# ZabavySign.net
KiCad netlist of a schematic drawn in EAGLE
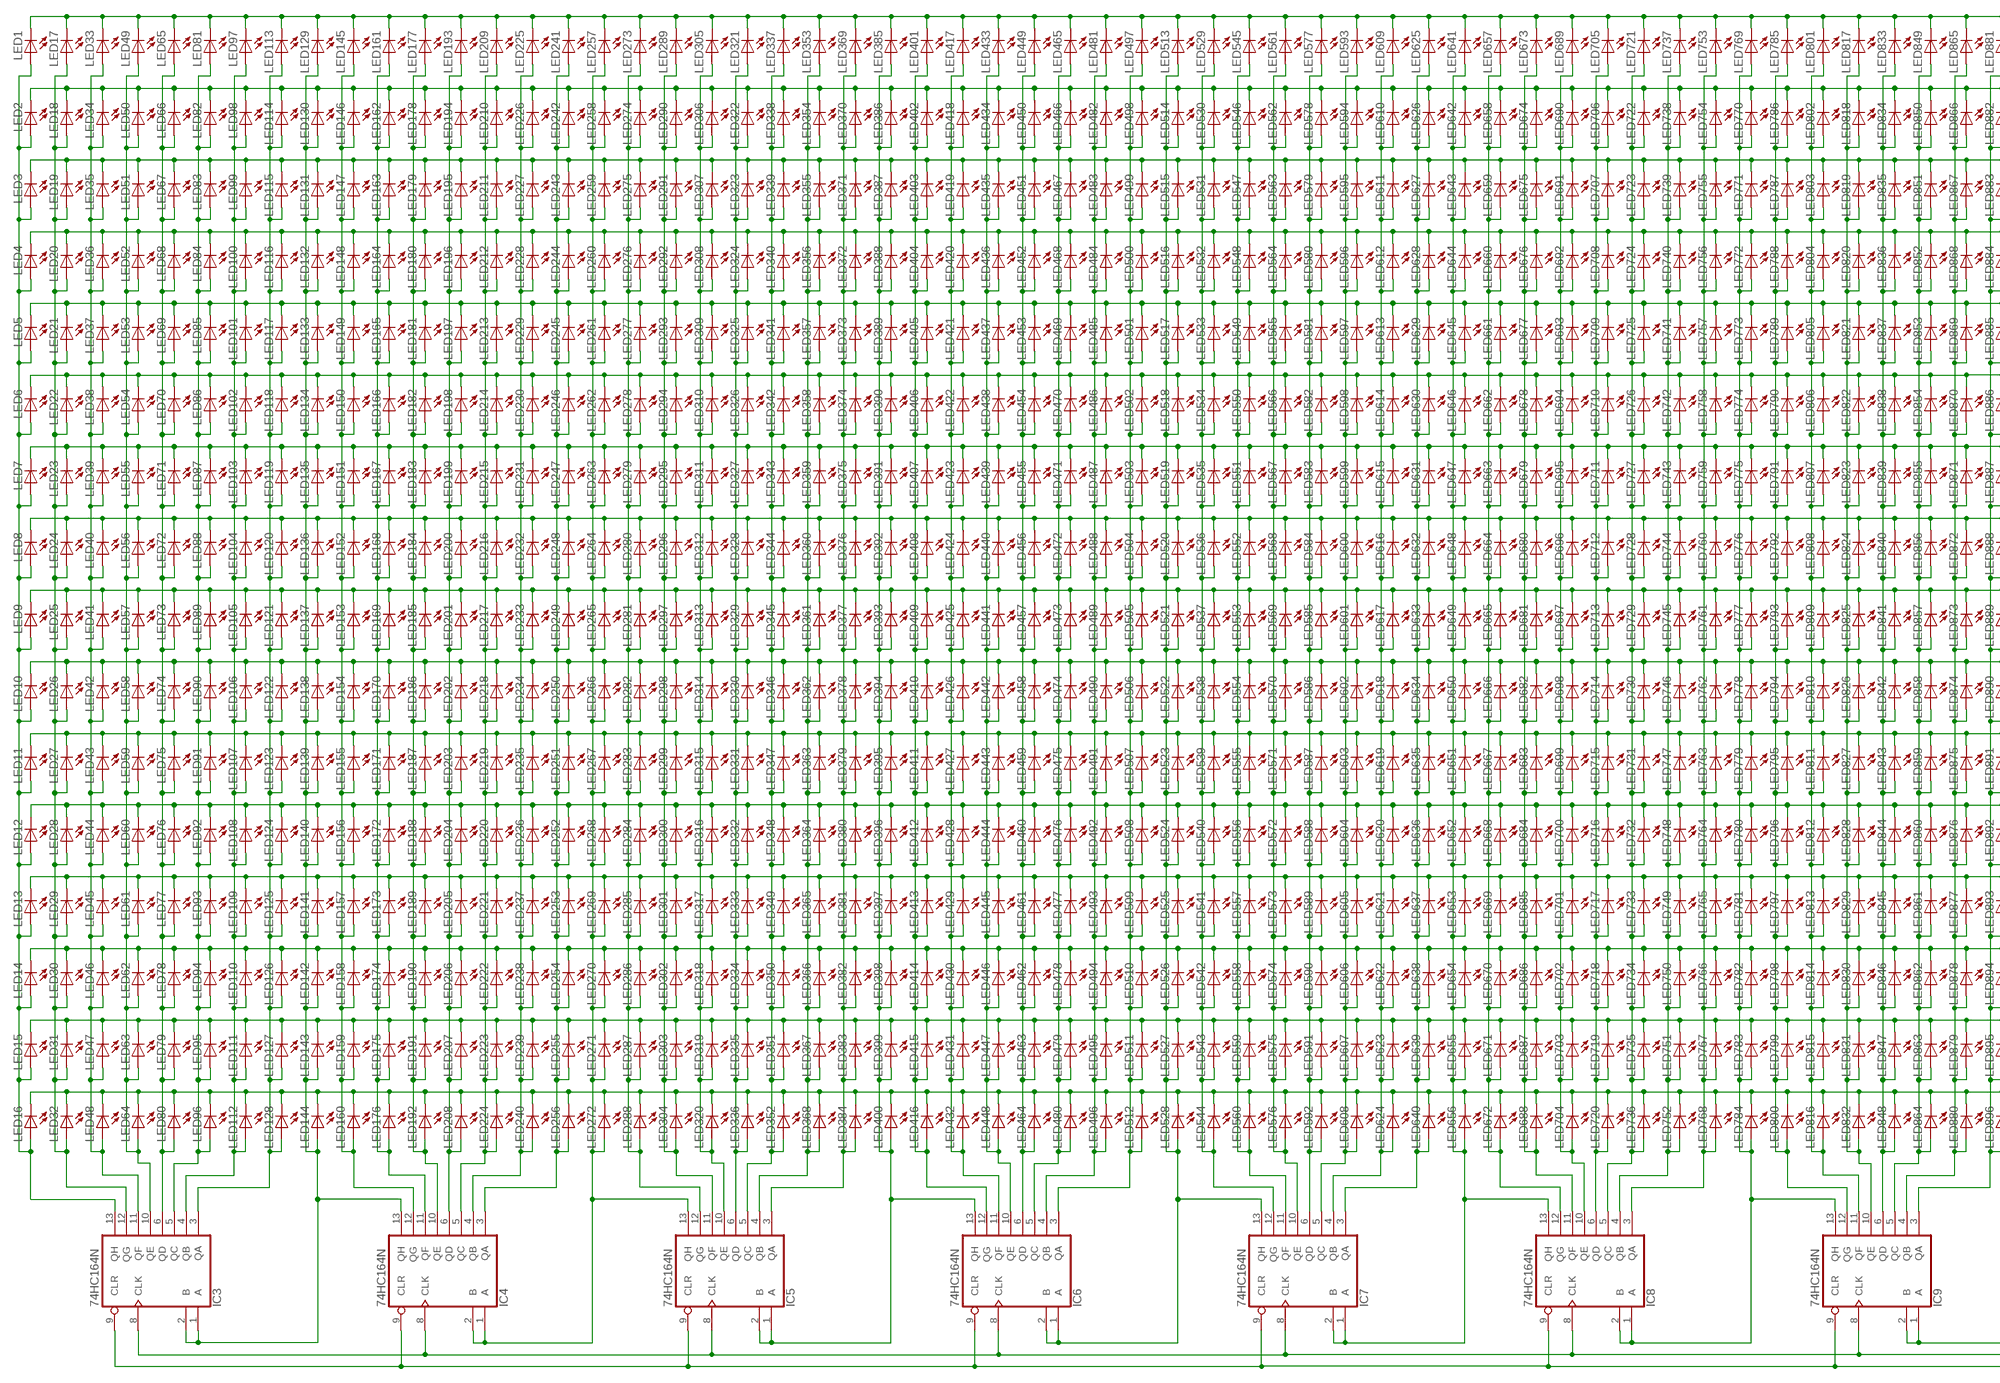
[diagram p0: schematic, sheet 1, part 1 of 2]
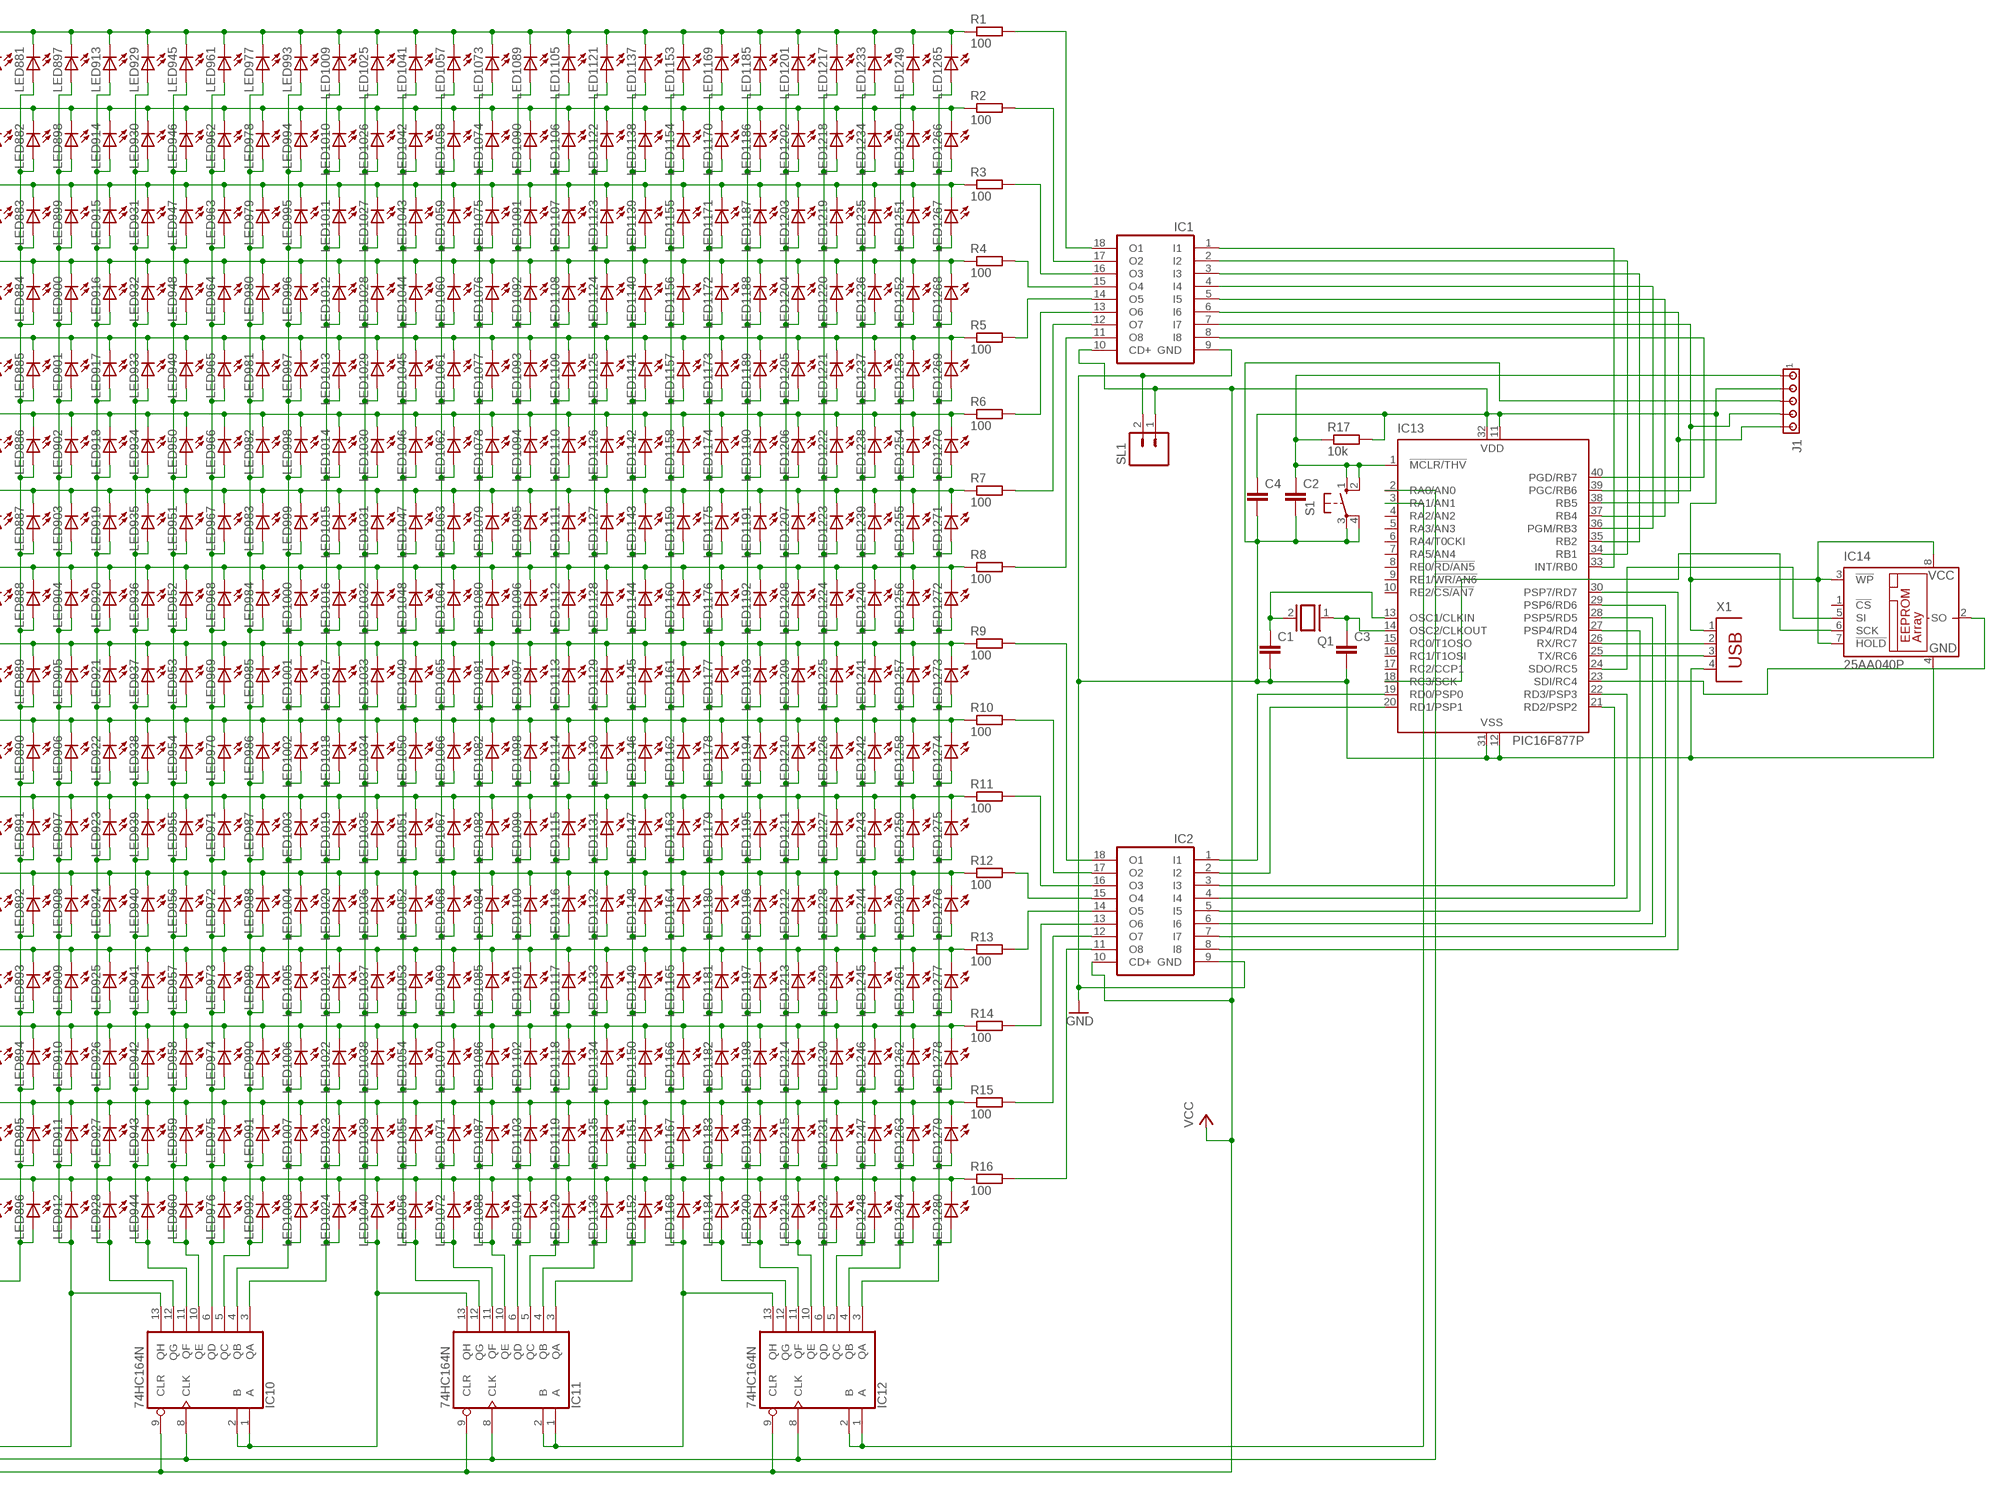
[diagram p1: schematic, sheet 1, part 2 of 2]

(export (version "E")
  (design (tool "Eeschema 10.0.6"))
  (components
    (comp (ref "C1")
      (value "C-EU050-024X044")
      (footprint "eagle-import:C050-024X044")
      (libsource (lib "eagle-import") (part "C-EU050-024X044"))
    )
    (comp (ref "C2")
      (value "C-EU050-024X044")
      (footprint "eagle-import:C050-024X044")
      (libsource (lib "eagle-import") (part "C-EU050-024X044"))
    )
    (comp (ref "C3")
      (value "C-EU050-024X044")
      (footprint "eagle-import:C050-024X044")
      (libsource (lib "eagle-import") (part "C-EU050-024X044"))
    )
    (comp (ref "C4")
      (value "C-EU050-024X044")
      (footprint "eagle-import:C050-024X044")
      (libsource (lib "eagle-import") (part "C-EU050-024X044"))
    )
    (comp (ref "IC1")
      (value "ULN2803A")
      (footprint "eagle-import:DIL18")
      (libsource (lib "eagle-import") (part "ULN2803A"))
    )
    (comp (ref "IC2")
      (value "ULN2803A")
      (footprint "eagle-import:DIL18")
      (libsource (lib "eagle-import") (part "ULN2803A"))
    )
    (comp (ref "IC3")
      (value "74HC164N")
      (footprint "eagle-import:DIL14")
      (libsource (lib "eagle-import") (part "74164NHC"))
    )
    (comp (ref "IC4")
      (value "74HC164N")
      (footprint "eagle-import:DIL14")
      (libsource (lib "eagle-import") (part "74164NHC"))
    )
    (comp (ref "IC5")
      (value "74HC164N")
      (footprint "eagle-import:DIL14")
      (libsource (lib "eagle-import") (part "74164NHC"))
    )
    (comp (ref "IC6")
      (value "74HC164N")
      (footprint "eagle-import:DIL14")
      (libsource (lib "eagle-import") (part "74164NHC"))
    )
    (comp (ref "IC7")
      (value "74HC164N")
      (footprint "eagle-import:DIL14")
      (libsource (lib "eagle-import") (part "74164NHC"))
    )
    (comp (ref "IC8")
      (value "74HC164N")
      (footprint "eagle-import:DIL14")
      (libsource (lib "eagle-import") (part "74164NHC"))
    )
    (comp (ref "IC9")
      (value "74HC164N")
      (footprint "eagle-import:DIL14")
      (libsource (lib "eagle-import") (part "74164NHC"))
    )
    (comp (ref "IC10")
      (value "74HC164N")
      (footprint "eagle-import:DIL14")
      (libsource (lib "eagle-import") (part "74164NHC"))
    )
    (comp (ref "IC11")
      (value "74HC164N")
      (footprint "eagle-import:DIL14")
      (libsource (lib "eagle-import") (part "74164NHC"))
    )
    (comp (ref "IC12")
      (value "74HC164N")
      (footprint "eagle-import:DIL14")
      (libsource (lib "eagle-import") (part "74164NHC"))
    )
    (comp (ref "IC13")
      (value "PIC16F877P")
      (footprint "eagle-import:DIL40")
      (fields (field (name "MF") "MICROCHIP") (field (name "MPN") "PIC16F877-04/P"))
      (libsource (lib "eagle-import") (part "PIC16F87P7"))
    )
    (comp (ref "IC14")
      (value "25AA040P")
      (footprint "eagle-import:DIL8")
      (fields (field (name "MF") "MICROCHIP") (field (name "MPN") "25AA040-I/P"))
      (libsource (lib "eagle-import") (part "25PAA040"))
    )
    (comp (ref "J1")
      (value "MTA05-100")
      (footprint "eagle-import:10X05MTA")
      (libsource (lib "eagle-import") (part "MTA05-100"))
    )
    (comp (ref "LED1")
      (value "LED5MM")
      (footprint "eagle-import:LED5MM")
      (libsource (lib "eagle-import") (part "LED5MM"))
    )
    (comp (ref "LED2")
      (value "LED5MM")
      (footprint "eagle-import:LED5MM")
      (libsource (lib "eagle-import") (part "LED5MM"))
    )
    (comp (ref "LED3")
      (value "LED5MM")
      (footprint "eagle-import:LED5MM")
      (libsource (lib "eagle-import") (part "LED5MM"))
    )
    (comp (ref "LED4")
      (value "LED5MM")
      (footprint "eagle-import:LED5MM")
      (libsource (lib "eagle-import") (part "LED5MM"))
    )
    (comp (ref "LED5")
      (value "LED5MM")
      (footprint "eagle-import:LED5MM")
      (libsource (lib "eagle-import") (part "LED5MM"))
    )
    (comp (ref "LED6")
      (value "LED5MM")
      (footprint "eagle-import:LED5MM")
      (libsource (lib "eagle-import") (part "LED5MM"))
    )
    (comp (ref "LED7")
      (value "LED5MM")
      (footprint "eagle-import:LED5MM")
      (libsource (lib "eagle-import") (part "LED5MM"))
    )
    (comp (ref "LED8")
      (value "LED5MM")
      (footprint "eagle-import:LED5MM")
      (libsource (lib "eagle-import") (part "LED5MM"))
    )
    (comp (ref "LED9")
      (value "LED5MM")
      (footprint "eagle-import:LED5MM")
      (libsource (lib "eagle-import") (part "LED5MM"))
    )
    (comp (ref "LED10")
      (value "LED5MM")
      (footprint "eagle-import:LED5MM")
      (libsource (lib "eagle-import") (part "LED5MM"))
    )
    (comp (ref "LED11")
      (value "LED5MM")
      (footprint "eagle-import:LED5MM")
      (libsource (lib "eagle-import") (part "LED5MM"))
    )
    (comp (ref "LED12")
      (value "LED5MM")
      (footprint "eagle-import:LED5MM")
      (libsource (lib "eagle-import") (part "LED5MM"))
    )
    (comp (ref "LED13")
      (value "LED5MM")
      (footprint "eagle-import:LED5MM")
      (libsource (lib "eagle-import") (part "LED5MM"))
    )
    (comp (ref "LED14")
      (value "LED5MM")
      (footprint "eagle-import:LED5MM")
      (libsource (lib "eagle-import") (part "LED5MM"))
    )
    (comp (ref "LED15")
      (value "LED5MM")
      (footprint "eagle-import:LED5MM")
      (libsource (lib "eagle-import") (part "LED5MM"))
    )
    (comp (ref "LED16")
      (value "LED5MM")
      (footprint "eagle-import:LED5MM")
      (libsource (lib "eagle-import") (part "LED5MM"))
    )
    (comp (ref "LED17")
      (value "LED5MM")
      (footprint "eagle-import:LED5MM")
      (libsource (lib "eagle-import") (part "LED5MM"))
    )
    (comp (ref "LED18")
      (value "LED5MM")
      (footprint "eagle-import:LED5MM")
      (libsource (lib "eagle-import") (part "LED5MM"))
    )
    (comp (ref "LED19")
      (value "LED5MM")
      (footprint "eagle-import:LED5MM")
      (libsource (lib "eagle-import") (part "LED5MM"))
    )
    (comp (ref "LED20")
      (value "LED5MM")
      (footprint "eagle-import:LED5MM")
      (libsource (lib "eagle-import") (part "LED5MM"))
    )
    (comp (ref "LED21")
      (value "LED5MM")
      (footprint "eagle-import:LED5MM")
      (libsource (lib "eagle-import") (part "LED5MM"))
    )
    (comp (ref "LED22")
      (value "LED5MM")
      (footprint "eagle-import:LED5MM")
      (libsource (lib "eagle-import") (part "LED5MM"))
    )
    (comp (ref "LED23")
      (value "LED5MM")
      (footprint "eagle-import:LED5MM")
      (libsource (lib "eagle-import") (part "LED5MM"))
    )
    (comp (ref "LED24")
      (value "LED5MM")
      (footprint "eagle-import:LED5MM")
      (libsource (lib "eagle-import") (part "LED5MM"))
    )
    (comp (ref "LED25")
      (value "LED5MM")
      (footprint "eagle-import:LED5MM")
      (libsource (lib "eagle-import") (part "LED5MM"))
    )
    (comp (ref "LED26")
      (value "LED5MM")
      (footprint "eagle-import:LED5MM")
      (libsource (lib "eagle-import") (part "LED5MM"))
    )
    (comp (ref "LED27")
      (value "LED5MM")
      (footprint "eagle-import:LED5MM")
      (libsource (lib "eagle-import") (part "LED5MM"))
    )
    (comp (ref "LED28")
      (value "LED5MM")
      (footprint "eagle-import:LED5MM")
      (libsource (lib "eagle-import") (part "LED5MM"))
    )
    (comp (ref "LED29")
      (value "LED5MM")
      (footprint "eagle-import:LED5MM")
      (libsource (lib "eagle-import") (part "LED5MM"))
    )
    (comp (ref "LED30")
      (value "LED5MM")
      (footprint "eagle-import:LED5MM")
      (libsource (lib "eagle-import") (part "LED5MM"))
    )
    (comp (ref "LED31")
      (value "LED5MM")
      (footprint "eagle-import:LED5MM")
      (libsource (lib "eagle-import") (part "LED5MM"))
    )
    (comp (ref "LED32")
      (value "LED5MM")
      (footprint "eagle-import:LED5MM")
      (libsource (lib "eagle-import") (part "LED5MM"))
    )
    (comp (ref "LED33")
      (value "LED5MM")
      (footprint "eagle-import:LED5MM")
      (libsource (lib "eagle-import") (part "LED5MM"))
    )
    (comp (ref "LED34")
      (value "LED5MM")
      (footprint "eagle-import:LED5MM")
      (libsource (lib "eagle-import") (part "LED5MM"))
    )
    (comp (ref "LED35")
      (value "LED5MM")
      (footprint "eagle-import:LED5MM")
      (libsource (lib "eagle-import") (part "LED5MM"))
    )
    (comp (ref "LED36")
      (value "LED5MM")
      (footprint "eagle-import:LED5MM")
      (libsource (lib "eagle-import") (part "LED5MM"))
    )
    (comp (ref "LED37")
      (value "LED5MM")
      (footprint "eagle-import:LED5MM")
      (libsource (lib "eagle-import") (part "LED5MM"))
    )
    (comp (ref "LED38")
      (value "LED5MM")
      (footprint "eagle-import:LED5MM")
      (libsource (lib "eagle-import") (part "LED5MM"))
    )
    (comp (ref "LED39")
      (value "LED5MM")
      (footprint "eagle-import:LED5MM")
      (libsource (lib "eagle-import") (part "LED5MM"))
    )
    (comp (ref "LED40")
      (value "LED5MM")
      (footprint "eagle-import:LED5MM")
      (libsource (lib "eagle-import") (part "LED5MM"))
    )
    (comp (ref "LED41")
      (value "LED5MM")
      (footprint "eagle-import:LED5MM")
      (libsource (lib "eagle-import") (part "LED5MM"))
    )
    (comp (ref "LED42")
      (value "LED5MM")
      (footprint "eagle-import:LED5MM")
      (libsource (lib "eagle-import") (part "LED5MM"))
    )
    (comp (ref "LED43")
      (value "LED5MM")
      (footprint "eagle-import:LED5MM")
      (libsource (lib "eagle-import") (part "LED5MM"))
    )
    (comp (ref "LED44")
      (value "LED5MM")
      (footprint "eagle-import:LED5MM")
      (libsource (lib "eagle-import") (part "LED5MM"))
    )
    (comp (ref "LED45")
      (value "LED5MM")
      (footprint "eagle-import:LED5MM")
      (libsource (lib "eagle-import") (part "LED5MM"))
    )
    (comp (ref "LED46")
      (value "LED5MM")
      (footprint "eagle-import:LED5MM")
      (libsource (lib "eagle-import") (part "LED5MM"))
    )
    (comp (ref "LED47")
      (value "LED5MM")
      (footprint "eagle-import:LED5MM")
      (libsource (lib "eagle-import") (part "LED5MM"))
    )
    (comp (ref "LED48")
      (value "LED5MM")
      (footprint "eagle-import:LED5MM")
      (libsource (lib "eagle-import") (part "LED5MM"))
    )
    (comp (ref "LED49")
      (value "LED5MM")
      (footprint "eagle-import:LED5MM")
      (libsource (lib "eagle-import") (part "LED5MM"))
    )
    (comp (ref "LED50")
      (value "LED5MM")
      (footprint "eagle-import:LED5MM")
      (libsource (lib "eagle-import") (part "LED5MM"))
    )
    (comp (ref "LED51")
      (value "LED5MM")
      (footprint "eagle-import:LED5MM")
      (libsource (lib "eagle-import") (part "LED5MM"))
    )
    (comp (ref "LED52")
      (value "LED5MM")
      (footprint "eagle-import:LED5MM")
      (libsource (lib "eagle-import") (part "LED5MM"))
    )
    (comp (ref "LED53")
      (value "LED5MM")
      (footprint "eagle-import:LED5MM")
      (libsource (lib "eagle-import") (part "LED5MM"))
    )
    (comp (ref "LED54")
      (value "LED5MM")
      (footprint "eagle-import:LED5MM")
      (libsource (lib "eagle-import") (part "LED5MM"))
    )
    (comp (ref "LED55")
      (value "LED5MM")
      (footprint "eagle-import:LED5MM")
      (libsource (lib "eagle-import") (part "LED5MM"))
    )
    (comp (ref "LED56")
      (value "LED5MM")
      (footprint "eagle-import:LED5MM")
      (libsource (lib "eagle-import") (part "LED5MM"))
    )
    (comp (ref "LED57")
      (value "LED5MM")
      (footprint "eagle-import:LED5MM")
      (libsource (lib "eagle-import") (part "LED5MM"))
    )
    (comp (ref "LED58")
      (value "LED5MM")
      (footprint "eagle-import:LED5MM")
      (libsource (lib "eagle-import") (part "LED5MM"))
    )
    (comp (ref "LED59")
      (value "LED5MM")
      (footprint "eagle-import:LED5MM")
      (libsource (lib "eagle-import") (part "LED5MM"))
    )
    (comp (ref "LED60")
      (value "LED5MM")
      (footprint "eagle-import:LED5MM")
      (libsource (lib "eagle-import") (part "LED5MM"))
    )
    (comp (ref "LED61")
      (value "LED5MM")
      (footprint "eagle-import:LED5MM")
      (libsource (lib "eagle-import") (part "LED5MM"))
    )
    (comp (ref "LED62")
      (value "LED5MM")
      (footprint "eagle-import:LED5MM")
      (libsource (lib "eagle-import") (part "LED5MM"))
    )
    (comp (ref "LED63")
      (value "LED5MM")
      (footprint "eagle-import:LED5MM")
      (libsource (lib "eagle-import") (part "LED5MM"))
    )
    (comp (ref "LED64")
      (value "LED5MM")
      (footprint "eagle-import:LED5MM")
      (libsource (lib "eagle-import") (part "LED5MM"))
    )
    (comp (ref "LED65")
      (value "LED5MM")
      (footprint "eagle-import:LED5MM")
      (libsource (lib "eagle-import") (part "LED5MM"))
    )
    (comp (ref "LED66")
      (value "LED5MM")
      (footprint "eagle-import:LED5MM")
      (libsource (lib "eagle-import") (part "LED5MM"))
    )
    (comp (ref "LED67")
      (value "LED5MM")
      (footprint "eagle-import:LED5MM")
      (libsource (lib "eagle-import") (part "LED5MM"))
    )
    (comp (ref "LED68")
      (value "LED5MM")
      (footprint "eagle-import:LED5MM")
      (libsource (lib "eagle-import") (part "LED5MM"))
    )
    (comp (ref "LED69")
      (value "LED5MM")
      (footprint "eagle-import:LED5MM")
      (libsource (lib "eagle-import") (part "LED5MM"))
    )
    (comp (ref "LED70")
      (value "LED5MM")
      (footprint "eagle-import:LED5MM")
      (libsource (lib "eagle-import") (part "LED5MM"))
    )
    (comp (ref "LED71")
      (value "LED5MM")
      (footprint "eagle-import:LED5MM")
      (libsource (lib "eagle-import") (part "LED5MM"))
    )
    (comp (ref "LED72")
      (value "LED5MM")
      (footprint "eagle-import:LED5MM")
      (libsource (lib "eagle-import") (part "LED5MM"))
    )
    (comp (ref "LED73")
      (value "LED5MM")
      (footprint "eagle-import:LED5MM")
      (libsource (lib "eagle-import") (part "LED5MM"))
    )
    (comp (ref "LED74")
      (value "LED5MM")
      (footprint "eagle-import:LED5MM")
      (libsource (lib "eagle-import") (part "LED5MM"))
    )
    (comp (ref "LED75")
      (value "LED5MM")
      (footprint "eagle-import:LED5MM")
      (libsource (lib "eagle-import") (part "LED5MM"))
    )
    (comp (ref "LED76")
      (value "LED5MM")
      (footprint "eagle-import:LED5MM")
      (libsource (lib "eagle-import") (part "LED5MM"))
    )
    (comp (ref "LED77")
      (value "LED5MM")
      (footprint "eagle-import:LED5MM")
      (libsource (lib "eagle-import") (part "LED5MM"))
    )
    (comp (ref "LED78")
      (value "LED5MM")
      (footprint "eagle-import:LED5MM")
      (libsource (lib "eagle-import") (part "LED5MM"))
    )
    (comp (ref "LED79")
      (value "LED5MM")
      (footprint "eagle-import:LED5MM")
      (libsource (lib "eagle-import") (part "LED5MM"))
    )
    (comp (ref "LED80")
      (value "LED5MM")
      (footprint "eagle-import:LED5MM")
      (libsource (lib "eagle-import") (part "LED5MM"))
    )
    (comp (ref "LED81")
      (value "LED5MM")
      (footprint "eagle-import:LED5MM")
      (libsource (lib "eagle-import") (part "LED5MM"))
    )
    (comp (ref "LED82")
      (value "LED5MM")
      (footprint "eagle-import:LED5MM")
      (libsource (lib "eagle-import") (part "LED5MM"))
    )
    (comp (ref "LED83")
      (value "LED5MM")
      (footprint "eagle-import:LED5MM")
      (libsource (lib "eagle-import") (part "LED5MM"))
    )
    (comp (ref "LED84")
      (value "LED5MM")
      (footprint "eagle-import:LED5MM")
      (libsource (lib "eagle-import") (part "LED5MM"))
    )
    (comp (ref "LED85")
      (value "LED5MM")
      (footprint "eagle-import:LED5MM")
      (libsource (lib "eagle-import") (part "LED5MM"))
    )
    (comp (ref "LED86")
      (value "LED5MM")
      (footprint "eagle-import:LED5MM")
      (libsource (lib "eagle-import") (part "LED5MM"))
    )
    (comp (ref "LED87")
      (value "LED5MM")
      (footprint "eagle-import:LED5MM")
      (libsource (lib "eagle-import") (part "LED5MM"))
    )
    (comp (ref "LED88")
      (value "LED5MM")
      (footprint "eagle-import:LED5MM")
      (libsource (lib "eagle-import") (part "LED5MM"))
    )
    (comp (ref "LED89")
      (value "LED5MM")
      (footprint "eagle-import:LED5MM")
      (libsource (lib "eagle-import") (part "LED5MM"))
    )
    (comp (ref "LED90")
      (value "LED5MM")
      (footprint "eagle-import:LED5MM")
      (libsource (lib "eagle-import") (part "LED5MM"))
    )
    (comp (ref "LED91")
      (value "LED5MM")
      (footprint "eagle-import:LED5MM")
      (libsource (lib "eagle-import") (part "LED5MM"))
    )
    (comp (ref "LED92")
      (value "LED5MM")
      (footprint "eagle-import:LED5MM")
      (libsource (lib "eagle-import") (part "LED5MM"))
    )
    (comp (ref "LED93")
      (value "LED5MM")
      (footprint "eagle-import:LED5MM")
      (libsource (lib "eagle-import") (part "LED5MM"))
    )
    (comp (ref "LED94")
      (value "LED5MM")
      (footprint "eagle-import:LED5MM")
      (libsource (lib "eagle-import") (part "LED5MM"))
    )
    (comp (ref "LED95")
      (value "LED5MM")
      (footprint "eagle-import:LED5MM")
      (libsource (lib "eagle-import") (part "LED5MM"))
    )
    (comp (ref "LED96")
      (value "LED5MM")
      (footprint "eagle-import:LED5MM")
      (libsource (lib "eagle-import") (part "LED5MM"))
    )
    (comp (ref "LED97")
      (value "LED5MM")
      (footprint "eagle-import:LED5MM")
      (libsource (lib "eagle-import") (part "LED5MM"))
    )
    (comp (ref "LED98")
      (value "LED5MM")
      (footprint "eagle-import:LED5MM")
      (libsource (lib "eagle-import") (part "LED5MM"))
    )
    (comp (ref "LED99")
      (value "LED5MM")
      (footprint "eagle-import:LED5MM")
      (libsource (lib "eagle-import") (part "LED5MM"))
    )
    (comp (ref "LED100")
      (value "LED5MM")
      (footprint "eagle-import:LED5MM")
      (libsource (lib "eagle-import") (part "LED5MM"))
    )
    (comp (ref "LED101")
      (value "LED5MM")
      (footprint "eagle-import:LED5MM")
      (libsource (lib "eagle-import") (part "LED5MM"))
    )
    (comp (ref "LED102")
      (value "LED5MM")
      (footprint "eagle-import:LED5MM")
      (libsource (lib "eagle-import") (part "LED5MM"))
    )
    (comp (ref "LED103")
      (value "LED5MM")
      (footprint "eagle-import:LED5MM")
      (libsource (lib "eagle-import") (part "LED5MM"))
    )
    (comp (ref "LED104")
      (value "LED5MM")
      (footprint "eagle-import:LED5MM")
      (libsource (lib "eagle-import") (part "LED5MM"))
    )
    (comp (ref "LED105")
      (value "LED5MM")
      (footprint "eagle-import:LED5MM")
      (libsource (lib "eagle-import") (part "LED5MM"))
    )
    (comp (ref "LED106")
      (value "LED5MM")
      (footprint "eagle-import:LED5MM")
      (libsource (lib "eagle-import") (part "LED5MM"))
    )
    (comp (ref "LED107")
      (value "LED5MM")
      (footprint "eagle-import:LED5MM")
      (libsource (lib "eagle-import") (part "LED5MM"))
    )
    (comp (ref "LED108")
      (value "LED5MM")
      (footprint "eagle-import:LED5MM")
      (libsource (lib "eagle-import") (part "LED5MM"))
    )
    (comp (ref "LED109")
      (value "LED5MM")
      (footprint "eagle-import:LED5MM")
      (libsource (lib "eagle-import") (part "LED5MM"))
    )
    (comp (ref "LED110")
      (value "LED5MM")
      (footprint "eagle-import:LED5MM")
      (libsource (lib "eagle-import") (part "LED5MM"))
    )
    (comp (ref "LED111")
      (value "LED5MM")
      (footprint "eagle-import:LED5MM")
      (libsource (lib "eagle-import") (part "LED5MM"))
    )
    (comp (ref "LED112")
      (value "LED5MM")
      (footprint "eagle-import:LED5MM")
      (libsource (lib "eagle-import") (part "LED5MM"))
    )
    (comp (ref "LED113")
      (value "LED5MM")
      (footprint "eagle-import:LED5MM")
      (libsource (lib "eagle-import") (part "LED5MM"))
    )
    (comp (ref "LED114")
      (value "LED5MM")
      (footprint "eagle-import:LED5MM")
      (libsource (lib "eagle-import") (part "LED5MM"))
    )
    (comp (ref "LED115")
      (value "LED5MM")
      (footprint "eagle-import:LED5MM")
      (libsource (lib "eagle-import") (part "LED5MM"))
    )
    (comp (ref "LED116")
      (value "LED5MM")
      (footprint "eagle-import:LED5MM")
      (libsource (lib "eagle-import") (part "LED5MM"))
    )
    (comp (ref "LED117")
      (value "LED5MM")
      (footprint "eagle-import:LED5MM")
      (libsource (lib "eagle-import") (part "LED5MM"))
    )
    (comp (ref "LED118")
      (value "LED5MM")
      (footprint "eagle-import:LED5MM")
      (libsource (lib "eagle-import") (part "LED5MM"))
    )
    (comp (ref "LED119")
      (value "LED5MM")
      (footprint "eagle-import:LED5MM")
      (libsource (lib "eagle-import") (part "LED5MM"))
    )
    (comp (ref "LED120")
      (value "LED5MM")
      (footprint "eagle-import:LED5MM")
      (libsource (lib "eagle-import") (part "LED5MM"))
    )
    (comp (ref "LED121")
      (value "LED5MM")
      (footprint "eagle-import:LED5MM")
      (libsource (lib "eagle-import") (part "LED5MM"))
    )
    (comp (ref "LED122")
      (value "LED5MM")
      (footprint "eagle-import:LED5MM")
      (libsource (lib "eagle-import") (part "LED5MM"))
    )
    (comp (ref "LED123")
      (value "LED5MM")
      (footprint "eagle-import:LED5MM")
      (libsource (lib "eagle-import") (part "LED5MM"))
    )
    (comp (ref "LED124")
      (value "LED5MM")
      (footprint "eagle-import:LED5MM")
      (libsource (lib "eagle-import") (part "LED5MM"))
    )
    (comp (ref "LED125")
      (value "LED5MM")
      (footprint "eagle-import:LED5MM")
      (libsource (lib "eagle-import") (part "LED5MM"))
    )
    (comp (ref "LED126")
      (value "LED5MM")
      (footprint "eagle-import:LED5MM")
      (libsource (lib "eagle-import") (part "LED5MM"))
    )
    (comp (ref "LED127")
      (value "LED5MM")
      (footprint "eagle-import:LED5MM")
      (libsource (lib "eagle-import") (part "LED5MM"))
    )
    (comp (ref "LED128")
      (value "LED5MM")
      (footprint "eagle-import:LED5MM")
      (libsource (lib "eagle-import") (part "LED5MM"))
    )
    (comp (ref "LED129")
      (value "LED5MM")
      (footprint "eagle-import:LED5MM")
      (libsource (lib "eagle-import") (part "LED5MM"))
    )
    (comp (ref "LED130")
      (value "LED5MM")
      (footprint "eagle-import:LED5MM")
      (libsource (lib "eagle-import") (part "LED5MM"))
    )
    (comp (ref "LED131")
      (value "LED5MM")
      (footprint "eagle-import:LED5MM")
      (libsource (lib "eagle-import") (part "LED5MM"))
    )
    (comp (ref "LED132")
      (value "LED5MM")
      (footprint "eagle-import:LED5MM")
      (libsource (lib "eagle-import") (part "LED5MM"))
    )
    (comp (ref "LED133")
      (value "LED5MM")
      (footprint "eagle-import:LED5MM")
      (libsource (lib "eagle-import") (part "LED5MM"))
    )
    (comp (ref "LED134")
      (value "LED5MM")
      (footprint "eagle-import:LED5MM")
      (libsource (lib "eagle-import") (part "LED5MM"))
    )
    (comp (ref "LED135")
      (value "LED5MM")
      (footprint "eagle-import:LED5MM")
      (libsource (lib "eagle-import") (part "LED5MM"))
    )
    (comp (ref "LED136")
      (value "LED5MM")
      (footprint "eagle-import:LED5MM")
      (libsource (lib "eagle-import") (part "LED5MM"))
    )
    (comp (ref "LED137")
      (value "LED5MM")
      (footprint "eagle-import:LED5MM")
      (libsource (lib "eagle-import") (part "LED5MM"))
    )
    (comp (ref "LED138")
      (value "LED5MM")
      (footprint "eagle-import:LED5MM")
      (libsource (lib "eagle-import") (part "LED5MM"))
    )
    (comp (ref "LED139")
      (value "LED5MM")
      (footprint "eagle-import:LED5MM")
      (libsource (lib "eagle-import") (part "LED5MM"))
    )
    (comp (ref "LED140")
      (value "LED5MM")
      (footprint "eagle-import:LED5MM")
      (libsource (lib "eagle-import") (part "LED5MM"))
    )
    (comp (ref "LED141")
      (value "LED5MM")
      (footprint "eagle-import:LED5MM")
      (libsource (lib "eagle-import") (part "LED5MM"))
    )
    (comp (ref "LED142")
      (value "LED5MM")
      (footprint "eagle-import:LED5MM")
      (libsource (lib "eagle-import") (part "LED5MM"))
    )
    (comp (ref "LED143")
      (value "LED5MM")
      (footprint "eagle-import:LED5MM")
      (libsource (lib "eagle-import") (part "LED5MM"))
    )
    (comp (ref "LED144")
      (value "LED5MM")
      (footprint "eagle-import:LED5MM")
      (libsource (lib "eagle-import") (part "LED5MM"))
    )
    (comp (ref "LED145")
      (value "LED5MM")
      (footprint "eagle-import:LED5MM")
      (libsource (lib "eagle-import") (part "LED5MM"))
    )
    (comp (ref "LED146")
      (value "LED5MM")
      (footprint "eagle-import:LED5MM")
      (libsource (lib "eagle-import") (part "LED5MM"))
    )
    (comp (ref "LED147")
      (value "LED5MM")
      (footprint "eagle-import:LED5MM")
      (libsource (lib "eagle-import") (part "LED5MM"))
    )
    (comp (ref "LED148")
      (value "LED5MM")
      (footprint "eagle-import:LED5MM")
      (libsource (lib "eagle-import") (part "LED5MM"))
    )
    (comp (ref "LED149")
      (value "LED5MM")
      (footprint "eagle-import:LED5MM")
      (libsource (lib "eagle-import") (part "LED5MM"))
    )
    (comp (ref "LED150")
      (value "LED5MM")
      (footprint "eagle-import:LED5MM")
      (libsource (lib "eagle-import") (part "LED5MM"))
    )
    (comp (ref "LED151")
      (value "LED5MM")
      (footprint "eagle-import:LED5MM")
      (libsource (lib "eagle-import") (part "LED5MM"))
    )
    (comp (ref "LED152")
      (value "LED5MM")
      (footprint "eagle-import:LED5MM")
      (libsource (lib "eagle-import") (part "LED5MM"))
    )
    (comp (ref "LED153")
      (value "LED5MM")
      (footprint "eagle-import:LED5MM")
      (libsource (lib "eagle-import") (part "LED5MM"))
    )
    (comp (ref "LED154")
      (value "LED5MM")
      (footprint "eagle-import:LED5MM")
      (libsource (lib "eagle-import") (part "LED5MM"))
    )
    (comp (ref "LED155")
      (value "LED5MM")
      (footprint "eagle-import:LED5MM")
      (libsource (lib "eagle-import") (part "LED5MM"))
    )
    (comp (ref "LED156")
      (value "LED5MM")
      (footprint "eagle-import:LED5MM")
      (libsource (lib "eagle-import") (part "LED5MM"))
    )
    (comp (ref "LED157")
      (value "LED5MM")
      (footprint "eagle-import:LED5MM")
      (libsource (lib "eagle-import") (part "LED5MM"))
    )
    (comp (ref "LED158")
      (value "LED5MM")
      (footprint "eagle-import:LED5MM")
      (libsource (lib "eagle-import") (part "LED5MM"))
    )
    (comp (ref "LED159")
      (value "LED5MM")
      (footprint "eagle-import:LED5MM")
      (libsource (lib "eagle-import") (part "LED5MM"))
    )
    (comp (ref "LED160")
      (value "LED5MM")
      (footprint "eagle-import:LED5MM")
      (libsource (lib "eagle-import") (part "LED5MM"))
    )
    (comp (ref "LED161")
      (value "LED5MM")
      (footprint "eagle-import:LED5MM")
      (libsource (lib "eagle-import") (part "LED5MM"))
    )
    (comp (ref "LED162")
      (value "LED5MM")
      (footprint "eagle-import:LED5MM")
      (libsource (lib "eagle-import") (part "LED5MM"))
    )
    (comp (ref "LED163")
      (value "LED5MM")
      (footprint "eagle-import:LED5MM")
      (libsource (lib "eagle-import") (part "LED5MM"))
    )
    (comp (ref "LED164")
      (value "LED5MM")
      (footprint "eagle-import:LED5MM")
      (libsource (lib "eagle-import") (part "LED5MM"))
    )
    (comp (ref "LED165")
      (value "LED5MM")
      (footprint "eagle-import:LED5MM")
      (libsource (lib "eagle-import") (part "LED5MM"))
    )
    (comp (ref "LED166")
      (value "LED5MM")
      (footprint "eagle-import:LED5MM")
      (libsource (lib "eagle-import") (part "LED5MM"))
    )
    (comp (ref "LED167")
      (value "LED5MM")
      (footprint "eagle-import:LED5MM")
      (libsource (lib "eagle-import") (part "LED5MM"))
    )
    (comp (ref "LED168")
      (value "LED5MM")
      (footprint "eagle-import:LED5MM")
      (libsource (lib "eagle-import") (part "LED5MM"))
    )
    (comp (ref "LED169")
      (value "LED5MM")
      (footprint "eagle-import:LED5MM")
      (libsource (lib "eagle-import") (part "LED5MM"))
    )
    (comp (ref "LED170")
      (value "LED5MM")
      (footprint "eagle-import:LED5MM")
      (libsource (lib "eagle-import") (part "LED5MM"))
    )
    (comp (ref "LED171")
      (value "LED5MM")
      (footprint "eagle-import:LED5MM")
      (libsource (lib "eagle-import") (part "LED5MM"))
    )
    (comp (ref "LED172")
      (value "LED5MM")
      (footprint "eagle-import:LED5MM")
      (libsource (lib "eagle-import") (part "LED5MM"))
    )
    (comp (ref "LED173")
      (value "LED5MM")
      (footprint "eagle-import:LED5MM")
      (libsource (lib "eagle-import") (part "LED5MM"))
    )
    (comp (ref "LED174")
      (value "LED5MM")
      (footprint "eagle-import:LED5MM")
      (libsource (lib "eagle-import") (part "LED5MM"))
    )
    (comp (ref "LED175")
      (value "LED5MM")
      (footprint "eagle-import:LED5MM")
      (libsource (lib "eagle-import") (part "LED5MM"))
    )
    (comp (ref "LED176")
      (value "LED5MM")
      (footprint "eagle-import:LED5MM")
      (libsource (lib "eagle-import") (part "LED5MM"))
    )
    (comp (ref "LED177")
      (value "LED5MM")
      (footprint "eagle-import:LED5MM")
      (libsource (lib "eagle-import") (part "LED5MM"))
    )
    (comp (ref "LED178")
      (value "LED5MM")
      (footprint "eagle-import:LED5MM")
      (libsource (lib "eagle-import") (part "LED5MM"))
    )
    (comp (ref "LED179")
      (value "LED5MM")
      (footprint "eagle-import:LED5MM")
      (libsource (lib "eagle-import") (part "LED5MM"))
    )
    (comp (ref "LED180")
      (value "LED5MM")
      (footprint "eagle-import:LED5MM")
      (libsource (lib "eagle-import") (part "LED5MM"))
    )
    (comp (ref "LED181")
      (value "LED5MM")
      (footprint "eagle-import:LED5MM")
      (libsource (lib "eagle-import") (part "LED5MM"))
    )
    (comp (ref "LED182")
      (value "LED5MM")
      (footprint "eagle-import:LED5MM")
      (libsource (lib "eagle-import") (part "LED5MM"))
    )
    (comp (ref "LED183")
      (value "LED5MM")
      (footprint "eagle-import:LED5MM")
      (libsource (lib "eagle-import") (part "LED5MM"))
    )
    (comp (ref "LED184")
      (value "LED5MM")
      (footprint "eagle-import:LED5MM")
      (libsource (lib "eagle-import") (part "LED5MM"))
    )
    (comp (ref "LED185")
      (value "LED5MM")
      (footprint "eagle-import:LED5MM")
      (libsource (lib "eagle-import") (part "LED5MM"))
    )
    (comp (ref "LED186")
      (value "LED5MM")
      (footprint "eagle-import:LED5MM")
      (libsource (lib "eagle-import") (part "LED5MM"))
    )
    (comp (ref "LED187")
      (value "LED5MM")
      (footprint "eagle-import:LED5MM")
      (libsource (lib "eagle-import") (part "LED5MM"))
    )
    (comp (ref "LED188")
      (value "LED5MM")
      (footprint "eagle-import:LED5MM")
      (libsource (lib "eagle-import") (part "LED5MM"))
    )
    (comp (ref "LED189")
      (value "LED5MM")
      (footprint "eagle-import:LED5MM")
      (libsource (lib "eagle-import") (part "LED5MM"))
    )
    (comp (ref "LED190")
      (value "LED5MM")
      (footprint "eagle-import:LED5MM")
      (libsource (lib "eagle-import") (part "LED5MM"))
    )
    (comp (ref "LED191")
      (value "LED5MM")
      (footprint "eagle-import:LED5MM")
      (libsource (lib "eagle-import") (part "LED5MM"))
    )
    (comp (ref "LED192")
      (value "LED5MM")
      (footprint "eagle-import:LED5MM")
      (libsource (lib "eagle-import") (part "LED5MM"))
    )
    (comp (ref "LED193")
      (value "LED5MM")
      (footprint "eagle-import:LED5MM")
      (libsource (lib "eagle-import") (part "LED5MM"))
    )
    (comp (ref "LED194")
      (value "LED5MM")
      (footprint "eagle-import:LED5MM")
      (libsource (lib "eagle-import") (part "LED5MM"))
    )
    (comp (ref "LED195")
      (value "LED5MM")
      (footprint "eagle-import:LED5MM")
      (libsource (lib "eagle-import") (part "LED5MM"))
    )
    (comp (ref "LED196")
      (value "LED5MM")
      (footprint "eagle-import:LED5MM")
      (libsource (lib "eagle-import") (part "LED5MM"))
    )
    (comp (ref "LED197")
      (value "LED5MM")
      (footprint "eagle-import:LED5MM")
      (libsource (lib "eagle-import") (part "LED5MM"))
    )
    (comp (ref "LED198")
      (value "LED5MM")
      (footprint "eagle-import:LED5MM")
      (libsource (lib "eagle-import") (part "LED5MM"))
    )
    (comp (ref "LED199")
      (value "LED5MM")
      (footprint "eagle-import:LED5MM")
      (libsource (lib "eagle-import") (part "LED5MM"))
    )
    (comp (ref "LED200")
      (value "LED5MM")
      (footprint "eagle-import:LED5MM")
      (libsource (lib "eagle-import") (part "LED5MM"))
    )
    (comp (ref "LED201")
      (value "LED5MM")
      (footprint "eagle-import:LED5MM")
      (libsource (lib "eagle-import") (part "LED5MM"))
    )
    (comp (ref "LED202")
      (value "LED5MM")
      (footprint "eagle-import:LED5MM")
      (libsource (lib "eagle-import") (part "LED5MM"))
    )
    (comp (ref "LED203")
      (value "LED5MM")
      (footprint "eagle-import:LED5MM")
      (libsource (lib "eagle-import") (part "LED5MM"))
    )
    (comp (ref "LED204")
      (value "LED5MM")
      (footprint "eagle-import:LED5MM")
      (libsource (lib "eagle-import") (part "LED5MM"))
    )
    (comp (ref "LED205")
      (value "LED5MM")
      (footprint "eagle-import:LED5MM")
      (libsource (lib "eagle-import") (part "LED5MM"))
    )
    (comp (ref "LED206")
      (value "LED5MM")
      (footprint "eagle-import:LED5MM")
      (libsource (lib "eagle-import") (part "LED5MM"))
    )
    (comp (ref "LED207")
      (value "LED5MM")
      (footprint "eagle-import:LED5MM")
      (libsource (lib "eagle-import") (part "LED5MM"))
    )
    (comp (ref "LED208")
      (value "LED5MM")
      (footprint "eagle-import:LED5MM")
      (libsource (lib "eagle-import") (part "LED5MM"))
    )
    (comp (ref "LED209")
      (value "LED5MM")
      (footprint "eagle-import:LED5MM")
      (libsource (lib "eagle-import") (part "LED5MM"))
    )
    (comp (ref "LED210")
      (value "LED5MM")
      (footprint "eagle-import:LED5MM")
      (libsource (lib "eagle-import") (part "LED5MM"))
    )
    (comp (ref "LED211")
      (value "LED5MM")
      (footprint "eagle-import:LED5MM")
      (libsource (lib "eagle-import") (part "LED5MM"))
    )
    (comp (ref "LED212")
      (value "LED5MM")
      (footprint "eagle-import:LED5MM")
      (libsource (lib "eagle-import") (part "LED5MM"))
    )
    (comp (ref "LED213")
      (value "LED5MM")
      (footprint "eagle-import:LED5MM")
      (libsource (lib "eagle-import") (part "LED5MM"))
    )
    (comp (ref "LED214")
      (value "LED5MM")
      (footprint "eagle-import:LED5MM")
      (libsource (lib "eagle-import") (part "LED5MM"))
    )
    (comp (ref "LED215")
      (value "LED5MM")
      (footprint "eagle-import:LED5MM")
      (libsource (lib "eagle-import") (part "LED5MM"))
    )
    (comp (ref "LED216")
      (value "LED5MM")
      (footprint "eagle-import:LED5MM")
      (libsource (lib "eagle-import") (part "LED5MM"))
    )
    (comp (ref "LED217")
      (value "LED5MM")
      (footprint "eagle-import:LED5MM")
      (libsource (lib "eagle-import") (part "LED5MM"))
    )
    (comp (ref "LED218")
      (value "LED5MM")
      (footprint "eagle-import:LED5MM")
      (libsource (lib "eagle-import") (part "LED5MM"))
    )
    (comp (ref "LED219")
      (value "LED5MM")
      (footprint "eagle-import:LED5MM")
      (libsource (lib "eagle-import") (part "LED5MM"))
    )
    (comp (ref "LED220")
      (value "LED5MM")
      (footprint "eagle-import:LED5MM")
      (libsource (lib "eagle-import") (part "LED5MM"))
    )
    (comp (ref "LED221")
      (value "LED5MM")
      (footprint "eagle-import:LED5MM")
      (libsource (lib "eagle-import") (part "LED5MM"))
    )
    (comp (ref "LED222")
      (value "LED5MM")
      (footprint "eagle-import:LED5MM")
      (libsource (lib "eagle-import") (part "LED5MM"))
    )
    (comp (ref "LED223")
      (value "LED5MM")
      (footprint "eagle-import:LED5MM")
      (libsource (lib "eagle-import") (part "LED5MM"))
    )
    (comp (ref "LED224")
      (value "LED5MM")
      (footprint "eagle-import:LED5MM")
      (libsource (lib "eagle-import") (part "LED5MM"))
    )
    (comp (ref "LED225")
      (value "LED5MM")
      (footprint "eagle-import:LED5MM")
      (libsource (lib "eagle-import") (part "LED5MM"))
    )
    (comp (ref "LED226")
      (value "LED5MM")
      (footprint "eagle-import:LED5MM")
      (libsource (lib "eagle-import") (part "LED5MM"))
    )
    (comp (ref "LED227")
      (value "LED5MM")
      (footprint "eagle-import:LED5MM")
      (libsource (lib "eagle-import") (part "LED5MM"))
    )
    (comp (ref "LED228")
      (value "LED5MM")
      (footprint "eagle-import:LED5MM")
      (libsource (lib "eagle-import") (part "LED5MM"))
    )
    (comp (ref "LED229")
      (value "LED5MM")
      (footprint "eagle-import:LED5MM")
      (libsource (lib "eagle-import") (part "LED5MM"))
    )
    (comp (ref "LED230")
      (value "LED5MM")
      (footprint "eagle-import:LED5MM")
      (libsource (lib "eagle-import") (part "LED5MM"))
    )
    (comp (ref "LED231")
      (value "LED5MM")
      (footprint "eagle-import:LED5MM")
      (libsource (lib "eagle-import") (part "LED5MM"))
    )
    (comp (ref "LED232")
      (value "LED5MM")
      (footprint "eagle-import:LED5MM")
      (libsource (lib "eagle-import") (part "LED5MM"))
    )
    (comp (ref "LED233")
      (value "LED5MM")
      (footprint "eagle-import:LED5MM")
      (libsource (lib "eagle-import") (part "LED5MM"))
    )
    (comp (ref "LED234")
      (value "LED5MM")
      (footprint "eagle-import:LED5MM")
      (libsource (lib "eagle-import") (part "LED5MM"))
    )
    (comp (ref "LED235")
      (value "LED5MM")
      (footprint "eagle-import:LED5MM")
      (libsource (lib "eagle-import") (part "LED5MM"))
    )
    (comp (ref "LED236")
      (value "LED5MM")
      (footprint "eagle-import:LED5MM")
      (libsource (lib "eagle-import") (part "LED5MM"))
    )
    (comp (ref "LED237")
      (value "LED5MM")
      (footprint "eagle-import:LED5MM")
      (libsource (lib "eagle-import") (part "LED5MM"))
    )
    (comp (ref "LED238")
      (value "LED5MM")
      (footprint "eagle-import:LED5MM")
      (libsource (lib "eagle-import") (part "LED5MM"))
    )
    (comp (ref "LED239")
      (value "LED5MM")
      (footprint "eagle-import:LED5MM")
      (libsource (lib "eagle-import") (part "LED5MM"))
    )
    (comp (ref "LED240")
      (value "LED5MM")
      (footprint "eagle-import:LED5MM")
      (libsource (lib "eagle-import") (part "LED5MM"))
    )
    (comp (ref "LED241")
      (value "LED5MM")
      (footprint "eagle-import:LED5MM")
      (libsource (lib "eagle-import") (part "LED5MM"))
    )
    (comp (ref "LED242")
      (value "LED5MM")
      (footprint "eagle-import:LED5MM")
      (libsource (lib "eagle-import") (part "LED5MM"))
    )
    (comp (ref "LED243")
      (value "LED5MM")
      (footprint "eagle-import:LED5MM")
      (libsource (lib "eagle-import") (part "LED5MM"))
    )
    (comp (ref "LED244")
      (value "LED5MM")
      (footprint "eagle-import:LED5MM")
      (libsource (lib "eagle-import") (part "LED5MM"))
    )
    (comp (ref "LED245")
      (value "LED5MM")
      (footprint "eagle-import:LED5MM")
      (libsource (lib "eagle-import") (part "LED5MM"))
    )
    (comp (ref "LED246")
      (value "LED5MM")
      (footprint "eagle-import:LED5MM")
      (libsource (lib "eagle-import") (part "LED5MM"))
    )
    (comp (ref "LED247")
      (value "LED5MM")
      (footprint "eagle-import:LED5MM")
      (libsource (lib "eagle-import") (part "LED5MM"))
    )
    (comp (ref "LED248")
      (value "LED5MM")
      (footprint "eagle-import:LED5MM")
      (libsource (lib "eagle-import") (part "LED5MM"))
    )
    (comp (ref "LED249")
      (value "LED5MM")
      (footprint "eagle-import:LED5MM")
      (libsource (lib "eagle-import") (part "LED5MM"))
    )
    (comp (ref "LED250")
      (value "LED5MM")
      (footprint "eagle-import:LED5MM")
      (libsource (lib "eagle-import") (part "LED5MM"))
    )
    (comp (ref "LED251")
      (value "LED5MM")
      (footprint "eagle-import:LED5MM")
      (libsource (lib "eagle-import") (part "LED5MM"))
    )
    (comp (ref "LED252")
      (value "LED5MM")
      (footprint "eagle-import:LED5MM")
      (libsource (lib "eagle-import") (part "LED5MM"))
    )
    (comp (ref "LED253")
      (value "LED5MM")
      (footprint "eagle-import:LED5MM")
      (libsource (lib "eagle-import") (part "LED5MM"))
    )
    (comp (ref "LED254")
      (value "LED5MM")
      (footprint "eagle-import:LED5MM")
      (libsource (lib "eagle-import") (part "LED5MM"))
    )
    (comp (ref "LED255")
      (value "LED5MM")
      (footprint "eagle-import:LED5MM")
      (libsource (lib "eagle-import") (part "LED5MM"))
    )
    (comp (ref "LED256")
      (value "LED5MM")
      (footprint "eagle-import:LED5MM")
      (libsource (lib "eagle-import") (part "LED5MM"))
    )
    (comp (ref "LED257")
      (value "LED5MM")
      (footprint "eagle-import:LED5MM")
      (libsource (lib "eagle-import") (part "LED5MM"))
    )
    (comp (ref "LED258")
      (value "LED5MM")
      (footprint "eagle-import:LED5MM")
      (libsource (lib "eagle-import") (part "LED5MM"))
    )
    (comp (ref "LED259")
      (value "LED5MM")
      (footprint "eagle-import:LED5MM")
      (libsource (lib "eagle-import") (part "LED5MM"))
    )
    (comp (ref "LED260")
      (value "LED5MM")
      (footprint "eagle-import:LED5MM")
      (libsource (lib "eagle-import") (part "LED5MM"))
    )
    (comp (ref "LED261")
      (value "LED5MM")
      (footprint "eagle-import:LED5MM")
      (libsource (lib "eagle-import") (part "LED5MM"))
    )
    (comp (ref "LED262")
      (value "LED5MM")
      (footprint "eagle-import:LED5MM")
      (libsource (lib "eagle-import") (part "LED5MM"))
    )
    (comp (ref "LED263")
      (value "LED5MM")
      (footprint "eagle-import:LED5MM")
      (libsource (lib "eagle-import") (part "LED5MM"))
    )
    (comp (ref "LED264")
      (value "LED5MM")
      (footprint "eagle-import:LED5MM")
      (libsource (lib "eagle-import") (part "LED5MM"))
    )
    (comp (ref "LED265")
      (value "LED5MM")
      (footprint "eagle-import:LED5MM")
      (libsource (lib "eagle-import") (part "LED5MM"))
    )
    (comp (ref "LED266")
      (value "LED5MM")
      (footprint "eagle-import:LED5MM")
      (libsource (lib "eagle-import") (part "LED5MM"))
    )
    (comp (ref "LED267")
      (value "LED5MM")
      (footprint "eagle-import:LED5MM")
      (libsource (lib "eagle-import") (part "LED5MM"))
    )
    (comp (ref "LED268")
      (value "LED5MM")
      (footprint "eagle-import:LED5MM")
      (libsource (lib "eagle-import") (part "LED5MM"))
    )
    (comp (ref "LED269")
      (value "LED5MM")
      (footprint "eagle-import:LED5MM")
      (libsource (lib "eagle-import") (part "LED5MM"))
    )
    (comp (ref "LED270")
      (value "LED5MM")
      (footprint "eagle-import:LED5MM")
      (libsource (lib "eagle-import") (part "LED5MM"))
    )
    (comp (ref "LED271")
      (value "LED5MM")
      (footprint "eagle-import:LED5MM")
      (libsource (lib "eagle-import") (part "LED5MM"))
    )
    (comp (ref "LED272")
      (value "LED5MM")
      (footprint "eagle-import:LED5MM")
      (libsource (lib "eagle-import") (part "LED5MM"))
    )
    (comp (ref "LED273")
      (value "LED5MM")
      (footprint "eagle-import:LED5MM")
      (libsource (lib "eagle-import") (part "LED5MM"))
    )
    (comp (ref "LED274")
      (value "LED5MM")
      (footprint "eagle-import:LED5MM")
      (libsource (lib "eagle-import") (part "LED5MM"))
    )
    (comp (ref "LED275")
      (value "LED5MM")
      (footprint "eagle-import:LED5MM")
      (libsource (lib "eagle-import") (part "LED5MM"))
    )
    (comp (ref "LED276")
      (value "LED5MM")
      (footprint "eagle-import:LED5MM")
      (libsource (lib "eagle-import") (part "LED5MM"))
    )
    (comp (ref "LED277")
      (value "LED5MM")
      (footprint "eagle-import:LED5MM")
      (libsource (lib "eagle-import") (part "LED5MM"))
    )
    (comp (ref "LED278")
      (value "LED5MM")
      (footprint "eagle-import:LED5MM")
      (libsource (lib "eagle-import") (part "LED5MM"))
    )
    (comp (ref "LED279")
      (value "LED5MM")
      (footprint "eagle-import:LED5MM")
      (libsource (lib "eagle-import") (part "LED5MM"))
    )
    (comp (ref "LED280")
      (value "LED5MM")
      (footprint "eagle-import:LED5MM")
      (libsource (lib "eagle-import") (part "LED5MM"))
    )
    (comp (ref "LED281")
      (value "LED5MM")
      (footprint "eagle-import:LED5MM")
      (libsource (lib "eagle-import") (part "LED5MM"))
    )
    (comp (ref "LED282")
      (value "LED5MM")
      (footprint "eagle-import:LED5MM")
      (libsource (lib "eagle-import") (part "LED5MM"))
    )
    (comp (ref "LED283")
      (value "LED5MM")
      (footprint "eagle-import:LED5MM")
      (libsource (lib "eagle-import") (part "LED5MM"))
    )
    (comp (ref "LED284")
      (value "LED5MM")
      (footprint "eagle-import:LED5MM")
      (libsource (lib "eagle-import") (part "LED5MM"))
    )
    (comp (ref "LED285")
      (value "LED5MM")
      (footprint "eagle-import:LED5MM")
      (libsource (lib "eagle-import") (part "LED5MM"))
    )
    (comp (ref "LED286")
      (value "LED5MM")
      (footprint "eagle-import:LED5MM")
      (libsource (lib "eagle-import") (part "LED5MM"))
    )
    (comp (ref "LED287")
      (value "LED5MM")
      (footprint "eagle-import:LED5MM")
      (libsource (lib "eagle-import") (part "LED5MM"))
    )
    (comp (ref "LED288")
      (value "LED5MM")
      (footprint "eagle-import:LED5MM")
      (libsource (lib "eagle-import") (part "LED5MM"))
    )
    (comp (ref "LED289")
      (value "LED5MM")
      (footprint "eagle-import:LED5MM")
      (libsource (lib "eagle-import") (part "LED5MM"))
    )
    (comp (ref "LED290")
      (value "LED5MM")
      (footprint "eagle-import:LED5MM")
      (libsource (lib "eagle-import") (part "LED5MM"))
    )
    (comp (ref "LED291")
      (value "LED5MM")
      (footprint "eagle-import:LED5MM")
      (libsource (lib "eagle-import") (part "LED5MM"))
    )
    (comp (ref "LED292")
      (value "LED5MM")
      (footprint "eagle-import:LED5MM")
      (libsource (lib "eagle-import") (part "LED5MM"))
    )
    (comp (ref "LED293")
      (value "LED5MM")
      (footprint "eagle-import:LED5MM")
      (libsource (lib "eagle-import") (part "LED5MM"))
    )
    (comp (ref "LED294")
      (value "LED5MM")
      (footprint "eagle-import:LED5MM")
      (libsource (lib "eagle-import") (part "LED5MM"))
    )
    (comp (ref "LED295")
      (value "LED5MM")
      (footprint "eagle-import:LED5MM")
      (libsource (lib "eagle-import") (part "LED5MM"))
    )
    (comp (ref "LED296")
      (value "LED5MM")
      (footprint "eagle-import:LED5MM")
      (libsource (lib "eagle-import") (part "LED5MM"))
    )
    (comp (ref "LED297")
      (value "LED5MM")
      (footprint "eagle-import:LED5MM")
      (libsource (lib "eagle-import") (part "LED5MM"))
    )
    (comp (ref "LED298")
      (value "LED5MM")
      (footprint "eagle-import:LED5MM")
      (libsource (lib "eagle-import") (part "LED5MM"))
    )
    (comp (ref "LED299")
      (value "LED5MM")
      (footprint "eagle-import:LED5MM")
      (libsource (lib "eagle-import") (part "LED5MM"))
    )
    (comp (ref "LED300")
      (value "LED5MM")
      (footprint "eagle-import:LED5MM")
      (libsource (lib "eagle-import") (part "LED5MM"))
    )
    (comp (ref "LED301")
      (value "LED5MM")
      (footprint "eagle-import:LED5MM")
      (libsource (lib "eagle-import") (part "LED5MM"))
    )
    (comp (ref "LED302")
      (value "LED5MM")
      (footprint "eagle-import:LED5MM")
      (libsource (lib "eagle-import") (part "LED5MM"))
    )
    (comp (ref "LED303")
      (value "LED5MM")
      (footprint "eagle-import:LED5MM")
      (libsource (lib "eagle-import") (part "LED5MM"))
    )
    (comp (ref "LED304")
      (value "LED5MM")
      (footprint "eagle-import:LED5MM")
      (libsource (lib "eagle-import") (part "LED5MM"))
    )
    (comp (ref "LED305")
      (value "LED5MM")
      (footprint "eagle-import:LED5MM")
      (libsource (lib "eagle-import") (part "LED5MM"))
    )
    (comp (ref "LED306")
      (value "LED5MM")
      (footprint "eagle-import:LED5MM")
      (libsource (lib "eagle-import") (part "LED5MM"))
    )
    (comp (ref "LED307")
      (value "LED5MM")
      (footprint "eagle-import:LED5MM")
      (libsource (lib "eagle-import") (part "LED5MM"))
    )
    (comp (ref "LED308")
      (value "LED5MM")
      (footprint "eagle-import:LED5MM")
      (libsource (lib "eagle-import") (part "LED5MM"))
    )
    (comp (ref "LED309")
      (value "LED5MM")
      (footprint "eagle-import:LED5MM")
      (libsource (lib "eagle-import") (part "LED5MM"))
    )
    (comp (ref "LED310")
      (value "LED5MM")
      (footprint "eagle-import:LED5MM")
      (libsource (lib "eagle-import") (part "LED5MM"))
    )
    (comp (ref "LED311")
      (value "LED5MM")
      (footprint "eagle-import:LED5MM")
      (libsource (lib "eagle-import") (part "LED5MM"))
    )
    (comp (ref "LED312")
      (value "LED5MM")
      (footprint "eagle-import:LED5MM")
      (libsource (lib "eagle-import") (part "LED5MM"))
    )
    (comp (ref "LED313")
      (value "LED5MM")
      (footprint "eagle-import:LED5MM")
      (libsource (lib "eagle-import") (part "LED5MM"))
    )
    (comp (ref "LED314")
      (value "LED5MM")
      (footprint "eagle-import:LED5MM")
      (libsource (lib "eagle-import") (part "LED5MM"))
    )
    (comp (ref "LED315")
      (value "LED5MM")
      (footprint "eagle-import:LED5MM")
      (libsource (lib "eagle-import") (part "LED5MM"))
    )
    (comp (ref "LED316")
      (value "LED5MM")
      (footprint "eagle-import:LED5MM")
      (libsource (lib "eagle-import") (part "LED5MM"))
    )
    (comp (ref "LED317")
      (value "LED5MM")
      (footprint "eagle-import:LED5MM")
      (libsource (lib "eagle-import") (part "LED5MM"))
    )
    (comp (ref "LED318")
      (value "LED5MM")
      (footprint "eagle-import:LED5MM")
      (libsource (lib "eagle-import") (part "LED5MM"))
    )
    (comp (ref "LED319")
      (value "LED5MM")
      (footprint "eagle-import:LED5MM")
      (libsource (lib "eagle-import") (part "LED5MM"))
    )
    (comp (ref "LED320")
      (value "LED5MM")
      (footprint "eagle-import:LED5MM")
      (libsource (lib "eagle-import") (part "LED5MM"))
    )
    (comp (ref "LED321")
      (value "LED5MM")
      (footprint "eagle-import:LED5MM")
      (libsource (lib "eagle-import") (part "LED5MM"))
    )
    (comp (ref "LED322")
      (value "LED5MM")
      (footprint "eagle-import:LED5MM")
      (libsource (lib "eagle-import") (part "LED5MM"))
    )
    (comp (ref "LED323")
      (value "LED5MM")
      (footprint "eagle-import:LED5MM")
      (libsource (lib "eagle-import") (part "LED5MM"))
    )
    (comp (ref "LED324")
      (value "LED5MM")
      (footprint "eagle-import:LED5MM")
      (libsource (lib "eagle-import") (part "LED5MM"))
    )
    (comp (ref "LED325")
      (value "LED5MM")
      (footprint "eagle-import:LED5MM")
      (libsource (lib "eagle-import") (part "LED5MM"))
    )
    (comp (ref "LED326")
      (value "LED5MM")
      (footprint "eagle-import:LED5MM")
      (libsource (lib "eagle-import") (part "LED5MM"))
    )
    (comp (ref "LED327")
      (value "LED5MM")
      (footprint "eagle-import:LED5MM")
      (libsource (lib "eagle-import") (part "LED5MM"))
    )
    (comp (ref "LED328")
      (value "LED5MM")
      (footprint "eagle-import:LED5MM")
      (libsource (lib "eagle-import") (part "LED5MM"))
    )
    (comp (ref "LED329")
      (value "LED5MM")
      (footprint "eagle-import:LED5MM")
      (libsource (lib "eagle-import") (part "LED5MM"))
    )
    (comp (ref "LED330")
      (value "LED5MM")
      (footprint "eagle-import:LED5MM")
      (libsource (lib "eagle-import") (part "LED5MM"))
    )
    (comp (ref "LED331")
      (value "LED5MM")
      (footprint "eagle-import:LED5MM")
      (libsource (lib "eagle-import") (part "LED5MM"))
    )
    (comp (ref "LED332")
      (value "LED5MM")
      (footprint "eagle-import:LED5MM")
      (libsource (lib "eagle-import") (part "LED5MM"))
    )
    (comp (ref "LED333")
      (value "LED5MM")
      (footprint "eagle-import:LED5MM")
      (libsource (lib "eagle-import") (part "LED5MM"))
    )
    (comp (ref "LED334")
      (value "LED5MM")
      (footprint "eagle-import:LED5MM")
      (libsource (lib "eagle-import") (part "LED5MM"))
    )
    (comp (ref "LED335")
      (value "LED5MM")
      (footprint "eagle-import:LED5MM")
      (libsource (lib "eagle-import") (part "LED5MM"))
    )
    (comp (ref "LED336")
      (value "LED5MM")
      (footprint "eagle-import:LED5MM")
      (libsource (lib "eagle-import") (part "LED5MM"))
    )
    (comp (ref "LED337")
      (value "LED5MM")
      (footprint "eagle-import:LED5MM")
      (libsource (lib "eagle-import") (part "LED5MM"))
    )
    (comp (ref "LED338")
      (value "LED5MM")
      (footprint "eagle-import:LED5MM")
      (libsource (lib "eagle-import") (part "LED5MM"))
    )
    (comp (ref "LED339")
      (value "LED5MM")
      (footprint "eagle-import:LED5MM")
      (libsource (lib "eagle-import") (part "LED5MM"))
    )
    (comp (ref "LED340")
      (value "LED5MM")
      (footprint "eagle-import:LED5MM")
      (libsource (lib "eagle-import") (part "LED5MM"))
    )
    (comp (ref "LED341")
      (value "LED5MM")
      (footprint "eagle-import:LED5MM")
      (libsource (lib "eagle-import") (part "LED5MM"))
    )
    (comp (ref "LED342")
      (value "LED5MM")
      (footprint "eagle-import:LED5MM")
      (libsource (lib "eagle-import") (part "LED5MM"))
    )
    (comp (ref "LED343")
      (value "LED5MM")
      (footprint "eagle-import:LED5MM")
      (libsource (lib "eagle-import") (part "LED5MM"))
    )
    (comp (ref "LED344")
      (value "LED5MM")
      (footprint "eagle-import:LED5MM")
      (libsource (lib "eagle-import") (part "LED5MM"))
    )
    (comp (ref "LED345")
      (value "LED5MM")
      (footprint "eagle-import:LED5MM")
      (libsource (lib "eagle-import") (part "LED5MM"))
    )
    (comp (ref "LED346")
      (value "LED5MM")
      (footprint "eagle-import:LED5MM")
      (libsource (lib "eagle-import") (part "LED5MM"))
    )
    (comp (ref "LED347")
      (value "LED5MM")
      (footprint "eagle-import:LED5MM")
      (libsource (lib "eagle-import") (part "LED5MM"))
    )
    (comp (ref "LED348")
      (value "LED5MM")
      (footprint "eagle-import:LED5MM")
      (libsource (lib "eagle-import") (part "LED5MM"))
    )
    (comp (ref "LED349")
      (value "LED5MM")
      (footprint "eagle-import:LED5MM")
      (libsource (lib "eagle-import") (part "LED5MM"))
    )
    (comp (ref "LED350")
      (value "LED5MM")
      (footprint "eagle-import:LED5MM")
      (libsource (lib "eagle-import") (part "LED5MM"))
    )
    (comp (ref "LED351")
      (value "LED5MM")
      (footprint "eagle-import:LED5MM")
      (libsource (lib "eagle-import") (part "LED5MM"))
    )
    (comp (ref "LED352")
      (value "LED5MM")
      (footprint "eagle-import:LED5MM")
      (libsource (lib "eagle-import") (part "LED5MM"))
    )
    (comp (ref "LED353")
      (value "LED5MM")
      (footprint "eagle-import:LED5MM")
      (libsource (lib "eagle-import") (part "LED5MM"))
    )
    (comp (ref "LED354")
      (value "LED5MM")
      (footprint "eagle-import:LED5MM")
      (libsource (lib "eagle-import") (part "LED5MM"))
    )
    (comp (ref "LED355")
      (value "LED5MM")
      (footprint "eagle-import:LED5MM")
      (libsource (lib "eagle-import") (part "LED5MM"))
    )
    (comp (ref "LED356")
      (value "LED5MM")
      (footprint "eagle-import:LED5MM")
      (libsource (lib "eagle-import") (part "LED5MM"))
    )
    (comp (ref "LED357")
      (value "LED5MM")
      (footprint "eagle-import:LED5MM")
      (libsource (lib "eagle-import") (part "LED5MM"))
    )
    (comp (ref "LED358")
      (value "LED5MM")
      (footprint "eagle-import:LED5MM")
      (libsource (lib "eagle-import") (part "LED5MM"))
    )
    (comp (ref "LED359")
      (value "LED5MM")
      (footprint "eagle-import:LED5MM")
      (libsource (lib "eagle-import") (part "LED5MM"))
    )
    (comp (ref "LED360")
      (value "LED5MM")
      (footprint "eagle-import:LED5MM")
      (libsource (lib "eagle-import") (part "LED5MM"))
    )
    (comp (ref "LED361")
      (value "LED5MM")
      (footprint "eagle-import:LED5MM")
      (libsource (lib "eagle-import") (part "LED5MM"))
    )
    (comp (ref "LED362")
      (value "LED5MM")
      (footprint "eagle-import:LED5MM")
      (libsource (lib "eagle-import") (part "LED5MM"))
    )
    (comp (ref "LED363")
      (value "LED5MM")
      (footprint "eagle-import:LED5MM")
      (libsource (lib "eagle-import") (part "LED5MM"))
    )
    (comp (ref "LED364")
      (value "LED5MM")
      (footprint "eagle-import:LED5MM")
      (libsource (lib "eagle-import") (part "LED5MM"))
    )
    (comp (ref "LED365")
      (value "LED5MM")
      (footprint "eagle-import:LED5MM")
      (libsource (lib "eagle-import") (part "LED5MM"))
    )
    (comp (ref "LED366")
      (value "LED5MM")
      (footprint "eagle-import:LED5MM")
      (libsource (lib "eagle-import") (part "LED5MM"))
    )
    (comp (ref "LED367")
      (value "LED5MM")
      (footprint "eagle-import:LED5MM")
      (libsource (lib "eagle-import") (part "LED5MM"))
    )
    (comp (ref "LED368")
      (value "LED5MM")
      (footprint "eagle-import:LED5MM")
      (libsource (lib "eagle-import") (part "LED5MM"))
    )
    (comp (ref "LED369")
      (value "LED5MM")
      (footprint "eagle-import:LED5MM")
      (libsource (lib "eagle-import") (part "LED5MM"))
    )
    (comp (ref "LED370")
      (value "LED5MM")
      (footprint "eagle-import:LED5MM")
      (libsource (lib "eagle-import") (part "LED5MM"))
    )
    (comp (ref "LED371")
      (value "LED5MM")
      (footprint "eagle-import:LED5MM")
      (libsource (lib "eagle-import") (part "LED5MM"))
    )
    (comp (ref "LED372")
      (value "LED5MM")
      (footprint "eagle-import:LED5MM")
      (libsource (lib "eagle-import") (part "LED5MM"))
    )
    (comp (ref "LED373")
      (value "LED5MM")
      (footprint "eagle-import:LED5MM")
      (libsource (lib "eagle-import") (part "LED5MM"))
    )
    (comp (ref "LED374")
      (value "LED5MM")
      (footprint "eagle-import:LED5MM")
      (libsource (lib "eagle-import") (part "LED5MM"))
    )
    (comp (ref "LED375")
      (value "LED5MM")
      (footprint "eagle-import:LED5MM")
      (libsource (lib "eagle-import") (part "LED5MM"))
    )
    (comp (ref "LED376")
      (value "LED5MM")
      (footprint "eagle-import:LED5MM")
      (libsource (lib "eagle-import") (part "LED5MM"))
    )
    (comp (ref "LED377")
      (value "LED5MM")
      (footprint "eagle-import:LED5MM")
      (libsource (lib "eagle-import") (part "LED5MM"))
    )
    (comp (ref "LED378")
      (value "LED5MM")
      (footprint "eagle-import:LED5MM")
      (libsource (lib "eagle-import") (part "LED5MM"))
    )
    (comp (ref "LED379")
      (value "LED5MM")
      (footprint "eagle-import:LED5MM")
      (libsource (lib "eagle-import") (part "LED5MM"))
    )
    (comp (ref "LED380")
      (value "LED5MM")
      (footprint "eagle-import:LED5MM")
      (libsource (lib "eagle-import") (part "LED5MM"))
    )
    (comp (ref "LED381")
      (value "LED5MM")
      (footprint "eagle-import:LED5MM")
      (libsource (lib "eagle-import") (part "LED5MM"))
    )
    (comp (ref "LED382")
      (value "LED5MM")
      (footprint "eagle-import:LED5MM")
      (libsource (lib "eagle-import") (part "LED5MM"))
    )
    (comp (ref "LED383")
      (value "LED5MM")
      (footprint "eagle-import:LED5MM")
      (libsource (lib "eagle-import") (part "LED5MM"))
    )
    (comp (ref "LED384")
      (value "LED5MM")
      (footprint "eagle-import:LED5MM")
      (libsource (lib "eagle-import") (part "LED5MM"))
    )
    (comp (ref "LED385")
      (value "LED5MM")
      (footprint "eagle-import:LED5MM")
      (libsource (lib "eagle-import") (part "LED5MM"))
    )
    (comp (ref "LED386")
      (value "LED5MM")
      (footprint "eagle-import:LED5MM")
      (libsource (lib "eagle-import") (part "LED5MM"))
    )
    (comp (ref "LED387")
      (value "LED5MM")
      (footprint "eagle-import:LED5MM")
      (libsource (lib "eagle-import") (part "LED5MM"))
    )
    (comp (ref "LED388")
      (value "LED5MM")
      (footprint "eagle-import:LED5MM")
      (libsource (lib "eagle-import") (part "LED5MM"))
    )
    (comp (ref "LED389")
      (value "LED5MM")
      (footprint "eagle-import:LED5MM")
      (libsource (lib "eagle-import") (part "LED5MM"))
    )
    (comp (ref "LED390")
      (value "LED5MM")
      (footprint "eagle-import:LED5MM")
      (libsource (lib "eagle-import") (part "LED5MM"))
    )
    (comp (ref "LED391")
      (value "LED5MM")
      (footprint "eagle-import:LED5MM")
      (libsource (lib "eagle-import") (part "LED5MM"))
    )
    (comp (ref "LED392")
      (value "LED5MM")
      (footprint "eagle-import:LED5MM")
      (libsource (lib "eagle-import") (part "LED5MM"))
    )
    (comp (ref "LED393")
      (value "LED5MM")
      (footprint "eagle-import:LED5MM")
      (libsource (lib "eagle-import") (part "LED5MM"))
    )
    (comp (ref "LED394")
      (value "LED5MM")
      (footprint "eagle-import:LED5MM")
      (libsource (lib "eagle-import") (part "LED5MM"))
    )
    (comp (ref "LED395")
      (value "LED5MM")
      (footprint "eagle-import:LED5MM")
      (libsource (lib "eagle-import") (part "LED5MM"))
    )
    (comp (ref "LED396")
      (value "LED5MM")
      (footprint "eagle-import:LED5MM")
      (libsource (lib "eagle-import") (part "LED5MM"))
    )
    (comp (ref "LED397")
      (value "LED5MM")
      (footprint "eagle-import:LED5MM")
      (libsource (lib "eagle-import") (part "LED5MM"))
    )
    (comp (ref "LED398")
      (value "LED5MM")
      (footprint "eagle-import:LED5MM")
      (libsource (lib "eagle-import") (part "LED5MM"))
    )
    (comp (ref "LED399")
      (value "LED5MM")
      (footprint "eagle-import:LED5MM")
      (libsource (lib "eagle-import") (part "LED5MM"))
    )
    (comp (ref "LED400")
      (value "LED5MM")
      (footprint "eagle-import:LED5MM")
      (libsource (lib "eagle-import") (part "LED5MM"))
    )
    (comp (ref "LED401")
      (value "LED5MM")
      (footprint "eagle-import:LED5MM")
      (libsource (lib "eagle-import") (part "LED5MM"))
    )
    (comp (ref "LED402")
      (value "LED5MM")
      (footprint "eagle-import:LED5MM")
      (libsource (lib "eagle-import") (part "LED5MM"))
    )
    (comp (ref "LED403")
      (value "LED5MM")
      (footprint "eagle-import:LED5MM")
      (libsource (lib "eagle-import") (part "LED5MM"))
    )
    (comp (ref "LED404")
      (value "LED5MM")
      (footprint "eagle-import:LED5MM")
      (libsource (lib "eagle-import") (part "LED5MM"))
    )
    (comp (ref "LED405")
      (value "LED5MM")
      (footprint "eagle-import:LED5MM")
      (libsource (lib "eagle-import") (part "LED5MM"))
    )
    (comp (ref "LED406")
      (value "LED5MM")
      (footprint "eagle-import:LED5MM")
      (libsource (lib "eagle-import") (part "LED5MM"))
    )
    (comp (ref "LED407")
      (value "LED5MM")
      (footprint "eagle-import:LED5MM")
      (libsource (lib "eagle-import") (part "LED5MM"))
    )
    (comp (ref "LED408")
      (value "LED5MM")
      (footprint "eagle-import:LED5MM")
      (libsource (lib "eagle-import") (part "LED5MM"))
    )
    (comp (ref "LED409")
      (value "LED5MM")
      (footprint "eagle-import:LED5MM")
      (libsource (lib "eagle-import") (part "LED5MM"))
    )
    (comp (ref "LED410")
      (value "LED5MM")
      (footprint "eagle-import:LED5MM")
      (libsource (lib "eagle-import") (part "LED5MM"))
    )
    (comp (ref "LED411")
      (value "LED5MM")
      (footprint "eagle-import:LED5MM")
      (libsource (lib "eagle-import") (part "LED5MM"))
    )
    (comp (ref "LED412")
      (value "LED5MM")
      (footprint "eagle-import:LED5MM")
      (libsource (lib "eagle-import") (part "LED5MM"))
    )
    (comp (ref "LED413")
      (value "LED5MM")
      (footprint "eagle-import:LED5MM")
      (libsource (lib "eagle-import") (part "LED5MM"))
    )
    (comp (ref "LED414")
      (value "LED5MM")
      (footprint "eagle-import:LED5MM")
      (libsource (lib "eagle-import") (part "LED5MM"))
    )
    (comp (ref "LED415")
      (value "LED5MM")
      (footprint "eagle-import:LED5MM")
      (libsource (lib "eagle-import") (part "LED5MM"))
    )
    (comp (ref "LED416")
      (value "LED5MM")
      (footprint "eagle-import:LED5MM")
      (libsource (lib "eagle-import") (part "LED5MM"))
    )
    (comp (ref "LED417")
      (value "LED5MM")
      (footprint "eagle-import:LED5MM")
      (libsource (lib "eagle-import") (part "LED5MM"))
    )
    (comp (ref "LED418")
      (value "LED5MM")
      (footprint "eagle-import:LED5MM")
      (libsource (lib "eagle-import") (part "LED5MM"))
    )
    (comp (ref "LED419")
      (value "LED5MM")
      (footprint "eagle-import:LED5MM")
      (libsource (lib "eagle-import") (part "LED5MM"))
    )
    (comp (ref "LED420")
      (value "LED5MM")
      (footprint "eagle-import:LED5MM")
      (libsource (lib "eagle-import") (part "LED5MM"))
    )
    (comp (ref "LED421")
      (value "LED5MM")
      (footprint "eagle-import:LED5MM")
      (libsource (lib "eagle-import") (part "LED5MM"))
    )
    (comp (ref "LED422")
      (value "LED5MM")
      (footprint "eagle-import:LED5MM")
      (libsource (lib "eagle-import") (part "LED5MM"))
    )
    (comp (ref "LED423")
      (value "LED5MM")
      (footprint "eagle-import:LED5MM")
      (libsource (lib "eagle-import") (part "LED5MM"))
    )
    (comp (ref "LED424")
      (value "LED5MM")
      (footprint "eagle-import:LED5MM")
      (libsource (lib "eagle-import") (part "LED5MM"))
    )
    (comp (ref "LED425")
      (value "LED5MM")
      (footprint "eagle-import:LED5MM")
      (libsource (lib "eagle-import") (part "LED5MM"))
    )
    (comp (ref "LED426")
      (value "LED5MM")
      (footprint "eagle-import:LED5MM")
      (libsource (lib "eagle-import") (part "LED5MM"))
    )
    (comp (ref "LED427")
      (value "LED5MM")
      (footprint "eagle-import:LED5MM")
      (libsource (lib "eagle-import") (part "LED5MM"))
    )
    (comp (ref "LED428")
      (value "LED5MM")
      (footprint "eagle-import:LED5MM")
      (libsource (lib "eagle-import") (part "LED5MM"))
    )
    (comp (ref "LED429")
      (value "LED5MM")
      (footprint "eagle-import:LED5MM")
      (libsource (lib "eagle-import") (part "LED5MM"))
    )
    (comp (ref "LED430")
      (value "LED5MM")
      (footprint "eagle-import:LED5MM")
      (libsource (lib "eagle-import") (part "LED5MM"))
    )
    (comp (ref "LED431")
      (value "LED5MM")
      (footprint "eagle-import:LED5MM")
      (libsource (lib "eagle-import") (part "LED5MM"))
    )
    (comp (ref "LED432")
      (value "LED5MM")
      (footprint "eagle-import:LED5MM")
      (libsource (lib "eagle-import") (part "LED5MM"))
    )
    (comp (ref "LED433")
      (value "LED5MM")
      (footprint "eagle-import:LED5MM")
      (libsource (lib "eagle-import") (part "LED5MM"))
    )
    (comp (ref "LED434")
      (value "LED5MM")
      (footprint "eagle-import:LED5MM")
      (libsource (lib "eagle-import") (part "LED5MM"))
    )
    (comp (ref "LED435")
      (value "LED5MM")
      (footprint "eagle-import:LED5MM")
      (libsource (lib "eagle-import") (part "LED5MM"))
    )
    (comp (ref "LED436")
      (value "LED5MM")
      (footprint "eagle-import:LED5MM")
      (libsource (lib "eagle-import") (part "LED5MM"))
    )
    (comp (ref "LED437")
      (value "LED5MM")
      (footprint "eagle-import:LED5MM")
      (libsource (lib "eagle-import") (part "LED5MM"))
    )
    (comp (ref "LED438")
      (value "LED5MM")
      (footprint "eagle-import:LED5MM")
      (libsource (lib "eagle-import") (part "LED5MM"))
    )
    (comp (ref "LED439")
      (value "LED5MM")
      (footprint "eagle-import:LED5MM")
      (libsource (lib "eagle-import") (part "LED5MM"))
    )
    (comp (ref "LED440")
      (value "LED5MM")
      (footprint "eagle-import:LED5MM")
      (libsource (lib "eagle-import") (part "LED5MM"))
    )
    (comp (ref "LED441")
      (value "LED5MM")
      (footprint "eagle-import:LED5MM")
      (libsource (lib "eagle-import") (part "LED5MM"))
    )
    (comp (ref "LED442")
      (value "LED5MM")
      (footprint "eagle-import:LED5MM")
      (libsource (lib "eagle-import") (part "LED5MM"))
    )
    (comp (ref "LED443")
      (value "LED5MM")
      (footprint "eagle-import:LED5MM")
      (libsource (lib "eagle-import") (part "LED5MM"))
    )
    (comp (ref "LED444")
      (value "LED5MM")
      (footprint "eagle-import:LED5MM")
      (libsource (lib "eagle-import") (part "LED5MM"))
    )
    (comp (ref "LED445")
      (value "LED5MM")
      (footprint "eagle-import:LED5MM")
      (libsource (lib "eagle-import") (part "LED5MM"))
    )
    (comp (ref "LED446")
      (value "LED5MM")
      (footprint "eagle-import:LED5MM")
      (libsource (lib "eagle-import") (part "LED5MM"))
    )
    (comp (ref "LED447")
      (value "LED5MM")
      (footprint "eagle-import:LED5MM")
      (libsource (lib "eagle-import") (part "LED5MM"))
    )
    (comp (ref "LED448")
      (value "LED5MM")
      (footprint "eagle-import:LED5MM")
      (libsource (lib "eagle-import") (part "LED5MM"))
    )
    (comp (ref "LED449")
      (value "LED5MM")
      (footprint "eagle-import:LED5MM")
      (libsource (lib "eagle-import") (part "LED5MM"))
    )
    (comp (ref "LED450")
      (value "LED5MM")
      (footprint "eagle-import:LED5MM")
      (libsource (lib "eagle-import") (part "LED5MM"))
    )
    (comp (ref "LED451")
      (value "LED5MM")
      (footprint "eagle-import:LED5MM")
      (libsource (lib "eagle-import") (part "LED5MM"))
    )
    (comp (ref "LED452")
      (value "LED5MM")
      (footprint "eagle-import:LED5MM")
      (libsource (lib "eagle-import") (part "LED5MM"))
    )
    (comp (ref "LED453")
      (value "LED5MM")
      (footprint "eagle-import:LED5MM")
      (libsource (lib "eagle-import") (part "LED5MM"))
    )
    (comp (ref "LED454")
      (value "LED5MM")
      (footprint "eagle-import:LED5MM")
      (libsource (lib "eagle-import") (part "LED5MM"))
    )
    (comp (ref "LED455")
      (value "LED5MM")
      (footprint "eagle-import:LED5MM")
      (libsource (lib "eagle-import") (part "LED5MM"))
    )
    (comp (ref "LED456")
      (value "LED5MM")
      (footprint "eagle-import:LED5MM")
      (libsource (lib "eagle-import") (part "LED5MM"))
    )
    (comp (ref "LED457")
      (value "LED5MM")
      (footprint "eagle-import:LED5MM")
      (libsource (lib "eagle-import") (part "LED5MM"))
    )
    (comp (ref "LED458")
      (value "LED5MM")
      (footprint "eagle-import:LED5MM")
      (libsource (lib "eagle-import") (part "LED5MM"))
    )
    (comp (ref "LED459")
      (value "LED5MM")
      (footprint "eagle-import:LED5MM")
      (libsource (lib "eagle-import") (part "LED5MM"))
    )
    (comp (ref "LED460")
      (value "LED5MM")
      (footprint "eagle-import:LED5MM")
      (libsource (lib "eagle-import") (part "LED5MM"))
    )
    (comp (ref "LED461")
      (value "LED5MM")
      (footprint "eagle-import:LED5MM")
      (libsource (lib "eagle-import") (part "LED5MM"))
    )
    (comp (ref "LED462")
      (value "LED5MM")
      (footprint "eagle-import:LED5MM")
      (libsource (lib "eagle-import") (part "LED5MM"))
    )
    (comp (ref "LED463")
      (value "LED5MM")
      (footprint "eagle-import:LED5MM")
      (libsource (lib "eagle-import") (part "LED5MM"))
    )
    (comp (ref "LED464")
      (value "LED5MM")
      (footprint "eagle-import:LED5MM")
      (libsource (lib "eagle-import") (part "LED5MM"))
    )
    (comp (ref "LED465")
      (value "LED5MM")
      (footprint "eagle-import:LED5MM")
      (libsource (lib "eagle-import") (part "LED5MM"))
    )
    (comp (ref "LED466")
      (value "LED5MM")
      (footprint "eagle-import:LED5MM")
      (libsource (lib "eagle-import") (part "LED5MM"))
    )
    (comp (ref "LED467")
      (value "LED5MM")
      (footprint "eagle-import:LED5MM")
      (libsource (lib "eagle-import") (part "LED5MM"))
    )
    (comp (ref "LED468")
      (value "LED5MM")
      (footprint "eagle-import:LED5MM")
      (libsource (lib "eagle-import") (part "LED5MM"))
    )
    (comp (ref "LED469")
      (value "LED5MM")
      (footprint "eagle-import:LED5MM")
      (libsource (lib "eagle-import") (part "LED5MM"))
    )
    (comp (ref "LED470")
      (value "LED5MM")
      (footprint "eagle-import:LED5MM")
      (libsource (lib "eagle-import") (part "LED5MM"))
    )
    (comp (ref "LED471")
      (value "LED5MM")
      (footprint "eagle-import:LED5MM")
      (libsource (lib "eagle-import") (part "LED5MM"))
    )
    (comp (ref "LED472")
      (value "LED5MM")
      (footprint "eagle-import:LED5MM")
      (libsource (lib "eagle-import") (part "LED5MM"))
    )
    (comp (ref "LED473")
      (value "LED5MM")
      (footprint "eagle-import:LED5MM")
      (libsource (lib "eagle-import") (part "LED5MM"))
    )
    (comp (ref "LED474")
      (value "LED5MM")
      (footprint "eagle-import:LED5MM")
      (libsource (lib "eagle-import") (part "LED5MM"))
    )
    (comp (ref "LED475")
      (value "LED5MM")
      (footprint "eagle-import:LED5MM")
      (libsource (lib "eagle-import") (part "LED5MM"))
    )
    (comp (ref "LED476")
      (value "LED5MM")
      (footprint "eagle-import:LED5MM")
      (libsource (lib "eagle-import") (part "LED5MM"))
    )
    (comp (ref "LED477")
      (value "LED5MM")
      (footprint "eagle-import:LED5MM")
      (libsource (lib "eagle-import") (part "LED5MM"))
    )
    (comp (ref "LED478")
      (value "LED5MM")
      (footprint "eagle-import:LED5MM")
      (libsource (lib "eagle-import") (part "LED5MM"))
    )
    (comp (ref "LED479")
      (value "LED5MM")
      (footprint "eagle-import:LED5MM")
      (libsource (lib "eagle-import") (part "LED5MM"))
    )
    (comp (ref "LED480")
      (value "LED5MM")
      (footprint "eagle-import:LED5MM")
      (libsource (lib "eagle-import") (part "LED5MM"))
    )
    (comp (ref "LED481")
      (value "LED5MM")
      (footprint "eagle-import:LED5MM")
      (libsource (lib "eagle-import") (part "LED5MM"))
    )
    (comp (ref "LED482")
      (value "LED5MM")
      (footprint "eagle-import:LED5MM")
      (libsource (lib "eagle-import") (part "LED5MM"))
    )
    (comp (ref "LED483")
      (value "LED5MM")
      (footprint "eagle-import:LED5MM")
      (libsource (lib "eagle-import") (part "LED5MM"))
    )
    (comp (ref "LED484")
      (value "LED5MM")
      (footprint "eagle-import:LED5MM")
      (libsource (lib "eagle-import") (part "LED5MM"))
    )
    (comp (ref "LED485")
      (value "LED5MM")
      (footprint "eagle-import:LED5MM")
      (libsource (lib "eagle-import") (part "LED5MM"))
    )
    (comp (ref "LED486")
      (value "LED5MM")
      (footprint "eagle-import:LED5MM")
      (libsource (lib "eagle-import") (part "LED5MM"))
    )
    (comp (ref "LED487")
      (value "LED5MM")
      (footprint "eagle-import:LED5MM")
      (libsource (lib "eagle-import") (part "LED5MM"))
    )
    (comp (ref "LED488")
      (value "LED5MM")
      (footprint "eagle-import:LED5MM")
      (libsource (lib "eagle-import") (part "LED5MM"))
    )
    (comp (ref "LED489")
      (value "LED5MM")
      (footprint "eagle-import:LED5MM")
      (libsource (lib "eagle-import") (part "LED5MM"))
    )
    (comp (ref "LED490")
      (value "LED5MM")
      (footprint "eagle-import:LED5MM")
      (libsource (lib "eagle-import") (part "LED5MM"))
    )
    (comp (ref "LED491")
      (value "LED5MM")
      (footprint "eagle-import:LED5MM")
      (libsource (lib "eagle-import") (part "LED5MM"))
    )
    (comp (ref "LED492")
      (value "LED5MM")
      (footprint "eagle-import:LED5MM")
      (libsource (lib "eagle-import") (part "LED5MM"))
    )
    (comp (ref "LED493")
      (value "LED5MM")
      (footprint "eagle-import:LED5MM")
      (libsource (lib "eagle-import") (part "LED5MM"))
    )
    (comp (ref "LED494")
      (value "LED5MM")
      (footprint "eagle-import:LED5MM")
      (libsource (lib "eagle-import") (part "LED5MM"))
    )
    (comp (ref "LED495")
      (value "LED5MM")
      (footprint "eagle-import:LED5MM")
      (libsource (lib "eagle-import") (part "LED5MM"))
    )
    (comp (ref "LED496")
      (value "LED5MM")
      (footprint "eagle-import:LED5MM")
      (libsource (lib "eagle-import") (part "LED5MM"))
    )
    (comp (ref "LED497")
      (value "LED5MM")
      (footprint "eagle-import:LED5MM")
      (libsource (lib "eagle-import") (part "LED5MM"))
    )
    (comp (ref "LED498")
      (value "LED5MM")
      (footprint "eagle-import:LED5MM")
      (libsource (lib "eagle-import") (part "LED5MM"))
    )
    (comp (ref "LED499")
      (value "LED5MM")
      (footprint "eagle-import:LED5MM")
      (libsource (lib "eagle-import") (part "LED5MM"))
    )
    (comp (ref "LED500")
      (value "LED5MM")
      (footprint "eagle-import:LED5MM")
      (libsource (lib "eagle-import") (part "LED5MM"))
    )
    (comp (ref "LED501")
      (value "LED5MM")
      (footprint "eagle-import:LED5MM")
      (libsource (lib "eagle-import") (part "LED5MM"))
    )
    (comp (ref "LED502")
      (value "LED5MM")
      (footprint "eagle-import:LED5MM")
      (libsource (lib "eagle-import") (part "LED5MM"))
    )
    (comp (ref "LED503")
      (value "LED5MM")
      (footprint "eagle-import:LED5MM")
      (libsource (lib "eagle-import") (part "LED5MM"))
    )
    (comp (ref "LED504")
      (value "LED5MM")
      (footprint "eagle-import:LED5MM")
      (libsource (lib "eagle-import") (part "LED5MM"))
    )
    (comp (ref "LED505")
      (value "LED5MM")
      (footprint "eagle-import:LED5MM")
      (libsource (lib "eagle-import") (part "LED5MM"))
    )
    (comp (ref "LED506")
      (value "LED5MM")
      (footprint "eagle-import:LED5MM")
      (libsource (lib "eagle-import") (part "LED5MM"))
    )
    (comp (ref "LED507")
      (value "LED5MM")
      (footprint "eagle-import:LED5MM")
      (libsource (lib "eagle-import") (part "LED5MM"))
    )
    (comp (ref "LED508")
      (value "LED5MM")
      (footprint "eagle-import:LED5MM")
      (libsource (lib "eagle-import") (part "LED5MM"))
    )
    (comp (ref "LED509")
      (value "LED5MM")
      (footprint "eagle-import:LED5MM")
      (libsource (lib "eagle-import") (part "LED5MM"))
    )
    (comp (ref "LED510")
      (value "LED5MM")
      (footprint "eagle-import:LED5MM")
      (libsource (lib "eagle-import") (part "LED5MM"))
    )
    (comp (ref "LED511")
      (value "LED5MM")
      (footprint "eagle-import:LED5MM")
      (libsource (lib "eagle-import") (part "LED5MM"))
    )
    (comp (ref "LED512")
      (value "LED5MM")
      (footprint "eagle-import:LED5MM")
      (libsource (lib "eagle-import") (part "LED5MM"))
    )
    (comp (ref "LED513")
      (value "LED5MM")
      (footprint "eagle-import:LED5MM")
      (libsource (lib "eagle-import") (part "LED5MM"))
    )
    (comp (ref "LED514")
      (value "LED5MM")
      (footprint "eagle-import:LED5MM")
      (libsource (lib "eagle-import") (part "LED5MM"))
    )
    (comp (ref "LED515")
      (value "LED5MM")
      (footprint "eagle-import:LED5MM")
      (libsource (lib "eagle-import") (part "LED5MM"))
    )
    (comp (ref "LED516")
      (value "LED5MM")
      (footprint "eagle-import:LED5MM")
      (libsource (lib "eagle-import") (part "LED5MM"))
    )
    (comp (ref "LED517")
      (value "LED5MM")
      (footprint "eagle-import:LED5MM")
      (libsource (lib "eagle-import") (part "LED5MM"))
    )
    (comp (ref "LED518")
      (value "LED5MM")
      (footprint "eagle-import:LED5MM")
      (libsource (lib "eagle-import") (part "LED5MM"))
    )
    (comp (ref "LED519")
      (value "LED5MM")
      (footprint "eagle-import:LED5MM")
      (libsource (lib "eagle-import") (part "LED5MM"))
    )
    (comp (ref "LED520")
      (value "LED5MM")
      (footprint "eagle-import:LED5MM")
      (libsource (lib "eagle-import") (part "LED5MM"))
    )
    (comp (ref "LED521")
      (value "LED5MM")
      (footprint "eagle-import:LED5MM")
      (libsource (lib "eagle-import") (part "LED5MM"))
    )
    (comp (ref "LED522")
      (value "LED5MM")
      (footprint "eagle-import:LED5MM")
      (libsource (lib "eagle-import") (part "LED5MM"))
    )
    (comp (ref "LED523")
      (value "LED5MM")
      (footprint "eagle-import:LED5MM")
      (libsource (lib "eagle-import") (part "LED5MM"))
    )
    (comp (ref "LED524")
      (value "LED5MM")
      (footprint "eagle-import:LED5MM")
      (libsource (lib "eagle-import") (part "LED5MM"))
    )
    (comp (ref "LED525")
      (value "LED5MM")
      (footprint "eagle-import:LED5MM")
      (libsource (lib "eagle-import") (part "LED5MM"))
    )
    (comp (ref "LED526")
      (value "LED5MM")
      (footprint "eagle-import:LED5MM")
      (libsource (lib "eagle-import") (part "LED5MM"))
    )
    (comp (ref "LED527")
      (value "LED5MM")
      (footprint "eagle-import:LED5MM")
      (libsource (lib "eagle-import") (part "LED5MM"))
    )
    (comp (ref "LED528")
      (value "LED5MM")
      (footprint "eagle-import:LED5MM")
      (libsource (lib "eagle-import") (part "LED5MM"))
    )
    (comp (ref "LED529")
      (value "LED5MM")
      (footprint "eagle-import:LED5MM")
      (libsource (lib "eagle-import") (part "LED5MM"))
    )
    (comp (ref "LED530")
      (value "LED5MM")
      (footprint "eagle-import:LED5MM")
      (libsource (lib "eagle-import") (part "LED5MM"))
    )
    (comp (ref "LED531")
      (value "LED5MM")
      (footprint "eagle-import:LED5MM")
      (libsource (lib "eagle-import") (part "LED5MM"))
    )
    (comp (ref "LED532")
      (value "LED5MM")
      (footprint "eagle-import:LED5MM")
      (libsource (lib "eagle-import") (part "LED5MM"))
    )
    (comp (ref "LED533")
      (value "LED5MM")
      (footprint "eagle-import:LED5MM")
      (libsource (lib "eagle-import") (part "LED5MM"))
    )
    (comp (ref "LED534")
      (value "LED5MM")
      (footprint "eagle-import:LED5MM")
      (libsource (lib "eagle-import") (part "LED5MM"))
    )
    (comp (ref "LED535")
      (value "LED5MM")
      (footprint "eagle-import:LED5MM")
      (libsource (lib "eagle-import") (part "LED5MM"))
    )
    (comp (ref "LED536")
      (value "LED5MM")
      (footprint "eagle-import:LED5MM")
      (libsource (lib "eagle-import") (part "LED5MM"))
    )
    (comp (ref "LED537")
      (value "LED5MM")
      (footprint "eagle-import:LED5MM")
      (libsource (lib "eagle-import") (part "LED5MM"))
    )
    (comp (ref "LED538")
      (value "LED5MM")
      (footprint "eagle-import:LED5MM")
      (libsource (lib "eagle-import") (part "LED5MM"))
    )
    (comp (ref "LED539")
      (value "LED5MM")
      (footprint "eagle-import:LED5MM")
      (libsource (lib "eagle-import") (part "LED5MM"))
    )
    (comp (ref "LED540")
      (value "LED5MM")
      (footprint "eagle-import:LED5MM")
      (libsource (lib "eagle-import") (part "LED5MM"))
    )
    (comp (ref "LED541")
      (value "LED5MM")
      (footprint "eagle-import:LED5MM")
      (libsource (lib "eagle-import") (part "LED5MM"))
    )
    (comp (ref "LED542")
      (value "LED5MM")
      (footprint "eagle-import:LED5MM")
      (libsource (lib "eagle-import") (part "LED5MM"))
    )
    (comp (ref "LED543")
      (value "LED5MM")
      (footprint "eagle-import:LED5MM")
      (libsource (lib "eagle-import") (part "LED5MM"))
    )
    (comp (ref "LED544")
      (value "LED5MM")
      (footprint "eagle-import:LED5MM")
      (libsource (lib "eagle-import") (part "LED5MM"))
    )
    (comp (ref "LED545")
      (value "LED5MM")
      (footprint "eagle-import:LED5MM")
      (libsource (lib "eagle-import") (part "LED5MM"))
    )
    (comp (ref "LED546")
      (value "LED5MM")
      (footprint "eagle-import:LED5MM")
      (libsource (lib "eagle-import") (part "LED5MM"))
    )
    (comp (ref "LED547")
      (value "LED5MM")
      (footprint "eagle-import:LED5MM")
      (libsource (lib "eagle-import") (part "LED5MM"))
    )
    (comp (ref "LED548")
      (value "LED5MM")
      (footprint "eagle-import:LED5MM")
      (libsource (lib "eagle-import") (part "LED5MM"))
    )
    (comp (ref "LED549")
      (value "LED5MM")
      (footprint "eagle-import:LED5MM")
      (libsource (lib "eagle-import") (part "LED5MM"))
    )
    (comp (ref "LED550")
      (value "LED5MM")
      (footprint "eagle-import:LED5MM")
      (libsource (lib "eagle-import") (part "LED5MM"))
    )
    (comp (ref "LED551")
      (value "LED5MM")
      (footprint "eagle-import:LED5MM")
      (libsource (lib "eagle-import") (part "LED5MM"))
    )
    (comp (ref "LED552")
      (value "LED5MM")
      (footprint "eagle-import:LED5MM")
      (libsource (lib "eagle-import") (part "LED5MM"))
    )
    (comp (ref "LED553")
      (value "LED5MM")
      (footprint "eagle-import:LED5MM")
      (libsource (lib "eagle-import") (part "LED5MM"))
    )
    (comp (ref "LED554")
      (value "LED5MM")
      (footprint "eagle-import:LED5MM")
      (libsource (lib "eagle-import") (part "LED5MM"))
    )
    (comp (ref "LED555")
      (value "LED5MM")
      (footprint "eagle-import:LED5MM")
      (libsource (lib "eagle-import") (part "LED5MM"))
    )
    (comp (ref "LED556")
      (value "LED5MM")
      (footprint "eagle-import:LED5MM")
      (libsource (lib "eagle-import") (part "LED5MM"))
    )
    (comp (ref "LED557")
      (value "LED5MM")
      (footprint "eagle-import:LED5MM")
      (libsource (lib "eagle-import") (part "LED5MM"))
    )
    (comp (ref "LED558")
      (value "LED5MM")
      (footprint "eagle-import:LED5MM")
      (libsource (lib "eagle-import") (part "LED5MM"))
    )
    (comp (ref "LED559")
      (value "LED5MM")
      (footprint "eagle-import:LED5MM")
      (libsource (lib "eagle-import") (part "LED5MM"))
    )
    (comp (ref "LED560")
      (value "LED5MM")
      (footprint "eagle-import:LED5MM")
      (libsource (lib "eagle-import") (part "LED5MM"))
    )
    (comp (ref "LED561")
      (value "LED5MM")
      (footprint "eagle-import:LED5MM")
      (libsource (lib "eagle-import") (part "LED5MM"))
    )
    (comp (ref "LED562")
      (value "LED5MM")
      (footprint "eagle-import:LED5MM")
      (libsource (lib "eagle-import") (part "LED5MM"))
    )
    (comp (ref "LED563")
      (value "LED5MM")
      (footprint "eagle-import:LED5MM")
      (libsource (lib "eagle-import") (part "LED5MM"))
    )
    (comp (ref "LED564")
      (value "LED5MM")
      (footprint "eagle-import:LED5MM")
      (libsource (lib "eagle-import") (part "LED5MM"))
    )
    (comp (ref "LED565")
      (value "LED5MM")
      (footprint "eagle-import:LED5MM")
      (libsource (lib "eagle-import") (part "LED5MM"))
    )
    (comp (ref "LED566")
      (value "LED5MM")
      (footprint "eagle-import:LED5MM")
      (libsource (lib "eagle-import") (part "LED5MM"))
    )
    (comp (ref "LED567")
      (value "LED5MM")
      (footprint "eagle-import:LED5MM")
      (libsource (lib "eagle-import") (part "LED5MM"))
    )
    (comp (ref "LED568")
      (value "LED5MM")
      (footprint "eagle-import:LED5MM")
      (libsource (lib "eagle-import") (part "LED5MM"))
    )
    (comp (ref "LED569")
      (value "LED5MM")
      (footprint "eagle-import:LED5MM")
      (libsource (lib "eagle-import") (part "LED5MM"))
    )
    (comp (ref "LED570")
      (value "LED5MM")
      (footprint "eagle-import:LED5MM")
      (libsource (lib "eagle-import") (part "LED5MM"))
    )
    (comp (ref "LED571")
      (value "LED5MM")
      (footprint "eagle-import:LED5MM")
      (libsource (lib "eagle-import") (part "LED5MM"))
    )
    (comp (ref "LED572")
      (value "LED5MM")
      (footprint "eagle-import:LED5MM")
      (libsource (lib "eagle-import") (part "LED5MM"))
    )
    (comp (ref "LED573")
      (value "LED5MM")
      (footprint "eagle-import:LED5MM")
      (libsource (lib "eagle-import") (part "LED5MM"))
    )
    (comp (ref "LED574")
      (value "LED5MM")
      (footprint "eagle-import:LED5MM")
      (libsource (lib "eagle-import") (part "LED5MM"))
    )
    (comp (ref "LED575")
      (value "LED5MM")
      (footprint "eagle-import:LED5MM")
      (libsource (lib "eagle-import") (part "LED5MM"))
    )
    (comp (ref "LED576")
      (value "LED5MM")
      (footprint "eagle-import:LED5MM")
      (libsource (lib "eagle-import") (part "LED5MM"))
    )
    (comp (ref "LED577")
      (value "LED5MM")
      (footprint "eagle-import:LED5MM")
      (libsource (lib "eagle-import") (part "LED5MM"))
    )
    (comp (ref "LED578")
      (value "LED5MM")
      (footprint "eagle-import:LED5MM")
      (libsource (lib "eagle-import") (part "LED5MM"))
    )
    (comp (ref "LED579")
      (value "LED5MM")
      (footprint "eagle-import:LED5MM")
      (libsource (lib "eagle-import") (part "LED5MM"))
    )
    (comp (ref "LED580")
      (value "LED5MM")
      (footprint "eagle-import:LED5MM")
      (libsource (lib "eagle-import") (part "LED5MM"))
    )
    (comp (ref "LED581")
      (value "LED5MM")
      (footprint "eagle-import:LED5MM")
      (libsource (lib "eagle-import") (part "LED5MM"))
    )
    (comp (ref "LED582")
      (value "LED5MM")
      (footprint "eagle-import:LED5MM")
      (libsource (lib "eagle-import") (part "LED5MM"))
    )
    (comp (ref "LED583")
      (value "LED5MM")
      (footprint "eagle-import:LED5MM")
      (libsource (lib "eagle-import") (part "LED5MM"))
    )
    (comp (ref "LED584")
      (value "LED5MM")
      (footprint "eagle-import:LED5MM")
      (libsource (lib "eagle-import") (part "LED5MM"))
    )
    (comp (ref "LED585")
      (value "LED5MM")
      (footprint "eagle-import:LED5MM")
      (libsource (lib "eagle-import") (part "LED5MM"))
    )
    (comp (ref "LED586")
      (value "LED5MM")
      (footprint "eagle-import:LED5MM")
      (libsource (lib "eagle-import") (part "LED5MM"))
    )
    (comp (ref "LED587")
      (value "LED5MM")
      (footprint "eagle-import:LED5MM")
      (libsource (lib "eagle-import") (part "LED5MM"))
    )
    (comp (ref "LED588")
      (value "LED5MM")
      (footprint "eagle-import:LED5MM")
      (libsource (lib "eagle-import") (part "LED5MM"))
    )
    (comp (ref "LED589")
      (value "LED5MM")
      (footprint "eagle-import:LED5MM")
      (libsource (lib "eagle-import") (part "LED5MM"))
    )
    (comp (ref "LED590")
      (value "LED5MM")
      (footprint "eagle-import:LED5MM")
      (libsource (lib "eagle-import") (part "LED5MM"))
    )
    (comp (ref "LED591")
      (value "LED5MM")
      (footprint "eagle-import:LED5MM")
      (libsource (lib "eagle-import") (part "LED5MM"))
    )
    (comp (ref "LED592")
      (value "LED5MM")
      (footprint "eagle-import:LED5MM")
      (libsource (lib "eagle-import") (part "LED5MM"))
    )
    (comp (ref "LED593")
      (value "LED5MM")
      (footprint "eagle-import:LED5MM")
      (libsource (lib "eagle-import") (part "LED5MM"))
    )
    (comp (ref "LED594")
      (value "LED5MM")
      (footprint "eagle-import:LED5MM")
      (libsource (lib "eagle-import") (part "LED5MM"))
    )
    (comp (ref "LED595")
      (value "LED5MM")
      (footprint "eagle-import:LED5MM")
      (libsource (lib "eagle-import") (part "LED5MM"))
    )
    (comp (ref "LED596")
      (value "LED5MM")
      (footprint "eagle-import:LED5MM")
      (libsource (lib "eagle-import") (part "LED5MM"))
    )
    (comp (ref "LED597")
      (value "LED5MM")
      (footprint "eagle-import:LED5MM")
      (libsource (lib "eagle-import") (part "LED5MM"))
    )
    (comp (ref "LED598")
      (value "LED5MM")
      (footprint "eagle-import:LED5MM")
      (libsource (lib "eagle-import") (part "LED5MM"))
    )
    (comp (ref "LED599")
      (value "LED5MM")
      (footprint "eagle-import:LED5MM")
      (libsource (lib "eagle-import") (part "LED5MM"))
    )
    (comp (ref "LED600")
      (value "LED5MM")
      (footprint "eagle-import:LED5MM")
      (libsource (lib "eagle-import") (part "LED5MM"))
    )
    (comp (ref "LED601")
      (value "LED5MM")
      (footprint "eagle-import:LED5MM")
      (libsource (lib "eagle-import") (part "LED5MM"))
    )
    (comp (ref "LED602")
      (value "LED5MM")
      (footprint "eagle-import:LED5MM")
      (libsource (lib "eagle-import") (part "LED5MM"))
    )
    (comp (ref "LED603")
      (value "LED5MM")
      (footprint "eagle-import:LED5MM")
      (libsource (lib "eagle-import") (part "LED5MM"))
    )
    (comp (ref "LED604")
      (value "LED5MM")
      (footprint "eagle-import:LED5MM")
      (libsource (lib "eagle-import") (part "LED5MM"))
    )
    (comp (ref "LED605")
      (value "LED5MM")
      (footprint "eagle-import:LED5MM")
      (libsource (lib "eagle-import") (part "LED5MM"))
    )
    (comp (ref "LED606")
      (value "LED5MM")
      (footprint "eagle-import:LED5MM")
      (libsource (lib "eagle-import") (part "LED5MM"))
    )
    (comp (ref "LED607")
      (value "LED5MM")
      (footprint "eagle-import:LED5MM")
      (libsource (lib "eagle-import") (part "LED5MM"))
    )
    (comp (ref "LED608")
      (value "LED5MM")
      (footprint "eagle-import:LED5MM")
      (libsource (lib "eagle-import") (part "LED5MM"))
    )
    (comp (ref "LED609")
      (value "LED5MM")
      (footprint "eagle-import:LED5MM")
      (libsource (lib "eagle-import") (part "LED5MM"))
    )
    (comp (ref "LED610")
      (value "LED5MM")
      (footprint "eagle-import:LED5MM")
      (libsource (lib "eagle-import") (part "LED5MM"))
    )
    (comp (ref "LED611")
      (value "LED5MM")
      (footprint "eagle-import:LED5MM")
      (libsource (lib "eagle-import") (part "LED5MM"))
    )
    (comp (ref "LED612")
      (value "LED5MM")
      (footprint "eagle-import:LED5MM")
      (libsource (lib "eagle-import") (part "LED5MM"))
    )
    (comp (ref "LED613")
      (value "LED5MM")
      (footprint "eagle-import:LED5MM")
      (libsource (lib "eagle-import") (part "LED5MM"))
    )
    (comp (ref "LED614")
      (value "LED5MM")
      (footprint "eagle-import:LED5MM")
      (libsource (lib "eagle-import") (part "LED5MM"))
    )
    (comp (ref "LED615")
      (value "LED5MM")
      (footprint "eagle-import:LED5MM")
      (libsource (lib "eagle-import") (part "LED5MM"))
    )
    (comp (ref "LED616")
      (value "LED5MM")
      (footprint "eagle-import:LED5MM")
      (libsource (lib "eagle-import") (part "LED5MM"))
    )
    (comp (ref "LED617")
      (value "LED5MM")
      (footprint "eagle-import:LED5MM")
      (libsource (lib "eagle-import") (part "LED5MM"))
    )
    (comp (ref "LED618")
      (value "LED5MM")
      (footprint "eagle-import:LED5MM")
      (libsource (lib "eagle-import") (part "LED5MM"))
    )
    (comp (ref "LED619")
      (value "LED5MM")
      (footprint "eagle-import:LED5MM")
      (libsource (lib "eagle-import") (part "LED5MM"))
    )
    (comp (ref "LED620")
      (value "LED5MM")
      (footprint "eagle-import:LED5MM")
      (libsource (lib "eagle-import") (part "LED5MM"))
    )
    (comp (ref "LED621")
      (value "LED5MM")
      (footprint "eagle-import:LED5MM")
      (libsource (lib "eagle-import") (part "LED5MM"))
    )
    (comp (ref "LED622")
      (value "LED5MM")
      (footprint "eagle-import:LED5MM")
      (libsource (lib "eagle-import") (part "LED5MM"))
    )
    (comp (ref "LED623")
      (value "LED5MM")
      (footprint "eagle-import:LED5MM")
      (libsource (lib "eagle-import") (part "LED5MM"))
    )
    (comp (ref "LED624")
      (value "LED5MM")
      (footprint "eagle-import:LED5MM")
      (libsource (lib "eagle-import") (part "LED5MM"))
    )
    (comp (ref "LED625")
      (value "LED5MM")
      (footprint "eagle-import:LED5MM")
      (libsource (lib "eagle-import") (part "LED5MM"))
    )
    (comp (ref "LED626")
      (value "LED5MM")
      (footprint "eagle-import:LED5MM")
      (libsource (lib "eagle-import") (part "LED5MM"))
    )
    (comp (ref "LED627")
      (value "LED5MM")
      (footprint "eagle-import:LED5MM")
      (libsource (lib "eagle-import") (part "LED5MM"))
    )
    (comp (ref "LED628")
      (value "LED5MM")
      (footprint "eagle-import:LED5MM")
      (libsource (lib "eagle-import") (part "LED5MM"))
    )
    (comp (ref "LED629")
      (value "LED5MM")
      (footprint "eagle-import:LED5MM")
      (libsource (lib "eagle-import") (part "LED5MM"))
    )
    (comp (ref "LED630")
      (value "LED5MM")
      (footprint "eagle-import:LED5MM")
      (libsource (lib "eagle-import") (part "LED5MM"))
    )
    (comp (ref "LED631")
      (value "LED5MM")
      (footprint "eagle-import:LED5MM")
      (libsource (lib "eagle-import") (part "LED5MM"))
    )
    (comp (ref "LED632")
      (value "LED5MM")
      (footprint "eagle-import:LED5MM")
      (libsource (lib "eagle-import") (part "LED5MM"))
    )
    (comp (ref "LED633")
      (value "LED5MM")
      (footprint "eagle-import:LED5MM")
      (libsource (lib "eagle-import") (part "LED5MM"))
    )
    (comp (ref "LED634")
      (value "LED5MM")
      (footprint "eagle-import:LED5MM")
      (libsource (lib "eagle-import") (part "LED5MM"))
    )
    (comp (ref "LED635")
      (value "LED5MM")
      (footprint "eagle-import:LED5MM")
      (libsource (lib "eagle-import") (part "LED5MM"))
    )
    (comp (ref "LED636")
      (value "LED5MM")
      (footprint "eagle-import:LED5MM")
      (libsource (lib "eagle-import") (part "LED5MM"))
    )
    (comp (ref "LED637")
      (value "LED5MM")
      (footprint "eagle-import:LED5MM")
      (libsource (lib "eagle-import") (part "LED5MM"))
    )
    (comp (ref "LED638")
      (value "LED5MM")
      (footprint "eagle-import:LED5MM")
      (libsource (lib "eagle-import") (part "LED5MM"))
    )
    (comp (ref "LED639")
      (value "LED5MM")
      (footprint "eagle-import:LED5MM")
      (libsource (lib "eagle-import") (part "LED5MM"))
    )
    (comp (ref "LED640")
      (value "LED5MM")
      (footprint "eagle-import:LED5MM")
      (libsource (lib "eagle-import") (part "LED5MM"))
    )
    (comp (ref "LED641")
      (value "LED5MM")
      (footprint "eagle-import:LED5MM")
      (libsource (lib "eagle-import") (part "LED5MM"))
    )
    (comp (ref "LED642")
      (value "LED5MM")
      (footprint "eagle-import:LED5MM")
      (libsource (lib "eagle-import") (part "LED5MM"))
    )
    (comp (ref "LED643")
      (value "LED5MM")
      (footprint "eagle-import:LED5MM")
      (libsource (lib "eagle-import") (part "LED5MM"))
    )
    (comp (ref "LED644")
      (value "LED5MM")
      (footprint "eagle-import:LED5MM")
      (libsource (lib "eagle-import") (part "LED5MM"))
    )
    (comp (ref "LED645")
      (value "LED5MM")
      (footprint "eagle-import:LED5MM")
      (libsource (lib "eagle-import") (part "LED5MM"))
    )
    (comp (ref "LED646")
      (value "LED5MM")
      (footprint "eagle-import:LED5MM")
      (libsource (lib "eagle-import") (part "LED5MM"))
    )
    (comp (ref "LED647")
      (value "LED5MM")
      (footprint "eagle-import:LED5MM")
      (libsource (lib "eagle-import") (part "LED5MM"))
    )
    (comp (ref "LED648")
      (value "LED5MM")
      (footprint "eagle-import:LED5MM")
      (libsource (lib "eagle-import") (part "LED5MM"))
    )
    (comp (ref "LED649")
      (value "LED5MM")
      (footprint "eagle-import:LED5MM")
      (libsource (lib "eagle-import") (part "LED5MM"))
    )
    (comp (ref "LED650")
      (value "LED5MM")
      (footprint "eagle-import:LED5MM")
      (libsource (lib "eagle-import") (part "LED5MM"))
    )
    (comp (ref "LED651")
      (value "LED5MM")
      (footprint "eagle-import:LED5MM")
      (libsource (lib "eagle-import") (part "LED5MM"))
    )
    (comp (ref "LED652")
      (value "LED5MM")
      (footprint "eagle-import:LED5MM")
      (libsource (lib "eagle-import") (part "LED5MM"))
    )
    (comp (ref "LED653")
      (value "LED5MM")
      (footprint "eagle-import:LED5MM")
      (libsource (lib "eagle-import") (part "LED5MM"))
    )
    (comp (ref "LED654")
      (value "LED5MM")
      (footprint "eagle-import:LED5MM")
      (libsource (lib "eagle-import") (part "LED5MM"))
    )
    (comp (ref "LED655")
      (value "LED5MM")
      (footprint "eagle-import:LED5MM")
      (libsource (lib "eagle-import") (part "LED5MM"))
    )
    (comp (ref "LED656")
      (value "LED5MM")
      (footprint "eagle-import:LED5MM")
      (libsource (lib "eagle-import") (part "LED5MM"))
    )
    (comp (ref "LED657")
      (value "LED5MM")
      (footprint "eagle-import:LED5MM")
      (libsource (lib "eagle-import") (part "LED5MM"))
    )
    (comp (ref "LED658")
      (value "LED5MM")
      (footprint "eagle-import:LED5MM")
      (libsource (lib "eagle-import") (part "LED5MM"))
    )
    (comp (ref "LED659")
      (value "LED5MM")
      (footprint "eagle-import:LED5MM")
      (libsource (lib "eagle-import") (part "LED5MM"))
    )
    (comp (ref "LED660")
      (value "LED5MM")
      (footprint "eagle-import:LED5MM")
      (libsource (lib "eagle-import") (part "LED5MM"))
    )
    (comp (ref "LED661")
      (value "LED5MM")
      (footprint "eagle-import:LED5MM")
      (libsource (lib "eagle-import") (part "LED5MM"))
    )
    (comp (ref "LED662")
      (value "LED5MM")
      (footprint "eagle-import:LED5MM")
      (libsource (lib "eagle-import") (part "LED5MM"))
    )
    (comp (ref "LED663")
      (value "LED5MM")
      (footprint "eagle-import:LED5MM")
      (libsource (lib "eagle-import") (part "LED5MM"))
    )
    (comp (ref "LED664")
      (value "LED5MM")
      (footprint "eagle-import:LED5MM")
      (libsource (lib "eagle-import") (part "LED5MM"))
    )
    (comp (ref "LED665")
      (value "LED5MM")
      (footprint "eagle-import:LED5MM")
      (libsource (lib "eagle-import") (part "LED5MM"))
    )
    (comp (ref "LED666")
      (value "LED5MM")
      (footprint "eagle-import:LED5MM")
      (libsource (lib "eagle-import") (part "LED5MM"))
    )
    (comp (ref "LED667")
      (value "LED5MM")
      (footprint "eagle-import:LED5MM")
      (libsource (lib "eagle-import") (part "LED5MM"))
    )
    (comp (ref "LED668")
      (value "LED5MM")
      (footprint "eagle-import:LED5MM")
      (libsource (lib "eagle-import") (part "LED5MM"))
    )
    (comp (ref "LED669")
      (value "LED5MM")
      (footprint "eagle-import:LED5MM")
      (libsource (lib "eagle-import") (part "LED5MM"))
    )
    (comp (ref "LED670")
      (value "LED5MM")
      (footprint "eagle-import:LED5MM")
      (libsource (lib "eagle-import") (part "LED5MM"))
    )
    (comp (ref "LED671")
      (value "LED5MM")
      (footprint "eagle-import:LED5MM")
      (libsource (lib "eagle-import") (part "LED5MM"))
    )
    (comp (ref "LED672")
      (value "LED5MM")
      (footprint "eagle-import:LED5MM")
      (libsource (lib "eagle-import") (part "LED5MM"))
    )
    (comp (ref "LED673")
      (value "LED5MM")
      (footprint "eagle-import:LED5MM")
      (libsource (lib "eagle-import") (part "LED5MM"))
    )
    (comp (ref "LED674")
      (value "LED5MM")
      (footprint "eagle-import:LED5MM")
      (libsource (lib "eagle-import") (part "LED5MM"))
    )
    (comp (ref "LED675")
      (value "LED5MM")
      (footprint "eagle-import:LED5MM")
      (libsource (lib "eagle-import") (part "LED5MM"))
    )
    (comp (ref "LED676")
      (value "LED5MM")
      (footprint "eagle-import:LED5MM")
      (libsource (lib "eagle-import") (part "LED5MM"))
    )
    (comp (ref "LED677")
      (value "LED5MM")
      (footprint "eagle-import:LED5MM")
      (libsource (lib "eagle-import") (part "LED5MM"))
    )
    (comp (ref "LED678")
      (value "LED5MM")
      (footprint "eagle-import:LED5MM")
      (libsource (lib "eagle-import") (part "LED5MM"))
    )
    (comp (ref "LED679")
      (value "LED5MM")
      (footprint "eagle-import:LED5MM")
      (libsource (lib "eagle-import") (part "LED5MM"))
    )
    (comp (ref "LED680")
      (value "LED5MM")
      (footprint "eagle-import:LED5MM")
      (libsource (lib "eagle-import") (part "LED5MM"))
    )
    (comp (ref "LED681")
      (value "LED5MM")
      (footprint "eagle-import:LED5MM")
      (libsource (lib "eagle-import") (part "LED5MM"))
    )
    (comp (ref "LED682")
      (value "LED5MM")
      (footprint "eagle-import:LED5MM")
      (libsource (lib "eagle-import") (part "LED5MM"))
    )
    (comp (ref "LED683")
      (value "LED5MM")
      (footprint "eagle-import:LED5MM")
      (libsource (lib "eagle-import") (part "LED5MM"))
    )
    (comp (ref "LED684")
      (value "LED5MM")
      (footprint "eagle-import:LED5MM")
      (libsource (lib "eagle-import") (part "LED5MM"))
    )
    (comp (ref "LED685")
      (value "LED5MM")
      (footprint "eagle-import:LED5MM")
      (libsource (lib "eagle-import") (part "LED5MM"))
    )
    (comp (ref "LED686")
      (value "LED5MM")
      (footprint "eagle-import:LED5MM")
      (libsource (lib "eagle-import") (part "LED5MM"))
    )
    (comp (ref "LED687")
      (value "LED5MM")
      (footprint "eagle-import:LED5MM")
      (libsource (lib "eagle-import") (part "LED5MM"))
    )
    (comp (ref "LED688")
      (value "LED5MM")
      (footprint "eagle-import:LED5MM")
      (libsource (lib "eagle-import") (part "LED5MM"))
    )
    (comp (ref "LED689")
      (value "LED5MM")
      (footprint "eagle-import:LED5MM")
      (libsource (lib "eagle-import") (part "LED5MM"))
    )
    (comp (ref "LED690")
      (value "LED5MM")
      (footprint "eagle-import:LED5MM")
      (libsource (lib "eagle-import") (part "LED5MM"))
    )
    (comp (ref "LED691")
      (value "LED5MM")
      (footprint "eagle-import:LED5MM")
      (libsource (lib "eagle-import") (part "LED5MM"))
    )
    (comp (ref "LED692")
      (value "LED5MM")
      (footprint "eagle-import:LED5MM")
      (libsource (lib "eagle-import") (part "LED5MM"))
    )
    (comp (ref "LED693")
      (value "LED5MM")
      (footprint "eagle-import:LED5MM")
      (libsource (lib "eagle-import") (part "LED5MM"))
    )
    (comp (ref "LED694")
      (value "LED5MM")
      (footprint "eagle-import:LED5MM")
      (libsource (lib "eagle-import") (part "LED5MM"))
    )
    (comp (ref "LED695")
      (value "LED5MM")
      (footprint "eagle-import:LED5MM")
      (libsource (lib "eagle-import") (part "LED5MM"))
    )
    (comp (ref "LED696")
      (value "LED5MM")
      (footprint "eagle-import:LED5MM")
      (libsource (lib "eagle-import") (part "LED5MM"))
    )
    (comp (ref "LED697")
      (value "LED5MM")
      (footprint "eagle-import:LED5MM")
      (libsource (lib "eagle-import") (part "LED5MM"))
    )
    (comp (ref "LED698")
      (value "LED5MM")
      (footprint "eagle-import:LED5MM")
      (libsource (lib "eagle-import") (part "LED5MM"))
    )
    (comp (ref "LED699")
      (value "LED5MM")
      (footprint "eagle-import:LED5MM")
      (libsource (lib "eagle-import") (part "LED5MM"))
    )
    (comp (ref "LED700")
      (value "LED5MM")
      (footprint "eagle-import:LED5MM")
      (libsource (lib "eagle-import") (part "LED5MM"))
    )
    (comp (ref "LED701")
      (value "LED5MM")
      (footprint "eagle-import:LED5MM")
      (libsource (lib "eagle-import") (part "LED5MM"))
    )
    (comp (ref "LED702")
      (value "LED5MM")
      (footprint "eagle-import:LED5MM")
      (libsource (lib "eagle-import") (part "LED5MM"))
    )
    (comp (ref "LED703")
      (value "LED5MM")
      (footprint "eagle-import:LED5MM")
      (libsource (lib "eagle-import") (part "LED5MM"))
    )
    (comp (ref "LED704")
      (value "LED5MM")
      (footprint "eagle-import:LED5MM")
      (libsource (lib "eagle-import") (part "LED5MM"))
    )
    (comp (ref "LED705")
      (value "LED5MM")
      (footprint "eagle-import:LED5MM")
      (libsource (lib "eagle-import") (part "LED5MM"))
    )
    (comp (ref "LED706")
      (value "LED5MM")
      (footprint "eagle-import:LED5MM")
      (libsource (lib "eagle-import") (part "LED5MM"))
    )
    (comp (ref "LED707")
      (value "LED5MM")
      (footprint "eagle-import:LED5MM")
      (libsource (lib "eagle-import") (part "LED5MM"))
    )
    (comp (ref "LED708")
      (value "LED5MM")
      (footprint "eagle-import:LED5MM")
      (libsource (lib "eagle-import") (part "LED5MM"))
    )
    (comp (ref "LED709")
      (value "LED5MM")
      (footprint "eagle-import:LED5MM")
      (libsource (lib "eagle-import") (part "LED5MM"))
    )
    (comp (ref "LED710")
      (value "LED5MM")
      (footprint "eagle-import:LED5MM")
      (libsource (lib "eagle-import") (part "LED5MM"))
    )
    (comp (ref "LED711")
      (value "LED5MM")
      (footprint "eagle-import:LED5MM")
      (libsource (lib "eagle-import") (part "LED5MM"))
    )
    (comp (ref "LED712")
      (value "LED5MM")
      (footprint "eagle-import:LED5MM")
      (libsource (lib "eagle-import") (part "LED5MM"))
    )
    (comp (ref "LED713")
      (value "LED5MM")
      (footprint "eagle-import:LED5MM")
      (libsource (lib "eagle-import") (part "LED5MM"))
    )
    (comp (ref "LED714")
      (value "LED5MM")
      (footprint "eagle-import:LED5MM")
      (libsource (lib "eagle-import") (part "LED5MM"))
    )
    (comp (ref "LED715")
      (value "LED5MM")
      (footprint "eagle-import:LED5MM")
      (libsource (lib "eagle-import") (part "LED5MM"))
    )
    (comp (ref "LED716")
      (value "LED5MM")
      (footprint "eagle-import:LED5MM")
      (libsource (lib "eagle-import") (part "LED5MM"))
    )
    (comp (ref "LED717")
      (value "LED5MM")
      (footprint "eagle-import:LED5MM")
      (libsource (lib "eagle-import") (part "LED5MM"))
    )
    (comp (ref "LED718")
      (value "LED5MM")
      (footprint "eagle-import:LED5MM")
      (libsource (lib "eagle-import") (part "LED5MM"))
    )
    (comp (ref "LED719")
      (value "LED5MM")
      (footprint "eagle-import:LED5MM")
      (libsource (lib "eagle-import") (part "LED5MM"))
    )
    (comp (ref "LED720")
      (value "LED5MM")
      (footprint "eagle-import:LED5MM")
      (libsource (lib "eagle-import") (part "LED5MM"))
    )
    (comp (ref "LED721")
      (value "LED5MM")
      (footprint "eagle-import:LED5MM")
      (libsource (lib "eagle-import") (part "LED5MM"))
    )
    (comp (ref "LED722")
      (value "LED5MM")
      (footprint "eagle-import:LED5MM")
      (libsource (lib "eagle-import") (part "LED5MM"))
    )
    (comp (ref "LED723")
      (value "LED5MM")
      (footprint "eagle-import:LED5MM")
      (libsource (lib "eagle-import") (part "LED5MM"))
    )
    (comp (ref "LED724")
      (value "LED5MM")
      (footprint "eagle-import:LED5MM")
      (libsource (lib "eagle-import") (part "LED5MM"))
    )
    (comp (ref "LED725")
      (value "LED5MM")
      (footprint "eagle-import:LED5MM")
      (libsource (lib "eagle-import") (part "LED5MM"))
    )
    (comp (ref "LED726")
      (value "LED5MM")
      (footprint "eagle-import:LED5MM")
      (libsource (lib "eagle-import") (part "LED5MM"))
    )
    (comp (ref "LED727")
      (value "LED5MM")
      (footprint "eagle-import:LED5MM")
      (libsource (lib "eagle-import") (part "LED5MM"))
    )
    (comp (ref "LED728")
      (value "LED5MM")
      (footprint "eagle-import:LED5MM")
      (libsource (lib "eagle-import") (part "LED5MM"))
    )
    (comp (ref "LED729")
      (value "LED5MM")
      (footprint "eagle-import:LED5MM")
      (libsource (lib "eagle-import") (part "LED5MM"))
    )
    (comp (ref "LED730")
      (value "LED5MM")
      (footprint "eagle-import:LED5MM")
      (libsource (lib "eagle-import") (part "LED5MM"))
    )
    (comp (ref "LED731")
      (value "LED5MM")
      (footprint "eagle-import:LED5MM")
      (libsource (lib "eagle-import") (part "LED5MM"))
    )
    (comp (ref "LED732")
      (value "LED5MM")
      (footprint "eagle-import:LED5MM")
      (libsource (lib "eagle-import") (part "LED5MM"))
    )
    (comp (ref "LED733")
      (value "LED5MM")
      (footprint "eagle-import:LED5MM")
      (libsource (lib "eagle-import") (part "LED5MM"))
    )
    (comp (ref "LED734")
      (value "LED5MM")
      (footprint "eagle-import:LED5MM")
      (libsource (lib "eagle-import") (part "LED5MM"))
    )
    (comp (ref "LED735")
      (value "LED5MM")
      (footprint "eagle-import:LED5MM")
      (libsource (lib "eagle-import") (part "LED5MM"))
    )
    (comp (ref "LED736")
      (value "LED5MM")
      (footprint "eagle-import:LED5MM")
      (libsource (lib "eagle-import") (part "LED5MM"))
    )
    (comp (ref "LED737")
      (value "LED5MM")
      (footprint "eagle-import:LED5MM")
      (libsource (lib "eagle-import") (part "LED5MM"))
    )
    (comp (ref "LED738")
      (value "LED5MM")
      (footprint "eagle-import:LED5MM")
      (libsource (lib "eagle-import") (part "LED5MM"))
    )
    (comp (ref "LED739")
      (value "LED5MM")
      (footprint "eagle-import:LED5MM")
      (libsource (lib "eagle-import") (part "LED5MM"))
    )
    (comp (ref "LED740")
      (value "LED5MM")
      (footprint "eagle-import:LED5MM")
      (libsource (lib "eagle-import") (part "LED5MM"))
    )
    (comp (ref "LED741")
      (value "LED5MM")
      (footprint "eagle-import:LED5MM")
      (libsource (lib "eagle-import") (part "LED5MM"))
    )
    (comp (ref "LED742")
      (value "LED5MM")
      (footprint "eagle-import:LED5MM")
      (libsource (lib "eagle-import") (part "LED5MM"))
    )
    (comp (ref "LED743")
      (value "LED5MM")
      (footprint "eagle-import:LED5MM")
      (libsource (lib "eagle-import") (part "LED5MM"))
    )
    (comp (ref "LED744")
      (value "LED5MM")
      (footprint "eagle-import:LED5MM")
      (libsource (lib "eagle-import") (part "LED5MM"))
    )
    (comp (ref "LED745")
      (value "LED5MM")
      (footprint "eagle-import:LED5MM")
      (libsource (lib "eagle-import") (part "LED5MM"))
    )
    (comp (ref "LED746")
      (value "LED5MM")
      (footprint "eagle-import:LED5MM")
      (libsource (lib "eagle-import") (part "LED5MM"))
    )
    (comp (ref "LED747")
      (value "LED5MM")
      (footprint "eagle-import:LED5MM")
      (libsource (lib "eagle-import") (part "LED5MM"))
    )
    (comp (ref "LED748")
      (value "LED5MM")
      (footprint "eagle-import:LED5MM")
      (libsource (lib "eagle-import") (part "LED5MM"))
    )
    (comp (ref "LED749")
      (value "LED5MM")
      (footprint "eagle-import:LED5MM")
      (libsource (lib "eagle-import") (part "LED5MM"))
    )
    (comp (ref "LED750")
      (value "LED5MM")
      (footprint "eagle-import:LED5MM")
      (libsource (lib "eagle-import") (part "LED5MM"))
    )
    (comp (ref "LED751")
      (value "LED5MM")
      (footprint "eagle-import:LED5MM")
      (libsource (lib "eagle-import") (part "LED5MM"))
    )
    (comp (ref "LED752")
      (value "LED5MM")
      (footprint "eagle-import:LED5MM")
      (libsource (lib "eagle-import") (part "LED5MM"))
    )
    (comp (ref "LED753")
      (value "LED5MM")
      (footprint "eagle-import:LED5MM")
      (libsource (lib "eagle-import") (part "LED5MM"))
    )
    (comp (ref "LED754")
      (value "LED5MM")
      (footprint "eagle-import:LED5MM")
      (libsource (lib "eagle-import") (part "LED5MM"))
    )
    (comp (ref "LED755")
      (value "LED5MM")
      (footprint "eagle-import:LED5MM")
      (libsource (lib "eagle-import") (part "LED5MM"))
    )
    (comp (ref "LED756")
      (value "LED5MM")
      (footprint "eagle-import:LED5MM")
      (libsource (lib "eagle-import") (part "LED5MM"))
    )
    (comp (ref "LED757")
      (value "LED5MM")
      (footprint "eagle-import:LED5MM")
      (libsource (lib "eagle-import") (part "LED5MM"))
    )
    (comp (ref "LED758")
      (value "LED5MM")
      (footprint "eagle-import:LED5MM")
      (libsource (lib "eagle-import") (part "LED5MM"))
    )
    (comp (ref "LED759")
      (value "LED5MM")
      (footprint "eagle-import:LED5MM")
      (libsource (lib "eagle-import") (part "LED5MM"))
    )
    (comp (ref "LED760")
      (value "LED5MM")
      (footprint "eagle-import:LED5MM")
      (libsource (lib "eagle-import") (part "LED5MM"))
    )
    (comp (ref "LED761")
      (value "LED5MM")
      (footprint "eagle-import:LED5MM")
      (libsource (lib "eagle-import") (part "LED5MM"))
    )
    (comp (ref "LED762")
      (value "LED5MM")
      (footprint "eagle-import:LED5MM")
      (libsource (lib "eagle-import") (part "LED5MM"))
    )
    (comp (ref "LED763")
      (value "LED5MM")
      (footprint "eagle-import:LED5MM")
      (libsource (lib "eagle-import") (part "LED5MM"))
    )
    (comp (ref "LED764")
      (value "LED5MM")
      (footprint "eagle-import:LED5MM")
      (libsource (lib "eagle-import") (part "LED5MM"))
    )
    (comp (ref "LED765")
      (value "LED5MM")
      (footprint "eagle-import:LED5MM")
      (libsource (lib "eagle-import") (part "LED5MM"))
    )
    (comp (ref "LED766")
      (value "LED5MM")
      (footprint "eagle-import:LED5MM")
      (libsource (lib "eagle-import") (part "LED5MM"))
    )
    (comp (ref "LED767")
      (value "LED5MM")
      (footprint "eagle-import:LED5MM")
      (libsource (lib "eagle-import") (part "LED5MM"))
    )
    (comp (ref "LED768")
      (value "LED5MM")
      (footprint "eagle-import:LED5MM")
      (libsource (lib "eagle-import") (part "LED5MM"))
    )
    (comp (ref "LED769")
      (value "LED5MM")
      (footprint "eagle-import:LED5MM")
      (libsource (lib "eagle-import") (part "LED5MM"))
    )
    (comp (ref "LED770")
      (value "LED5MM")
      (footprint "eagle-import:LED5MM")
      (libsource (lib "eagle-import") (part "LED5MM"))
    )
    (comp (ref "LED771")
      (value "LED5MM")
      (footprint "eagle-import:LED5MM")
      (libsource (lib "eagle-import") (part "LED5MM"))
    )
    (comp (ref "LED772")
      (value "LED5MM")
      (footprint "eagle-import:LED5MM")
      (libsource (lib "eagle-import") (part "LED5MM"))
    )
    (comp (ref "LED773")
      (value "LED5MM")
      (footprint "eagle-import:LED5MM")
      (libsource (lib "eagle-import") (part "LED5MM"))
    )
    (comp (ref "LED774")
      (value "LED5MM")
      (footprint "eagle-import:LED5MM")
      (libsource (lib "eagle-import") (part "LED5MM"))
    )
    (comp (ref "LED775")
      (value "LED5MM")
      (footprint "eagle-import:LED5MM")
      (libsource (lib "eagle-import") (part "LED5MM"))
    )
    (comp (ref "LED776")
      (value "LED5MM")
      (footprint "eagle-import:LED5MM")
      (libsource (lib "eagle-import") (part "LED5MM"))
    )
    (comp (ref "LED777")
      (value "LED5MM")
      (footprint "eagle-import:LED5MM")
      (libsource (lib "eagle-import") (part "LED5MM"))
    )
    (comp (ref "LED778")
      (value "LED5MM")
      (footprint "eagle-import:LED5MM")
      (libsource (lib "eagle-import") (part "LED5MM"))
    )
    (comp (ref "LED779")
      (value "LED5MM")
      (footprint "eagle-import:LED5MM")
      (libsource (lib "eagle-import") (part "LED5MM"))
    )
    (comp (ref "LED780")
      (value "LED5MM")
      (footprint "eagle-import:LED5MM")
      (libsource (lib "eagle-import") (part "LED5MM"))
    )
    (comp (ref "LED781")
      (value "LED5MM")
      (footprint "eagle-import:LED5MM")
      (libsource (lib "eagle-import") (part "LED5MM"))
    )
    (comp (ref "LED782")
      (value "LED5MM")
      (footprint "eagle-import:LED5MM")
      (libsource (lib "eagle-import") (part "LED5MM"))
    )
    (comp (ref "LED783")
      (value "LED5MM")
      (footprint "eagle-import:LED5MM")
      (libsource (lib "eagle-import") (part "LED5MM"))
    )
    (comp (ref "LED784")
      (value "LED5MM")
      (footprint "eagle-import:LED5MM")
      (libsource (lib "eagle-import") (part "LED5MM"))
    )
    (comp (ref "LED785")
      (value "LED5MM")
      (footprint "eagle-import:LED5MM")
      (libsource (lib "eagle-import") (part "LED5MM"))
    )
    (comp (ref "LED786")
      (value "LED5MM")
      (footprint "eagle-import:LED5MM")
      (libsource (lib "eagle-import") (part "LED5MM"))
    )
    (comp (ref "LED787")
      (value "LED5MM")
      (footprint "eagle-import:LED5MM")
      (libsource (lib "eagle-import") (part "LED5MM"))
    )
    (comp (ref "LED788")
      (value "LED5MM")
      (footprint "eagle-import:LED5MM")
      (libsource (lib "eagle-import") (part "LED5MM"))
    )
    (comp (ref "LED789")
      (value "LED5MM")
      (footprint "eagle-import:LED5MM")
      (libsource (lib "eagle-import") (part "LED5MM"))
    )
    (comp (ref "LED790")
      (value "LED5MM")
      (footprint "eagle-import:LED5MM")
      (libsource (lib "eagle-import") (part "LED5MM"))
    )
    (comp (ref "LED791")
      (value "LED5MM")
      (footprint "eagle-import:LED5MM")
      (libsource (lib "eagle-import") (part "LED5MM"))
    )
    (comp (ref "LED792")
      (value "LED5MM")
      (footprint "eagle-import:LED5MM")
      (libsource (lib "eagle-import") (part "LED5MM"))
    )
    (comp (ref "LED793")
      (value "LED5MM")
      (footprint "eagle-import:LED5MM")
      (libsource (lib "eagle-import") (part "LED5MM"))
    )
    (comp (ref "LED794")
      (value "LED5MM")
      (footprint "eagle-import:LED5MM")
      (libsource (lib "eagle-import") (part "LED5MM"))
    )
    (comp (ref "LED795")
      (value "LED5MM")
      (footprint "eagle-import:LED5MM")
      (libsource (lib "eagle-import") (part "LED5MM"))
    )
    (comp (ref "LED796")
      (value "LED5MM")
      (footprint "eagle-import:LED5MM")
      (libsource (lib "eagle-import") (part "LED5MM"))
    )
    (comp (ref "LED797")
      (value "LED5MM")
      (footprint "eagle-import:LED5MM")
      (libsource (lib "eagle-import") (part "LED5MM"))
    )
    (comp (ref "LED798")
      (value "LED5MM")
      (footprint "eagle-import:LED5MM")
      (libsource (lib "eagle-import") (part "LED5MM"))
    )
    (comp (ref "LED799")
      (value "LED5MM")
      (footprint "eagle-import:LED5MM")
      (libsource (lib "eagle-import") (part "LED5MM"))
    )
    (comp (ref "LED800")
      (value "LED5MM")
      (footprint "eagle-import:LED5MM")
      (libsource (lib "eagle-import") (part "LED5MM"))
    )
    (comp (ref "LED801")
      (value "LED5MM")
      (footprint "eagle-import:LED5MM")
      (libsource (lib "eagle-import") (part "LED5MM"))
    )
    (comp (ref "LED802")
      (value "LED5MM")
      (footprint "eagle-import:LED5MM")
      (libsource (lib "eagle-import") (part "LED5MM"))
    )
    (comp (ref "LED803")
      (value "LED5MM")
      (footprint "eagle-import:LED5MM")
      (libsource (lib "eagle-import") (part "LED5MM"))
    )
    (comp (ref "LED804")
      (value "LED5MM")
      (footprint "eagle-import:LED5MM")
      (libsource (lib "eagle-import") (part "LED5MM"))
    )
    (comp (ref "LED805")
      (value "LED5MM")
      (footprint "eagle-import:LED5MM")
      (libsource (lib "eagle-import") (part "LED5MM"))
    )
    (comp (ref "LED806")
      (value "LED5MM")
      (footprint "eagle-import:LED5MM")
      (libsource (lib "eagle-import") (part "LED5MM"))
    )
    (comp (ref "LED807")
      (value "LED5MM")
      (footprint "eagle-import:LED5MM")
      (libsource (lib "eagle-import") (part "LED5MM"))
    )
    (comp (ref "LED808")
      (value "LED5MM")
      (footprint "eagle-import:LED5MM")
      (libsource (lib "eagle-import") (part "LED5MM"))
    )
    (comp (ref "LED809")
      (value "LED5MM")
      (footprint "eagle-import:LED5MM")
      (libsource (lib "eagle-import") (part "LED5MM"))
    )
    (comp (ref "LED810")
      (value "LED5MM")
      (footprint "eagle-import:LED5MM")
      (libsource (lib "eagle-import") (part "LED5MM"))
    )
    (comp (ref "LED811")
      (value "LED5MM")
      (footprint "eagle-import:LED5MM")
      (libsource (lib "eagle-import") (part "LED5MM"))
    )
    (comp (ref "LED812")
      (value "LED5MM")
      (footprint "eagle-import:LED5MM")
      (libsource (lib "eagle-import") (part "LED5MM"))
    )
    (comp (ref "LED813")
      (value "LED5MM")
      (footprint "eagle-import:LED5MM")
      (libsource (lib "eagle-import") (part "LED5MM"))
    )
    (comp (ref "LED814")
      (value "LED5MM")
      (footprint "eagle-import:LED5MM")
      (libsource (lib "eagle-import") (part "LED5MM"))
    )
    (comp (ref "LED815")
      (value "LED5MM")
      (footprint "eagle-import:LED5MM")
      (libsource (lib "eagle-import") (part "LED5MM"))
    )
    (comp (ref "LED816")
      (value "LED5MM")
      (footprint "eagle-import:LED5MM")
      (libsource (lib "eagle-import") (part "LED5MM"))
    )
    (comp (ref "LED817")
      (value "LED5MM")
      (footprint "eagle-import:LED5MM")
      (libsource (lib "eagle-import") (part "LED5MM"))
    )
    (comp (ref "LED818")
      (value "LED5MM")
      (footprint "eagle-import:LED5MM")
      (libsource (lib "eagle-import") (part "LED5MM"))
    )
    (comp (ref "LED819")
      (value "LED5MM")
      (footprint "eagle-import:LED5MM")
      (libsource (lib "eagle-import") (part "LED5MM"))
    )
    (comp (ref "LED820")
      (value "LED5MM")
      (footprint "eagle-import:LED5MM")
      (libsource (lib "eagle-import") (part "LED5MM"))
    )
    (comp (ref "LED821")
      (value "LED5MM")
      (footprint "eagle-import:LED5MM")
      (libsource (lib "eagle-import") (part "LED5MM"))
    )
    (comp (ref "LED822")
      (value "LED5MM")
      (footprint "eagle-import:LED5MM")
      (libsource (lib "eagle-import") (part "LED5MM"))
    )
    (comp (ref "LED823")
      (value "LED5MM")
      (footprint "eagle-import:LED5MM")
      (libsource (lib "eagle-import") (part "LED5MM"))
    )
    (comp (ref "LED824")
      (value "LED5MM")
      (footprint "eagle-import:LED5MM")
      (libsource (lib "eagle-import") (part "LED5MM"))
    )
    (comp (ref "LED825")
      (value "LED5MM")
      (footprint "eagle-import:LED5MM")
      (libsource (lib "eagle-import") (part "LED5MM"))
    )
    (comp (ref "LED826")
      (value "LED5MM")
      (footprint "eagle-import:LED5MM")
      (libsource (lib "eagle-import") (part "LED5MM"))
    )
    (comp (ref "LED827")
      (value "LED5MM")
      (footprint "eagle-import:LED5MM")
      (libsource (lib "eagle-import") (part "LED5MM"))
    )
    (comp (ref "LED828")
      (value "LED5MM")
      (footprint "eagle-import:LED5MM")
      (libsource (lib "eagle-import") (part "LED5MM"))
    )
    (comp (ref "LED829")
      (value "LED5MM")
      (footprint "eagle-import:LED5MM")
      (libsource (lib "eagle-import") (part "LED5MM"))
    )
    (comp (ref "LED830")
      (value "LED5MM")
      (footprint "eagle-import:LED5MM")
      (libsource (lib "eagle-import") (part "LED5MM"))
    )
    (comp (ref "LED831")
      (value "LED5MM")
      (footprint "eagle-import:LED5MM")
      (libsource (lib "eagle-import") (part "LED5MM"))
    )
    (comp (ref "LED832")
      (value "LED5MM")
      (footprint "eagle-import:LED5MM")
      (libsource (lib "eagle-import") (part "LED5MM"))
    )
    (comp (ref "LED833")
      (value "LED5MM")
      (footprint "eagle-import:LED5MM")
      (libsource (lib "eagle-import") (part "LED5MM"))
    )
    (comp (ref "LED834")
      (value "LED5MM")
      (footprint "eagle-import:LED5MM")
      (libsource (lib "eagle-import") (part "LED5MM"))
    )
    (comp (ref "LED835")
      (value "LED5MM")
      (footprint "eagle-import:LED5MM")
      (libsource (lib "eagle-import") (part "LED5MM"))
    )
    (comp (ref "LED836")
      (value "LED5MM")
      (footprint "eagle-import:LED5MM")
      (libsource (lib "eagle-import") (part "LED5MM"))
    )
    (comp (ref "LED837")
      (value "LED5MM")
      (footprint "eagle-import:LED5MM")
      (libsource (lib "eagle-import") (part "LED5MM"))
    )
    (comp (ref "LED838")
      (value "LED5MM")
      (footprint "eagle-import:LED5MM")
      (libsource (lib "eagle-import") (part "LED5MM"))
    )
    (comp (ref "LED839")
      (value "LED5MM")
      (footprint "eagle-import:LED5MM")
      (libsource (lib "eagle-import") (part "LED5MM"))
    )
    (comp (ref "LED840")
      (value "LED5MM")
      (footprint "eagle-import:LED5MM")
      (libsource (lib "eagle-import") (part "LED5MM"))
    )
    (comp (ref "LED841")
      (value "LED5MM")
      (footprint "eagle-import:LED5MM")
      (libsource (lib "eagle-import") (part "LED5MM"))
    )
    (comp (ref "LED842")
      (value "LED5MM")
      (footprint "eagle-import:LED5MM")
      (libsource (lib "eagle-import") (part "LED5MM"))
    )
    (comp (ref "LED843")
      (value "LED5MM")
      (footprint "eagle-import:LED5MM")
      (libsource (lib "eagle-import") (part "LED5MM"))
    )
    (comp (ref "LED844")
      (value "LED5MM")
      (footprint "eagle-import:LED5MM")
      (libsource (lib "eagle-import") (part "LED5MM"))
    )
    (comp (ref "LED845")
      (value "LED5MM")
      (footprint "eagle-import:LED5MM")
      (libsource (lib "eagle-import") (part "LED5MM"))
    )
    (comp (ref "LED846")
      (value "LED5MM")
      (footprint "eagle-import:LED5MM")
      (libsource (lib "eagle-import") (part "LED5MM"))
    )
    (comp (ref "LED847")
      (value "LED5MM")
      (footprint "eagle-import:LED5MM")
      (libsource (lib "eagle-import") (part "LED5MM"))
    )
    (comp (ref "LED848")
      (value "LED5MM")
      (footprint "eagle-import:LED5MM")
      (libsource (lib "eagle-import") (part "LED5MM"))
    )
    (comp (ref "LED849")
      (value "LED5MM")
      (footprint "eagle-import:LED5MM")
      (libsource (lib "eagle-import") (part "LED5MM"))
    )
    (comp (ref "LED850")
      (value "LED5MM")
      (footprint "eagle-import:LED5MM")
      (libsource (lib "eagle-import") (part "LED5MM"))
    )
    (comp (ref "LED851")
      (value "LED5MM")
      (footprint "eagle-import:LED5MM")
      (libsource (lib "eagle-import") (part "LED5MM"))
    )
    (comp (ref "LED852")
      (value "LED5MM")
      (footprint "eagle-import:LED5MM")
      (libsource (lib "eagle-import") (part "LED5MM"))
    )
    (comp (ref "LED853")
      (value "LED5MM")
      (footprint "eagle-import:LED5MM")
      (libsource (lib "eagle-import") (part "LED5MM"))
    )
    (comp (ref "LED854")
      (value "LED5MM")
      (footprint "eagle-import:LED5MM")
      (libsource (lib "eagle-import") (part "LED5MM"))
    )
    (comp (ref "LED855")
      (value "LED5MM")
      (footprint "eagle-import:LED5MM")
      (libsource (lib "eagle-import") (part "LED5MM"))
    )
    (comp (ref "LED856")
      (value "LED5MM")
      (footprint "eagle-import:LED5MM")
      (libsource (lib "eagle-import") (part "LED5MM"))
    )
    (comp (ref "LED857")
      (value "LED5MM")
      (footprint "eagle-import:LED5MM")
      (libsource (lib "eagle-import") (part "LED5MM"))
    )
    (comp (ref "LED858")
      (value "LED5MM")
      (footprint "eagle-import:LED5MM")
      (libsource (lib "eagle-import") (part "LED5MM"))
    )
    (comp (ref "LED859")
      (value "LED5MM")
      (footprint "eagle-import:LED5MM")
      (libsource (lib "eagle-import") (part "LED5MM"))
    )
    (comp (ref "LED860")
      (value "LED5MM")
      (footprint "eagle-import:LED5MM")
      (libsource (lib "eagle-import") (part "LED5MM"))
    )
    (comp (ref "LED861")
      (value "LED5MM")
      (footprint "eagle-import:LED5MM")
      (libsource (lib "eagle-import") (part "LED5MM"))
    )
    (comp (ref "LED862")
      (value "LED5MM")
      (footprint "eagle-import:LED5MM")
      (libsource (lib "eagle-import") (part "LED5MM"))
    )
    (comp (ref "LED863")
      (value "LED5MM")
      (footprint "eagle-import:LED5MM")
      (libsource (lib "eagle-import") (part "LED5MM"))
    )
    (comp (ref "LED864")
      (value "LED5MM")
      (footprint "eagle-import:LED5MM")
      (libsource (lib "eagle-import") (part "LED5MM"))
    )
    (comp (ref "LED865")
      (value "LED5MM")
      (footprint "eagle-import:LED5MM")
      (libsource (lib "eagle-import") (part "LED5MM"))
    )
    (comp (ref "LED866")
      (value "LED5MM")
      (footprint "eagle-import:LED5MM")
      (libsource (lib "eagle-import") (part "LED5MM"))
    )
    (comp (ref "LED867")
      (value "LED5MM")
      (footprint "eagle-import:LED5MM")
      (libsource (lib "eagle-import") (part "LED5MM"))
    )
    (comp (ref "LED868")
      (value "LED5MM")
      (footprint "eagle-import:LED5MM")
      (libsource (lib "eagle-import") (part "LED5MM"))
    )
    (comp (ref "LED869")
      (value "LED5MM")
      (footprint "eagle-import:LED5MM")
      (libsource (lib "eagle-import") (part "LED5MM"))
    )
    (comp (ref "LED870")
      (value "LED5MM")
      (footprint "eagle-import:LED5MM")
      (libsource (lib "eagle-import") (part "LED5MM"))
    )
    (comp (ref "LED871")
      (value "LED5MM")
      (footprint "eagle-import:LED5MM")
      (libsource (lib "eagle-import") (part "LED5MM"))
    )
    (comp (ref "LED872")
      (value "LED5MM")
      (footprint "eagle-import:LED5MM")
      (libsource (lib "eagle-import") (part "LED5MM"))
    )
    (comp (ref "LED873")
      (value "LED5MM")
      (footprint "eagle-import:LED5MM")
      (libsource (lib "eagle-import") (part "LED5MM"))
    )
    (comp (ref "LED874")
      (value "LED5MM")
      (footprint "eagle-import:LED5MM")
      (libsource (lib "eagle-import") (part "LED5MM"))
    )
    (comp (ref "LED875")
      (value "LED5MM")
      (footprint "eagle-import:LED5MM")
      (libsource (lib "eagle-import") (part "LED5MM"))
    )
    (comp (ref "LED876")
      (value "LED5MM")
      (footprint "eagle-import:LED5MM")
      (libsource (lib "eagle-import") (part "LED5MM"))
    )
    (comp (ref "LED877")
      (value "LED5MM")
      (footprint "eagle-import:LED5MM")
      (libsource (lib "eagle-import") (part "LED5MM"))
    )
    (comp (ref "LED878")
      (value "LED5MM")
      (footprint "eagle-import:LED5MM")
      (libsource (lib "eagle-import") (part "LED5MM"))
    )
    (comp (ref "LED879")
      (value "LED5MM")
      (footprint "eagle-import:LED5MM")
      (libsource (lib "eagle-import") (part "LED5MM"))
    )
    (comp (ref "LED880")
      (value "LED5MM")
      (footprint "eagle-import:LED5MM")
      (libsource (lib "eagle-import") (part "LED5MM"))
    )
    (comp (ref "LED881")
      (value "LED5MM")
      (footprint "eagle-import:LED5MM")
      (libsource (lib "eagle-import") (part "LED5MM"))
    )
    (comp (ref "LED882")
      (value "LED5MM")
      (footprint "eagle-import:LED5MM")
      (libsource (lib "eagle-import") (part "LED5MM"))
    )
    (comp (ref "LED883")
      (value "LED5MM")
      (footprint "eagle-import:LED5MM")
      (libsource (lib "eagle-import") (part "LED5MM"))
    )
    (comp (ref "LED884")
      (value "LED5MM")
      (footprint "eagle-import:LED5MM")
      (libsource (lib "eagle-import") (part "LED5MM"))
    )
    (comp (ref "LED885")
      (value "LED5MM")
      (footprint "eagle-import:LED5MM")
      (libsource (lib "eagle-import") (part "LED5MM"))
    )
    (comp (ref "LED886")
      (value "LED5MM")
      (footprint "eagle-import:LED5MM")
      (libsource (lib "eagle-import") (part "LED5MM"))
    )
    (comp (ref "LED887")
      (value "LED5MM")
      (footprint "eagle-import:LED5MM")
      (libsource (lib "eagle-import") (part "LED5MM"))
    )
    (comp (ref "LED888")
      (value "LED5MM")
      (footprint "eagle-import:LED5MM")
      (libsource (lib "eagle-import") (part "LED5MM"))
    )
    (comp (ref "LED889")
      (value "LED5MM")
      (footprint "eagle-import:LED5MM")
      (libsource (lib "eagle-import") (part "LED5MM"))
    )
    (comp (ref "LED890")
      (value "LED5MM")
      (footprint "eagle-import:LED5MM")
      (libsource (lib "eagle-import") (part "LED5MM"))
    )
    (comp (ref "LED891")
      (value "LED5MM")
      (footprint "eagle-import:LED5MM")
      (libsource (lib "eagle-import") (part "LED5MM"))
    )
    (comp (ref "LED892")
      (value "LED5MM")
      (footprint "eagle-import:LED5MM")
      (libsource (lib "eagle-import") (part "LED5MM"))
    )
    (comp (ref "LED893")
      (value "LED5MM")
      (footprint "eagle-import:LED5MM")
      (libsource (lib "eagle-import") (part "LED5MM"))
    )
    (comp (ref "LED894")
      (value "LED5MM")
      (footprint "eagle-import:LED5MM")
      (libsource (lib "eagle-import") (part "LED5MM"))
    )
    (comp (ref "LED895")
      (value "LED5MM")
      (footprint "eagle-import:LED5MM")
      (libsource (lib "eagle-import") (part "LED5MM"))
    )
    (comp (ref "LED896")
      (value "LED5MM")
      (footprint "eagle-import:LED5MM")
      (libsource (lib "eagle-import") (part "LED5MM"))
    )
    (comp (ref "LED897")
      (value "LED5MM")
      (footprint "eagle-import:LED5MM")
      (libsource (lib "eagle-import") (part "LED5MM"))
    )
    (comp (ref "LED898")
      (value "LED5MM")
      (footprint "eagle-import:LED5MM")
      (libsource (lib "eagle-import") (part "LED5MM"))
    )
    (comp (ref "LED899")
      (value "LED5MM")
      (footprint "eagle-import:LED5MM")
      (libsource (lib "eagle-import") (part "LED5MM"))
    )
    (comp (ref "LED900")
      (value "LED5MM")
      (footprint "eagle-import:LED5MM")
      (libsource (lib "eagle-import") (part "LED5MM"))
    )
    (comp (ref "LED901")
      (value "LED5MM")
      (footprint "eagle-import:LED5MM")
      (libsource (lib "eagle-import") (part "LED5MM"))
    )
    (comp (ref "LED902")
      (value "LED5MM")
      (footprint "eagle-import:LED5MM")
      (libsource (lib "eagle-import") (part "LED5MM"))
    )
    (comp (ref "LED903")
      (value "LED5MM")
      (footprint "eagle-import:LED5MM")
      (libsource (lib "eagle-import") (part "LED5MM"))
    )
    (comp (ref "LED904")
      (value "LED5MM")
      (footprint "eagle-import:LED5MM")
      (libsource (lib "eagle-import") (part "LED5MM"))
    )
    (comp (ref "LED905")
      (value "LED5MM")
      (footprint "eagle-import:LED5MM")
      (libsource (lib "eagle-import") (part "LED5MM"))
    )
    (comp (ref "LED906")
      (value "LED5MM")
      (footprint "eagle-import:LED5MM")
      (libsource (lib "eagle-import") (part "LED5MM"))
    )
    (comp (ref "LED907")
      (value "LED5MM")
      (footprint "eagle-import:LED5MM")
      (libsource (lib "eagle-import") (part "LED5MM"))
    )
    (comp (ref "LED908")
      (value "LED5MM")
      (footprint "eagle-import:LED5MM")
      (libsource (lib "eagle-import") (part "LED5MM"))
    )
    (comp (ref "LED909")
      (value "LED5MM")
      (footprint "eagle-import:LED5MM")
      (libsource (lib "eagle-import") (part "LED5MM"))
    )
    (comp (ref "LED910")
      (value "LED5MM")
      (footprint "eagle-import:LED5MM")
      (libsource (lib "eagle-import") (part "LED5MM"))
    )
    (comp (ref "LED911")
      (value "LED5MM")
      (footprint "eagle-import:LED5MM")
      (libsource (lib "eagle-import") (part "LED5MM"))
    )
    (comp (ref "LED912")
      (value "LED5MM")
      (footprint "eagle-import:LED5MM")
      (libsource (lib "eagle-import") (part "LED5MM"))
    )
    (comp (ref "LED913")
      (value "LED5MM")
      (footprint "eagle-import:LED5MM")
      (libsource (lib "eagle-import") (part "LED5MM"))
    )
    (comp (ref "LED914")
      (value "LED5MM")
      (footprint "eagle-import:LED5MM")
      (libsource (lib "eagle-import") (part "LED5MM"))
    )
    (comp (ref "LED915")
      (value "LED5MM")
      (footprint "eagle-import:LED5MM")
      (libsource (lib "eagle-import") (part "LED5MM"))
    )
    (comp (ref "LED916")
      (value "LED5MM")
      (footprint "eagle-import:LED5MM")
      (libsource (lib "eagle-import") (part "LED5MM"))
    )
    (comp (ref "LED917")
      (value "LED5MM")
      (footprint "eagle-import:LED5MM")
      (libsource (lib "eagle-import") (part "LED5MM"))
    )
    (comp (ref "LED918")
      (value "LED5MM")
      (footprint "eagle-import:LED5MM")
      (libsource (lib "eagle-import") (part "LED5MM"))
    )
    (comp (ref "LED919")
      (value "LED5MM")
      (footprint "eagle-import:LED5MM")
      (libsource (lib "eagle-import") (part "LED5MM"))
    )
    (comp (ref "LED920")
      (value "LED5MM")
      (footprint "eagle-import:LED5MM")
      (libsource (lib "eagle-import") (part "LED5MM"))
    )
    (comp (ref "LED921")
      (value "LED5MM")
      (footprint "eagle-import:LED5MM")
      (libsource (lib "eagle-import") (part "LED5MM"))
    )
    (comp (ref "LED922")
      (value "LED5MM")
      (footprint "eagle-import:LED5MM")
      (libsource (lib "eagle-import") (part "LED5MM"))
    )
    (comp (ref "LED923")
      (value "LED5MM")
      (footprint "eagle-import:LED5MM")
      (libsource (lib "eagle-import") (part "LED5MM"))
    )
    (comp (ref "LED924")
      (value "LED5MM")
      (footprint "eagle-import:LED5MM")
      (libsource (lib "eagle-import") (part "LED5MM"))
    )
    (comp (ref "LED925")
      (value "LED5MM")
      (footprint "eagle-import:LED5MM")
      (libsource (lib "eagle-import") (part "LED5MM"))
    )
    (comp (ref "LED926")
      (value "LED5MM")
      (footprint "eagle-import:LED5MM")
      (libsource (lib "eagle-import") (part "LED5MM"))
    )
    (comp (ref "LED927")
      (value "LED5MM")
      (footprint "eagle-import:LED5MM")
      (libsource (lib "eagle-import") (part "LED5MM"))
    )
    (comp (ref "LED928")
      (value "LED5MM")
      (footprint "eagle-import:LED5MM")
      (libsource (lib "eagle-import") (part "LED5MM"))
    )
    (comp (ref "LED929")
      (value "LED5MM")
      (footprint "eagle-import:LED5MM")
      (libsource (lib "eagle-import") (part "LED5MM"))
    )
    (comp (ref "LED930")
      (value "LED5MM")
      (footprint "eagle-import:LED5MM")
      (libsource (lib "eagle-import") (part "LED5MM"))
    )
    (comp (ref "LED931")
      (value "LED5MM")
      (footprint "eagle-import:LED5MM")
      (libsource (lib "eagle-import") (part "LED5MM"))
    )
    (comp (ref "LED932")
      (value "LED5MM")
      (footprint "eagle-import:LED5MM")
      (libsource (lib "eagle-import") (part "LED5MM"))
    )
    (comp (ref "LED933")
      (value "LED5MM")
      (footprint "eagle-import:LED5MM")
      (libsource (lib "eagle-import") (part "LED5MM"))
    )
    (comp (ref "LED934")
      (value "LED5MM")
      (footprint "eagle-import:LED5MM")
      (libsource (lib "eagle-import") (part "LED5MM"))
    )
    (comp (ref "LED935")
      (value "LED5MM")
      (footprint "eagle-import:LED5MM")
      (libsource (lib "eagle-import") (part "LED5MM"))
    )
    (comp (ref "LED936")
      (value "LED5MM")
      (footprint "eagle-import:LED5MM")
      (libsource (lib "eagle-import") (part "LED5MM"))
    )
    (comp (ref "LED937")
      (value "LED5MM")
      (footprint "eagle-import:LED5MM")
      (libsource (lib "eagle-import") (part "LED5MM"))
    )
    (comp (ref "LED938")
      (value "LED5MM")
      (footprint "eagle-import:LED5MM")
      (libsource (lib "eagle-import") (part "LED5MM"))
    )
    (comp (ref "LED939")
      (value "LED5MM")
      (footprint "eagle-import:LED5MM")
      (libsource (lib "eagle-import") (part "LED5MM"))
    )
    (comp (ref "LED940")
      (value "LED5MM")
      (footprint "eagle-import:LED5MM")
      (libsource (lib "eagle-import") (part "LED5MM"))
    )
    (comp (ref "LED941")
      (value "LED5MM")
      (footprint "eagle-import:LED5MM")
      (libsource (lib "eagle-import") (part "LED5MM"))
    )
    (comp (ref "LED942")
      (value "LED5MM")
      (footprint "eagle-import:LED5MM")
      (libsource (lib "eagle-import") (part "LED5MM"))
    )
    (comp (ref "LED943")
      (value "LED5MM")
      (footprint "eagle-import:LED5MM")
      (libsource (lib "eagle-import") (part "LED5MM"))
    )
    (comp (ref "LED944")
      (value "LED5MM")
      (footprint "eagle-import:LED5MM")
      (libsource (lib "eagle-import") (part "LED5MM"))
    )
    (comp (ref "LED945")
      (value "LED5MM")
      (footprint "eagle-import:LED5MM")
      (libsource (lib "eagle-import") (part "LED5MM"))
    )
    (comp (ref "LED946")
      (value "LED5MM")
      (footprint "eagle-import:LED5MM")
      (libsource (lib "eagle-import") (part "LED5MM"))
    )
    (comp (ref "LED947")
      (value "LED5MM")
      (footprint "eagle-import:LED5MM")
      (libsource (lib "eagle-import") (part "LED5MM"))
    )
    (comp (ref "LED948")
      (value "LED5MM")
      (footprint "eagle-import:LED5MM")
      (libsource (lib "eagle-import") (part "LED5MM"))
    )
    (comp (ref "LED949")
      (value "LED5MM")
      (footprint "eagle-import:LED5MM")
      (libsource (lib "eagle-import") (part "LED5MM"))
    )
    (comp (ref "LED950")
      (value "LED5MM")
      (footprint "eagle-import:LED5MM")
      (libsource (lib "eagle-import") (part "LED5MM"))
    )
    (comp (ref "LED951")
      (value "LED5MM")
      (footprint "eagle-import:LED5MM")
      (libsource (lib "eagle-import") (part "LED5MM"))
    )
    (comp (ref "LED952")
      (value "LED5MM")
      (footprint "eagle-import:LED5MM")
      (libsource (lib "eagle-import") (part "LED5MM"))
    )
    (comp (ref "LED953")
      (value "LED5MM")
      (footprint "eagle-import:LED5MM")
      (libsource (lib "eagle-import") (part "LED5MM"))
    )
    (comp (ref "LED954")
      (value "LED5MM")
      (footprint "eagle-import:LED5MM")
      (libsource (lib "eagle-import") (part "LED5MM"))
    )
    (comp (ref "LED955")
      (value "LED5MM")
      (footprint "eagle-import:LED5MM")
      (libsource (lib "eagle-import") (part "LED5MM"))
    )
    (comp (ref "LED956")
      (value "LED5MM")
      (footprint "eagle-import:LED5MM")
      (libsource (lib "eagle-import") (part "LED5MM"))
    )
    (comp (ref "LED957")
      (value "LED5MM")
      (footprint "eagle-import:LED5MM")
      (libsource (lib "eagle-import") (part "LED5MM"))
    )
    (comp (ref "LED958")
      (value "LED5MM")
      (footprint "eagle-import:LED5MM")
      (libsource (lib "eagle-import") (part "LED5MM"))
    )
    (comp (ref "LED959")
      (value "LED5MM")
      (footprint "eagle-import:LED5MM")
      (libsource (lib "eagle-import") (part "LED5MM"))
    )
    (comp (ref "LED960")
      (value "LED5MM")
      (footprint "eagle-import:LED5MM")
      (libsource (lib "eagle-import") (part "LED5MM"))
    )
    (comp (ref "LED961")
      (value "LED5MM")
      (footprint "eagle-import:LED5MM")
      (libsource (lib "eagle-import") (part "LED5MM"))
    )
    (comp (ref "LED962")
      (value "LED5MM")
      (footprint "eagle-import:LED5MM")
      (libsource (lib "eagle-import") (part "LED5MM"))
    )
    (comp (ref "LED963")
      (value "LED5MM")
      (footprint "eagle-import:LED5MM")
      (libsource (lib "eagle-import") (part "LED5MM"))
    )
    (comp (ref "LED964")
      (value "LED5MM")
      (footprint "eagle-import:LED5MM")
      (libsource (lib "eagle-import") (part "LED5MM"))
    )
    (comp (ref "LED965")
      (value "LED5MM")
      (footprint "eagle-import:LED5MM")
      (libsource (lib "eagle-import") (part "LED5MM"))
    )
    (comp (ref "LED966")
      (value "LED5MM")
      (footprint "eagle-import:LED5MM")
      (libsource (lib "eagle-import") (part "LED5MM"))
    )
    (comp (ref "LED967")
      (value "LED5MM")
      (footprint "eagle-import:LED5MM")
      (libsource (lib "eagle-import") (part "LED5MM"))
    )
    (comp (ref "LED968")
      (value "LED5MM")
      (footprint "eagle-import:LED5MM")
      (libsource (lib "eagle-import") (part "LED5MM"))
    )
    (comp (ref "LED969")
      (value "LED5MM")
      (footprint "eagle-import:LED5MM")
      (libsource (lib "eagle-import") (part "LED5MM"))
    )
    (comp (ref "LED970")
      (value "LED5MM")
      (footprint "eagle-import:LED5MM")
      (libsource (lib "eagle-import") (part "LED5MM"))
    )
    (comp (ref "LED971")
      (value "LED5MM")
      (footprint "eagle-import:LED5MM")
      (libsource (lib "eagle-import") (part "LED5MM"))
    )
    (comp (ref "LED972")
      (value "LED5MM")
      (footprint "eagle-import:LED5MM")
      (libsource (lib "eagle-import") (part "LED5MM"))
    )
    (comp (ref "LED973")
      (value "LED5MM")
      (footprint "eagle-import:LED5MM")
      (libsource (lib "eagle-import") (part "LED5MM"))
    )
    (comp (ref "LED974")
      (value "LED5MM")
      (footprint "eagle-import:LED5MM")
      (libsource (lib "eagle-import") (part "LED5MM"))
    )
    (comp (ref "LED975")
      (value "LED5MM")
      (footprint "eagle-import:LED5MM")
      (libsource (lib "eagle-import") (part "LED5MM"))
    )
    (comp (ref "LED976")
      (value "LED5MM")
      (footprint "eagle-import:LED5MM")
      (libsource (lib "eagle-import") (part "LED5MM"))
    )
    (comp (ref "LED977")
      (value "LED5MM")
      (footprint "eagle-import:LED5MM")
      (libsource (lib "eagle-import") (part "LED5MM"))
    )
    (comp (ref "LED978")
      (value "LED5MM")
      (footprint "eagle-import:LED5MM")
      (libsource (lib "eagle-import") (part "LED5MM"))
    )
    (comp (ref "LED979")
      (value "LED5MM")
      (footprint "eagle-import:LED5MM")
      (libsource (lib "eagle-import") (part "LED5MM"))
    )
    (comp (ref "LED980")
      (value "LED5MM")
      (footprint "eagle-import:LED5MM")
      (libsource (lib "eagle-import") (part "LED5MM"))
    )
    (comp (ref "LED981")
      (value "LED5MM")
      (footprint "eagle-import:LED5MM")
      (libsource (lib "eagle-import") (part "LED5MM"))
    )
    (comp (ref "LED982")
      (value "LED5MM")
      (footprint "eagle-import:LED5MM")
      (libsource (lib "eagle-import") (part "LED5MM"))
    )
    (comp (ref "LED983")
      (value "LED5MM")
      (footprint "eagle-import:LED5MM")
      (libsource (lib "eagle-import") (part "LED5MM"))
    )
    (comp (ref "LED984")
      (value "LED5MM")
      (footprint "eagle-import:LED5MM")
      (libsource (lib "eagle-import") (part "LED5MM"))
    )
    (comp (ref "LED985")
      (value "LED5MM")
      (footprint "eagle-import:LED5MM")
      (libsource (lib "eagle-import") (part "LED5MM"))
    )
    (comp (ref "LED986")
      (value "LED5MM")
      (footprint "eagle-import:LED5MM")
      (libsource (lib "eagle-import") (part "LED5MM"))
    )
    (comp (ref "LED987")
      (value "LED5MM")
      (footprint "eagle-import:LED5MM")
      (libsource (lib "eagle-import") (part "LED5MM"))
    )
    (comp (ref "LED988")
      (value "LED5MM")
      (footprint "eagle-import:LED5MM")
      (libsource (lib "eagle-import") (part "LED5MM"))
    )
    (comp (ref "LED989")
      (value "LED5MM")
      (footprint "eagle-import:LED5MM")
      (libsource (lib "eagle-import") (part "LED5MM"))
    )
    (comp (ref "LED990")
      (value "LED5MM")
      (footprint "eagle-import:LED5MM")
      (libsource (lib "eagle-import") (part "LED5MM"))
    )
    (comp (ref "LED991")
      (value "LED5MM")
      (footprint "eagle-import:LED5MM")
      (libsource (lib "eagle-import") (part "LED5MM"))
    )
    (comp (ref "LED992")
      (value "LED5MM")
      (footprint "eagle-import:LED5MM")
      (libsource (lib "eagle-import") (part "LED5MM"))
    )
    (comp (ref "LED993")
      (value "LED5MM")
      (footprint "eagle-import:LED5MM")
      (libsource (lib "eagle-import") (part "LED5MM"))
    )
    (comp (ref "LED994")
      (value "LED5MM")
      (footprint "eagle-import:LED5MM")
      (libsource (lib "eagle-import") (part "LED5MM"))
    )
    (comp (ref "LED995")
      (value "LED5MM")
      (footprint "eagle-import:LED5MM")
      (libsource (lib "eagle-import") (part "LED5MM"))
    )
    (comp (ref "LED996")
      (value "LED5MM")
      (footprint "eagle-import:LED5MM")
      (libsource (lib "eagle-import") (part "LED5MM"))
    )
    (comp (ref "LED997")
      (value "LED5MM")
      (footprint "eagle-import:LED5MM")
      (libsource (lib "eagle-import") (part "LED5MM"))
    )
    (comp (ref "LED998")
      (value "LED5MM")
      (footprint "eagle-import:LED5MM")
      (libsource (lib "eagle-import") (part "LED5MM"))
    )
    (comp (ref "LED999")
      (value "LED5MM")
      (footprint "eagle-import:LED5MM")
      (libsource (lib "eagle-import") (part "LED5MM"))
    )
    (comp (ref "LED1000")
      (value "LED5MM")
      (footprint "eagle-import:LED5MM")
      (libsource (lib "eagle-import") (part "LED5MM"))
    )
    (comp (ref "LED1001")
      (value "LED5MM")
      (footprint "eagle-import:LED5MM")
      (libsource (lib "eagle-import") (part "LED5MM"))
    )
    (comp (ref "LED1002")
      (value "LED5MM")
      (footprint "eagle-import:LED5MM")
      (libsource (lib "eagle-import") (part "LED5MM"))
    )
    (comp (ref "LED1003")
      (value "LED5MM")
      (footprint "eagle-import:LED5MM")
      (libsource (lib "eagle-import") (part "LED5MM"))
    )
    (comp (ref "LED1004")
      (value "LED5MM")
      (footprint "eagle-import:LED5MM")
      (libsource (lib "eagle-import") (part "LED5MM"))
    )
    (comp (ref "LED1005")
      (value "LED5MM")
      (footprint "eagle-import:LED5MM")
      (libsource (lib "eagle-import") (part "LED5MM"))
    )
    (comp (ref "LED1006")
      (value "LED5MM")
      (footprint "eagle-import:LED5MM")
      (libsource (lib "eagle-import") (part "LED5MM"))
    )
    (comp (ref "LED1007")
      (value "LED5MM")
      (footprint "eagle-import:LED5MM")
      (libsource (lib "eagle-import") (part "LED5MM"))
    )
    (comp (ref "LED1008")
      (value "LED5MM")
      (footprint "eagle-import:LED5MM")
      (libsource (lib "eagle-import") (part "LED5MM"))
    )
    (comp (ref "LED1009")
      (value "LED5MM")
      (footprint "eagle-import:LED5MM")
      (libsource (lib "eagle-import") (part "LED5MM"))
    )
    (comp (ref "LED1010")
      (value "LED5MM")
      (footprint "eagle-import:LED5MM")
      (libsource (lib "eagle-import") (part "LED5MM"))
    )
    (comp (ref "LED1011")
      (value "LED5MM")
      (footprint "eagle-import:LED5MM")
      (libsource (lib "eagle-import") (part "LED5MM"))
    )
    (comp (ref "LED1012")
      (value "LED5MM")
      (footprint "eagle-import:LED5MM")
      (libsource (lib "eagle-import") (part "LED5MM"))
    )
    (comp (ref "LED1013")
      (value "LED5MM")
      (footprint "eagle-import:LED5MM")
      (libsource (lib "eagle-import") (part "LED5MM"))
    )
    (comp (ref "LED1014")
      (value "LED5MM")
      (footprint "eagle-import:LED5MM")
      (libsource (lib "eagle-import") (part "LED5MM"))
    )
    (comp (ref "LED1015")
      (value "LED5MM")
      (footprint "eagle-import:LED5MM")
      (libsource (lib "eagle-import") (part "LED5MM"))
    )
    (comp (ref "LED1016")
      (value "LED5MM")
      (footprint "eagle-import:LED5MM")
      (libsource (lib "eagle-import") (part "LED5MM"))
    )
    (comp (ref "LED1017")
      (value "LED5MM")
      (footprint "eagle-import:LED5MM")
      (libsource (lib "eagle-import") (part "LED5MM"))
    )
    (comp (ref "LED1018")
      (value "LED5MM")
      (footprint "eagle-import:LED5MM")
      (libsource (lib "eagle-import") (part "LED5MM"))
    )
    (comp (ref "LED1019")
      (value "LED5MM")
      (footprint "eagle-import:LED5MM")
      (libsource (lib "eagle-import") (part "LED5MM"))
    )
    (comp (ref "LED1020")
      (value "LED5MM")
      (footprint "eagle-import:LED5MM")
      (libsource (lib "eagle-import") (part "LED5MM"))
    )
    (comp (ref "LED1021")
      (value "LED5MM")
      (footprint "eagle-import:LED5MM")
      (libsource (lib "eagle-import") (part "LED5MM"))
    )
    (comp (ref "LED1022")
      (value "LED5MM")
      (footprint "eagle-import:LED5MM")
      (libsource (lib "eagle-import") (part "LED5MM"))
    )
    (comp (ref "LED1023")
      (value "LED5MM")
      (footprint "eagle-import:LED5MM")
      (libsource (lib "eagle-import") (part "LED5MM"))
    )
    (comp (ref "LED1024")
      (value "LED5MM")
      (footprint "eagle-import:LED5MM")
      (libsource (lib "eagle-import") (part "LED5MM"))
    )
    (comp (ref "LED1025")
      (value "LED5MM")
      (footprint "eagle-import:LED5MM")
      (libsource (lib "eagle-import") (part "LED5MM"))
    )
    (comp (ref "LED1026")
      (value "LED5MM")
      (footprint "eagle-import:LED5MM")
      (libsource (lib "eagle-import") (part "LED5MM"))
    )
    (comp (ref "LED1027")
      (value "LED5MM")
      (footprint "eagle-import:LED5MM")
      (libsource (lib "eagle-import") (part "LED5MM"))
    )
    (comp (ref "LED1028")
      (value "LED5MM")
      (footprint "eagle-import:LED5MM")
      (libsource (lib "eagle-import") (part "LED5MM"))
    )
    (comp (ref "LED1029")
      (value "LED5MM")
      (footprint "eagle-import:LED5MM")
      (libsource (lib "eagle-import") (part "LED5MM"))
    )
    (comp (ref "LED1030")
      (value "LED5MM")
      (footprint "eagle-import:LED5MM")
      (libsource (lib "eagle-import") (part "LED5MM"))
    )
    (comp (ref "LED1031")
      (value "LED5MM")
      (footprint "eagle-import:LED5MM")
      (libsource (lib "eagle-import") (part "LED5MM"))
    )
    (comp (ref "LED1032")
      (value "LED5MM")
      (footprint "eagle-import:LED5MM")
      (libsource (lib "eagle-import") (part "LED5MM"))
    )
    (comp (ref "LED1033")
      (value "LED5MM")
      (footprint "eagle-import:LED5MM")
      (libsource (lib "eagle-import") (part "LED5MM"))
    )
    (comp (ref "LED1034")
      (value "LED5MM")
      (footprint "eagle-import:LED5MM")
      (libsource (lib "eagle-import") (part "LED5MM"))
    )
    (comp (ref "LED1035")
      (value "LED5MM")
      (footprint "eagle-import:LED5MM")
      (libsource (lib "eagle-import") (part "LED5MM"))
    )
    (comp (ref "LED1036")
      (value "LED5MM")
      (footprint "eagle-import:LED5MM")
      (libsource (lib "eagle-import") (part "LED5MM"))
    )
    (comp (ref "LED1037")
      (value "LED5MM")
      (footprint "eagle-import:LED5MM")
      (libsource (lib "eagle-import") (part "LED5MM"))
    )
    (comp (ref "LED1038")
      (value "LED5MM")
      (footprint "eagle-import:LED5MM")
      (libsource (lib "eagle-import") (part "LED5MM"))
    )
    (comp (ref "LED1039")
      (value "LED5MM")
      (footprint "eagle-import:LED5MM")
      (libsource (lib "eagle-import") (part "LED5MM"))
    )
    (comp (ref "LED1040")
      (value "LED5MM")
      (footprint "eagle-import:LED5MM")
      (libsource (lib "eagle-import") (part "LED5MM"))
    )
    (comp (ref "LED1041")
      (value "LED5MM")
      (footprint "eagle-import:LED5MM")
      (libsource (lib "eagle-import") (part "LED5MM"))
    )
    (comp (ref "LED1042")
      (value "LED5MM")
      (footprint "eagle-import:LED5MM")
      (libsource (lib "eagle-import") (part "LED5MM"))
    )
    (comp (ref "LED1043")
      (value "LED5MM")
      (footprint "eagle-import:LED5MM")
      (libsource (lib "eagle-import") (part "LED5MM"))
    )
    (comp (ref "LED1044")
      (value "LED5MM")
      (footprint "eagle-import:LED5MM")
      (libsource (lib "eagle-import") (part "LED5MM"))
    )
    (comp (ref "LED1045")
      (value "LED5MM")
      (footprint "eagle-import:LED5MM")
      (libsource (lib "eagle-import") (part "LED5MM"))
    )
    (comp (ref "LED1046")
      (value "LED5MM")
      (footprint "eagle-import:LED5MM")
      (libsource (lib "eagle-import") (part "LED5MM"))
    )
    (comp (ref "LED1047")
      (value "LED5MM")
      (footprint "eagle-import:LED5MM")
      (libsource (lib "eagle-import") (part "LED5MM"))
    )
    (comp (ref "LED1048")
      (value "LED5MM")
      (footprint "eagle-import:LED5MM")
      (libsource (lib "eagle-import") (part "LED5MM"))
    )
    (comp (ref "LED1049")
      (value "LED5MM")
      (footprint "eagle-import:LED5MM")
      (libsource (lib "eagle-import") (part "LED5MM"))
    )
    (comp (ref "LED1050")
      (value "LED5MM")
      (footprint "eagle-import:LED5MM")
      (libsource (lib "eagle-import") (part "LED5MM"))
    )
    (comp (ref "LED1051")
      (value "LED5MM")
      (footprint "eagle-import:LED5MM")
      (libsource (lib "eagle-import") (part "LED5MM"))
    )
    (comp (ref "LED1052")
      (value "LED5MM")
      (footprint "eagle-import:LED5MM")
      (libsource (lib "eagle-import") (part "LED5MM"))
    )
    (comp (ref "LED1053")
      (value "LED5MM")
      (footprint "eagle-import:LED5MM")
      (libsource (lib "eagle-import") (part "LED5MM"))
    )
    (comp (ref "LED1054")
      (value "LED5MM")
      (footprint "eagle-import:LED5MM")
      (libsource (lib "eagle-import") (part "LED5MM"))
    )
    (comp (ref "LED1055")
      (value "LED5MM")
      (footprint "eagle-import:LED5MM")
      (libsource (lib "eagle-import") (part "LED5MM"))
    )
    (comp (ref "LED1056")
      (value "LED5MM")
      (footprint "eagle-import:LED5MM")
      (libsource (lib "eagle-import") (part "LED5MM"))
    )
    (comp (ref "LED1057")
      (value "LED5MM")
      (footprint "eagle-import:LED5MM")
      (libsource (lib "eagle-import") (part "LED5MM"))
    )
    (comp (ref "LED1058")
      (value "LED5MM")
      (footprint "eagle-import:LED5MM")
      (libsource (lib "eagle-import") (part "LED5MM"))
    )
    (comp (ref "LED1059")
      (value "LED5MM")
      (footprint "eagle-import:LED5MM")
      (libsource (lib "eagle-import") (part "LED5MM"))
    )
    (comp (ref "LED1060")
      (value "LED5MM")
      (footprint "eagle-import:LED5MM")
      (libsource (lib "eagle-import") (part "LED5MM"))
    )
    (comp (ref "LED1061")
      (value "LED5MM")
      (footprint "eagle-import:LED5MM")
      (libsource (lib "eagle-import") (part "LED5MM"))
    )
    (comp (ref "LED1062")
      (value "LED5MM")
      (footprint "eagle-import:LED5MM")
      (libsource (lib "eagle-import") (part "LED5MM"))
    )
    (comp (ref "LED1063")
      (value "LED5MM")
      (footprint "eagle-import:LED5MM")
      (libsource (lib "eagle-import") (part "LED5MM"))
    )
    (comp (ref "LED1064")
      (value "LED5MM")
      (footprint "eagle-import:LED5MM")
      (libsource (lib "eagle-import") (part "LED5MM"))
    )
    (comp (ref "LED1065")
      (value "LED5MM")
      (footprint "eagle-import:LED5MM")
      (libsource (lib "eagle-import") (part "LED5MM"))
    )
    (comp (ref "LED1066")
      (value "LED5MM")
      (footprint "eagle-import:LED5MM")
      (libsource (lib "eagle-import") (part "LED5MM"))
    )
    (comp (ref "LED1067")
      (value "LED5MM")
      (footprint "eagle-import:LED5MM")
      (libsource (lib "eagle-import") (part "LED5MM"))
    )
    (comp (ref "LED1068")
      (value "LED5MM")
      (footprint "eagle-import:LED5MM")
      (libsource (lib "eagle-import") (part "LED5MM"))
    )
    (comp (ref "LED1069")
      (value "LED5MM")
      (footprint "eagle-import:LED5MM")
      (libsource (lib "eagle-import") (part "LED5MM"))
    )
    (comp (ref "LED1070")
      (value "LED5MM")
      (footprint "eagle-import:LED5MM")
      (libsource (lib "eagle-import") (part "LED5MM"))
    )
    (comp (ref "LED1071")
      (value "LED5MM")
      (footprint "eagle-import:LED5MM")
      (libsource (lib "eagle-import") (part "LED5MM"))
    )
    (comp (ref "LED1072")
      (value "LED5MM")
      (footprint "eagle-import:LED5MM")
      (libsource (lib "eagle-import") (part "LED5MM"))
    )
    (comp (ref "LED1073")
      (value "LED5MM")
      (footprint "eagle-import:LED5MM")
      (libsource (lib "eagle-import") (part "LED5MM"))
    )
    (comp (ref "LED1074")
      (value "LED5MM")
      (footprint "eagle-import:LED5MM")
      (libsource (lib "eagle-import") (part "LED5MM"))
    )
    (comp (ref "LED1075")
      (value "LED5MM")
      (footprint "eagle-import:LED5MM")
      (libsource (lib "eagle-import") (part "LED5MM"))
    )
    (comp (ref "LED1076")
      (value "LED5MM")
      (footprint "eagle-import:LED5MM")
      (libsource (lib "eagle-import") (part "LED5MM"))
    )
    (comp (ref "LED1077")
      (value "LED5MM")
      (footprint "eagle-import:LED5MM")
      (libsource (lib "eagle-import") (part "LED5MM"))
    )
    (comp (ref "LED1078")
      (value "LED5MM")
      (footprint "eagle-import:LED5MM")
      (libsource (lib "eagle-import") (part "LED5MM"))
    )
    (comp (ref "LED1079")
      (value "LED5MM")
      (footprint "eagle-import:LED5MM")
      (libsource (lib "eagle-import") (part "LED5MM"))
    )
    (comp (ref "LED1080")
      (value "LED5MM")
      (footprint "eagle-import:LED5MM")
      (libsource (lib "eagle-import") (part "LED5MM"))
    )
    (comp (ref "LED1081")
      (value "LED5MM")
      (footprint "eagle-import:LED5MM")
      (libsource (lib "eagle-import") (part "LED5MM"))
    )
    (comp (ref "LED1082")
      (value "LED5MM")
      (footprint "eagle-import:LED5MM")
      (libsource (lib "eagle-import") (part "LED5MM"))
    )
    (comp (ref "LED1083")
      (value "LED5MM")
      (footprint "eagle-import:LED5MM")
      (libsource (lib "eagle-import") (part "LED5MM"))
    )
    (comp (ref "LED1084")
      (value "LED5MM")
      (footprint "eagle-import:LED5MM")
      (libsource (lib "eagle-import") (part "LED5MM"))
    )
    (comp (ref "LED1085")
      (value "LED5MM")
      (footprint "eagle-import:LED5MM")
      (libsource (lib "eagle-import") (part "LED5MM"))
    )
    (comp (ref "LED1086")
      (value "LED5MM")
      (footprint "eagle-import:LED5MM")
      (libsource (lib "eagle-import") (part "LED5MM"))
    )
    (comp (ref "LED1087")
      (value "LED5MM")
      (footprint "eagle-import:LED5MM")
      (libsource (lib "eagle-import") (part "LED5MM"))
    )
    (comp (ref "LED1088")
      (value "LED5MM")
      (footprint "eagle-import:LED5MM")
      (libsource (lib "eagle-import") (part "LED5MM"))
    )
    (comp (ref "LED1089")
      (value "LED5MM")
      (footprint "eagle-import:LED5MM")
      (libsource (lib "eagle-import") (part "LED5MM"))
    )
    (comp (ref "LED1090")
      (value "LED5MM")
      (footprint "eagle-import:LED5MM")
      (libsource (lib "eagle-import") (part "LED5MM"))
    )
    (comp (ref "LED1091")
      (value "LED5MM")
      (footprint "eagle-import:LED5MM")
      (libsource (lib "eagle-import") (part "LED5MM"))
    )
    (comp (ref "LED1092")
      (value "LED5MM")
      (footprint "eagle-import:LED5MM")
      (libsource (lib "eagle-import") (part "LED5MM"))
    )
    (comp (ref "LED1093")
      (value "LED5MM")
      (footprint "eagle-import:LED5MM")
      (libsource (lib "eagle-import") (part "LED5MM"))
    )
    (comp (ref "LED1094")
      (value "LED5MM")
      (footprint "eagle-import:LED5MM")
      (libsource (lib "eagle-import") (part "LED5MM"))
    )
    (comp (ref "LED1095")
      (value "LED5MM")
      (footprint "eagle-import:LED5MM")
      (libsource (lib "eagle-import") (part "LED5MM"))
    )
    (comp (ref "LED1096")
      (value "LED5MM")
      (footprint "eagle-import:LED5MM")
      (libsource (lib "eagle-import") (part "LED5MM"))
    )
    (comp (ref "LED1097")
      (value "LED5MM")
      (footprint "eagle-import:LED5MM")
      (libsource (lib "eagle-import") (part "LED5MM"))
    )
    (comp (ref "LED1098")
      (value "LED5MM")
      (footprint "eagle-import:LED5MM")
      (libsource (lib "eagle-import") (part "LED5MM"))
    )
    (comp (ref "LED1099")
      (value "LED5MM")
      (footprint "eagle-import:LED5MM")
      (libsource (lib "eagle-import") (part "LED5MM"))
    )
    (comp (ref "LED1100")
      (value "LED5MM")
      (footprint "eagle-import:LED5MM")
      (libsource (lib "eagle-import") (part "LED5MM"))
    )
    (comp (ref "LED1101")
      (value "LED5MM")
      (footprint "eagle-import:LED5MM")
      (libsource (lib "eagle-import") (part "LED5MM"))
    )
    (comp (ref "LED1102")
      (value "LED5MM")
      (footprint "eagle-import:LED5MM")
      (libsource (lib "eagle-import") (part "LED5MM"))
    )
    (comp (ref "LED1103")
      (value "LED5MM")
      (footprint "eagle-import:LED5MM")
      (libsource (lib "eagle-import") (part "LED5MM"))
    )
    (comp (ref "LED1104")
      (value "LED5MM")
      (footprint "eagle-import:LED5MM")
      (libsource (lib "eagle-import") (part "LED5MM"))
    )
    (comp (ref "LED1105")
      (value "LED5MM")
      (footprint "eagle-import:LED5MM")
      (libsource (lib "eagle-import") (part "LED5MM"))
    )
    (comp (ref "LED1106")
      (value "LED5MM")
      (footprint "eagle-import:LED5MM")
      (libsource (lib "eagle-import") (part "LED5MM"))
    )
    (comp (ref "LED1107")
      (value "LED5MM")
      (footprint "eagle-import:LED5MM")
      (libsource (lib "eagle-import") (part "LED5MM"))
    )
    (comp (ref "LED1108")
      (value "LED5MM")
      (footprint "eagle-import:LED5MM")
      (libsource (lib "eagle-import") (part "LED5MM"))
    )
    (comp (ref "LED1109")
      (value "LED5MM")
      (footprint "eagle-import:LED5MM")
      (libsource (lib "eagle-import") (part "LED5MM"))
    )
    (comp (ref "LED1110")
      (value "LED5MM")
      (footprint "eagle-import:LED5MM")
      (libsource (lib "eagle-import") (part "LED5MM"))
    )
    (comp (ref "LED1111")
      (value "LED5MM")
      (footprint "eagle-import:LED5MM")
      (libsource (lib "eagle-import") (part "LED5MM"))
    )
    (comp (ref "LED1112")
      (value "LED5MM")
      (footprint "eagle-import:LED5MM")
      (libsource (lib "eagle-import") (part "LED5MM"))
    )
    (comp (ref "LED1113")
      (value "LED5MM")
      (footprint "eagle-import:LED5MM")
      (libsource (lib "eagle-import") (part "LED5MM"))
    )
    (comp (ref "LED1114")
      (value "LED5MM")
      (footprint "eagle-import:LED5MM")
      (libsource (lib "eagle-import") (part "LED5MM"))
    )
    (comp (ref "LED1115")
      (value "LED5MM")
      (footprint "eagle-import:LED5MM")
      (libsource (lib "eagle-import") (part "LED5MM"))
    )
    (comp (ref "LED1116")
      (value "LED5MM")
      (footprint "eagle-import:LED5MM")
      (libsource (lib "eagle-import") (part "LED5MM"))
    )
    (comp (ref "LED1117")
      (value "LED5MM")
      (footprint "eagle-import:LED5MM")
      (libsource (lib "eagle-import") (part "LED5MM"))
    )
    (comp (ref "LED1118")
      (value "LED5MM")
      (footprint "eagle-import:LED5MM")
      (libsource (lib "eagle-import") (part "LED5MM"))
    )
    (comp (ref "LED1119")
      (value "LED5MM")
      (footprint "eagle-import:LED5MM")
      (libsource (lib "eagle-import") (part "LED5MM"))
    )
    (comp (ref "LED1120")
      (value "LED5MM")
      (footprint "eagle-import:LED5MM")
      (libsource (lib "eagle-import") (part "LED5MM"))
    )
    (comp (ref "LED1121")
      (value "LED5MM")
      (footprint "eagle-import:LED5MM")
      (libsource (lib "eagle-import") (part "LED5MM"))
    )
    (comp (ref "LED1122")
      (value "LED5MM")
      (footprint "eagle-import:LED5MM")
      (libsource (lib "eagle-import") (part "LED5MM"))
    )
    (comp (ref "LED1123")
      (value "LED5MM")
      (footprint "eagle-import:LED5MM")
      (libsource (lib "eagle-import") (part "LED5MM"))
    )
    (comp (ref "LED1124")
      (value "LED5MM")
      (footprint "eagle-import:LED5MM")
      (libsource (lib "eagle-import") (part "LED5MM"))
    )
    (comp (ref "LED1125")
      (value "LED5MM")
      (footprint "eagle-import:LED5MM")
      (libsource (lib "eagle-import") (part "LED5MM"))
    )
    (comp (ref "LED1126")
      (value "LED5MM")
      (footprint "eagle-import:LED5MM")
      (libsource (lib "eagle-import") (part "LED5MM"))
    )
    (comp (ref "LED1127")
      (value "LED5MM")
      (footprint "eagle-import:LED5MM")
      (libsource (lib "eagle-import") (part "LED5MM"))
    )
    (comp (ref "LED1128")
      (value "LED5MM")
      (footprint "eagle-import:LED5MM")
      (libsource (lib "eagle-import") (part "LED5MM"))
    )
    (comp (ref "LED1129")
      (value "LED5MM")
      (footprint "eagle-import:LED5MM")
      (libsource (lib "eagle-import") (part "LED5MM"))
    )
    (comp (ref "LED1130")
      (value "LED5MM")
      (footprint "eagle-import:LED5MM")
      (libsource (lib "eagle-import") (part "LED5MM"))
    )
    (comp (ref "LED1131")
      (value "LED5MM")
      (footprint "eagle-import:LED5MM")
      (libsource (lib "eagle-import") (part "LED5MM"))
    )
    (comp (ref "LED1132")
      (value "LED5MM")
      (footprint "eagle-import:LED5MM")
      (libsource (lib "eagle-import") (part "LED5MM"))
    )
    (comp (ref "LED1133")
      (value "LED5MM")
      (footprint "eagle-import:LED5MM")
      (libsource (lib "eagle-import") (part "LED5MM"))
    )
    (comp (ref "LED1134")
      (value "LED5MM")
      (footprint "eagle-import:LED5MM")
      (libsource (lib "eagle-import") (part "LED5MM"))
    )
    (comp (ref "LED1135")
      (value "LED5MM")
      (footprint "eagle-import:LED5MM")
      (libsource (lib "eagle-import") (part "LED5MM"))
    )
    (comp (ref "LED1136")
      (value "LED5MM")
      (footprint "eagle-import:LED5MM")
      (libsource (lib "eagle-import") (part "LED5MM"))
    )
    (comp (ref "LED1137")
      (value "LED5MM")
      (footprint "eagle-import:LED5MM")
      (libsource (lib "eagle-import") (part "LED5MM"))
    )
    (comp (ref "LED1138")
      (value "LED5MM")
      (footprint "eagle-import:LED5MM")
      (libsource (lib "eagle-import") (part "LED5MM"))
    )
    (comp (ref "LED1139")
      (value "LED5MM")
      (footprint "eagle-import:LED5MM")
      (libsource (lib "eagle-import") (part "LED5MM"))
    )
    (comp (ref "LED1140")
      (value "LED5MM")
      (footprint "eagle-import:LED5MM")
      (libsource (lib "eagle-import") (part "LED5MM"))
    )
    (comp (ref "LED1141")
      (value "LED5MM")
      (footprint "eagle-import:LED5MM")
      (libsource (lib "eagle-import") (part "LED5MM"))
    )
    (comp (ref "LED1142")
      (value "LED5MM")
      (footprint "eagle-import:LED5MM")
      (libsource (lib "eagle-import") (part "LED5MM"))
    )
    (comp (ref "LED1143")
      (value "LED5MM")
      (footprint "eagle-import:LED5MM")
      (libsource (lib "eagle-import") (part "LED5MM"))
    )
    (comp (ref "LED1144")
      (value "LED5MM")
      (footprint "eagle-import:LED5MM")
      (libsource (lib "eagle-import") (part "LED5MM"))
    )
    (comp (ref "LED1145")
      (value "LED5MM")
      (footprint "eagle-import:LED5MM")
      (libsource (lib "eagle-import") (part "LED5MM"))
    )
    (comp (ref "LED1146")
      (value "LED5MM")
      (footprint "eagle-import:LED5MM")
      (libsource (lib "eagle-import") (part "LED5MM"))
    )
    (comp (ref "LED1147")
      (value "LED5MM")
      (footprint "eagle-import:LED5MM")
      (libsource (lib "eagle-import") (part "LED5MM"))
    )
    (comp (ref "LED1148")
      (value "LED5MM")
      (footprint "eagle-import:LED5MM")
      (libsource (lib "eagle-import") (part "LED5MM"))
    )
    (comp (ref "LED1149")
      (value "LED5MM")
      (footprint "eagle-import:LED5MM")
      (libsource (lib "eagle-import") (part "LED5MM"))
    )
    (comp (ref "LED1150")
      (value "LED5MM")
      (footprint "eagle-import:LED5MM")
      (libsource (lib "eagle-import") (part "LED5MM"))
    )
    (comp (ref "LED1151")
      (value "LED5MM")
      (footprint "eagle-import:LED5MM")
      (libsource (lib "eagle-import") (part "LED5MM"))
    )
    (comp (ref "LED1152")
      (value "LED5MM")
      (footprint "eagle-import:LED5MM")
      (libsource (lib "eagle-import") (part "LED5MM"))
    )
    (comp (ref "LED1153")
      (value "LED5MM")
      (footprint "eagle-import:LED5MM")
      (libsource (lib "eagle-import") (part "LED5MM"))
    )
    (comp (ref "LED1154")
      (value "LED5MM")
      (footprint "eagle-import:LED5MM")
      (libsource (lib "eagle-import") (part "LED5MM"))
    )
    (comp (ref "LED1155")
      (value "LED5MM")
      (footprint "eagle-import:LED5MM")
      (libsource (lib "eagle-import") (part "LED5MM"))
    )
    (comp (ref "LED1156")
      (value "LED5MM")
      (footprint "eagle-import:LED5MM")
      (libsource (lib "eagle-import") (part "LED5MM"))
    )
    (comp (ref "LED1157")
      (value "LED5MM")
      (footprint "eagle-import:LED5MM")
      (libsource (lib "eagle-import") (part "LED5MM"))
    )
    (comp (ref "LED1158")
      (value "LED5MM")
      (footprint "eagle-import:LED5MM")
      (libsource (lib "eagle-import") (part "LED5MM"))
    )
    (comp (ref "LED1159")
      (value "LED5MM")
      (footprint "eagle-import:LED5MM")
      (libsource (lib "eagle-import") (part "LED5MM"))
    )
    (comp (ref "LED1160")
      (value "LED5MM")
      (footprint "eagle-import:LED5MM")
      (libsource (lib "eagle-import") (part "LED5MM"))
    )
    (comp (ref "LED1161")
      (value "LED5MM")
      (footprint "eagle-import:LED5MM")
      (libsource (lib "eagle-import") (part "LED5MM"))
    )
    (comp (ref "LED1162")
      (value "LED5MM")
      (footprint "eagle-import:LED5MM")
      (libsource (lib "eagle-import") (part "LED5MM"))
    )
    (comp (ref "LED1163")
      (value "LED5MM")
      (footprint "eagle-import:LED5MM")
      (libsource (lib "eagle-import") (part "LED5MM"))
    )
    (comp (ref "LED1164")
      (value "LED5MM")
      (footprint "eagle-import:LED5MM")
      (libsource (lib "eagle-import") (part "LED5MM"))
    )
    (comp (ref "LED1165")
      (value "LED5MM")
      (footprint "eagle-import:LED5MM")
      (libsource (lib "eagle-import") (part "LED5MM"))
    )
    (comp (ref "LED1166")
      (value "LED5MM")
      (footprint "eagle-import:LED5MM")
      (libsource (lib "eagle-import") (part "LED5MM"))
    )
    (comp (ref "LED1167")
      (value "LED5MM")
      (footprint "eagle-import:LED5MM")
      (libsource (lib "eagle-import") (part "LED5MM"))
    )
    (comp (ref "LED1168")
      (value "LED5MM")
      (footprint "eagle-import:LED5MM")
      (libsource (lib "eagle-import") (part "LED5MM"))
    )
    (comp (ref "LED1169")
      (value "LED5MM")
      (footprint "eagle-import:LED5MM")
      (libsource (lib "eagle-import") (part "LED5MM"))
    )
    (comp (ref "LED1170")
      (value "LED5MM")
      (footprint "eagle-import:LED5MM")
      (libsource (lib "eagle-import") (part "LED5MM"))
    )
    (comp (ref "LED1171")
      (value "LED5MM")
      (footprint "eagle-import:LED5MM")
      (libsource (lib "eagle-import") (part "LED5MM"))
    )
    (comp (ref "LED1172")
      (value "LED5MM")
      (footprint "eagle-import:LED5MM")
      (libsource (lib "eagle-import") (part "LED5MM"))
    )
    (comp (ref "LED1173")
      (value "LED5MM")
      (footprint "eagle-import:LED5MM")
      (libsource (lib "eagle-import") (part "LED5MM"))
    )
    (comp (ref "LED1174")
      (value "LED5MM")
      (footprint "eagle-import:LED5MM")
      (libsource (lib "eagle-import") (part "LED5MM"))
    )
    (comp (ref "LED1175")
      (value "LED5MM")
      (footprint "eagle-import:LED5MM")
      (libsource (lib "eagle-import") (part "LED5MM"))
    )
    (comp (ref "LED1176")
      (value "LED5MM")
      (footprint "eagle-import:LED5MM")
      (libsource (lib "eagle-import") (part "LED5MM"))
    )
    (comp (ref "LED1177")
      (value "LED5MM")
      (footprint "eagle-import:LED5MM")
      (libsource (lib "eagle-import") (part "LED5MM"))
    )
    (comp (ref "LED1178")
      (value "LED5MM")
      (footprint "eagle-import:LED5MM")
      (libsource (lib "eagle-import") (part "LED5MM"))
    )
    (comp (ref "LED1179")
      (value "LED5MM")
      (footprint "eagle-import:LED5MM")
      (libsource (lib "eagle-import") (part "LED5MM"))
    )
    (comp (ref "LED1180")
      (value "LED5MM")
      (footprint "eagle-import:LED5MM")
      (libsource (lib "eagle-import") (part "LED5MM"))
    )
    (comp (ref "LED1181")
      (value "LED5MM")
      (footprint "eagle-import:LED5MM")
      (libsource (lib "eagle-import") (part "LED5MM"))
    )
    (comp (ref "LED1182")
      (value "LED5MM")
      (footprint "eagle-import:LED5MM")
      (libsource (lib "eagle-import") (part "LED5MM"))
    )
    (comp (ref "LED1183")
      (value "LED5MM")
      (footprint "eagle-import:LED5MM")
      (libsource (lib "eagle-import") (part "LED5MM"))
    )
    (comp (ref "LED1184")
      (value "LED5MM")
      (footprint "eagle-import:LED5MM")
      (libsource (lib "eagle-import") (part "LED5MM"))
    )
    (comp (ref "LED1185")
      (value "LED5MM")
      (footprint "eagle-import:LED5MM")
      (libsource (lib "eagle-import") (part "LED5MM"))
    )
    (comp (ref "LED1186")
      (value "LED5MM")
      (footprint "eagle-import:LED5MM")
      (libsource (lib "eagle-import") (part "LED5MM"))
    )
    (comp (ref "LED1187")
      (value "LED5MM")
      (footprint "eagle-import:LED5MM")
      (libsource (lib "eagle-import") (part "LED5MM"))
    )
    (comp (ref "LED1188")
      (value "LED5MM")
      (footprint "eagle-import:LED5MM")
      (libsource (lib "eagle-import") (part "LED5MM"))
    )
    (comp (ref "LED1189")
      (value "LED5MM")
      (footprint "eagle-import:LED5MM")
      (libsource (lib "eagle-import") (part "LED5MM"))
    )
    (comp (ref "LED1190")
      (value "LED5MM")
      (footprint "eagle-import:LED5MM")
      (libsource (lib "eagle-import") (part "LED5MM"))
    )
    (comp (ref "LED1191")
      (value "LED5MM")
      (footprint "eagle-import:LED5MM")
      (libsource (lib "eagle-import") (part "LED5MM"))
    )
    (comp (ref "LED1192")
      (value "LED5MM")
      (footprint "eagle-import:LED5MM")
      (libsource (lib "eagle-import") (part "LED5MM"))
    )
    (comp (ref "LED1193")
      (value "LED5MM")
      (footprint "eagle-import:LED5MM")
      (libsource (lib "eagle-import") (part "LED5MM"))
    )
    (comp (ref "LED1194")
      (value "LED5MM")
      (footprint "eagle-import:LED5MM")
      (libsource (lib "eagle-import") (part "LED5MM"))
    )
    (comp (ref "LED1195")
      (value "LED5MM")
      (footprint "eagle-import:LED5MM")
      (libsource (lib "eagle-import") (part "LED5MM"))
    )
    (comp (ref "LED1196")
      (value "LED5MM")
      (footprint "eagle-import:LED5MM")
      (libsource (lib "eagle-import") (part "LED5MM"))
    )
    (comp (ref "LED1197")
      (value "LED5MM")
      (footprint "eagle-import:LED5MM")
      (libsource (lib "eagle-import") (part "LED5MM"))
    )
    (comp (ref "LED1198")
      (value "LED5MM")
      (footprint "eagle-import:LED5MM")
      (libsource (lib "eagle-import") (part "LED5MM"))
    )
    (comp (ref "LED1199")
      (value "LED5MM")
      (footprint "eagle-import:LED5MM")
      (libsource (lib "eagle-import") (part "LED5MM"))
    )
    (comp (ref "LED1200")
      (value "LED5MM")
      (footprint "eagle-import:LED5MM")
      (libsource (lib "eagle-import") (part "LED5MM"))
    )
    (comp (ref "LED1201")
      (value "LED5MM")
      (footprint "eagle-import:LED5MM")
      (libsource (lib "eagle-import") (part "LED5MM"))
    )
    (comp (ref "LED1202")
      (value "LED5MM")
      (footprint "eagle-import:LED5MM")
      (libsource (lib "eagle-import") (part "LED5MM"))
    )
    (comp (ref "LED1203")
      (value "LED5MM")
      (footprint "eagle-import:LED5MM")
      (libsource (lib "eagle-import") (part "LED5MM"))
    )
    (comp (ref "LED1204")
      (value "LED5MM")
      (footprint "eagle-import:LED5MM")
      (libsource (lib "eagle-import") (part "LED5MM"))
    )
    (comp (ref "LED1205")
      (value "LED5MM")
      (footprint "eagle-import:LED5MM")
      (libsource (lib "eagle-import") (part "LED5MM"))
    )
    (comp (ref "LED1206")
      (value "LED5MM")
      (footprint "eagle-import:LED5MM")
      (libsource (lib "eagle-import") (part "LED5MM"))
    )
    (comp (ref "LED1207")
      (value "LED5MM")
      (footprint "eagle-import:LED5MM")
      (libsource (lib "eagle-import") (part "LED5MM"))
    )
    (comp (ref "LED1208")
      (value "LED5MM")
      (footprint "eagle-import:LED5MM")
      (libsource (lib "eagle-import") (part "LED5MM"))
    )
    (comp (ref "LED1209")
      (value "LED5MM")
      (footprint "eagle-import:LED5MM")
      (libsource (lib "eagle-import") (part "LED5MM"))
    )
    (comp (ref "LED1210")
      (value "LED5MM")
      (footprint "eagle-import:LED5MM")
      (libsource (lib "eagle-import") (part "LED5MM"))
    )
    (comp (ref "LED1211")
      (value "LED5MM")
      (footprint "eagle-import:LED5MM")
      (libsource (lib "eagle-import") (part "LED5MM"))
    )
    (comp (ref "LED1212")
      (value "LED5MM")
      (footprint "eagle-import:LED5MM")
      (libsource (lib "eagle-import") (part "LED5MM"))
    )
    (comp (ref "LED1213")
      (value "LED5MM")
      (footprint "eagle-import:LED5MM")
      (libsource (lib "eagle-import") (part "LED5MM"))
    )
    (comp (ref "LED1214")
      (value "LED5MM")
      (footprint "eagle-import:LED5MM")
      (libsource (lib "eagle-import") (part "LED5MM"))
    )
    (comp (ref "LED1215")
      (value "LED5MM")
      (footprint "eagle-import:LED5MM")
      (libsource (lib "eagle-import") (part "LED5MM"))
    )
    (comp (ref "LED1216")
      (value "LED5MM")
      (footprint "eagle-import:LED5MM")
      (libsource (lib "eagle-import") (part "LED5MM"))
    )
    (comp (ref "LED1217")
      (value "LED5MM")
      (footprint "eagle-import:LED5MM")
      (libsource (lib "eagle-import") (part "LED5MM"))
    )
    (comp (ref "LED1218")
      (value "LED5MM")
      (footprint "eagle-import:LED5MM")
      (libsource (lib "eagle-import") (part "LED5MM"))
    )
    (comp (ref "LED1219")
      (value "LED5MM")
      (footprint "eagle-import:LED5MM")
      (libsource (lib "eagle-import") (part "LED5MM"))
    )
    (comp (ref "LED1220")
      (value "LED5MM")
      (footprint "eagle-import:LED5MM")
      (libsource (lib "eagle-import") (part "LED5MM"))
    )
    (comp (ref "LED1221")
      (value "LED5MM")
      (footprint "eagle-import:LED5MM")
      (libsource (lib "eagle-import") (part "LED5MM"))
    )
    (comp (ref "LED1222")
      (value "LED5MM")
      (footprint "eagle-import:LED5MM")
      (libsource (lib "eagle-import") (part "LED5MM"))
    )
    (comp (ref "LED1223")
      (value "LED5MM")
      (footprint "eagle-import:LED5MM")
      (libsource (lib "eagle-import") (part "LED5MM"))
    )
    (comp (ref "LED1224")
      (value "LED5MM")
      (footprint "eagle-import:LED5MM")
      (libsource (lib "eagle-import") (part "LED5MM"))
    )
    (comp (ref "LED1225")
      (value "LED5MM")
      (footprint "eagle-import:LED5MM")
      (libsource (lib "eagle-import") (part "LED5MM"))
    )
    (comp (ref "LED1226")
      (value "LED5MM")
      (footprint "eagle-import:LED5MM")
      (libsource (lib "eagle-import") (part "LED5MM"))
    )
    (comp (ref "LED1227")
      (value "LED5MM")
      (footprint "eagle-import:LED5MM")
      (libsource (lib "eagle-import") (part "LED5MM"))
    )
    (comp (ref "LED1228")
      (value "LED5MM")
      (footprint "eagle-import:LED5MM")
      (libsource (lib "eagle-import") (part "LED5MM"))
    )
    (comp (ref "LED1229")
      (value "LED5MM")
      (footprint "eagle-import:LED5MM")
      (libsource (lib "eagle-import") (part "LED5MM"))
    )
    (comp (ref "LED1230")
      (value "LED5MM")
      (footprint "eagle-import:LED5MM")
      (libsource (lib "eagle-import") (part "LED5MM"))
    )
    (comp (ref "LED1231")
      (value "LED5MM")
      (footprint "eagle-import:LED5MM")
      (libsource (lib "eagle-import") (part "LED5MM"))
    )
    (comp (ref "LED1232")
      (value "LED5MM")
      (footprint "eagle-import:LED5MM")
      (libsource (lib "eagle-import") (part "LED5MM"))
    )
    (comp (ref "LED1233")
      (value "LED5MM")
      (footprint "eagle-import:LED5MM")
      (libsource (lib "eagle-import") (part "LED5MM"))
    )
    (comp (ref "LED1234")
      (value "LED5MM")
      (footprint "eagle-import:LED5MM")
      (libsource (lib "eagle-import") (part "LED5MM"))
    )
    (comp (ref "LED1235")
      (value "LED5MM")
      (footprint "eagle-import:LED5MM")
      (libsource (lib "eagle-import") (part "LED5MM"))
    )
    (comp (ref "LED1236")
      (value "LED5MM")
      (footprint "eagle-import:LED5MM")
      (libsource (lib "eagle-import") (part "LED5MM"))
    )
    (comp (ref "LED1237")
      (value "LED5MM")
      (footprint "eagle-import:LED5MM")
      (libsource (lib "eagle-import") (part "LED5MM"))
    )
    (comp (ref "LED1238")
      (value "LED5MM")
      (footprint "eagle-import:LED5MM")
      (libsource (lib "eagle-import") (part "LED5MM"))
    )
    (comp (ref "LED1239")
      (value "LED5MM")
      (footprint "eagle-import:LED5MM")
      (libsource (lib "eagle-import") (part "LED5MM"))
    )
    (comp (ref "LED1240")
      (value "LED5MM")
      (footprint "eagle-import:LED5MM")
      (libsource (lib "eagle-import") (part "LED5MM"))
    )
    (comp (ref "LED1241")
      (value "LED5MM")
      (footprint "eagle-import:LED5MM")
      (libsource (lib "eagle-import") (part "LED5MM"))
    )
    (comp (ref "LED1242")
      (value "LED5MM")
      (footprint "eagle-import:LED5MM")
      (libsource (lib "eagle-import") (part "LED5MM"))
    )
    (comp (ref "LED1243")
      (value "LED5MM")
      (footprint "eagle-import:LED5MM")
      (libsource (lib "eagle-import") (part "LED5MM"))
    )
    (comp (ref "LED1244")
      (value "LED5MM")
      (footprint "eagle-import:LED5MM")
      (libsource (lib "eagle-import") (part "LED5MM"))
    )
    (comp (ref "LED1245")
      (value "LED5MM")
      (footprint "eagle-import:LED5MM")
      (libsource (lib "eagle-import") (part "LED5MM"))
    )
    (comp (ref "LED1246")
      (value "LED5MM")
      (footprint "eagle-import:LED5MM")
      (libsource (lib "eagle-import") (part "LED5MM"))
    )
    (comp (ref "LED1247")
      (value "LED5MM")
      (footprint "eagle-import:LED5MM")
      (libsource (lib "eagle-import") (part "LED5MM"))
    )
    (comp (ref "LED1248")
      (value "LED5MM")
      (footprint "eagle-import:LED5MM")
      (libsource (lib "eagle-import") (part "LED5MM"))
    )
    (comp (ref "LED1249")
      (value "LED5MM")
      (footprint "eagle-import:LED5MM")
      (libsource (lib "eagle-import") (part "LED5MM"))
    )
    (comp (ref "LED1250")
      (value "LED5MM")
      (footprint "eagle-import:LED5MM")
      (libsource (lib "eagle-import") (part "LED5MM"))
    )
    (comp (ref "LED1251")
      (value "LED5MM")
      (footprint "eagle-import:LED5MM")
      (libsource (lib "eagle-import") (part "LED5MM"))
    )
    (comp (ref "LED1252")
      (value "LED5MM")
      (footprint "eagle-import:LED5MM")
      (libsource (lib "eagle-import") (part "LED5MM"))
    )
    (comp (ref "LED1253")
      (value "LED5MM")
      (footprint "eagle-import:LED5MM")
      (libsource (lib "eagle-import") (part "LED5MM"))
    )
    (comp (ref "LED1254")
      (value "LED5MM")
      (footprint "eagle-import:LED5MM")
      (libsource (lib "eagle-import") (part "LED5MM"))
    )
    (comp (ref "LED1255")
      (value "LED5MM")
      (footprint "eagle-import:LED5MM")
      (libsource (lib "eagle-import") (part "LED5MM"))
    )
    (comp (ref "LED1256")
      (value "LED5MM")
      (footprint "eagle-import:LED5MM")
      (libsource (lib "eagle-import") (part "LED5MM"))
    )
    (comp (ref "LED1257")
      (value "LED5MM")
      (footprint "eagle-import:LED5MM")
      (libsource (lib "eagle-import") (part "LED5MM"))
    )
    (comp (ref "LED1258")
      (value "LED5MM")
      (footprint "eagle-import:LED5MM")
      (libsource (lib "eagle-import") (part "LED5MM"))
    )
    (comp (ref "LED1259")
      (value "LED5MM")
      (footprint "eagle-import:LED5MM")
      (libsource (lib "eagle-import") (part "LED5MM"))
    )
    (comp (ref "LED1260")
      (value "LED5MM")
      (footprint "eagle-import:LED5MM")
      (libsource (lib "eagle-import") (part "LED5MM"))
    )
    (comp (ref "LED1261")
      (value "LED5MM")
      (footprint "eagle-import:LED5MM")
      (libsource (lib "eagle-import") (part "LED5MM"))
    )
    (comp (ref "LED1262")
      (value "LED5MM")
      (footprint "eagle-import:LED5MM")
      (libsource (lib "eagle-import") (part "LED5MM"))
    )
    (comp (ref "LED1263")
      (value "LED5MM")
      (footprint "eagle-import:LED5MM")
      (libsource (lib "eagle-import") (part "LED5MM"))
    )
    (comp (ref "LED1264")
      (value "LED5MM")
      (footprint "eagle-import:LED5MM")
      (libsource (lib "eagle-import") (part "LED5MM"))
    )
    (comp (ref "LED1265")
      (value "LED5MM")
      (footprint "eagle-import:LED5MM")
      (libsource (lib "eagle-import") (part "LED5MM"))
    )
    (comp (ref "LED1266")
      (value "LED5MM")
      (footprint "eagle-import:LED5MM")
      (libsource (lib "eagle-import") (part "LED5MM"))
    )
    (comp (ref "LED1267")
      (value "LED5MM")
      (footprint "eagle-import:LED5MM")
      (libsource (lib "eagle-import") (part "LED5MM"))
    )
    (comp (ref "LED1268")
      (value "LED5MM")
      (footprint "eagle-import:LED5MM")
      (libsource (lib "eagle-import") (part "LED5MM"))
    )
    (comp (ref "LED1269")
      (value "LED5MM")
      (footprint "eagle-import:LED5MM")
      (libsource (lib "eagle-import") (part "LED5MM"))
    )
    (comp (ref "LED1270")
      (value "LED5MM")
      (footprint "eagle-import:LED5MM")
      (libsource (lib "eagle-import") (part "LED5MM"))
    )
    (comp (ref "LED1271")
      (value "LED5MM")
      (footprint "eagle-import:LED5MM")
      (libsource (lib "eagle-import") (part "LED5MM"))
    )
    (comp (ref "LED1272")
      (value "LED5MM")
      (footprint "eagle-import:LED5MM")
      (libsource (lib "eagle-import") (part "LED5MM"))
    )
    (comp (ref "LED1273")
      (value "LED5MM")
      (footprint "eagle-import:LED5MM")
      (libsource (lib "eagle-import") (part "LED5MM"))
    )
    (comp (ref "LED1274")
      (value "LED5MM")
      (footprint "eagle-import:LED5MM")
      (libsource (lib "eagle-import") (part "LED5MM"))
    )
    (comp (ref "LED1275")
      (value "LED5MM")
      (footprint "eagle-import:LED5MM")
      (libsource (lib "eagle-import") (part "LED5MM"))
    )
    (comp (ref "LED1276")
      (value "LED5MM")
      (footprint "eagle-import:LED5MM")
      (libsource (lib "eagle-import") (part "LED5MM"))
    )
    (comp (ref "LED1277")
      (value "LED5MM")
      (footprint "eagle-import:LED5MM")
      (libsource (lib "eagle-import") (part "LED5MM"))
    )
    (comp (ref "LED1278")
      (value "LED5MM")
      (footprint "eagle-import:LED5MM")
      (libsource (lib "eagle-import") (part "LED5MM"))
    )
    (comp (ref "LED1279")
      (value "LED5MM")
      (footprint "eagle-import:LED5MM")
      (libsource (lib "eagle-import") (part "LED5MM"))
    )
    (comp (ref "LED1280")
      (value "LED5MM")
      (footprint "eagle-import:LED5MM")
      (libsource (lib "eagle-import") (part "LED5MM"))
    )
    (comp (ref "Q1")
      (value "XTAL/S")
      (footprint "eagle-import:QS")
      (libsource (lib "eagle-import") (part "XTAL/S"))
    )
    (comp (ref "R1")
      (value "100")
      (footprint "eagle-import:0207_10")
      (libsource (lib "eagle-import") (part "R-EU_0207/10"))
    )
    (comp (ref "R2")
      (value "100")
      (footprint "eagle-import:0207_10")
      (libsource (lib "eagle-import") (part "R-EU_0207/10"))
    )
    (comp (ref "R3")
      (value "100")
      (footprint "eagle-import:0207_10")
      (libsource (lib "eagle-import") (part "R-EU_0207/10"))
    )
    (comp (ref "R4")
      (value "100")
      (footprint "eagle-import:0207_10")
      (libsource (lib "eagle-import") (part "R-EU_0207/10"))
    )
    (comp (ref "R5")
      (value "100")
      (footprint "eagle-import:0207_10")
      (libsource (lib "eagle-import") (part "R-EU_0207/10"))
    )
    (comp (ref "R6")
      (value "100")
      (footprint "eagle-import:0207_10")
      (libsource (lib "eagle-import") (part "R-EU_0207/10"))
    )
    (comp (ref "R7")
      (value "100")
      (footprint "eagle-import:0207_10")
      (libsource (lib "eagle-import") (part "R-EU_0207/10"))
    )
    (comp (ref "R8")
      (value "100")
      (footprint "eagle-import:0207_10")
      (libsource (lib "eagle-import") (part "R-EU_0207/10"))
    )
    (comp (ref "R9")
      (value "100")
      (footprint "eagle-import:0207_10")
      (libsource (lib "eagle-import") (part "R-EU_0207/10"))
    )
    (comp (ref "R10")
      (value "100")
      (footprint "eagle-import:0207_10")
      (libsource (lib "eagle-import") (part "R-EU_0207/10"))
    )
    (comp (ref "R11")
      (value "100")
      (footprint "eagle-import:0207_10")
      (libsource (lib "eagle-import") (part "R-EU_0207/10"))
    )
    (comp (ref "R12")
      (value "100")
      (footprint "eagle-import:0207_10")
      (libsource (lib "eagle-import") (part "R-EU_0207/10"))
    )
    (comp (ref "R13")
      (value "100")
      (footprint "eagle-import:0207_10")
      (libsource (lib "eagle-import") (part "R-EU_0207/10"))
    )
    (comp (ref "R14")
      (value "100")
      (footprint "eagle-import:0207_10")
      (libsource (lib "eagle-import") (part "R-EU_0207/10"))
    )
    (comp (ref "R15")
      (value "100")
      (footprint "eagle-import:0207_10")
      (libsource (lib "eagle-import") (part "R-EU_0207/10"))
    )
    (comp (ref "R16")
      (value "100")
      (footprint "eagle-import:0207_10")
      (libsource (lib "eagle-import") (part "R-EU_0207/10"))
    )
    (comp (ref "R17")
      (value "10k")
      (footprint "eagle-import:0207_10")
      (libsource (lib "eagle-import") (part "R-EU_0207/10"))
    )
    (comp (ref "S1")
      (value "10-XX")
      (footprint "eagle-import:B3F-10XX")
      (fields (field (name "MPN") "B3F-1000"))
      (libsource (lib "eagle-import") (part "10-XX"))
    )
    (comp (ref "SL1")
      (value "M02")
      (footprint "eagle-import:02P")
      (libsource (lib "eagle-import") (part "M02"))
    )
    (comp (ref "X1")
      (value "PN87520")
      (footprint "eagle-import:PN87520")
      (libsource (lib "eagle-import") (part "PN87520"))
    )
  )
  (nets
    (net (code "1") (name "GND") (class "Default")
      (node (ref "C1") (pin "2") (pinfunction "2_2") (pintype "passive"))
      (node (ref "C2") (pin "2") (pinfunction "2_2") (pintype "passive"))
      (node (ref "C3") (pin "2") (pinfunction "2_2") (pintype "passive"))
      (node (ref "C4") (pin "2") (pinfunction "2_2") (pintype "passive"))
      (node (ref "IC1") (pin "9") (pinfunction "GND_9") (pintype "power_in"))
      (node (ref "IC13") (pin "12") (pinfunction "VSS_12") (pintype "power_in"))
      (node (ref "IC13") (pin "31") (pinfunction "VSS_31") (pintype "power_in"))
      (node (ref "IC14") (pin "4") (pinfunction "GND_4") (pintype "power_in"))
      (node (ref "IC2") (pin "9") (pinfunction "GND_9") (pintype "power_in"))
      (node (ref "J1") (pin "3") (pinfunction "3_3") (pintype "passive"))
      (node (ref "S1") (pin "3") (pinfunction "P_3") (pintype "passive"))
      (node (ref "S1") (pin "4") (pinfunction "P1_4") (pintype "passive"))
      (node (ref "SL1") (pin "2") (pinfunction "2_2") (pintype "passive"))
      (node (ref "X1") (pin "4") (pinfunction "4_4") (pintype "passive"))
    )
    (net (code "2") (name "Net-(IC1-I1)") (class "Default")
      (node (ref "IC1") (pin "1") (pinfunction "I1_1") (pintype "input"))
      (node (ref "IC13") (pin "33") (pinfunction "INT/RB0_33") (pintype "bidirectional"))
    )
    (net (code "3") (name "Net-(IC1-I2)") (class "Default")
      (node (ref "IC1") (pin "2") (pinfunction "I2_2") (pintype "input"))
      (node (ref "IC13") (pin "34") (pinfunction "RB1_34") (pintype "bidirectional"))
    )
    (net (code "4") (name "Net-(IC1-I3)") (class "Default")
      (node (ref "IC1") (pin "3") (pinfunction "I3_3") (pintype "input"))
      (node (ref "IC13") (pin "35") (pinfunction "RB2_35") (pintype "bidirectional"))
    )
    (net (code "5") (name "Net-(IC1-I4)") (class "Default")
      (node (ref "IC1") (pin "4") (pinfunction "I4_4") (pintype "input"))
      (node (ref "IC13") (pin "36") (pinfunction "PGM/RB3_36") (pintype "bidirectional"))
    )
    (net (code "6") (name "Net-(IC1-I5)") (class "Default")
      (node (ref "IC1") (pin "5") (pinfunction "I5_5") (pintype "input"))
      (node (ref "IC13") (pin "37") (pinfunction "RB4_37") (pintype "bidirectional"))
    )
    (net (code "7") (name "Net-(IC1-I6)") (class "Default")
      (node (ref "IC1") (pin "6") (pinfunction "I6_6") (pintype "input"))
      (node (ref "IC13") (pin "38") (pinfunction "RB5_38") (pintype "bidirectional"))
      (node (ref "J1") (pin "5") (pinfunction "5_5") (pintype "passive"))
    )
    (net (code "8") (name "Net-(IC1-I7)") (class "Default")
      (node (ref "IC1") (pin "7") (pinfunction "I7_7") (pintype "input"))
      (node (ref "IC13") (pin "39") (pinfunction "PGC/RB6_39") (pintype "bidirectional"))
      (node (ref "J1") (pin "4") (pinfunction "4_4") (pintype "passive"))
    )
    (net (code "9") (name "Net-(IC1-I8)") (class "Default")
      (node (ref "IC1") (pin "8") (pinfunction "I8_8") (pintype "input"))
      (node (ref "IC13") (pin "40") (pinfunction "PGD/RB7_40") (pintype "bidirectional"))
    )
    (net (code "10") (name "Net-(IC1-O1)") (class "Default")
      (node (ref "IC1") (pin "18") (pinfunction "O1_18") (pintype "open_collector"))
      (node (ref "R1") (pin "2") (pinfunction "2_2") (pintype "passive"))
    )
    (net (code "11") (name "Net-(IC1-O2)") (class "Default")
      (node (ref "IC1") (pin "17") (pinfunction "O2_17") (pintype "open_collector"))
      (node (ref "R2") (pin "2") (pinfunction "2_2") (pintype "passive"))
    )
    (net (code "12") (name "Net-(IC1-O3)") (class "Default")
      (node (ref "IC1") (pin "16") (pinfunction "O3_16") (pintype "open_collector"))
      (node (ref "R3") (pin "2") (pinfunction "2_2") (pintype "passive"))
    )
    (net (code "13") (name "Net-(IC1-O4)") (class "Default")
      (node (ref "IC1") (pin "15") (pinfunction "O4_15") (pintype "open_collector"))
      (node (ref "R4") (pin "2") (pinfunction "2_2") (pintype "passive"))
    )
    (net (code "14") (name "Net-(IC1-O5)") (class "Default")
      (node (ref "IC1") (pin "14") (pinfunction "O5_14") (pintype "open_collector"))
      (node (ref "R5") (pin "2") (pinfunction "2_2") (pintype "passive"))
    )
    (net (code "15") (name "Net-(IC1-O6)") (class "Default")
      (node (ref "IC1") (pin "13") (pinfunction "O6_13") (pintype "open_collector"))
      (node (ref "R6") (pin "2") (pinfunction "2_2") (pintype "passive"))
    )
    (net (code "16") (name "Net-(IC1-O7)") (class "Default")
      (node (ref "IC1") (pin "12") (pinfunction "O7_12") (pintype "open_collector"))
      (node (ref "R7") (pin "2") (pinfunction "2_2") (pintype "passive"))
    )
    (net (code "17") (name "Net-(IC1-O8)") (class "Default")
      (node (ref "IC1") (pin "11") (pinfunction "O8_11") (pintype "open_collector"))
      (node (ref "R8") (pin "2") (pinfunction "2_2") (pintype "passive"))
    )
    (net (code "18") (name "Net-(IC2-O1)") (class "Default")
      (node (ref "IC2") (pin "18") (pinfunction "O1_18") (pintype "open_collector"))
      (node (ref "R9") (pin "2") (pinfunction "2_2") (pintype "passive"))
    )
    (net (code "19") (name "Net-(IC2-O2)") (class "Default")
      (node (ref "IC2") (pin "17") (pinfunction "O2_17") (pintype "open_collector"))
      (node (ref "R10") (pin "2") (pinfunction "2_2") (pintype "passive"))
    )
    (net (code "20") (name "Net-(IC2-O3)") (class "Default")
      (node (ref "IC2") (pin "16") (pinfunction "O3_16") (pintype "open_collector"))
      (node (ref "R11") (pin "2") (pinfunction "2_2") (pintype "passive"))
    )
    (net (code "21") (name "Net-(IC2-O4)") (class "Default")
      (node (ref "IC2") (pin "15") (pinfunction "O4_15") (pintype "open_collector"))
      (node (ref "R12") (pin "2") (pinfunction "2_2") (pintype "passive"))
    )
    (net (code "22") (name "Net-(IC2-O5)") (class "Default")
      (node (ref "IC2") (pin "14") (pinfunction "O5_14") (pintype "open_collector"))
      (node (ref "R13") (pin "2") (pinfunction "2_2") (pintype "passive"))
    )
    (net (code "23") (name "Net-(IC2-O6)") (class "Default")
      (node (ref "IC2") (pin "13") (pinfunction "O6_13") (pintype "open_collector"))
      (node (ref "R14") (pin "2") (pinfunction "2_2") (pintype "passive"))
    )
    (net (code "24") (name "Net-(IC2-O7)") (class "Default")
      (node (ref "IC2") (pin "12") (pinfunction "O7_12") (pintype "open_collector"))
      (node (ref "R15") (pin "2") (pinfunction "2_2") (pintype "passive"))
    )
    (net (code "25") (name "Net-(IC2-O8)") (class "Default")
      (node (ref "IC2") (pin "11") (pinfunction "O8_11") (pintype "open_collector"))
      (node (ref "R16") (pin "2") (pinfunction "2_2") (pintype "passive"))
    )
    (net (code "26") (name "Net-(IC3A-A)") (class "Default")
      (node (ref "IC3") (pin "1") (pinfunction "A_1") (pintype "input"))
      (node (ref "IC3") (pin "2") (pinfunction "B_2") (pintype "input"))
      (node (ref "IC4") (pin "13") (pinfunction "QH_13") (pintype "output"))
      (node (ref "LED129") (pin "A") (pinfunction "A_A") (pintype "passive"))
      (node (ref "LED130") (pin "A") (pinfunction "A_A") (pintype "passive"))
      (node (ref "LED131") (pin "A") (pinfunction "A_A") (pintype "passive"))
      (node (ref "LED132") (pin "A") (pinfunction "A_A") (pintype "passive"))
      (node (ref "LED133") (pin "A") (pinfunction "A_A") (pintype "passive"))
      (node (ref "LED134") (pin "A") (pinfunction "A_A") (pintype "passive"))
      (node (ref "LED135") (pin "A") (pinfunction "A_A") (pintype "passive"))
      (node (ref "LED136") (pin "A") (pinfunction "A_A") (pintype "passive"))
      (node (ref "LED137") (pin "A") (pinfunction "A_A") (pintype "passive"))
      (node (ref "LED138") (pin "A") (pinfunction "A_A") (pintype "passive"))
      (node (ref "LED139") (pin "A") (pinfunction "A_A") (pintype "passive"))
      (node (ref "LED140") (pin "A") (pinfunction "A_A") (pintype "passive"))
      (node (ref "LED141") (pin "A") (pinfunction "A_A") (pintype "passive"))
      (node (ref "LED142") (pin "A") (pinfunction "A_A") (pintype "passive"))
      (node (ref "LED143") (pin "A") (pinfunction "A_A") (pintype "passive"))
      (node (ref "LED144") (pin "A") (pinfunction "A_A") (pintype "passive"))
    )
    (net (code "27") (name "Net-(IC3A-QA)") (class "Default")
      (node (ref "IC3") (pin "3") (pinfunction "QA_3") (pintype "output"))
      (node (ref "LED113") (pin "A") (pinfunction "A_A") (pintype "passive"))
      (node (ref "LED114") (pin "A") (pinfunction "A_A") (pintype "passive"))
      (node (ref "LED115") (pin "A") (pinfunction "A_A") (pintype "passive"))
      (node (ref "LED116") (pin "A") (pinfunction "A_A") (pintype "passive"))
      (node (ref "LED117") (pin "A") (pinfunction "A_A") (pintype "passive"))
      (node (ref "LED118") (pin "A") (pinfunction "A_A") (pintype "passive"))
      (node (ref "LED119") (pin "A") (pinfunction "A_A") (pintype "passive"))
      (node (ref "LED120") (pin "A") (pinfunction "A_A") (pintype "passive"))
      (node (ref "LED121") (pin "A") (pinfunction "A_A") (pintype "passive"))
      (node (ref "LED122") (pin "A") (pinfunction "A_A") (pintype "passive"))
      (node (ref "LED123") (pin "A") (pinfunction "A_A") (pintype "passive"))
      (node (ref "LED124") (pin "A") (pinfunction "A_A") (pintype "passive"))
      (node (ref "LED125") (pin "A") (pinfunction "A_A") (pintype "passive"))
      (node (ref "LED126") (pin "A") (pinfunction "A_A") (pintype "passive"))
      (node (ref "LED127") (pin "A") (pinfunction "A_A") (pintype "passive"))
      (node (ref "LED128") (pin "A") (pinfunction "A_A") (pintype "passive"))
    )
    (net (code "28") (name "Net-(IC3A-QB)") (class "Default")
      (node (ref "IC3") (pin "4") (pinfunction "QB_4") (pintype "output"))
      (node (ref "LED100") (pin "A") (pinfunction "A_A") (pintype "passive"))
      (node (ref "LED101") (pin "A") (pinfunction "A_A") (pintype "passive"))
      (node (ref "LED102") (pin "A") (pinfunction "A_A") (pintype "passive"))
      (node (ref "LED103") (pin "A") (pinfunction "A_A") (pintype "passive"))
      (node (ref "LED104") (pin "A") (pinfunction "A_A") (pintype "passive"))
      (node (ref "LED105") (pin "A") (pinfunction "A_A") (pintype "passive"))
      (node (ref "LED106") (pin "A") (pinfunction "A_A") (pintype "passive"))
      (node (ref "LED107") (pin "A") (pinfunction "A_A") (pintype "passive"))
      (node (ref "LED108") (pin "A") (pinfunction "A_A") (pintype "passive"))
      (node (ref "LED109") (pin "A") (pinfunction "A_A") (pintype "passive"))
      (node (ref "LED110") (pin "A") (pinfunction "A_A") (pintype "passive"))
      (node (ref "LED111") (pin "A") (pinfunction "A_A") (pintype "passive"))
      (node (ref "LED112") (pin "A") (pinfunction "A_A") (pintype "passive"))
      (node (ref "LED97") (pin "A") (pinfunction "A_A") (pintype "passive"))
      (node (ref "LED98") (pin "A") (pinfunction "A_A") (pintype "passive"))
      (node (ref "LED99") (pin "A") (pinfunction "A_A") (pintype "passive"))
    )
    (net (code "29") (name "Net-(IC3A-QC)") (class "Default")
      (node (ref "IC3") (pin "5") (pinfunction "QC_5") (pintype "output"))
      (node (ref "LED81") (pin "A") (pinfunction "A_A") (pintype "passive"))
      (node (ref "LED82") (pin "A") (pinfunction "A_A") (pintype "passive"))
      (node (ref "LED83") (pin "A") (pinfunction "A_A") (pintype "passive"))
      (node (ref "LED84") (pin "A") (pinfunction "A_A") (pintype "passive"))
      (node (ref "LED85") (pin "A") (pinfunction "A_A") (pintype "passive"))
      (node (ref "LED86") (pin "A") (pinfunction "A_A") (pintype "passive"))
      (node (ref "LED87") (pin "A") (pinfunction "A_A") (pintype "passive"))
      (node (ref "LED88") (pin "A") (pinfunction "A_A") (pintype "passive"))
      (node (ref "LED89") (pin "A") (pinfunction "A_A") (pintype "passive"))
      (node (ref "LED90") (pin "A") (pinfunction "A_A") (pintype "passive"))
      (node (ref "LED91") (pin "A") (pinfunction "A_A") (pintype "passive"))
      (node (ref "LED92") (pin "A") (pinfunction "A_A") (pintype "passive"))
      (node (ref "LED93") (pin "A") (pinfunction "A_A") (pintype "passive"))
      (node (ref "LED94") (pin "A") (pinfunction "A_A") (pintype "passive"))
      (node (ref "LED95") (pin "A") (pinfunction "A_A") (pintype "passive"))
      (node (ref "LED96") (pin "A") (pinfunction "A_A") (pintype "passive"))
    )
    (net (code "30") (name "Net-(IC3A-QD)") (class "Default")
      (node (ref "IC3") (pin "6") (pinfunction "QD_6") (pintype "output"))
      (node (ref "LED65") (pin "A") (pinfunction "A_A") (pintype "passive"))
      (node (ref "LED66") (pin "A") (pinfunction "A_A") (pintype "passive"))
      (node (ref "LED67") (pin "A") (pinfunction "A_A") (pintype "passive"))
      (node (ref "LED68") (pin "A") (pinfunction "A_A") (pintype "passive"))
      (node (ref "LED69") (pin "A") (pinfunction "A_A") (pintype "passive"))
      (node (ref "LED70") (pin "A") (pinfunction "A_A") (pintype "passive"))
      (node (ref "LED71") (pin "A") (pinfunction "A_A") (pintype "passive"))
      (node (ref "LED72") (pin "A") (pinfunction "A_A") (pintype "passive"))
      (node (ref "LED73") (pin "A") (pinfunction "A_A") (pintype "passive"))
      (node (ref "LED74") (pin "A") (pinfunction "A_A") (pintype "passive"))
      (node (ref "LED75") (pin "A") (pinfunction "A_A") (pintype "passive"))
      (node (ref "LED76") (pin "A") (pinfunction "A_A") (pintype "passive"))
      (node (ref "LED77") (pin "A") (pinfunction "A_A") (pintype "passive"))
      (node (ref "LED78") (pin "A") (pinfunction "A_A") (pintype "passive"))
      (node (ref "LED79") (pin "A") (pinfunction "A_A") (pintype "passive"))
      (node (ref "LED80") (pin "A") (pinfunction "A_A") (pintype "passive"))
    )
    (net (code "31") (name "Net-(IC3A-QE)") (class "Default")
      (node (ref "IC3") (pin "10") (pinfunction "QE_10") (pintype "output"))
      (node (ref "LED49") (pin "A") (pinfunction "A_A") (pintype "passive"))
      (node (ref "LED50") (pin "A") (pinfunction "A_A") (pintype "passive"))
      (node (ref "LED51") (pin "A") (pinfunction "A_A") (pintype "passive"))
      (node (ref "LED52") (pin "A") (pinfunction "A_A") (pintype "passive"))
      (node (ref "LED53") (pin "A") (pinfunction "A_A") (pintype "passive"))
      (node (ref "LED54") (pin "A") (pinfunction "A_A") (pintype "passive"))
      (node (ref "LED55") (pin "A") (pinfunction "A_A") (pintype "passive"))
      (node (ref "LED56") (pin "A") (pinfunction "A_A") (pintype "passive"))
      (node (ref "LED57") (pin "A") (pinfunction "A_A") (pintype "passive"))
      (node (ref "LED58") (pin "A") (pinfunction "A_A") (pintype "passive"))
      (node (ref "LED59") (pin "A") (pinfunction "A_A") (pintype "passive"))
      (node (ref "LED60") (pin "A") (pinfunction "A_A") (pintype "passive"))
      (node (ref "LED61") (pin "A") (pinfunction "A_A") (pintype "passive"))
      (node (ref "LED62") (pin "A") (pinfunction "A_A") (pintype "passive"))
      (node (ref "LED63") (pin "A") (pinfunction "A_A") (pintype "passive"))
      (node (ref "LED64") (pin "A") (pinfunction "A_A") (pintype "passive"))
    )
    (net (code "32") (name "Net-(IC3A-QF)") (class "Default")
      (node (ref "IC3") (pin "11") (pinfunction "QF_11") (pintype "output"))
      (node (ref "LED33") (pin "A") (pinfunction "A_A") (pintype "passive"))
      (node (ref "LED34") (pin "A") (pinfunction "A_A") (pintype "passive"))
      (node (ref "LED35") (pin "A") (pinfunction "A_A") (pintype "passive"))
      (node (ref "LED36") (pin "A") (pinfunction "A_A") (pintype "passive"))
      (node (ref "LED37") (pin "A") (pinfunction "A_A") (pintype "passive"))
      (node (ref "LED38") (pin "A") (pinfunction "A_A") (pintype "passive"))
      (node (ref "LED39") (pin "A") (pinfunction "A_A") (pintype "passive"))
      (node (ref "LED40") (pin "A") (pinfunction "A_A") (pintype "passive"))
      (node (ref "LED41") (pin "A") (pinfunction "A_A") (pintype "passive"))
      (node (ref "LED42") (pin "A") (pinfunction "A_A") (pintype "passive"))
      (node (ref "LED43") (pin "A") (pinfunction "A_A") (pintype "passive"))
      (node (ref "LED44") (pin "A") (pinfunction "A_A") (pintype "passive"))
      (node (ref "LED45") (pin "A") (pinfunction "A_A") (pintype "passive"))
      (node (ref "LED46") (pin "A") (pinfunction "A_A") (pintype "passive"))
      (node (ref "LED47") (pin "A") (pinfunction "A_A") (pintype "passive"))
      (node (ref "LED48") (pin "A") (pinfunction "A_A") (pintype "passive"))
    )
    (net (code "33") (name "Net-(IC3A-QG)") (class "Default")
      (node (ref "IC3") (pin "12") (pinfunction "QG_12") (pintype "output"))
      (node (ref "LED17") (pin "A") (pinfunction "A_A") (pintype "passive"))
      (node (ref "LED18") (pin "A") (pinfunction "A_A") (pintype "passive"))
      (node (ref "LED19") (pin "A") (pinfunction "A_A") (pintype "passive"))
      (node (ref "LED20") (pin "A") (pinfunction "A_A") (pintype "passive"))
      (node (ref "LED21") (pin "A") (pinfunction "A_A") (pintype "passive"))
      (node (ref "LED22") (pin "A") (pinfunction "A_A") (pintype "passive"))
      (node (ref "LED23") (pin "A") (pinfunction "A_A") (pintype "passive"))
      (node (ref "LED24") (pin "A") (pinfunction "A_A") (pintype "passive"))
      (node (ref "LED25") (pin "A") (pinfunction "A_A") (pintype "passive"))
      (node (ref "LED26") (pin "A") (pinfunction "A_A") (pintype "passive"))
      (node (ref "LED27") (pin "A") (pinfunction "A_A") (pintype "passive"))
      (node (ref "LED28") (pin "A") (pinfunction "A_A") (pintype "passive"))
      (node (ref "LED29") (pin "A") (pinfunction "A_A") (pintype "passive"))
      (node (ref "LED30") (pin "A") (pinfunction "A_A") (pintype "passive"))
      (node (ref "LED31") (pin "A") (pinfunction "A_A") (pintype "passive"))
      (node (ref "LED32") (pin "A") (pinfunction "A_A") (pintype "passive"))
    )
    (net (code "34") (name "Net-(IC3A-QH)") (class "Default")
      (node (ref "IC3") (pin "13") (pinfunction "QH_13") (pintype "output"))
      (node (ref "LED1") (pin "A") (pinfunction "A_A") (pintype "passive"))
      (node (ref "LED10") (pin "A") (pinfunction "A_A") (pintype "passive"))
      (node (ref "LED11") (pin "A") (pinfunction "A_A") (pintype "passive"))
      (node (ref "LED12") (pin "A") (pinfunction "A_A") (pintype "passive"))
      (node (ref "LED13") (pin "A") (pinfunction "A_A") (pintype "passive"))
      (node (ref "LED14") (pin "A") (pinfunction "A_A") (pintype "passive"))
      (node (ref "LED15") (pin "A") (pinfunction "A_A") (pintype "passive"))
      (node (ref "LED16") (pin "A") (pinfunction "A_A") (pintype "passive"))
      (node (ref "LED2") (pin "A") (pinfunction "A_A") (pintype "passive"))
      (node (ref "LED3") (pin "A") (pinfunction "A_A") (pintype "passive"))
      (node (ref "LED4") (pin "A") (pinfunction "A_A") (pintype "passive"))
      (node (ref "LED5") (pin "A") (pinfunction "A_A") (pintype "passive"))
      (node (ref "LED6") (pin "A") (pinfunction "A_A") (pintype "passive"))
      (node (ref "LED7") (pin "A") (pinfunction "A_A") (pintype "passive"))
      (node (ref "LED8") (pin "A") (pinfunction "A_A") (pintype "passive"))
      (node (ref "LED9") (pin "A") (pinfunction "A_A") (pintype "passive"))
    )
    (net (code "35") (name "Net-(IC4A-A)") (class "Default")
      (node (ref "IC4") (pin "1") (pinfunction "A_1") (pintype "input"))
      (node (ref "IC4") (pin "2") (pinfunction "B_2") (pintype "input"))
      (node (ref "IC5") (pin "13") (pinfunction "QH_13") (pintype "output"))
      (node (ref "LED257") (pin "A") (pinfunction "A_A") (pintype "passive"))
      (node (ref "LED258") (pin "A") (pinfunction "A_A") (pintype "passive"))
      (node (ref "LED259") (pin "A") (pinfunction "A_A") (pintype "passive"))
      (node (ref "LED260") (pin "A") (pinfunction "A_A") (pintype "passive"))
      (node (ref "LED261") (pin "A") (pinfunction "A_A") (pintype "passive"))
      (node (ref "LED262") (pin "A") (pinfunction "A_A") (pintype "passive"))
      (node (ref "LED263") (pin "A") (pinfunction "A_A") (pintype "passive"))
      (node (ref "LED264") (pin "A") (pinfunction "A_A") (pintype "passive"))
      (node (ref "LED265") (pin "A") (pinfunction "A_A") (pintype "passive"))
      (node (ref "LED266") (pin "A") (pinfunction "A_A") (pintype "passive"))
      (node (ref "LED267") (pin "A") (pinfunction "A_A") (pintype "passive"))
      (node (ref "LED268") (pin "A") (pinfunction "A_A") (pintype "passive"))
      (node (ref "LED269") (pin "A") (pinfunction "A_A") (pintype "passive"))
      (node (ref "LED270") (pin "A") (pinfunction "A_A") (pintype "passive"))
      (node (ref "LED271") (pin "A") (pinfunction "A_A") (pintype "passive"))
      (node (ref "LED272") (pin "A") (pinfunction "A_A") (pintype "passive"))
    )
    (net (code "36") (name "Net-(IC4A-QA)") (class "Default")
      (node (ref "IC4") (pin "3") (pinfunction "QA_3") (pintype "output"))
      (node (ref "LED241") (pin "A") (pinfunction "A_A") (pintype "passive"))
      (node (ref "LED242") (pin "A") (pinfunction "A_A") (pintype "passive"))
      (node (ref "LED243") (pin "A") (pinfunction "A_A") (pintype "passive"))
      (node (ref "LED244") (pin "A") (pinfunction "A_A") (pintype "passive"))
      (node (ref "LED245") (pin "A") (pinfunction "A_A") (pintype "passive"))
      (node (ref "LED246") (pin "A") (pinfunction "A_A") (pintype "passive"))
      (node (ref "LED247") (pin "A") (pinfunction "A_A") (pintype "passive"))
      (node (ref "LED248") (pin "A") (pinfunction "A_A") (pintype "passive"))
      (node (ref "LED249") (pin "A") (pinfunction "A_A") (pintype "passive"))
      (node (ref "LED250") (pin "A") (pinfunction "A_A") (pintype "passive"))
      (node (ref "LED251") (pin "A") (pinfunction "A_A") (pintype "passive"))
      (node (ref "LED252") (pin "A") (pinfunction "A_A") (pintype "passive"))
      (node (ref "LED253") (pin "A") (pinfunction "A_A") (pintype "passive"))
      (node (ref "LED254") (pin "A") (pinfunction "A_A") (pintype "passive"))
      (node (ref "LED255") (pin "A") (pinfunction "A_A") (pintype "passive"))
      (node (ref "LED256") (pin "A") (pinfunction "A_A") (pintype "passive"))
    )
    (net (code "37") (name "Net-(IC4A-QB)") (class "Default")
      (node (ref "IC4") (pin "4") (pinfunction "QB_4") (pintype "output"))
      (node (ref "LED225") (pin "A") (pinfunction "A_A") (pintype "passive"))
      (node (ref "LED226") (pin "A") (pinfunction "A_A") (pintype "passive"))
      (node (ref "LED227") (pin "A") (pinfunction "A_A") (pintype "passive"))
      (node (ref "LED228") (pin "A") (pinfunction "A_A") (pintype "passive"))
      (node (ref "LED229") (pin "A") (pinfunction "A_A") (pintype "passive"))
      (node (ref "LED230") (pin "A") (pinfunction "A_A") (pintype "passive"))
      (node (ref "LED231") (pin "A") (pinfunction "A_A") (pintype "passive"))
      (node (ref "LED232") (pin "A") (pinfunction "A_A") (pintype "passive"))
      (node (ref "LED233") (pin "A") (pinfunction "A_A") (pintype "passive"))
      (node (ref "LED234") (pin "A") (pinfunction "A_A") (pintype "passive"))
      (node (ref "LED235") (pin "A") (pinfunction "A_A") (pintype "passive"))
      (node (ref "LED236") (pin "A") (pinfunction "A_A") (pintype "passive"))
      (node (ref "LED237") (pin "A") (pinfunction "A_A") (pintype "passive"))
      (node (ref "LED238") (pin "A") (pinfunction "A_A") (pintype "passive"))
      (node (ref "LED239") (pin "A") (pinfunction "A_A") (pintype "passive"))
      (node (ref "LED240") (pin "A") (pinfunction "A_A") (pintype "passive"))
    )
    (net (code "38") (name "Net-(IC4A-QC)") (class "Default")
      (node (ref "IC4") (pin "5") (pinfunction "QC_5") (pintype "output"))
      (node (ref "LED209") (pin "A") (pinfunction "A_A") (pintype "passive"))
      (node (ref "LED210") (pin "A") (pinfunction "A_A") (pintype "passive"))
      (node (ref "LED211") (pin "A") (pinfunction "A_A") (pintype "passive"))
      (node (ref "LED212") (pin "A") (pinfunction "A_A") (pintype "passive"))
      (node (ref "LED213") (pin "A") (pinfunction "A_A") (pintype "passive"))
      (node (ref "LED214") (pin "A") (pinfunction "A_A") (pintype "passive"))
      (node (ref "LED215") (pin "A") (pinfunction "A_A") (pintype "passive"))
      (node (ref "LED216") (pin "A") (pinfunction "A_A") (pintype "passive"))
      (node (ref "LED217") (pin "A") (pinfunction "A_A") (pintype "passive"))
      (node (ref "LED218") (pin "A") (pinfunction "A_A") (pintype "passive"))
      (node (ref "LED219") (pin "A") (pinfunction "A_A") (pintype "passive"))
      (node (ref "LED220") (pin "A") (pinfunction "A_A") (pintype "passive"))
      (node (ref "LED221") (pin "A") (pinfunction "A_A") (pintype "passive"))
      (node (ref "LED222") (pin "A") (pinfunction "A_A") (pintype "passive"))
      (node (ref "LED223") (pin "A") (pinfunction "A_A") (pintype "passive"))
      (node (ref "LED224") (pin "A") (pinfunction "A_A") (pintype "passive"))
    )
    (net (code "39") (name "Net-(IC4A-QD)") (class "Default")
      (node (ref "IC4") (pin "6") (pinfunction "QD_6") (pintype "output"))
      (node (ref "LED193") (pin "A") (pinfunction "A_A") (pintype "passive"))
      (node (ref "LED194") (pin "A") (pinfunction "A_A") (pintype "passive"))
      (node (ref "LED195") (pin "A") (pinfunction "A_A") (pintype "passive"))
      (node (ref "LED196") (pin "A") (pinfunction "A_A") (pintype "passive"))
      (node (ref "LED197") (pin "A") (pinfunction "A_A") (pintype "passive"))
      (node (ref "LED198") (pin "A") (pinfunction "A_A") (pintype "passive"))
      (node (ref "LED199") (pin "A") (pinfunction "A_A") (pintype "passive"))
      (node (ref "LED200") (pin "A") (pinfunction "A_A") (pintype "passive"))
      (node (ref "LED201") (pin "A") (pinfunction "A_A") (pintype "passive"))
      (node (ref "LED202") (pin "A") (pinfunction "A_A") (pintype "passive"))
      (node (ref "LED203") (pin "A") (pinfunction "A_A") (pintype "passive"))
      (node (ref "LED204") (pin "A") (pinfunction "A_A") (pintype "passive"))
      (node (ref "LED205") (pin "A") (pinfunction "A_A") (pintype "passive"))
      (node (ref "LED206") (pin "A") (pinfunction "A_A") (pintype "passive"))
      (node (ref "LED207") (pin "A") (pinfunction "A_A") (pintype "passive"))
      (node (ref "LED208") (pin "A") (pinfunction "A_A") (pintype "passive"))
    )
    (net (code "40") (name "Net-(IC4A-QE)") (class "Default")
      (node (ref "IC4") (pin "10") (pinfunction "QE_10") (pintype "output"))
      (node (ref "LED177") (pin "A") (pinfunction "A_A") (pintype "passive"))
      (node (ref "LED178") (pin "A") (pinfunction "A_A") (pintype "passive"))
      (node (ref "LED179") (pin "A") (pinfunction "A_A") (pintype "passive"))
      (node (ref "LED180") (pin "A") (pinfunction "A_A") (pintype "passive"))
      (node (ref "LED181") (pin "A") (pinfunction "A_A") (pintype "passive"))
      (node (ref "LED182") (pin "A") (pinfunction "A_A") (pintype "passive"))
      (node (ref "LED183") (pin "A") (pinfunction "A_A") (pintype "passive"))
      (node (ref "LED184") (pin "A") (pinfunction "A_A") (pintype "passive"))
      (node (ref "LED185") (pin "A") (pinfunction "A_A") (pintype "passive"))
      (node (ref "LED186") (pin "A") (pinfunction "A_A") (pintype "passive"))
      (node (ref "LED187") (pin "A") (pinfunction "A_A") (pintype "passive"))
      (node (ref "LED188") (pin "A") (pinfunction "A_A") (pintype "passive"))
      (node (ref "LED189") (pin "A") (pinfunction "A_A") (pintype "passive"))
      (node (ref "LED190") (pin "A") (pinfunction "A_A") (pintype "passive"))
      (node (ref "LED191") (pin "A") (pinfunction "A_A") (pintype "passive"))
      (node (ref "LED192") (pin "A") (pinfunction "A_A") (pintype "passive"))
    )
    (net (code "41") (name "Net-(IC4A-QF)") (class "Default")
      (node (ref "IC4") (pin "11") (pinfunction "QF_11") (pintype "output"))
      (node (ref "LED161") (pin "A") (pinfunction "A_A") (pintype "passive"))
      (node (ref "LED162") (pin "A") (pinfunction "A_A") (pintype "passive"))
      (node (ref "LED163") (pin "A") (pinfunction "A_A") (pintype "passive"))
      (node (ref "LED164") (pin "A") (pinfunction "A_A") (pintype "passive"))
      (node (ref "LED165") (pin "A") (pinfunction "A_A") (pintype "passive"))
      (node (ref "LED166") (pin "A") (pinfunction "A_A") (pintype "passive"))
      (node (ref "LED167") (pin "A") (pinfunction "A_A") (pintype "passive"))
      (node (ref "LED168") (pin "A") (pinfunction "A_A") (pintype "passive"))
      (node (ref "LED169") (pin "A") (pinfunction "A_A") (pintype "passive"))
      (node (ref "LED170") (pin "A") (pinfunction "A_A") (pintype "passive"))
      (node (ref "LED171") (pin "A") (pinfunction "A_A") (pintype "passive"))
      (node (ref "LED172") (pin "A") (pinfunction "A_A") (pintype "passive"))
      (node (ref "LED173") (pin "A") (pinfunction "A_A") (pintype "passive"))
      (node (ref "LED174") (pin "A") (pinfunction "A_A") (pintype "passive"))
      (node (ref "LED175") (pin "A") (pinfunction "A_A") (pintype "passive"))
      (node (ref "LED176") (pin "A") (pinfunction "A_A") (pintype "passive"))
    )
    (net (code "42") (name "Net-(IC4A-QG)") (class "Default")
      (node (ref "IC4") (pin "12") (pinfunction "QG_12") (pintype "output"))
      (node (ref "LED145") (pin "A") (pinfunction "A_A") (pintype "passive"))
      (node (ref "LED146") (pin "A") (pinfunction "A_A") (pintype "passive"))
      (node (ref "LED147") (pin "A") (pinfunction "A_A") (pintype "passive"))
      (node (ref "LED148") (pin "A") (pinfunction "A_A") (pintype "passive"))
      (node (ref "LED149") (pin "A") (pinfunction "A_A") (pintype "passive"))
      (node (ref "LED150") (pin "A") (pinfunction "A_A") (pintype "passive"))
      (node (ref "LED151") (pin "A") (pinfunction "A_A") (pintype "passive"))
      (node (ref "LED152") (pin "A") (pinfunction "A_A") (pintype "passive"))
      (node (ref "LED153") (pin "A") (pinfunction "A_A") (pintype "passive"))
      (node (ref "LED154") (pin "A") (pinfunction "A_A") (pintype "passive"))
      (node (ref "LED155") (pin "A") (pinfunction "A_A") (pintype "passive"))
      (node (ref "LED156") (pin "A") (pinfunction "A_A") (pintype "passive"))
      (node (ref "LED157") (pin "A") (pinfunction "A_A") (pintype "passive"))
      (node (ref "LED158") (pin "A") (pinfunction "A_A") (pintype "passive"))
      (node (ref "LED159") (pin "A") (pinfunction "A_A") (pintype "passive"))
      (node (ref "LED160") (pin "A") (pinfunction "A_A") (pintype "passive"))
    )
    (net (code "43") (name "Net-(IC5A-A)") (class "Default")
      (node (ref "IC5") (pin "1") (pinfunction "A_1") (pintype "input"))
      (node (ref "IC5") (pin "2") (pinfunction "B_2") (pintype "input"))
      (node (ref "IC6") (pin "13") (pinfunction "QH_13") (pintype "output"))
      (node (ref "LED385") (pin "A") (pinfunction "A_A") (pintype "passive"))
      (node (ref "LED386") (pin "A") (pinfunction "A_A") (pintype "passive"))
      (node (ref "LED387") (pin "A") (pinfunction "A_A") (pintype "passive"))
      (node (ref "LED388") (pin "A") (pinfunction "A_A") (pintype "passive"))
      (node (ref "LED389") (pin "A") (pinfunction "A_A") (pintype "passive"))
      (node (ref "LED390") (pin "A") (pinfunction "A_A") (pintype "passive"))
      (node (ref "LED391") (pin "A") (pinfunction "A_A") (pintype "passive"))
      (node (ref "LED392") (pin "A") (pinfunction "A_A") (pintype "passive"))
      (node (ref "LED393") (pin "A") (pinfunction "A_A") (pintype "passive"))
      (node (ref "LED394") (pin "A") (pinfunction "A_A") (pintype "passive"))
      (node (ref "LED395") (pin "A") (pinfunction "A_A") (pintype "passive"))
      (node (ref "LED396") (pin "A") (pinfunction "A_A") (pintype "passive"))
      (node (ref "LED397") (pin "A") (pinfunction "A_A") (pintype "passive"))
      (node (ref "LED398") (pin "A") (pinfunction "A_A") (pintype "passive"))
      (node (ref "LED399") (pin "A") (pinfunction "A_A") (pintype "passive"))
      (node (ref "LED400") (pin "A") (pinfunction "A_A") (pintype "passive"))
    )
    (net (code "44") (name "Net-(IC5A-QA)") (class "Default")
      (node (ref "IC5") (pin "3") (pinfunction "QA_3") (pintype "output"))
      (node (ref "LED369") (pin "A") (pinfunction "A_A") (pintype "passive"))
      (node (ref "LED370") (pin "A") (pinfunction "A_A") (pintype "passive"))
      (node (ref "LED371") (pin "A") (pinfunction "A_A") (pintype "passive"))
      (node (ref "LED372") (pin "A") (pinfunction "A_A") (pintype "passive"))
      (node (ref "LED373") (pin "A") (pinfunction "A_A") (pintype "passive"))
      (node (ref "LED374") (pin "A") (pinfunction "A_A") (pintype "passive"))
      (node (ref "LED375") (pin "A") (pinfunction "A_A") (pintype "passive"))
      (node (ref "LED376") (pin "A") (pinfunction "A_A") (pintype "passive"))
      (node (ref "LED377") (pin "A") (pinfunction "A_A") (pintype "passive"))
      (node (ref "LED378") (pin "A") (pinfunction "A_A") (pintype "passive"))
      (node (ref "LED379") (pin "A") (pinfunction "A_A") (pintype "passive"))
      (node (ref "LED380") (pin "A") (pinfunction "A_A") (pintype "passive"))
      (node (ref "LED381") (pin "A") (pinfunction "A_A") (pintype "passive"))
      (node (ref "LED382") (pin "A") (pinfunction "A_A") (pintype "passive"))
      (node (ref "LED383") (pin "A") (pinfunction "A_A") (pintype "passive"))
      (node (ref "LED384") (pin "A") (pinfunction "A_A") (pintype "passive"))
    )
    (net (code "45") (name "Net-(IC5A-QB)") (class "Default")
      (node (ref "IC5") (pin "4") (pinfunction "QB_4") (pintype "output"))
      (node (ref "LED353") (pin "A") (pinfunction "A_A") (pintype "passive"))
      (node (ref "LED354") (pin "A") (pinfunction "A_A") (pintype "passive"))
      (node (ref "LED355") (pin "A") (pinfunction "A_A") (pintype "passive"))
      (node (ref "LED356") (pin "A") (pinfunction "A_A") (pintype "passive"))
      (node (ref "LED357") (pin "A") (pinfunction "A_A") (pintype "passive"))
      (node (ref "LED358") (pin "A") (pinfunction "A_A") (pintype "passive"))
      (node (ref "LED359") (pin "A") (pinfunction "A_A") (pintype "passive"))
      (node (ref "LED360") (pin "A") (pinfunction "A_A") (pintype "passive"))
      (node (ref "LED361") (pin "A") (pinfunction "A_A") (pintype "passive"))
      (node (ref "LED362") (pin "A") (pinfunction "A_A") (pintype "passive"))
      (node (ref "LED363") (pin "A") (pinfunction "A_A") (pintype "passive"))
      (node (ref "LED364") (pin "A") (pinfunction "A_A") (pintype "passive"))
      (node (ref "LED365") (pin "A") (pinfunction "A_A") (pintype "passive"))
      (node (ref "LED366") (pin "A") (pinfunction "A_A") (pintype "passive"))
      (node (ref "LED367") (pin "A") (pinfunction "A_A") (pintype "passive"))
      (node (ref "LED368") (pin "A") (pinfunction "A_A") (pintype "passive"))
    )
    (net (code "46") (name "Net-(IC5A-QC)") (class "Default")
      (node (ref "IC5") (pin "5") (pinfunction "QC_5") (pintype "output"))
      (node (ref "LED337") (pin "A") (pinfunction "A_A") (pintype "passive"))
      (node (ref "LED338") (pin "A") (pinfunction "A_A") (pintype "passive"))
      (node (ref "LED339") (pin "A") (pinfunction "A_A") (pintype "passive"))
      (node (ref "LED340") (pin "A") (pinfunction "A_A") (pintype "passive"))
      (node (ref "LED341") (pin "A") (pinfunction "A_A") (pintype "passive"))
      (node (ref "LED342") (pin "A") (pinfunction "A_A") (pintype "passive"))
      (node (ref "LED343") (pin "A") (pinfunction "A_A") (pintype "passive"))
      (node (ref "LED344") (pin "A") (pinfunction "A_A") (pintype "passive"))
      (node (ref "LED345") (pin "A") (pinfunction "A_A") (pintype "passive"))
      (node (ref "LED346") (pin "A") (pinfunction "A_A") (pintype "passive"))
      (node (ref "LED347") (pin "A") (pinfunction "A_A") (pintype "passive"))
      (node (ref "LED348") (pin "A") (pinfunction "A_A") (pintype "passive"))
      (node (ref "LED349") (pin "A") (pinfunction "A_A") (pintype "passive"))
      (node (ref "LED350") (pin "A") (pinfunction "A_A") (pintype "passive"))
      (node (ref "LED351") (pin "A") (pinfunction "A_A") (pintype "passive"))
      (node (ref "LED352") (pin "A") (pinfunction "A_A") (pintype "passive"))
    )
    (net (code "47") (name "Net-(IC5A-QD)") (class "Default")
      (node (ref "IC5") (pin "6") (pinfunction "QD_6") (pintype "output"))
      (node (ref "LED321") (pin "A") (pinfunction "A_A") (pintype "passive"))
      (node (ref "LED322") (pin "A") (pinfunction "A_A") (pintype "passive"))
      (node (ref "LED323") (pin "A") (pinfunction "A_A") (pintype "passive"))
      (node (ref "LED324") (pin "A") (pinfunction "A_A") (pintype "passive"))
      (node (ref "LED325") (pin "A") (pinfunction "A_A") (pintype "passive"))
      (node (ref "LED326") (pin "A") (pinfunction "A_A") (pintype "passive"))
      (node (ref "LED327") (pin "A") (pinfunction "A_A") (pintype "passive"))
      (node (ref "LED328") (pin "A") (pinfunction "A_A") (pintype "passive"))
      (node (ref "LED329") (pin "A") (pinfunction "A_A") (pintype "passive"))
      (node (ref "LED330") (pin "A") (pinfunction "A_A") (pintype "passive"))
      (node (ref "LED331") (pin "A") (pinfunction "A_A") (pintype "passive"))
      (node (ref "LED332") (pin "A") (pinfunction "A_A") (pintype "passive"))
      (node (ref "LED333") (pin "A") (pinfunction "A_A") (pintype "passive"))
      (node (ref "LED334") (pin "A") (pinfunction "A_A") (pintype "passive"))
      (node (ref "LED335") (pin "A") (pinfunction "A_A") (pintype "passive"))
      (node (ref "LED336") (pin "A") (pinfunction "A_A") (pintype "passive"))
    )
    (net (code "48") (name "Net-(IC5A-QE)") (class "Default")
      (node (ref "IC5") (pin "10") (pinfunction "QE_10") (pintype "output"))
      (node (ref "LED305") (pin "A") (pinfunction "A_A") (pintype "passive"))
      (node (ref "LED306") (pin "A") (pinfunction "A_A") (pintype "passive"))
      (node (ref "LED307") (pin "A") (pinfunction "A_A") (pintype "passive"))
      (node (ref "LED308") (pin "A") (pinfunction "A_A") (pintype "passive"))
      (node (ref "LED309") (pin "A") (pinfunction "A_A") (pintype "passive"))
      (node (ref "LED310") (pin "A") (pinfunction "A_A") (pintype "passive"))
      (node (ref "LED311") (pin "A") (pinfunction "A_A") (pintype "passive"))
      (node (ref "LED312") (pin "A") (pinfunction "A_A") (pintype "passive"))
      (node (ref "LED313") (pin "A") (pinfunction "A_A") (pintype "passive"))
      (node (ref "LED314") (pin "A") (pinfunction "A_A") (pintype "passive"))
      (node (ref "LED315") (pin "A") (pinfunction "A_A") (pintype "passive"))
      (node (ref "LED316") (pin "A") (pinfunction "A_A") (pintype "passive"))
      (node (ref "LED317") (pin "A") (pinfunction "A_A") (pintype "passive"))
      (node (ref "LED318") (pin "A") (pinfunction "A_A") (pintype "passive"))
      (node (ref "LED319") (pin "A") (pinfunction "A_A") (pintype "passive"))
      (node (ref "LED320") (pin "A") (pinfunction "A_A") (pintype "passive"))
    )
    (net (code "49") (name "Net-(IC5A-QF)") (class "Default")
      (node (ref "IC5") (pin "11") (pinfunction "QF_11") (pintype "output"))
      (node (ref "LED289") (pin "A") (pinfunction "A_A") (pintype "passive"))
      (node (ref "LED290") (pin "A") (pinfunction "A_A") (pintype "passive"))
      (node (ref "LED291") (pin "A") (pinfunction "A_A") (pintype "passive"))
      (node (ref "LED292") (pin "A") (pinfunction "A_A") (pintype "passive"))
      (node (ref "LED293") (pin "A") (pinfunction "A_A") (pintype "passive"))
      (node (ref "LED294") (pin "A") (pinfunction "A_A") (pintype "passive"))
      (node (ref "LED295") (pin "A") (pinfunction "A_A") (pintype "passive"))
      (node (ref "LED296") (pin "A") (pinfunction "A_A") (pintype "passive"))
      (node (ref "LED297") (pin "A") (pinfunction "A_A") (pintype "passive"))
      (node (ref "LED298") (pin "A") (pinfunction "A_A") (pintype "passive"))
      (node (ref "LED299") (pin "A") (pinfunction "A_A") (pintype "passive"))
      (node (ref "LED300") (pin "A") (pinfunction "A_A") (pintype "passive"))
      (node (ref "LED301") (pin "A") (pinfunction "A_A") (pintype "passive"))
      (node (ref "LED302") (pin "A") (pinfunction "A_A") (pintype "passive"))
      (node (ref "LED303") (pin "A") (pinfunction "A_A") (pintype "passive"))
      (node (ref "LED304") (pin "A") (pinfunction "A_A") (pintype "passive"))
    )
    (net (code "50") (name "Net-(IC5A-QG)") (class "Default")
      (node (ref "IC5") (pin "12") (pinfunction "QG_12") (pintype "output"))
      (node (ref "LED273") (pin "A") (pinfunction "A_A") (pintype "passive"))
      (node (ref "LED274") (pin "A") (pinfunction "A_A") (pintype "passive"))
      (node (ref "LED275") (pin "A") (pinfunction "A_A") (pintype "passive"))
      (node (ref "LED276") (pin "A") (pinfunction "A_A") (pintype "passive"))
      (node (ref "LED277") (pin "A") (pinfunction "A_A") (pintype "passive"))
      (node (ref "LED278") (pin "A") (pinfunction "A_A") (pintype "passive"))
      (node (ref "LED279") (pin "A") (pinfunction "A_A") (pintype "passive"))
      (node (ref "LED280") (pin "A") (pinfunction "A_A") (pintype "passive"))
      (node (ref "LED281") (pin "A") (pinfunction "A_A") (pintype "passive"))
      (node (ref "LED282") (pin "A") (pinfunction "A_A") (pintype "passive"))
      (node (ref "LED283") (pin "A") (pinfunction "A_A") (pintype "passive"))
      (node (ref "LED284") (pin "A") (pinfunction "A_A") (pintype "passive"))
      (node (ref "LED285") (pin "A") (pinfunction "A_A") (pintype "passive"))
      (node (ref "LED286") (pin "A") (pinfunction "A_A") (pintype "passive"))
      (node (ref "LED287") (pin "A") (pinfunction "A_A") (pintype "passive"))
      (node (ref "LED288") (pin "A") (pinfunction "A_A") (pintype "passive"))
    )
    (net (code "51") (name "Net-(IC6A-A)") (class "Default")
      (node (ref "IC6") (pin "1") (pinfunction "A_1") (pintype "input"))
      (node (ref "IC6") (pin "2") (pinfunction "B_2") (pintype "input"))
      (node (ref "IC7") (pin "13") (pinfunction "QH_13") (pintype "output"))
      (node (ref "LED513") (pin "A") (pinfunction "A_A") (pintype "passive"))
      (node (ref "LED514") (pin "A") (pinfunction "A_A") (pintype "passive"))
      (node (ref "LED515") (pin "A") (pinfunction "A_A") (pintype "passive"))
      (node (ref "LED516") (pin "A") (pinfunction "A_A") (pintype "passive"))
      (node (ref "LED517") (pin "A") (pinfunction "A_A") (pintype "passive"))
      (node (ref "LED518") (pin "A") (pinfunction "A_A") (pintype "passive"))
      (node (ref "LED519") (pin "A") (pinfunction "A_A") (pintype "passive"))
      (node (ref "LED520") (pin "A") (pinfunction "A_A") (pintype "passive"))
      (node (ref "LED521") (pin "A") (pinfunction "A_A") (pintype "passive"))
      (node (ref "LED522") (pin "A") (pinfunction "A_A") (pintype "passive"))
      (node (ref "LED523") (pin "A") (pinfunction "A_A") (pintype "passive"))
      (node (ref "LED524") (pin "A") (pinfunction "A_A") (pintype "passive"))
      (node (ref "LED525") (pin "A") (pinfunction "A_A") (pintype "passive"))
      (node (ref "LED526") (pin "A") (pinfunction "A_A") (pintype "passive"))
      (node (ref "LED527") (pin "A") (pinfunction "A_A") (pintype "passive"))
      (node (ref "LED528") (pin "A") (pinfunction "A_A") (pintype "passive"))
    )
    (net (code "52") (name "Net-(IC6A-QA)") (class "Default")
      (node (ref "IC6") (pin "3") (pinfunction "QA_3") (pintype "output"))
      (node (ref "LED497") (pin "A") (pinfunction "A_A") (pintype "passive"))
      (node (ref "LED498") (pin "A") (pinfunction "A_A") (pintype "passive"))
      (node (ref "LED499") (pin "A") (pinfunction "A_A") (pintype "passive"))
      (node (ref "LED500") (pin "A") (pinfunction "A_A") (pintype "passive"))
      (node (ref "LED501") (pin "A") (pinfunction "A_A") (pintype "passive"))
      (node (ref "LED502") (pin "A") (pinfunction "A_A") (pintype "passive"))
      (node (ref "LED503") (pin "A") (pinfunction "A_A") (pintype "passive"))
      (node (ref "LED504") (pin "A") (pinfunction "A_A") (pintype "passive"))
      (node (ref "LED505") (pin "A") (pinfunction "A_A") (pintype "passive"))
      (node (ref "LED506") (pin "A") (pinfunction "A_A") (pintype "passive"))
      (node (ref "LED507") (pin "A") (pinfunction "A_A") (pintype "passive"))
      (node (ref "LED508") (pin "A") (pinfunction "A_A") (pintype "passive"))
      (node (ref "LED509") (pin "A") (pinfunction "A_A") (pintype "passive"))
      (node (ref "LED510") (pin "A") (pinfunction "A_A") (pintype "passive"))
      (node (ref "LED511") (pin "A") (pinfunction "A_A") (pintype "passive"))
      (node (ref "LED512") (pin "A") (pinfunction "A_A") (pintype "passive"))
    )
    (net (code "53") (name "Net-(IC6A-QB)") (class "Default")
      (node (ref "IC6") (pin "4") (pinfunction "QB_4") (pintype "output"))
      (node (ref "LED481") (pin "A") (pinfunction "A_A") (pintype "passive"))
      (node (ref "LED482") (pin "A") (pinfunction "A_A") (pintype "passive"))
      (node (ref "LED483") (pin "A") (pinfunction "A_A") (pintype "passive"))
      (node (ref "LED484") (pin "A") (pinfunction "A_A") (pintype "passive"))
      (node (ref "LED485") (pin "A") (pinfunction "A_A") (pintype "passive"))
      (node (ref "LED486") (pin "A") (pinfunction "A_A") (pintype "passive"))
      (node (ref "LED487") (pin "A") (pinfunction "A_A") (pintype "passive"))
      (node (ref "LED488") (pin "A") (pinfunction "A_A") (pintype "passive"))
      (node (ref "LED489") (pin "A") (pinfunction "A_A") (pintype "passive"))
      (node (ref "LED490") (pin "A") (pinfunction "A_A") (pintype "passive"))
      (node (ref "LED491") (pin "A") (pinfunction "A_A") (pintype "passive"))
      (node (ref "LED492") (pin "A") (pinfunction "A_A") (pintype "passive"))
      (node (ref "LED493") (pin "A") (pinfunction "A_A") (pintype "passive"))
      (node (ref "LED494") (pin "A") (pinfunction "A_A") (pintype "passive"))
      (node (ref "LED495") (pin "A") (pinfunction "A_A") (pintype "passive"))
      (node (ref "LED496") (pin "A") (pinfunction "A_A") (pintype "passive"))
    )
    (net (code "54") (name "Net-(IC6A-QC)") (class "Default")
      (node (ref "IC6") (pin "5") (pinfunction "QC_5") (pintype "output"))
      (node (ref "LED465") (pin "A") (pinfunction "A_A") (pintype "passive"))
      (node (ref "LED466") (pin "A") (pinfunction "A_A") (pintype "passive"))
      (node (ref "LED467") (pin "A") (pinfunction "A_A") (pintype "passive"))
      (node (ref "LED468") (pin "A") (pinfunction "A_A") (pintype "passive"))
      (node (ref "LED469") (pin "A") (pinfunction "A_A") (pintype "passive"))
      (node (ref "LED470") (pin "A") (pinfunction "A_A") (pintype "passive"))
      (node (ref "LED471") (pin "A") (pinfunction "A_A") (pintype "passive"))
      (node (ref "LED472") (pin "A") (pinfunction "A_A") (pintype "passive"))
      (node (ref "LED473") (pin "A") (pinfunction "A_A") (pintype "passive"))
      (node (ref "LED474") (pin "A") (pinfunction "A_A") (pintype "passive"))
      (node (ref "LED475") (pin "A") (pinfunction "A_A") (pintype "passive"))
      (node (ref "LED476") (pin "A") (pinfunction "A_A") (pintype "passive"))
      (node (ref "LED477") (pin "A") (pinfunction "A_A") (pintype "passive"))
      (node (ref "LED478") (pin "A") (pinfunction "A_A") (pintype "passive"))
      (node (ref "LED479") (pin "A") (pinfunction "A_A") (pintype "passive"))
      (node (ref "LED480") (pin "A") (pinfunction "A_A") (pintype "passive"))
    )
    (net (code "55") (name "Net-(IC6A-QD)") (class "Default")
      (node (ref "IC6") (pin "6") (pinfunction "QD_6") (pintype "output"))
      (node (ref "LED449") (pin "A") (pinfunction "A_A") (pintype "passive"))
      (node (ref "LED450") (pin "A") (pinfunction "A_A") (pintype "passive"))
      (node (ref "LED451") (pin "A") (pinfunction "A_A") (pintype "passive"))
      (node (ref "LED452") (pin "A") (pinfunction "A_A") (pintype "passive"))
      (node (ref "LED453") (pin "A") (pinfunction "A_A") (pintype "passive"))
      (node (ref "LED454") (pin "A") (pinfunction "A_A") (pintype "passive"))
      (node (ref "LED455") (pin "A") (pinfunction "A_A") (pintype "passive"))
      (node (ref "LED456") (pin "A") (pinfunction "A_A") (pintype "passive"))
      (node (ref "LED457") (pin "A") (pinfunction "A_A") (pintype "passive"))
      (node (ref "LED458") (pin "A") (pinfunction "A_A") (pintype "passive"))
      (node (ref "LED459") (pin "A") (pinfunction "A_A") (pintype "passive"))
      (node (ref "LED460") (pin "A") (pinfunction "A_A") (pintype "passive"))
      (node (ref "LED461") (pin "A") (pinfunction "A_A") (pintype "passive"))
      (node (ref "LED462") (pin "A") (pinfunction "A_A") (pintype "passive"))
      (node (ref "LED463") (pin "A") (pinfunction "A_A") (pintype "passive"))
      (node (ref "LED464") (pin "A") (pinfunction "A_A") (pintype "passive"))
    )
    (net (code "56") (name "Net-(IC6A-QE)") (class "Default")
      (node (ref "IC6") (pin "10") (pinfunction "QE_10") (pintype "output"))
      (node (ref "LED433") (pin "A") (pinfunction "A_A") (pintype "passive"))
      (node (ref "LED434") (pin "A") (pinfunction "A_A") (pintype "passive"))
      (node (ref "LED435") (pin "A") (pinfunction "A_A") (pintype "passive"))
      (node (ref "LED436") (pin "A") (pinfunction "A_A") (pintype "passive"))
      (node (ref "LED437") (pin "A") (pinfunction "A_A") (pintype "passive"))
      (node (ref "LED438") (pin "A") (pinfunction "A_A") (pintype "passive"))
      (node (ref "LED439") (pin "A") (pinfunction "A_A") (pintype "passive"))
      (node (ref "LED440") (pin "A") (pinfunction "A_A") (pintype "passive"))
      (node (ref "LED441") (pin "A") (pinfunction "A_A") (pintype "passive"))
      (node (ref "LED442") (pin "A") (pinfunction "A_A") (pintype "passive"))
      (node (ref "LED443") (pin "A") (pinfunction "A_A") (pintype "passive"))
      (node (ref "LED444") (pin "A") (pinfunction "A_A") (pintype "passive"))
      (node (ref "LED445") (pin "A") (pinfunction "A_A") (pintype "passive"))
      (node (ref "LED446") (pin "A") (pinfunction "A_A") (pintype "passive"))
      (node (ref "LED447") (pin "A") (pinfunction "A_A") (pintype "passive"))
      (node (ref "LED448") (pin "A") (pinfunction "A_A") (pintype "passive"))
    )
    (net (code "57") (name "Net-(IC6A-QF)") (class "Default")
      (node (ref "IC6") (pin "11") (pinfunction "QF_11") (pintype "output"))
      (node (ref "LED417") (pin "A") (pinfunction "A_A") (pintype "passive"))
      (node (ref "LED418") (pin "A") (pinfunction "A_A") (pintype "passive"))
      (node (ref "LED419") (pin "A") (pinfunction "A_A") (pintype "passive"))
      (node (ref "LED420") (pin "A") (pinfunction "A_A") (pintype "passive"))
      (node (ref "LED421") (pin "A") (pinfunction "A_A") (pintype "passive"))
      (node (ref "LED422") (pin "A") (pinfunction "A_A") (pintype "passive"))
      (node (ref "LED423") (pin "A") (pinfunction "A_A") (pintype "passive"))
      (node (ref "LED424") (pin "A") (pinfunction "A_A") (pintype "passive"))
      (node (ref "LED425") (pin "A") (pinfunction "A_A") (pintype "passive"))
      (node (ref "LED426") (pin "A") (pinfunction "A_A") (pintype "passive"))
      (node (ref "LED427") (pin "A") (pinfunction "A_A") (pintype "passive"))
      (node (ref "LED428") (pin "A") (pinfunction "A_A") (pintype "passive"))
      (node (ref "LED429") (pin "A") (pinfunction "A_A") (pintype "passive"))
      (node (ref "LED430") (pin "A") (pinfunction "A_A") (pintype "passive"))
      (node (ref "LED431") (pin "A") (pinfunction "A_A") (pintype "passive"))
      (node (ref "LED432") (pin "A") (pinfunction "A_A") (pintype "passive"))
    )
    (net (code "58") (name "Net-(IC6A-QG)") (class "Default")
      (node (ref "IC6") (pin "12") (pinfunction "QG_12") (pintype "output"))
      (node (ref "LED401") (pin "A") (pinfunction "A_A") (pintype "passive"))
      (node (ref "LED402") (pin "A") (pinfunction "A_A") (pintype "passive"))
      (node (ref "LED403") (pin "A") (pinfunction "A_A") (pintype "passive"))
      (node (ref "LED404") (pin "A") (pinfunction "A_A") (pintype "passive"))
      (node (ref "LED405") (pin "A") (pinfunction "A_A") (pintype "passive"))
      (node (ref "LED406") (pin "A") (pinfunction "A_A") (pintype "passive"))
      (node (ref "LED407") (pin "A") (pinfunction "A_A") (pintype "passive"))
      (node (ref "LED408") (pin "A") (pinfunction "A_A") (pintype "passive"))
      (node (ref "LED409") (pin "A") (pinfunction "A_A") (pintype "passive"))
      (node (ref "LED410") (pin "A") (pinfunction "A_A") (pintype "passive"))
      (node (ref "LED411") (pin "A") (pinfunction "A_A") (pintype "passive"))
      (node (ref "LED412") (pin "A") (pinfunction "A_A") (pintype "passive"))
      (node (ref "LED413") (pin "A") (pinfunction "A_A") (pintype "passive"))
      (node (ref "LED414") (pin "A") (pinfunction "A_A") (pintype "passive"))
      (node (ref "LED415") (pin "A") (pinfunction "A_A") (pintype "passive"))
      (node (ref "LED416") (pin "A") (pinfunction "A_A") (pintype "passive"))
    )
    (net (code "59") (name "Net-(IC7A-A)") (class "Default")
      (node (ref "IC7") (pin "1") (pinfunction "A_1") (pintype "input"))
      (node (ref "IC7") (pin "2") (pinfunction "B_2") (pintype "input"))
      (node (ref "IC8") (pin "13") (pinfunction "QH_13") (pintype "output"))
      (node (ref "LED641") (pin "A") (pinfunction "A_A") (pintype "passive"))
      (node (ref "LED642") (pin "A") (pinfunction "A_A") (pintype "passive"))
      (node (ref "LED643") (pin "A") (pinfunction "A_A") (pintype "passive"))
      (node (ref "LED644") (pin "A") (pinfunction "A_A") (pintype "passive"))
      (node (ref "LED645") (pin "A") (pinfunction "A_A") (pintype "passive"))
      (node (ref "LED646") (pin "A") (pinfunction "A_A") (pintype "passive"))
      (node (ref "LED647") (pin "A") (pinfunction "A_A") (pintype "passive"))
      (node (ref "LED648") (pin "A") (pinfunction "A_A") (pintype "passive"))
      (node (ref "LED649") (pin "A") (pinfunction "A_A") (pintype "passive"))
      (node (ref "LED650") (pin "A") (pinfunction "A_A") (pintype "passive"))
      (node (ref "LED651") (pin "A") (pinfunction "A_A") (pintype "passive"))
      (node (ref "LED652") (pin "A") (pinfunction "A_A") (pintype "passive"))
      (node (ref "LED653") (pin "A") (pinfunction "A_A") (pintype "passive"))
      (node (ref "LED654") (pin "A") (pinfunction "A_A") (pintype "passive"))
      (node (ref "LED655") (pin "A") (pinfunction "A_A") (pintype "passive"))
      (node (ref "LED656") (pin "A") (pinfunction "A_A") (pintype "passive"))
    )
    (net (code "60") (name "Net-(IC7A-QA)") (class "Default")
      (node (ref "IC7") (pin "3") (pinfunction "QA_3") (pintype "output"))
      (node (ref "LED625") (pin "A") (pinfunction "A_A") (pintype "passive"))
      (node (ref "LED626") (pin "A") (pinfunction "A_A") (pintype "passive"))
      (node (ref "LED627") (pin "A") (pinfunction "A_A") (pintype "passive"))
      (node (ref "LED628") (pin "A") (pinfunction "A_A") (pintype "passive"))
      (node (ref "LED629") (pin "A") (pinfunction "A_A") (pintype "passive"))
      (node (ref "LED630") (pin "A") (pinfunction "A_A") (pintype "passive"))
      (node (ref "LED631") (pin "A") (pinfunction "A_A") (pintype "passive"))
      (node (ref "LED632") (pin "A") (pinfunction "A_A") (pintype "passive"))
      (node (ref "LED633") (pin "A") (pinfunction "A_A") (pintype "passive"))
      (node (ref "LED634") (pin "A") (pinfunction "A_A") (pintype "passive"))
      (node (ref "LED635") (pin "A") (pinfunction "A_A") (pintype "passive"))
      (node (ref "LED636") (pin "A") (pinfunction "A_A") (pintype "passive"))
      (node (ref "LED637") (pin "A") (pinfunction "A_A") (pintype "passive"))
      (node (ref "LED638") (pin "A") (pinfunction "A_A") (pintype "passive"))
      (node (ref "LED639") (pin "A") (pinfunction "A_A") (pintype "passive"))
      (node (ref "LED640") (pin "A") (pinfunction "A_A") (pintype "passive"))
    )
    (net (code "61") (name "Net-(IC7A-QB)") (class "Default")
      (node (ref "IC7") (pin "4") (pinfunction "QB_4") (pintype "output"))
      (node (ref "LED609") (pin "A") (pinfunction "A_A") (pintype "passive"))
      (node (ref "LED610") (pin "A") (pinfunction "A_A") (pintype "passive"))
      (node (ref "LED611") (pin "A") (pinfunction "A_A") (pintype "passive"))
      (node (ref "LED612") (pin "A") (pinfunction "A_A") (pintype "passive"))
      (node (ref "LED613") (pin "A") (pinfunction "A_A") (pintype "passive"))
      (node (ref "LED614") (pin "A") (pinfunction "A_A") (pintype "passive"))
      (node (ref "LED615") (pin "A") (pinfunction "A_A") (pintype "passive"))
      (node (ref "LED616") (pin "A") (pinfunction "A_A") (pintype "passive"))
      (node (ref "LED617") (pin "A") (pinfunction "A_A") (pintype "passive"))
      (node (ref "LED618") (pin "A") (pinfunction "A_A") (pintype "passive"))
      (node (ref "LED619") (pin "A") (pinfunction "A_A") (pintype "passive"))
      (node (ref "LED620") (pin "A") (pinfunction "A_A") (pintype "passive"))
      (node (ref "LED621") (pin "A") (pinfunction "A_A") (pintype "passive"))
      (node (ref "LED622") (pin "A") (pinfunction "A_A") (pintype "passive"))
      (node (ref "LED623") (pin "A") (pinfunction "A_A") (pintype "passive"))
      (node (ref "LED624") (pin "A") (pinfunction "A_A") (pintype "passive"))
    )
    (net (code "62") (name "Net-(IC7A-QC)") (class "Default")
      (node (ref "IC7") (pin "5") (pinfunction "QC_5") (pintype "output"))
      (node (ref "LED593") (pin "A") (pinfunction "A_A") (pintype "passive"))
      (node (ref "LED594") (pin "A") (pinfunction "A_A") (pintype "passive"))
      (node (ref "LED595") (pin "A") (pinfunction "A_A") (pintype "passive"))
      (node (ref "LED596") (pin "A") (pinfunction "A_A") (pintype "passive"))
      (node (ref "LED597") (pin "A") (pinfunction "A_A") (pintype "passive"))
      (node (ref "LED598") (pin "A") (pinfunction "A_A") (pintype "passive"))
      (node (ref "LED599") (pin "A") (pinfunction "A_A") (pintype "passive"))
      (node (ref "LED600") (pin "A") (pinfunction "A_A") (pintype "passive"))
      (node (ref "LED601") (pin "A") (pinfunction "A_A") (pintype "passive"))
      (node (ref "LED602") (pin "A") (pinfunction "A_A") (pintype "passive"))
      (node (ref "LED603") (pin "A") (pinfunction "A_A") (pintype "passive"))
      (node (ref "LED604") (pin "A") (pinfunction "A_A") (pintype "passive"))
      (node (ref "LED605") (pin "A") (pinfunction "A_A") (pintype "passive"))
      (node (ref "LED606") (pin "A") (pinfunction "A_A") (pintype "passive"))
      (node (ref "LED607") (pin "A") (pinfunction "A_A") (pintype "passive"))
      (node (ref "LED608") (pin "A") (pinfunction "A_A") (pintype "passive"))
    )
    (net (code "63") (name "Net-(IC7A-QD)") (class "Default")
      (node (ref "IC7") (pin "6") (pinfunction "QD_6") (pintype "output"))
      (node (ref "LED577") (pin "A") (pinfunction "A_A") (pintype "passive"))
      (node (ref "LED578") (pin "A") (pinfunction "A_A") (pintype "passive"))
      (node (ref "LED579") (pin "A") (pinfunction "A_A") (pintype "passive"))
      (node (ref "LED580") (pin "A") (pinfunction "A_A") (pintype "passive"))
      (node (ref "LED581") (pin "A") (pinfunction "A_A") (pintype "passive"))
      (node (ref "LED582") (pin "A") (pinfunction "A_A") (pintype "passive"))
      (node (ref "LED583") (pin "A") (pinfunction "A_A") (pintype "passive"))
      (node (ref "LED584") (pin "A") (pinfunction "A_A") (pintype "passive"))
      (node (ref "LED585") (pin "A") (pinfunction "A_A") (pintype "passive"))
      (node (ref "LED586") (pin "A") (pinfunction "A_A") (pintype "passive"))
      (node (ref "LED587") (pin "A") (pinfunction "A_A") (pintype "passive"))
      (node (ref "LED588") (pin "A") (pinfunction "A_A") (pintype "passive"))
      (node (ref "LED589") (pin "A") (pinfunction "A_A") (pintype "passive"))
      (node (ref "LED590") (pin "A") (pinfunction "A_A") (pintype "passive"))
      (node (ref "LED591") (pin "A") (pinfunction "A_A") (pintype "passive"))
      (node (ref "LED592") (pin "A") (pinfunction "A_A") (pintype "passive"))
    )
    (net (code "64") (name "Net-(IC7A-QE)") (class "Default")
      (node (ref "IC7") (pin "10") (pinfunction "QE_10") (pintype "output"))
      (node (ref "LED561") (pin "A") (pinfunction "A_A") (pintype "passive"))
      (node (ref "LED562") (pin "A") (pinfunction "A_A") (pintype "passive"))
      (node (ref "LED563") (pin "A") (pinfunction "A_A") (pintype "passive"))
      (node (ref "LED564") (pin "A") (pinfunction "A_A") (pintype "passive"))
      (node (ref "LED565") (pin "A") (pinfunction "A_A") (pintype "passive"))
      (node (ref "LED566") (pin "A") (pinfunction "A_A") (pintype "passive"))
      (node (ref "LED567") (pin "A") (pinfunction "A_A") (pintype "passive"))
      (node (ref "LED568") (pin "A") (pinfunction "A_A") (pintype "passive"))
      (node (ref "LED569") (pin "A") (pinfunction "A_A") (pintype "passive"))
      (node (ref "LED570") (pin "A") (pinfunction "A_A") (pintype "passive"))
      (node (ref "LED571") (pin "A") (pinfunction "A_A") (pintype "passive"))
      (node (ref "LED572") (pin "A") (pinfunction "A_A") (pintype "passive"))
      (node (ref "LED573") (pin "A") (pinfunction "A_A") (pintype "passive"))
      (node (ref "LED574") (pin "A") (pinfunction "A_A") (pintype "passive"))
      (node (ref "LED575") (pin "A") (pinfunction "A_A") (pintype "passive"))
      (node (ref "LED576") (pin "A") (pinfunction "A_A") (pintype "passive"))
    )
    (net (code "65") (name "Net-(IC7A-QF)") (class "Default")
      (node (ref "IC7") (pin "11") (pinfunction "QF_11") (pintype "output"))
      (node (ref "LED545") (pin "A") (pinfunction "A_A") (pintype "passive"))
      (node (ref "LED546") (pin "A") (pinfunction "A_A") (pintype "passive"))
      (node (ref "LED547") (pin "A") (pinfunction "A_A") (pintype "passive"))
      (node (ref "LED548") (pin "A") (pinfunction "A_A") (pintype "passive"))
      (node (ref "LED549") (pin "A") (pinfunction "A_A") (pintype "passive"))
      (node (ref "LED550") (pin "A") (pinfunction "A_A") (pintype "passive"))
      (node (ref "LED551") (pin "A") (pinfunction "A_A") (pintype "passive"))
      (node (ref "LED552") (pin "A") (pinfunction "A_A") (pintype "passive"))
      (node (ref "LED553") (pin "A") (pinfunction "A_A") (pintype "passive"))
      (node (ref "LED554") (pin "A") (pinfunction "A_A") (pintype "passive"))
      (node (ref "LED555") (pin "A") (pinfunction "A_A") (pintype "passive"))
      (node (ref "LED556") (pin "A") (pinfunction "A_A") (pintype "passive"))
      (node (ref "LED557") (pin "A") (pinfunction "A_A") (pintype "passive"))
      (node (ref "LED558") (pin "A") (pinfunction "A_A") (pintype "passive"))
      (node (ref "LED559") (pin "A") (pinfunction "A_A") (pintype "passive"))
      (node (ref "LED560") (pin "A") (pinfunction "A_A") (pintype "passive"))
    )
    (net (code "66") (name "Net-(IC7A-QG)") (class "Default")
      (node (ref "IC7") (pin "12") (pinfunction "QG_12") (pintype "output"))
      (node (ref "LED529") (pin "A") (pinfunction "A_A") (pintype "passive"))
      (node (ref "LED530") (pin "A") (pinfunction "A_A") (pintype "passive"))
      (node (ref "LED531") (pin "A") (pinfunction "A_A") (pintype "passive"))
      (node (ref "LED532") (pin "A") (pinfunction "A_A") (pintype "passive"))
      (node (ref "LED533") (pin "A") (pinfunction "A_A") (pintype "passive"))
      (node (ref "LED534") (pin "A") (pinfunction "A_A") (pintype "passive"))
      (node (ref "LED535") (pin "A") (pinfunction "A_A") (pintype "passive"))
      (node (ref "LED536") (pin "A") (pinfunction "A_A") (pintype "passive"))
      (node (ref "LED537") (pin "A") (pinfunction "A_A") (pintype "passive"))
      (node (ref "LED538") (pin "A") (pinfunction "A_A") (pintype "passive"))
      (node (ref "LED539") (pin "A") (pinfunction "A_A") (pintype "passive"))
      (node (ref "LED540") (pin "A") (pinfunction "A_A") (pintype "passive"))
      (node (ref "LED541") (pin "A") (pinfunction "A_A") (pintype "passive"))
      (node (ref "LED542") (pin "A") (pinfunction "A_A") (pintype "passive"))
      (node (ref "LED543") (pin "A") (pinfunction "A_A") (pintype "passive"))
      (node (ref "LED544") (pin "A") (pinfunction "A_A") (pintype "passive"))
    )
    (net (code "67") (name "Net-(IC8A-A)") (class "Default")
      (node (ref "IC8") (pin "1") (pinfunction "A_1") (pintype "input"))
      (node (ref "IC8") (pin "2") (pinfunction "B_2") (pintype "input"))
      (node (ref "IC9") (pin "13") (pinfunction "QH_13") (pintype "output"))
      (node (ref "LED769") (pin "A") (pinfunction "A_A") (pintype "passive"))
      (node (ref "LED770") (pin "A") (pinfunction "A_A") (pintype "passive"))
      (node (ref "LED771") (pin "A") (pinfunction "A_A") (pintype "passive"))
      (node (ref "LED772") (pin "A") (pinfunction "A_A") (pintype "passive"))
      (node (ref "LED773") (pin "A") (pinfunction "A_A") (pintype "passive"))
      (node (ref "LED774") (pin "A") (pinfunction "A_A") (pintype "passive"))
      (node (ref "LED775") (pin "A") (pinfunction "A_A") (pintype "passive"))
      (node (ref "LED776") (pin "A") (pinfunction "A_A") (pintype "passive"))
      (node (ref "LED777") (pin "A") (pinfunction "A_A") (pintype "passive"))
      (node (ref "LED778") (pin "A") (pinfunction "A_A") (pintype "passive"))
      (node (ref "LED779") (pin "A") (pinfunction "A_A") (pintype "passive"))
      (node (ref "LED780") (pin "A") (pinfunction "A_A") (pintype "passive"))
      (node (ref "LED781") (pin "A") (pinfunction "A_A") (pintype "passive"))
      (node (ref "LED782") (pin "A") (pinfunction "A_A") (pintype "passive"))
      (node (ref "LED783") (pin "A") (pinfunction "A_A") (pintype "passive"))
      (node (ref "LED784") (pin "A") (pinfunction "A_A") (pintype "passive"))
    )
    (net (code "68") (name "Net-(IC8A-QA)") (class "Default")
      (node (ref "IC8") (pin "3") (pinfunction "QA_3") (pintype "output"))
      (node (ref "LED753") (pin "A") (pinfunction "A_A") (pintype "passive"))
      (node (ref "LED754") (pin "A") (pinfunction "A_A") (pintype "passive"))
      (node (ref "LED755") (pin "A") (pinfunction "A_A") (pintype "passive"))
      (node (ref "LED756") (pin "A") (pinfunction "A_A") (pintype "passive"))
      (node (ref "LED757") (pin "A") (pinfunction "A_A") (pintype "passive"))
      (node (ref "LED758") (pin "A") (pinfunction "A_A") (pintype "passive"))
      (node (ref "LED759") (pin "A") (pinfunction "A_A") (pintype "passive"))
      (node (ref "LED760") (pin "A") (pinfunction "A_A") (pintype "passive"))
      (node (ref "LED761") (pin "A") (pinfunction "A_A") (pintype "passive"))
      (node (ref "LED762") (pin "A") (pinfunction "A_A") (pintype "passive"))
      (node (ref "LED763") (pin "A") (pinfunction "A_A") (pintype "passive"))
      (node (ref "LED764") (pin "A") (pinfunction "A_A") (pintype "passive"))
      (node (ref "LED765") (pin "A") (pinfunction "A_A") (pintype "passive"))
      (node (ref "LED766") (pin "A") (pinfunction "A_A") (pintype "passive"))
      (node (ref "LED767") (pin "A") (pinfunction "A_A") (pintype "passive"))
      (node (ref "LED768") (pin "A") (pinfunction "A_A") (pintype "passive"))
    )
    (net (code "69") (name "Net-(IC8A-QB)") (class "Default")
      (node (ref "IC8") (pin "4") (pinfunction "QB_4") (pintype "output"))
      (node (ref "LED737") (pin "A") (pinfunction "A_A") (pintype "passive"))
      (node (ref "LED738") (pin "A") (pinfunction "A_A") (pintype "passive"))
      (node (ref "LED739") (pin "A") (pinfunction "A_A") (pintype "passive"))
      (node (ref "LED740") (pin "A") (pinfunction "A_A") (pintype "passive"))
      (node (ref "LED741") (pin "A") (pinfunction "A_A") (pintype "passive"))
      (node (ref "LED742") (pin "A") (pinfunction "A_A") (pintype "passive"))
      (node (ref "LED743") (pin "A") (pinfunction "A_A") (pintype "passive"))
      (node (ref "LED744") (pin "A") (pinfunction "A_A") (pintype "passive"))
      (node (ref "LED745") (pin "A") (pinfunction "A_A") (pintype "passive"))
      (node (ref "LED746") (pin "A") (pinfunction "A_A") (pintype "passive"))
      (node (ref "LED747") (pin "A") (pinfunction "A_A") (pintype "passive"))
      (node (ref "LED748") (pin "A") (pinfunction "A_A") (pintype "passive"))
      (node (ref "LED749") (pin "A") (pinfunction "A_A") (pintype "passive"))
      (node (ref "LED750") (pin "A") (pinfunction "A_A") (pintype "passive"))
      (node (ref "LED751") (pin "A") (pinfunction "A_A") (pintype "passive"))
      (node (ref "LED752") (pin "A") (pinfunction "A_A") (pintype "passive"))
    )
    (net (code "70") (name "Net-(IC8A-QC)") (class "Default")
      (node (ref "IC8") (pin "5") (pinfunction "QC_5") (pintype "output"))
      (node (ref "LED721") (pin "A") (pinfunction "A_A") (pintype "passive"))
      (node (ref "LED722") (pin "A") (pinfunction "A_A") (pintype "passive"))
      (node (ref "LED723") (pin "A") (pinfunction "A_A") (pintype "passive"))
      (node (ref "LED724") (pin "A") (pinfunction "A_A") (pintype "passive"))
      (node (ref "LED725") (pin "A") (pinfunction "A_A") (pintype "passive"))
      (node (ref "LED726") (pin "A") (pinfunction "A_A") (pintype "passive"))
      (node (ref "LED727") (pin "A") (pinfunction "A_A") (pintype "passive"))
      (node (ref "LED728") (pin "A") (pinfunction "A_A") (pintype "passive"))
      (node (ref "LED729") (pin "A") (pinfunction "A_A") (pintype "passive"))
      (node (ref "LED730") (pin "A") (pinfunction "A_A") (pintype "passive"))
      (node (ref "LED731") (pin "A") (pinfunction "A_A") (pintype "passive"))
      (node (ref "LED732") (pin "A") (pinfunction "A_A") (pintype "passive"))
      (node (ref "LED733") (pin "A") (pinfunction "A_A") (pintype "passive"))
      (node (ref "LED734") (pin "A") (pinfunction "A_A") (pintype "passive"))
      (node (ref "LED735") (pin "A") (pinfunction "A_A") (pintype "passive"))
      (node (ref "LED736") (pin "A") (pinfunction "A_A") (pintype "passive"))
    )
    (net (code "71") (name "Net-(IC8A-QD)") (class "Default")
      (node (ref "IC8") (pin "6") (pinfunction "QD_6") (pintype "output"))
      (node (ref "LED705") (pin "A") (pinfunction "A_A") (pintype "passive"))
      (node (ref "LED706") (pin "A") (pinfunction "A_A") (pintype "passive"))
      (node (ref "LED707") (pin "A") (pinfunction "A_A") (pintype "passive"))
      (node (ref "LED708") (pin "A") (pinfunction "A_A") (pintype "passive"))
      (node (ref "LED709") (pin "A") (pinfunction "A_A") (pintype "passive"))
      (node (ref "LED710") (pin "A") (pinfunction "A_A") (pintype "passive"))
      (node (ref "LED711") (pin "A") (pinfunction "A_A") (pintype "passive"))
      (node (ref "LED712") (pin "A") (pinfunction "A_A") (pintype "passive"))
      (node (ref "LED713") (pin "A") (pinfunction "A_A") (pintype "passive"))
      (node (ref "LED714") (pin "A") (pinfunction "A_A") (pintype "passive"))
      (node (ref "LED715") (pin "A") (pinfunction "A_A") (pintype "passive"))
      (node (ref "LED716") (pin "A") (pinfunction "A_A") (pintype "passive"))
      (node (ref "LED717") (pin "A") (pinfunction "A_A") (pintype "passive"))
      (node (ref "LED718") (pin "A") (pinfunction "A_A") (pintype "passive"))
      (node (ref "LED719") (pin "A") (pinfunction "A_A") (pintype "passive"))
      (node (ref "LED720") (pin "A") (pinfunction "A_A") (pintype "passive"))
    )
    (net (code "72") (name "Net-(IC8A-QE)") (class "Default")
      (node (ref "IC8") (pin "10") (pinfunction "QE_10") (pintype "output"))
      (node (ref "LED689") (pin "A") (pinfunction "A_A") (pintype "passive"))
      (node (ref "LED690") (pin "A") (pinfunction "A_A") (pintype "passive"))
      (node (ref "LED691") (pin "A") (pinfunction "A_A") (pintype "passive"))
      (node (ref "LED692") (pin "A") (pinfunction "A_A") (pintype "passive"))
      (node (ref "LED693") (pin "A") (pinfunction "A_A") (pintype "passive"))
      (node (ref "LED694") (pin "A") (pinfunction "A_A") (pintype "passive"))
      (node (ref "LED695") (pin "A") (pinfunction "A_A") (pintype "passive"))
      (node (ref "LED696") (pin "A") (pinfunction "A_A") (pintype "passive"))
      (node (ref "LED697") (pin "A") (pinfunction "A_A") (pintype "passive"))
      (node (ref "LED698") (pin "A") (pinfunction "A_A") (pintype "passive"))
      (node (ref "LED699") (pin "A") (pinfunction "A_A") (pintype "passive"))
      (node (ref "LED700") (pin "A") (pinfunction "A_A") (pintype "passive"))
      (node (ref "LED701") (pin "A") (pinfunction "A_A") (pintype "passive"))
      (node (ref "LED702") (pin "A") (pinfunction "A_A") (pintype "passive"))
      (node (ref "LED703") (pin "A") (pinfunction "A_A") (pintype "passive"))
      (node (ref "LED704") (pin "A") (pinfunction "A_A") (pintype "passive"))
    )
    (net (code "73") (name "Net-(IC8A-QF)") (class "Default")
      (node (ref "IC8") (pin "11") (pinfunction "QF_11") (pintype "output"))
      (node (ref "LED673") (pin "A") (pinfunction "A_A") (pintype "passive"))
      (node (ref "LED674") (pin "A") (pinfunction "A_A") (pintype "passive"))
      (node (ref "LED675") (pin "A") (pinfunction "A_A") (pintype "passive"))
      (node (ref "LED676") (pin "A") (pinfunction "A_A") (pintype "passive"))
      (node (ref "LED677") (pin "A") (pinfunction "A_A") (pintype "passive"))
      (node (ref "LED678") (pin "A") (pinfunction "A_A") (pintype "passive"))
      (node (ref "LED679") (pin "A") (pinfunction "A_A") (pintype "passive"))
      (node (ref "LED680") (pin "A") (pinfunction "A_A") (pintype "passive"))
      (node (ref "LED681") (pin "A") (pinfunction "A_A") (pintype "passive"))
      (node (ref "LED682") (pin "A") (pinfunction "A_A") (pintype "passive"))
      (node (ref "LED683") (pin "A") (pinfunction "A_A") (pintype "passive"))
      (node (ref "LED684") (pin "A") (pinfunction "A_A") (pintype "passive"))
      (node (ref "LED685") (pin "A") (pinfunction "A_A") (pintype "passive"))
      (node (ref "LED686") (pin "A") (pinfunction "A_A") (pintype "passive"))
      (node (ref "LED687") (pin "A") (pinfunction "A_A") (pintype "passive"))
      (node (ref "LED688") (pin "A") (pinfunction "A_A") (pintype "passive"))
    )
    (net (code "74") (name "Net-(IC8A-QG)") (class "Default")
      (node (ref "IC8") (pin "12") (pinfunction "QG_12") (pintype "output"))
      (node (ref "LED657") (pin "A") (pinfunction "A_A") (pintype "passive"))
      (node (ref "LED658") (pin "A") (pinfunction "A_A") (pintype "passive"))
      (node (ref "LED659") (pin "A") (pinfunction "A_A") (pintype "passive"))
      (node (ref "LED660") (pin "A") (pinfunction "A_A") (pintype "passive"))
      (node (ref "LED661") (pin "A") (pinfunction "A_A") (pintype "passive"))
      (node (ref "LED662") (pin "A") (pinfunction "A_A") (pintype "passive"))
      (node (ref "LED663") (pin "A") (pinfunction "A_A") (pintype "passive"))
      (node (ref "LED664") (pin "A") (pinfunction "A_A") (pintype "passive"))
      (node (ref "LED665") (pin "A") (pinfunction "A_A") (pintype "passive"))
      (node (ref "LED666") (pin "A") (pinfunction "A_A") (pintype "passive"))
      (node (ref "LED667") (pin "A") (pinfunction "A_A") (pintype "passive"))
      (node (ref "LED668") (pin "A") (pinfunction "A_A") (pintype "passive"))
      (node (ref "LED669") (pin "A") (pinfunction "A_A") (pintype "passive"))
      (node (ref "LED670") (pin "A") (pinfunction "A_A") (pintype "passive"))
      (node (ref "LED671") (pin "A") (pinfunction "A_A") (pintype "passive"))
      (node (ref "LED672") (pin "A") (pinfunction "A_A") (pintype "passive"))
    )
    (net (code "75") (name "Net-(IC9A-QA)") (class "Default")
      (node (ref "IC9") (pin "3") (pinfunction "QA_3") (pintype "output"))
      (node (ref "LED881") (pin "A") (pinfunction "A_A") (pintype "passive"))
      (node (ref "LED882") (pin "A") (pinfunction "A_A") (pintype "passive"))
      (node (ref "LED883") (pin "A") (pinfunction "A_A") (pintype "passive"))
      (node (ref "LED884") (pin "A") (pinfunction "A_A") (pintype "passive"))
      (node (ref "LED885") (pin "A") (pinfunction "A_A") (pintype "passive"))
      (node (ref "LED886") (pin "A") (pinfunction "A_A") (pintype "passive"))
      (node (ref "LED887") (pin "A") (pinfunction "A_A") (pintype "passive"))
      (node (ref "LED888") (pin "A") (pinfunction "A_A") (pintype "passive"))
      (node (ref "LED889") (pin "A") (pinfunction "A_A") (pintype "passive"))
      (node (ref "LED890") (pin "A") (pinfunction "A_A") (pintype "passive"))
      (node (ref "LED891") (pin "A") (pinfunction "A_A") (pintype "passive"))
      (node (ref "LED892") (pin "A") (pinfunction "A_A") (pintype "passive"))
      (node (ref "LED893") (pin "A") (pinfunction "A_A") (pintype "passive"))
      (node (ref "LED894") (pin "A") (pinfunction "A_A") (pintype "passive"))
      (node (ref "LED895") (pin "A") (pinfunction "A_A") (pintype "passive"))
      (node (ref "LED896") (pin "A") (pinfunction "A_A") (pintype "passive"))
    )
    (net (code "76") (name "Net-(IC9A-QB)") (class "Default")
      (node (ref "IC9") (pin "4") (pinfunction "QB_4") (pintype "output"))
      (node (ref "LED865") (pin "A") (pinfunction "A_A") (pintype "passive"))
      (node (ref "LED866") (pin "A") (pinfunction "A_A") (pintype "passive"))
      (node (ref "LED867") (pin "A") (pinfunction "A_A") (pintype "passive"))
      (node (ref "LED868") (pin "A") (pinfunction "A_A") (pintype "passive"))
      (node (ref "LED869") (pin "A") (pinfunction "A_A") (pintype "passive"))
      (node (ref "LED870") (pin "A") (pinfunction "A_A") (pintype "passive"))
      (node (ref "LED871") (pin "A") (pinfunction "A_A") (pintype "passive"))
      (node (ref "LED872") (pin "A") (pinfunction "A_A") (pintype "passive"))
      (node (ref "LED873") (pin "A") (pinfunction "A_A") (pintype "passive"))
      (node (ref "LED874") (pin "A") (pinfunction "A_A") (pintype "passive"))
      (node (ref "LED875") (pin "A") (pinfunction "A_A") (pintype "passive"))
      (node (ref "LED876") (pin "A") (pinfunction "A_A") (pintype "passive"))
      (node (ref "LED877") (pin "A") (pinfunction "A_A") (pintype "passive"))
      (node (ref "LED878") (pin "A") (pinfunction "A_A") (pintype "passive"))
      (node (ref "LED879") (pin "A") (pinfunction "A_A") (pintype "passive"))
      (node (ref "LED880") (pin "A") (pinfunction "A_A") (pintype "passive"))
    )
    (net (code "77") (name "Net-(IC9A-QC)") (class "Default")
      (node (ref "IC9") (pin "5") (pinfunction "QC_5") (pintype "output"))
      (node (ref "LED849") (pin "A") (pinfunction "A_A") (pintype "passive"))
      (node (ref "LED850") (pin "A") (pinfunction "A_A") (pintype "passive"))
      (node (ref "LED851") (pin "A") (pinfunction "A_A") (pintype "passive"))
      (node (ref "LED852") (pin "A") (pinfunction "A_A") (pintype "passive"))
      (node (ref "LED853") (pin "A") (pinfunction "A_A") (pintype "passive"))
      (node (ref "LED854") (pin "A") (pinfunction "A_A") (pintype "passive"))
      (node (ref "LED855") (pin "A") (pinfunction "A_A") (pintype "passive"))
      (node (ref "LED856") (pin "A") (pinfunction "A_A") (pintype "passive"))
      (node (ref "LED857") (pin "A") (pinfunction "A_A") (pintype "passive"))
      (node (ref "LED858") (pin "A") (pinfunction "A_A") (pintype "passive"))
      (node (ref "LED859") (pin "A") (pinfunction "A_A") (pintype "passive"))
      (node (ref "LED860") (pin "A") (pinfunction "A_A") (pintype "passive"))
      (node (ref "LED861") (pin "A") (pinfunction "A_A") (pintype "passive"))
      (node (ref "LED862") (pin "A") (pinfunction "A_A") (pintype "passive"))
      (node (ref "LED863") (pin "A") (pinfunction "A_A") (pintype "passive"))
      (node (ref "LED864") (pin "A") (pinfunction "A_A") (pintype "passive"))
    )
    (net (code "78") (name "Net-(IC9A-QD)") (class "Default")
      (node (ref "IC9") (pin "6") (pinfunction "QD_6") (pintype "output"))
      (node (ref "LED833") (pin "A") (pinfunction "A_A") (pintype "passive"))
      (node (ref "LED834") (pin "A") (pinfunction "A_A") (pintype "passive"))
      (node (ref "LED835") (pin "A") (pinfunction "A_A") (pintype "passive"))
      (node (ref "LED836") (pin "A") (pinfunction "A_A") (pintype "passive"))
      (node (ref "LED837") (pin "A") (pinfunction "A_A") (pintype "passive"))
      (node (ref "LED838") (pin "A") (pinfunction "A_A") (pintype "passive"))
      (node (ref "LED839") (pin "A") (pinfunction "A_A") (pintype "passive"))
      (node (ref "LED840") (pin "A") (pinfunction "A_A") (pintype "passive"))
      (node (ref "LED841") (pin "A") (pinfunction "A_A") (pintype "passive"))
      (node (ref "LED842") (pin "A") (pinfunction "A_A") (pintype "passive"))
      (node (ref "LED843") (pin "A") (pinfunction "A_A") (pintype "passive"))
      (node (ref "LED844") (pin "A") (pinfunction "A_A") (pintype "passive"))
      (node (ref "LED845") (pin "A") (pinfunction "A_A") (pintype "passive"))
      (node (ref "LED846") (pin "A") (pinfunction "A_A") (pintype "passive"))
      (node (ref "LED847") (pin "A") (pinfunction "A_A") (pintype "passive"))
      (node (ref "LED848") (pin "A") (pinfunction "A_A") (pintype "passive"))
    )
    (net (code "79") (name "Net-(IC9A-QE)") (class "Default")
      (node (ref "IC9") (pin "10") (pinfunction "QE_10") (pintype "output"))
      (node (ref "LED817") (pin "A") (pinfunction "A_A") (pintype "passive"))
      (node (ref "LED818") (pin "A") (pinfunction "A_A") (pintype "passive"))
      (node (ref "LED819") (pin "A") (pinfunction "A_A") (pintype "passive"))
      (node (ref "LED820") (pin "A") (pinfunction "A_A") (pintype "passive"))
      (node (ref "LED821") (pin "A") (pinfunction "A_A") (pintype "passive"))
      (node (ref "LED822") (pin "A") (pinfunction "A_A") (pintype "passive"))
      (node (ref "LED823") (pin "A") (pinfunction "A_A") (pintype "passive"))
      (node (ref "LED824") (pin "A") (pinfunction "A_A") (pintype "passive"))
      (node (ref "LED825") (pin "A") (pinfunction "A_A") (pintype "passive"))
      (node (ref "LED826") (pin "A") (pinfunction "A_A") (pintype "passive"))
      (node (ref "LED827") (pin "A") (pinfunction "A_A") (pintype "passive"))
      (node (ref "LED828") (pin "A") (pinfunction "A_A") (pintype "passive"))
      (node (ref "LED829") (pin "A") (pinfunction "A_A") (pintype "passive"))
      (node (ref "LED830") (pin "A") (pinfunction "A_A") (pintype "passive"))
      (node (ref "LED831") (pin "A") (pinfunction "A_A") (pintype "passive"))
      (node (ref "LED832") (pin "A") (pinfunction "A_A") (pintype "passive"))
    )
    (net (code "80") (name "Net-(IC9A-QF)") (class "Default")
      (node (ref "IC9") (pin "11") (pinfunction "QF_11") (pintype "output"))
      (node (ref "LED801") (pin "A") (pinfunction "A_A") (pintype "passive"))
      (node (ref "LED802") (pin "A") (pinfunction "A_A") (pintype "passive"))
      (node (ref "LED803") (pin "A") (pinfunction "A_A") (pintype "passive"))
      (node (ref "LED804") (pin "A") (pinfunction "A_A") (pintype "passive"))
      (node (ref "LED805") (pin "A") (pinfunction "A_A") (pintype "passive"))
      (node (ref "LED806") (pin "A") (pinfunction "A_A") (pintype "passive"))
      (node (ref "LED807") (pin "A") (pinfunction "A_A") (pintype "passive"))
      (node (ref "LED808") (pin "A") (pinfunction "A_A") (pintype "passive"))
      (node (ref "LED809") (pin "A") (pinfunction "A_A") (pintype "passive"))
      (node (ref "LED810") (pin "A") (pinfunction "A_A") (pintype "passive"))
      (node (ref "LED811") (pin "A") (pinfunction "A_A") (pintype "passive"))
      (node (ref "LED812") (pin "A") (pinfunction "A_A") (pintype "passive"))
      (node (ref "LED813") (pin "A") (pinfunction "A_A") (pintype "passive"))
      (node (ref "LED814") (pin "A") (pinfunction "A_A") (pintype "passive"))
      (node (ref "LED815") (pin "A") (pinfunction "A_A") (pintype "passive"))
      (node (ref "LED816") (pin "A") (pinfunction "A_A") (pintype "passive"))
    )
    (net (code "81") (name "Net-(IC9A-QG)") (class "Default")
      (node (ref "IC9") (pin "12") (pinfunction "QG_12") (pintype "output"))
      (node (ref "LED785") (pin "A") (pinfunction "A_A") (pintype "passive"))
      (node (ref "LED786") (pin "A") (pinfunction "A_A") (pintype "passive"))
      (node (ref "LED787") (pin "A") (pinfunction "A_A") (pintype "passive"))
      (node (ref "LED788") (pin "A") (pinfunction "A_A") (pintype "passive"))
      (node (ref "LED789") (pin "A") (pinfunction "A_A") (pintype "passive"))
      (node (ref "LED790") (pin "A") (pinfunction "A_A") (pintype "passive"))
      (node (ref "LED791") (pin "A") (pinfunction "A_A") (pintype "passive"))
      (node (ref "LED792") (pin "A") (pinfunction "A_A") (pintype "passive"))
      (node (ref "LED793") (pin "A") (pinfunction "A_A") (pintype "passive"))
      (node (ref "LED794") (pin "A") (pinfunction "A_A") (pintype "passive"))
      (node (ref "LED795") (pin "A") (pinfunction "A_A") (pintype "passive"))
      (node (ref "LED796") (pin "A") (pinfunction "A_A") (pintype "passive"))
      (node (ref "LED797") (pin "A") (pinfunction "A_A") (pintype "passive"))
      (node (ref "LED798") (pin "A") (pinfunction "A_A") (pintype "passive"))
      (node (ref "LED799") (pin "A") (pinfunction "A_A") (pintype "passive"))
      (node (ref "LED800") (pin "A") (pinfunction "A_A") (pintype "passive"))
    )
    (net (code "82") (name "Net-(IC10A-A)") (class "Default")
      (node (ref "IC10") (pin "1") (pinfunction "A_1") (pintype "input"))
      (node (ref "IC10") (pin "2") (pinfunction "B_2") (pintype "input"))
      (node (ref "IC11") (pin "13") (pinfunction "QH_13") (pintype "output"))
      (node (ref "LED1025") (pin "A") (pinfunction "A_A") (pintype "passive"))
      (node (ref "LED1026") (pin "A") (pinfunction "A_A") (pintype "passive"))
      (node (ref "LED1027") (pin "A") (pinfunction "A_A") (pintype "passive"))
      (node (ref "LED1028") (pin "A") (pinfunction "A_A") (pintype "passive"))
      (node (ref "LED1029") (pin "A") (pinfunction "A_A") (pintype "passive"))
      (node (ref "LED1030") (pin "A") (pinfunction "A_A") (pintype "passive"))
      (node (ref "LED1031") (pin "A") (pinfunction "A_A") (pintype "passive"))
      (node (ref "LED1032") (pin "A") (pinfunction "A_A") (pintype "passive"))
      (node (ref "LED1033") (pin "A") (pinfunction "A_A") (pintype "passive"))
      (node (ref "LED1034") (pin "A") (pinfunction "A_A") (pintype "passive"))
      (node (ref "LED1035") (pin "A") (pinfunction "A_A") (pintype "passive"))
      (node (ref "LED1036") (pin "A") (pinfunction "A_A") (pintype "passive"))
      (node (ref "LED1037") (pin "A") (pinfunction "A_A") (pintype "passive"))
      (node (ref "LED1038") (pin "A") (pinfunction "A_A") (pintype "passive"))
      (node (ref "LED1039") (pin "A") (pinfunction "A_A") (pintype "passive"))
      (node (ref "LED1040") (pin "A") (pinfunction "A_A") (pintype "passive"))
    )
    (net (code "83") (name "Net-(IC10A-CLK)") (class "Default")
      (node (ref "IC10") (pin "8") (pinfunction "CLK_8") (pintype "input"))
      (node (ref "IC11") (pin "8") (pinfunction "CLK_8") (pintype "input"))
      (node (ref "IC12") (pin "8") (pinfunction "CLK_8") (pintype "input"))
      (node (ref "IC13") (pin "2") (pinfunction "RA0/AN0_2") (pintype "bidirectional"))
      (node (ref "IC3") (pin "8") (pinfunction "CLK_8") (pintype "input"))
      (node (ref "IC4") (pin "8") (pinfunction "CLK_8") (pintype "input"))
      (node (ref "IC5") (pin "8") (pinfunction "CLK_8") (pintype "input"))
      (node (ref "IC6") (pin "8") (pinfunction "CLK_8") (pintype "input"))
      (node (ref "IC7") (pin "8") (pinfunction "CLK_8") (pintype "input"))
      (node (ref "IC8") (pin "8") (pinfunction "CLK_8") (pintype "input"))
      (node (ref "IC9") (pin "8") (pinfunction "CLK_8") (pintype "input"))
    )
    (net (code "84") (name "Net-(IC10A-QA)") (class "Default")
      (node (ref "IC10") (pin "3") (pinfunction "QA_3") (pintype "output"))
      (node (ref "LED1009") (pin "A") (pinfunction "A_A") (pintype "passive"))
      (node (ref "LED1010") (pin "A") (pinfunction "A_A") (pintype "passive"))
      (node (ref "LED1011") (pin "A") (pinfunction "A_A") (pintype "passive"))
      (node (ref "LED1012") (pin "A") (pinfunction "A_A") (pintype "passive"))
      (node (ref "LED1013") (pin "A") (pinfunction "A_A") (pintype "passive"))
      (node (ref "LED1014") (pin "A") (pinfunction "A_A") (pintype "passive"))
      (node (ref "LED1015") (pin "A") (pinfunction "A_A") (pintype "passive"))
      (node (ref "LED1016") (pin "A") (pinfunction "A_A") (pintype "passive"))
      (node (ref "LED1017") (pin "A") (pinfunction "A_A") (pintype "passive"))
      (node (ref "LED1018") (pin "A") (pinfunction "A_A") (pintype "passive"))
      (node (ref "LED1019") (pin "A") (pinfunction "A_A") (pintype "passive"))
      (node (ref "LED1020") (pin "A") (pinfunction "A_A") (pintype "passive"))
      (node (ref "LED1021") (pin "A") (pinfunction "A_A") (pintype "passive"))
      (node (ref "LED1022") (pin "A") (pinfunction "A_A") (pintype "passive"))
      (node (ref "LED1023") (pin "A") (pinfunction "A_A") (pintype "passive"))
      (node (ref "LED1024") (pin "A") (pinfunction "A_A") (pintype "passive"))
    )
    (net (code "85") (name "Net-(IC10A-QB)") (class "Default")
      (node (ref "IC10") (pin "4") (pinfunction "QB_4") (pintype "output"))
      (node (ref "LED1000") (pin "A") (pinfunction "A_A") (pintype "passive"))
      (node (ref "LED1001") (pin "A") (pinfunction "A_A") (pintype "passive"))
      (node (ref "LED1002") (pin "A") (pinfunction "A_A") (pintype "passive"))
      (node (ref "LED1003") (pin "A") (pinfunction "A_A") (pintype "passive"))
      (node (ref "LED1004") (pin "A") (pinfunction "A_A") (pintype "passive"))
      (node (ref "LED1005") (pin "A") (pinfunction "A_A") (pintype "passive"))
      (node (ref "LED1006") (pin "A") (pinfunction "A_A") (pintype "passive"))
      (node (ref "LED1007") (pin "A") (pinfunction "A_A") (pintype "passive"))
      (node (ref "LED1008") (pin "A") (pinfunction "A_A") (pintype "passive"))
      (node (ref "LED993") (pin "A") (pinfunction "A_A") (pintype "passive"))
      (node (ref "LED994") (pin "A") (pinfunction "A_A") (pintype "passive"))
      (node (ref "LED995") (pin "A") (pinfunction "A_A") (pintype "passive"))
      (node (ref "LED996") (pin "A") (pinfunction "A_A") (pintype "passive"))
      (node (ref "LED997") (pin "A") (pinfunction "A_A") (pintype "passive"))
      (node (ref "LED998") (pin "A") (pinfunction "A_A") (pintype "passive"))
      (node (ref "LED999") (pin "A") (pinfunction "A_A") (pintype "passive"))
    )
    (net (code "86") (name "Net-(IC10A-QC)") (class "Default")
      (node (ref "IC10") (pin "5") (pinfunction "QC_5") (pintype "output"))
      (node (ref "LED977") (pin "A") (pinfunction "A_A") (pintype "passive"))
      (node (ref "LED978") (pin "A") (pinfunction "A_A") (pintype "passive"))
      (node (ref "LED979") (pin "A") (pinfunction "A_A") (pintype "passive"))
      (node (ref "LED980") (pin "A") (pinfunction "A_A") (pintype "passive"))
      (node (ref "LED981") (pin "A") (pinfunction "A_A") (pintype "passive"))
      (node (ref "LED982") (pin "A") (pinfunction "A_A") (pintype "passive"))
      (node (ref "LED983") (pin "A") (pinfunction "A_A") (pintype "passive"))
      (node (ref "LED984") (pin "A") (pinfunction "A_A") (pintype "passive"))
      (node (ref "LED985") (pin "A") (pinfunction "A_A") (pintype "passive"))
      (node (ref "LED986") (pin "A") (pinfunction "A_A") (pintype "passive"))
      (node (ref "LED987") (pin "A") (pinfunction "A_A") (pintype "passive"))
      (node (ref "LED988") (pin "A") (pinfunction "A_A") (pintype "passive"))
      (node (ref "LED989") (pin "A") (pinfunction "A_A") (pintype "passive"))
      (node (ref "LED990") (pin "A") (pinfunction "A_A") (pintype "passive"))
      (node (ref "LED991") (pin "A") (pinfunction "A_A") (pintype "passive"))
      (node (ref "LED992") (pin "A") (pinfunction "A_A") (pintype "passive"))
    )
    (net (code "87") (name "Net-(IC10A-QD)") (class "Default")
      (node (ref "IC10") (pin "6") (pinfunction "QD_6") (pintype "output"))
      (node (ref "LED961") (pin "A") (pinfunction "A_A") (pintype "passive"))
      (node (ref "LED962") (pin "A") (pinfunction "A_A") (pintype "passive"))
      (node (ref "LED963") (pin "A") (pinfunction "A_A") (pintype "passive"))
      (node (ref "LED964") (pin "A") (pinfunction "A_A") (pintype "passive"))
      (node (ref "LED965") (pin "A") (pinfunction "A_A") (pintype "passive"))
      (node (ref "LED966") (pin "A") (pinfunction "A_A") (pintype "passive"))
      (node (ref "LED967") (pin "A") (pinfunction "A_A") (pintype "passive"))
      (node (ref "LED968") (pin "A") (pinfunction "A_A") (pintype "passive"))
      (node (ref "LED969") (pin "A") (pinfunction "A_A") (pintype "passive"))
      (node (ref "LED970") (pin "A") (pinfunction "A_A") (pintype "passive"))
      (node (ref "LED971") (pin "A") (pinfunction "A_A") (pintype "passive"))
      (node (ref "LED972") (pin "A") (pinfunction "A_A") (pintype "passive"))
      (node (ref "LED973") (pin "A") (pinfunction "A_A") (pintype "passive"))
      (node (ref "LED974") (pin "A") (pinfunction "A_A") (pintype "passive"))
      (node (ref "LED975") (pin "A") (pinfunction "A_A") (pintype "passive"))
      (node (ref "LED976") (pin "A") (pinfunction "A_A") (pintype "passive"))
    )
    (net (code "88") (name "Net-(IC10A-QE)") (class "Default")
      (node (ref "IC10") (pin "10") (pinfunction "QE_10") (pintype "output"))
      (node (ref "LED945") (pin "A") (pinfunction "A_A") (pintype "passive"))
      (node (ref "LED946") (pin "A") (pinfunction "A_A") (pintype "passive"))
      (node (ref "LED947") (pin "A") (pinfunction "A_A") (pintype "passive"))
      (node (ref "LED948") (pin "A") (pinfunction "A_A") (pintype "passive"))
      (node (ref "LED949") (pin "A") (pinfunction "A_A") (pintype "passive"))
      (node (ref "LED950") (pin "A") (pinfunction "A_A") (pintype "passive"))
      (node (ref "LED951") (pin "A") (pinfunction "A_A") (pintype "passive"))
      (node (ref "LED952") (pin "A") (pinfunction "A_A") (pintype "passive"))
      (node (ref "LED953") (pin "A") (pinfunction "A_A") (pintype "passive"))
      (node (ref "LED954") (pin "A") (pinfunction "A_A") (pintype "passive"))
      (node (ref "LED955") (pin "A") (pinfunction "A_A") (pintype "passive"))
      (node (ref "LED956") (pin "A") (pinfunction "A_A") (pintype "passive"))
      (node (ref "LED957") (pin "A") (pinfunction "A_A") (pintype "passive"))
      (node (ref "LED958") (pin "A") (pinfunction "A_A") (pintype "passive"))
      (node (ref "LED959") (pin "A") (pinfunction "A_A") (pintype "passive"))
      (node (ref "LED960") (pin "A") (pinfunction "A_A") (pintype "passive"))
    )
    (net (code "89") (name "Net-(IC10A-QF)") (class "Default")
      (node (ref "IC10") (pin "11") (pinfunction "QF_11") (pintype "output"))
      (node (ref "LED929") (pin "A") (pinfunction "A_A") (pintype "passive"))
      (node (ref "LED930") (pin "A") (pinfunction "A_A") (pintype "passive"))
      (node (ref "LED931") (pin "A") (pinfunction "A_A") (pintype "passive"))
      (node (ref "LED932") (pin "A") (pinfunction "A_A") (pintype "passive"))
      (node (ref "LED933") (pin "A") (pinfunction "A_A") (pintype "passive"))
      (node (ref "LED934") (pin "A") (pinfunction "A_A") (pintype "passive"))
      (node (ref "LED935") (pin "A") (pinfunction "A_A") (pintype "passive"))
      (node (ref "LED936") (pin "A") (pinfunction "A_A") (pintype "passive"))
      (node (ref "LED937") (pin "A") (pinfunction "A_A") (pintype "passive"))
      (node (ref "LED938") (pin "A") (pinfunction "A_A") (pintype "passive"))
      (node (ref "LED939") (pin "A") (pinfunction "A_A") (pintype "passive"))
      (node (ref "LED940") (pin "A") (pinfunction "A_A") (pintype "passive"))
      (node (ref "LED941") (pin "A") (pinfunction "A_A") (pintype "passive"))
      (node (ref "LED942") (pin "A") (pinfunction "A_A") (pintype "passive"))
      (node (ref "LED943") (pin "A") (pinfunction "A_A") (pintype "passive"))
      (node (ref "LED944") (pin "A") (pinfunction "A_A") (pintype "passive"))
    )
    (net (code "90") (name "Net-(IC10A-QG)") (class "Default")
      (node (ref "IC10") (pin "12") (pinfunction "QG_12") (pintype "output"))
      (node (ref "LED913") (pin "A") (pinfunction "A_A") (pintype "passive"))
      (node (ref "LED914") (pin "A") (pinfunction "A_A") (pintype "passive"))
      (node (ref "LED915") (pin "A") (pinfunction "A_A") (pintype "passive"))
      (node (ref "LED916") (pin "A") (pinfunction "A_A") (pintype "passive"))
      (node (ref "LED917") (pin "A") (pinfunction "A_A") (pintype "passive"))
      (node (ref "LED918") (pin "A") (pinfunction "A_A") (pintype "passive"))
      (node (ref "LED919") (pin "A") (pinfunction "A_A") (pintype "passive"))
      (node (ref "LED920") (pin "A") (pinfunction "A_A") (pintype "passive"))
      (node (ref "LED921") (pin "A") (pinfunction "A_A") (pintype "passive"))
      (node (ref "LED922") (pin "A") (pinfunction "A_A") (pintype "passive"))
      (node (ref "LED923") (pin "A") (pinfunction "A_A") (pintype "passive"))
      (node (ref "LED924") (pin "A") (pinfunction "A_A") (pintype "passive"))
      (node (ref "LED925") (pin "A") (pinfunction "A_A") (pintype "passive"))
      (node (ref "LED926") (pin "A") (pinfunction "A_A") (pintype "passive"))
      (node (ref "LED927") (pin "A") (pinfunction "A_A") (pintype "passive"))
      (node (ref "LED928") (pin "A") (pinfunction "A_A") (pintype "passive"))
    )
    (net (code "91") (name "Net-(IC10A-QH)") (class "Default")
      (node (ref "IC10") (pin "13") (pinfunction "QH_13") (pintype "output"))
      (node (ref "IC9") (pin "1") (pinfunction "A_1") (pintype "input"))
      (node (ref "IC9") (pin "2") (pinfunction "B_2") (pintype "input"))
      (node (ref "LED897") (pin "A") (pinfunction "A_A") (pintype "passive"))
      (node (ref "LED898") (pin "A") (pinfunction "A_A") (pintype "passive"))
      (node (ref "LED899") (pin "A") (pinfunction "A_A") (pintype "passive"))
      (node (ref "LED900") (pin "A") (pinfunction "A_A") (pintype "passive"))
      (node (ref "LED901") (pin "A") (pinfunction "A_A") (pintype "passive"))
      (node (ref "LED902") (pin "A") (pinfunction "A_A") (pintype "passive"))
      (node (ref "LED903") (pin "A") (pinfunction "A_A") (pintype "passive"))
      (node (ref "LED904") (pin "A") (pinfunction "A_A") (pintype "passive"))
      (node (ref "LED905") (pin "A") (pinfunction "A_A") (pintype "passive"))
      (node (ref "LED906") (pin "A") (pinfunction "A_A") (pintype "passive"))
      (node (ref "LED907") (pin "A") (pinfunction "A_A") (pintype "passive"))
      (node (ref "LED908") (pin "A") (pinfunction "A_A") (pintype "passive"))
      (node (ref "LED909") (pin "A") (pinfunction "A_A") (pintype "passive"))
      (node (ref "LED910") (pin "A") (pinfunction "A_A") (pintype "passive"))
      (node (ref "LED911") (pin "A") (pinfunction "A_A") (pintype "passive"))
      (node (ref "LED912") (pin "A") (pinfunction "A_A") (pintype "passive"))
    )
    (net (code "92") (name "Net-(IC11A-A)") (class "Default")
      (node (ref "IC11") (pin "1") (pinfunction "A_1") (pintype "input"))
      (node (ref "IC11") (pin "2") (pinfunction "B_2") (pintype "input"))
      (node (ref "IC12") (pin "13") (pinfunction "QH_13") (pintype "output"))
      (node (ref "LED1153") (pin "A") (pinfunction "A_A") (pintype "passive"))
      (node (ref "LED1154") (pin "A") (pinfunction "A_A") (pintype "passive"))
      (node (ref "LED1155") (pin "A") (pinfunction "A_A") (pintype "passive"))
      (node (ref "LED1156") (pin "A") (pinfunction "A_A") (pintype "passive"))
      (node (ref "LED1157") (pin "A") (pinfunction "A_A") (pintype "passive"))
      (node (ref "LED1158") (pin "A") (pinfunction "A_A") (pintype "passive"))
      (node (ref "LED1159") (pin "A") (pinfunction "A_A") (pintype "passive"))
      (node (ref "LED1160") (pin "A") (pinfunction "A_A") (pintype "passive"))
      (node (ref "LED1161") (pin "A") (pinfunction "A_A") (pintype "passive"))
      (node (ref "LED1162") (pin "A") (pinfunction "A_A") (pintype "passive"))
      (node (ref "LED1163") (pin "A") (pinfunction "A_A") (pintype "passive"))
      (node (ref "LED1164") (pin "A") (pinfunction "A_A") (pintype "passive"))
      (node (ref "LED1165") (pin "A") (pinfunction "A_A") (pintype "passive"))
      (node (ref "LED1166") (pin "A") (pinfunction "A_A") (pintype "passive"))
      (node (ref "LED1167") (pin "A") (pinfunction "A_A") (pintype "passive"))
      (node (ref "LED1168") (pin "A") (pinfunction "A_A") (pintype "passive"))
    )
    (net (code "93") (name "Net-(IC11A-QA)") (class "Default")
      (node (ref "IC11") (pin "3") (pinfunction "QA_3") (pintype "output"))
      (node (ref "LED1137") (pin "A") (pinfunction "A_A") (pintype "passive"))
      (node (ref "LED1138") (pin "A") (pinfunction "A_A") (pintype "passive"))
      (node (ref "LED1139") (pin "A") (pinfunction "A_A") (pintype "passive"))
      (node (ref "LED1140") (pin "A") (pinfunction "A_A") (pintype "passive"))
      (node (ref "LED1141") (pin "A") (pinfunction "A_A") (pintype "passive"))
      (node (ref "LED1142") (pin "A") (pinfunction "A_A") (pintype "passive"))
      (node (ref "LED1143") (pin "A") (pinfunction "A_A") (pintype "passive"))
      (node (ref "LED1144") (pin "A") (pinfunction "A_A") (pintype "passive"))
      (node (ref "LED1145") (pin "A") (pinfunction "A_A") (pintype "passive"))
      (node (ref "LED1146") (pin "A") (pinfunction "A_A") (pintype "passive"))
      (node (ref "LED1147") (pin "A") (pinfunction "A_A") (pintype "passive"))
      (node (ref "LED1148") (pin "A") (pinfunction "A_A") (pintype "passive"))
      (node (ref "LED1149") (pin "A") (pinfunction "A_A") (pintype "passive"))
      (node (ref "LED1150") (pin "A") (pinfunction "A_A") (pintype "passive"))
      (node (ref "LED1151") (pin "A") (pinfunction "A_A") (pintype "passive"))
      (node (ref "LED1152") (pin "A") (pinfunction "A_A") (pintype "passive"))
    )
    (net (code "94") (name "Net-(IC11A-QB)") (class "Default")
      (node (ref "IC11") (pin "4") (pinfunction "QB_4") (pintype "output"))
      (node (ref "LED1121") (pin "A") (pinfunction "A_A") (pintype "passive"))
      (node (ref "LED1122") (pin "A") (pinfunction "A_A") (pintype "passive"))
      (node (ref "LED1123") (pin "A") (pinfunction "A_A") (pintype "passive"))
      (node (ref "LED1124") (pin "A") (pinfunction "A_A") (pintype "passive"))
      (node (ref "LED1125") (pin "A") (pinfunction "A_A") (pintype "passive"))
      (node (ref "LED1126") (pin "A") (pinfunction "A_A") (pintype "passive"))
      (node (ref "LED1127") (pin "A") (pinfunction "A_A") (pintype "passive"))
      (node (ref "LED1128") (pin "A") (pinfunction "A_A") (pintype "passive"))
      (node (ref "LED1129") (pin "A") (pinfunction "A_A") (pintype "passive"))
      (node (ref "LED1130") (pin "A") (pinfunction "A_A") (pintype "passive"))
      (node (ref "LED1131") (pin "A") (pinfunction "A_A") (pintype "passive"))
      (node (ref "LED1132") (pin "A") (pinfunction "A_A") (pintype "passive"))
      (node (ref "LED1133") (pin "A") (pinfunction "A_A") (pintype "passive"))
      (node (ref "LED1134") (pin "A") (pinfunction "A_A") (pintype "passive"))
      (node (ref "LED1135") (pin "A") (pinfunction "A_A") (pintype "passive"))
      (node (ref "LED1136") (pin "A") (pinfunction "A_A") (pintype "passive"))
    )
    (net (code "95") (name "Net-(IC11A-QC)") (class "Default")
      (node (ref "IC11") (pin "5") (pinfunction "QC_5") (pintype "output"))
      (node (ref "LED1105") (pin "A") (pinfunction "A_A") (pintype "passive"))
      (node (ref "LED1106") (pin "A") (pinfunction "A_A") (pintype "passive"))
      (node (ref "LED1107") (pin "A") (pinfunction "A_A") (pintype "passive"))
      (node (ref "LED1108") (pin "A") (pinfunction "A_A") (pintype "passive"))
      (node (ref "LED1109") (pin "A") (pinfunction "A_A") (pintype "passive"))
      (node (ref "LED1110") (pin "A") (pinfunction "A_A") (pintype "passive"))
      (node (ref "LED1111") (pin "A") (pinfunction "A_A") (pintype "passive"))
      (node (ref "LED1112") (pin "A") (pinfunction "A_A") (pintype "passive"))
      (node (ref "LED1113") (pin "A") (pinfunction "A_A") (pintype "passive"))
      (node (ref "LED1114") (pin "A") (pinfunction "A_A") (pintype "passive"))
      (node (ref "LED1115") (pin "A") (pinfunction "A_A") (pintype "passive"))
      (node (ref "LED1116") (pin "A") (pinfunction "A_A") (pintype "passive"))
      (node (ref "LED1117") (pin "A") (pinfunction "A_A") (pintype "passive"))
      (node (ref "LED1118") (pin "A") (pinfunction "A_A") (pintype "passive"))
      (node (ref "LED1119") (pin "A") (pinfunction "A_A") (pintype "passive"))
      (node (ref "LED1120") (pin "A") (pinfunction "A_A") (pintype "passive"))
    )
    (net (code "96") (name "Net-(IC11A-QD)") (class "Default")
      (node (ref "IC11") (pin "6") (pinfunction "QD_6") (pintype "output"))
      (node (ref "LED1089") (pin "A") (pinfunction "A_A") (pintype "passive"))
      (node (ref "LED1090") (pin "A") (pinfunction "A_A") (pintype "passive"))
      (node (ref "LED1091") (pin "A") (pinfunction "A_A") (pintype "passive"))
      (node (ref "LED1092") (pin "A") (pinfunction "A_A") (pintype "passive"))
      (node (ref "LED1093") (pin "A") (pinfunction "A_A") (pintype "passive"))
      (node (ref "LED1094") (pin "A") (pinfunction "A_A") (pintype "passive"))
      (node (ref "LED1095") (pin "A") (pinfunction "A_A") (pintype "passive"))
      (node (ref "LED1096") (pin "A") (pinfunction "A_A") (pintype "passive"))
      (node (ref "LED1097") (pin "A") (pinfunction "A_A") (pintype "passive"))
      (node (ref "LED1098") (pin "A") (pinfunction "A_A") (pintype "passive"))
      (node (ref "LED1099") (pin "A") (pinfunction "A_A") (pintype "passive"))
      (node (ref "LED1100") (pin "A") (pinfunction "A_A") (pintype "passive"))
      (node (ref "LED1101") (pin "A") (pinfunction "A_A") (pintype "passive"))
      (node (ref "LED1102") (pin "A") (pinfunction "A_A") (pintype "passive"))
      (node (ref "LED1103") (pin "A") (pinfunction "A_A") (pintype "passive"))
      (node (ref "LED1104") (pin "A") (pinfunction "A_A") (pintype "passive"))
    )
    (net (code "97") (name "Net-(IC11A-QE)") (class "Default")
      (node (ref "IC11") (pin "10") (pinfunction "QE_10") (pintype "output"))
      (node (ref "LED1073") (pin "A") (pinfunction "A_A") (pintype "passive"))
      (node (ref "LED1074") (pin "A") (pinfunction "A_A") (pintype "passive"))
      (node (ref "LED1075") (pin "A") (pinfunction "A_A") (pintype "passive"))
      (node (ref "LED1076") (pin "A") (pinfunction "A_A") (pintype "passive"))
      (node (ref "LED1077") (pin "A") (pinfunction "A_A") (pintype "passive"))
      (node (ref "LED1078") (pin "A") (pinfunction "A_A") (pintype "passive"))
      (node (ref "LED1079") (pin "A") (pinfunction "A_A") (pintype "passive"))
      (node (ref "LED1080") (pin "A") (pinfunction "A_A") (pintype "passive"))
      (node (ref "LED1081") (pin "A") (pinfunction "A_A") (pintype "passive"))
      (node (ref "LED1082") (pin "A") (pinfunction "A_A") (pintype "passive"))
      (node (ref "LED1083") (pin "A") (pinfunction "A_A") (pintype "passive"))
      (node (ref "LED1084") (pin "A") (pinfunction "A_A") (pintype "passive"))
      (node (ref "LED1085") (pin "A") (pinfunction "A_A") (pintype "passive"))
      (node (ref "LED1086") (pin "A") (pinfunction "A_A") (pintype "passive"))
      (node (ref "LED1087") (pin "A") (pinfunction "A_A") (pintype "passive"))
      (node (ref "LED1088") (pin "A") (pinfunction "A_A") (pintype "passive"))
    )
    (net (code "98") (name "Net-(IC11A-QF)") (class "Default")
      (node (ref "IC11") (pin "11") (pinfunction "QF_11") (pintype "output"))
      (node (ref "LED1057") (pin "A") (pinfunction "A_A") (pintype "passive"))
      (node (ref "LED1058") (pin "A") (pinfunction "A_A") (pintype "passive"))
      (node (ref "LED1059") (pin "A") (pinfunction "A_A") (pintype "passive"))
      (node (ref "LED1060") (pin "A") (pinfunction "A_A") (pintype "passive"))
      (node (ref "LED1061") (pin "A") (pinfunction "A_A") (pintype "passive"))
      (node (ref "LED1062") (pin "A") (pinfunction "A_A") (pintype "passive"))
      (node (ref "LED1063") (pin "A") (pinfunction "A_A") (pintype "passive"))
      (node (ref "LED1064") (pin "A") (pinfunction "A_A") (pintype "passive"))
      (node (ref "LED1065") (pin "A") (pinfunction "A_A") (pintype "passive"))
      (node (ref "LED1066") (pin "A") (pinfunction "A_A") (pintype "passive"))
      (node (ref "LED1067") (pin "A") (pinfunction "A_A") (pintype "passive"))
      (node (ref "LED1068") (pin "A") (pinfunction "A_A") (pintype "passive"))
      (node (ref "LED1069") (pin "A") (pinfunction "A_A") (pintype "passive"))
      (node (ref "LED1070") (pin "A") (pinfunction "A_A") (pintype "passive"))
      (node (ref "LED1071") (pin "A") (pinfunction "A_A") (pintype "passive"))
      (node (ref "LED1072") (pin "A") (pinfunction "A_A") (pintype "passive"))
    )
    (net (code "99") (name "Net-(IC11A-QG)") (class "Default")
      (node (ref "IC11") (pin "12") (pinfunction "QG_12") (pintype "output"))
      (node (ref "LED1041") (pin "A") (pinfunction "A_A") (pintype "passive"))
      (node (ref "LED1042") (pin "A") (pinfunction "A_A") (pintype "passive"))
      (node (ref "LED1043") (pin "A") (pinfunction "A_A") (pintype "passive"))
      (node (ref "LED1044") (pin "A") (pinfunction "A_A") (pintype "passive"))
      (node (ref "LED1045") (pin "A") (pinfunction "A_A") (pintype "passive"))
      (node (ref "LED1046") (pin "A") (pinfunction "A_A") (pintype "passive"))
      (node (ref "LED1047") (pin "A") (pinfunction "A_A") (pintype "passive"))
      (node (ref "LED1048") (pin "A") (pinfunction "A_A") (pintype "passive"))
      (node (ref "LED1049") (pin "A") (pinfunction "A_A") (pintype "passive"))
      (node (ref "LED1050") (pin "A") (pinfunction "A_A") (pintype "passive"))
      (node (ref "LED1051") (pin "A") (pinfunction "A_A") (pintype "passive"))
      (node (ref "LED1052") (pin "A") (pinfunction "A_A") (pintype "passive"))
      (node (ref "LED1053") (pin "A") (pinfunction "A_A") (pintype "passive"))
      (node (ref "LED1054") (pin "A") (pinfunction "A_A") (pintype "passive"))
      (node (ref "LED1055") (pin "A") (pinfunction "A_A") (pintype "passive"))
      (node (ref "LED1056") (pin "A") (pinfunction "A_A") (pintype "passive"))
    )
    (net (code "100") (name "Net-(IC12A-A)") (class "Default")
      (node (ref "IC12") (pin "1") (pinfunction "A_1") (pintype "input"))
      (node (ref "IC12") (pin "2") (pinfunction "B_2") (pintype "input"))
      (node (ref "IC13") (pin "3") (pinfunction "RA1/AN1_3") (pintype "bidirectional"))
    )
    (net (code "101") (name "Net-(IC12A-QA)") (class "Default")
      (node (ref "IC12") (pin "3") (pinfunction "QA_3") (pintype "output"))
      (node (ref "LED1265") (pin "A") (pinfunction "A_A") (pintype "passive"))
      (node (ref "LED1266") (pin "A") (pinfunction "A_A") (pintype "passive"))
      (node (ref "LED1267") (pin "A") (pinfunction "A_A") (pintype "passive"))
      (node (ref "LED1268") (pin "A") (pinfunction "A_A") (pintype "passive"))
      (node (ref "LED1269") (pin "A") (pinfunction "A_A") (pintype "passive"))
      (node (ref "LED1270") (pin "A") (pinfunction "A_A") (pintype "passive"))
      (node (ref "LED1271") (pin "A") (pinfunction "A_A") (pintype "passive"))
      (node (ref "LED1272") (pin "A") (pinfunction "A_A") (pintype "passive"))
      (node (ref "LED1273") (pin "A") (pinfunction "A_A") (pintype "passive"))
      (node (ref "LED1274") (pin "A") (pinfunction "A_A") (pintype "passive"))
      (node (ref "LED1275") (pin "A") (pinfunction "A_A") (pintype "passive"))
      (node (ref "LED1276") (pin "A") (pinfunction "A_A") (pintype "passive"))
      (node (ref "LED1277") (pin "A") (pinfunction "A_A") (pintype "passive"))
      (node (ref "LED1278") (pin "A") (pinfunction "A_A") (pintype "passive"))
      (node (ref "LED1279") (pin "A") (pinfunction "A_A") (pintype "passive"))
      (node (ref "LED1280") (pin "A") (pinfunction "A_A") (pintype "passive"))
    )
    (net (code "102") (name "Net-(IC12A-QB)") (class "Default")
      (node (ref "IC12") (pin "4") (pinfunction "QB_4") (pintype "output"))
      (node (ref "LED1249") (pin "A") (pinfunction "A_A") (pintype "passive"))
      (node (ref "LED1250") (pin "A") (pinfunction "A_A") (pintype "passive"))
      (node (ref "LED1251") (pin "A") (pinfunction "A_A") (pintype "passive"))
      (node (ref "LED1252") (pin "A") (pinfunction "A_A") (pintype "passive"))
      (node (ref "LED1253") (pin "A") (pinfunction "A_A") (pintype "passive"))
      (node (ref "LED1254") (pin "A") (pinfunction "A_A") (pintype "passive"))
      (node (ref "LED1255") (pin "A") (pinfunction "A_A") (pintype "passive"))
      (node (ref "LED1256") (pin "A") (pinfunction "A_A") (pintype "passive"))
      (node (ref "LED1257") (pin "A") (pinfunction "A_A") (pintype "passive"))
      (node (ref "LED1258") (pin "A") (pinfunction "A_A") (pintype "passive"))
      (node (ref "LED1259") (pin "A") (pinfunction "A_A") (pintype "passive"))
      (node (ref "LED1260") (pin "A") (pinfunction "A_A") (pintype "passive"))
      (node (ref "LED1261") (pin "A") (pinfunction "A_A") (pintype "passive"))
      (node (ref "LED1262") (pin "A") (pinfunction "A_A") (pintype "passive"))
      (node (ref "LED1263") (pin "A") (pinfunction "A_A") (pintype "passive"))
      (node (ref "LED1264") (pin "A") (pinfunction "A_A") (pintype "passive"))
    )
    (net (code "103") (name "Net-(IC12A-QC)") (class "Default")
      (node (ref "IC12") (pin "5") (pinfunction "QC_5") (pintype "output"))
      (node (ref "LED1233") (pin "A") (pinfunction "A_A") (pintype "passive"))
      (node (ref "LED1234") (pin "A") (pinfunction "A_A") (pintype "passive"))
      (node (ref "LED1235") (pin "A") (pinfunction "A_A") (pintype "passive"))
      (node (ref "LED1236") (pin "A") (pinfunction "A_A") (pintype "passive"))
      (node (ref "LED1237") (pin "A") (pinfunction "A_A") (pintype "passive"))
      (node (ref "LED1238") (pin "A") (pinfunction "A_A") (pintype "passive"))
      (node (ref "LED1239") (pin "A") (pinfunction "A_A") (pintype "passive"))
      (node (ref "LED1240") (pin "A") (pinfunction "A_A") (pintype "passive"))
      (node (ref "LED1241") (pin "A") (pinfunction "A_A") (pintype "passive"))
      (node (ref "LED1242") (pin "A") (pinfunction "A_A") (pintype "passive"))
      (node (ref "LED1243") (pin "A") (pinfunction "A_A") (pintype "passive"))
      (node (ref "LED1244") (pin "A") (pinfunction "A_A") (pintype "passive"))
      (node (ref "LED1245") (pin "A") (pinfunction "A_A") (pintype "passive"))
      (node (ref "LED1246") (pin "A") (pinfunction "A_A") (pintype "passive"))
      (node (ref "LED1247") (pin "A") (pinfunction "A_A") (pintype "passive"))
      (node (ref "LED1248") (pin "A") (pinfunction "A_A") (pintype "passive"))
    )
    (net (code "104") (name "Net-(IC12A-QD)") (class "Default")
      (node (ref "IC12") (pin "6") (pinfunction "QD_6") (pintype "output"))
      (node (ref "LED1217") (pin "A") (pinfunction "A_A") (pintype "passive"))
      (node (ref "LED1218") (pin "A") (pinfunction "A_A") (pintype "passive"))
      (node (ref "LED1219") (pin "A") (pinfunction "A_A") (pintype "passive"))
      (node (ref "LED1220") (pin "A") (pinfunction "A_A") (pintype "passive"))
      (node (ref "LED1221") (pin "A") (pinfunction "A_A") (pintype "passive"))
      (node (ref "LED1222") (pin "A") (pinfunction "A_A") (pintype "passive"))
      (node (ref "LED1223") (pin "A") (pinfunction "A_A") (pintype "passive"))
      (node (ref "LED1224") (pin "A") (pinfunction "A_A") (pintype "passive"))
      (node (ref "LED1225") (pin "A") (pinfunction "A_A") (pintype "passive"))
      (node (ref "LED1226") (pin "A") (pinfunction "A_A") (pintype "passive"))
      (node (ref "LED1227") (pin "A") (pinfunction "A_A") (pintype "passive"))
      (node (ref "LED1228") (pin "A") (pinfunction "A_A") (pintype "passive"))
      (node (ref "LED1229") (pin "A") (pinfunction "A_A") (pintype "passive"))
      (node (ref "LED1230") (pin "A") (pinfunction "A_A") (pintype "passive"))
      (node (ref "LED1231") (pin "A") (pinfunction "A_A") (pintype "passive"))
      (node (ref "LED1232") (pin "A") (pinfunction "A_A") (pintype "passive"))
    )
    (net (code "105") (name "Net-(IC12A-QE)") (class "Default")
      (node (ref "IC12") (pin "10") (pinfunction "QE_10") (pintype "output"))
      (node (ref "LED1201") (pin "A") (pinfunction "A_A") (pintype "passive"))
      (node (ref "LED1202") (pin "A") (pinfunction "A_A") (pintype "passive"))
      (node (ref "LED1203") (pin "A") (pinfunction "A_A") (pintype "passive"))
      (node (ref "LED1204") (pin "A") (pinfunction "A_A") (pintype "passive"))
      (node (ref "LED1205") (pin "A") (pinfunction "A_A") (pintype "passive"))
      (node (ref "LED1206") (pin "A") (pinfunction "A_A") (pintype "passive"))
      (node (ref "LED1207") (pin "A") (pinfunction "A_A") (pintype "passive"))
      (node (ref "LED1208") (pin "A") (pinfunction "A_A") (pintype "passive"))
      (node (ref "LED1209") (pin "A") (pinfunction "A_A") (pintype "passive"))
      (node (ref "LED1210") (pin "A") (pinfunction "A_A") (pintype "passive"))
      (node (ref "LED1211") (pin "A") (pinfunction "A_A") (pintype "passive"))
      (node (ref "LED1212") (pin "A") (pinfunction "A_A") (pintype "passive"))
      (node (ref "LED1213") (pin "A") (pinfunction "A_A") (pintype "passive"))
      (node (ref "LED1214") (pin "A") (pinfunction "A_A") (pintype "passive"))
      (node (ref "LED1215") (pin "A") (pinfunction "A_A") (pintype "passive"))
      (node (ref "LED1216") (pin "A") (pinfunction "A_A") (pintype "passive"))
    )
    (net (code "106") (name "Net-(IC12A-QF)") (class "Default")
      (node (ref "IC12") (pin "11") (pinfunction "QF_11") (pintype "output"))
      (node (ref "LED1185") (pin "A") (pinfunction "A_A") (pintype "passive"))
      (node (ref "LED1186") (pin "A") (pinfunction "A_A") (pintype "passive"))
      (node (ref "LED1187") (pin "A") (pinfunction "A_A") (pintype "passive"))
      (node (ref "LED1188") (pin "A") (pinfunction "A_A") (pintype "passive"))
      (node (ref "LED1189") (pin "A") (pinfunction "A_A") (pintype "passive"))
      (node (ref "LED1190") (pin "A") (pinfunction "A_A") (pintype "passive"))
      (node (ref "LED1191") (pin "A") (pinfunction "A_A") (pintype "passive"))
      (node (ref "LED1192") (pin "A") (pinfunction "A_A") (pintype "passive"))
      (node (ref "LED1193") (pin "A") (pinfunction "A_A") (pintype "passive"))
      (node (ref "LED1194") (pin "A") (pinfunction "A_A") (pintype "passive"))
      (node (ref "LED1195") (pin "A") (pinfunction "A_A") (pintype "passive"))
      (node (ref "LED1196") (pin "A") (pinfunction "A_A") (pintype "passive"))
      (node (ref "LED1197") (pin "A") (pinfunction "A_A") (pintype "passive"))
      (node (ref "LED1198") (pin "A") (pinfunction "A_A") (pintype "passive"))
      (node (ref "LED1199") (pin "A") (pinfunction "A_A") (pintype "passive"))
      (node (ref "LED1200") (pin "A") (pinfunction "A_A") (pintype "passive"))
    )
    (net (code "107") (name "Net-(IC12A-QG)") (class "Default")
      (node (ref "IC12") (pin "12") (pinfunction "QG_12") (pintype "output"))
      (node (ref "LED1169") (pin "A") (pinfunction "A_A") (pintype "passive"))
      (node (ref "LED1170") (pin "A") (pinfunction "A_A") (pintype "passive"))
      (node (ref "LED1171") (pin "A") (pinfunction "A_A") (pintype "passive"))
      (node (ref "LED1172") (pin "A") (pinfunction "A_A") (pintype "passive"))
      (node (ref "LED1173") (pin "A") (pinfunction "A_A") (pintype "passive"))
      (node (ref "LED1174") (pin "A") (pinfunction "A_A") (pintype "passive"))
      (node (ref "LED1175") (pin "A") (pinfunction "A_A") (pintype "passive"))
      (node (ref "LED1176") (pin "A") (pinfunction "A_A") (pintype "passive"))
      (node (ref "LED1177") (pin "A") (pinfunction "A_A") (pintype "passive"))
      (node (ref "LED1178") (pin "A") (pinfunction "A_A") (pintype "passive"))
      (node (ref "LED1179") (pin "A") (pinfunction "A_A") (pintype "passive"))
      (node (ref "LED1180") (pin "A") (pinfunction "A_A") (pintype "passive"))
      (node (ref "LED1181") (pin "A") (pinfunction "A_A") (pintype "passive"))
      (node (ref "LED1182") (pin "A") (pinfunction "A_A") (pintype "passive"))
      (node (ref "LED1183") (pin "A") (pinfunction "A_A") (pintype "passive"))
      (node (ref "LED1184") (pin "A") (pinfunction "A_A") (pintype "passive"))
    )
    (net (code "108") (name "Net-(IC13-OSC1{slash}CLKIN)") (class "Default")
      (node (ref "C1") (pin "1") (pinfunction "1_1") (pintype "passive"))
      (node (ref "IC13") (pin "13") (pinfunction "OSC1/CLKIN_13") (pintype "input"))
      (node (ref "Q1") (pin "2") (pinfunction "2_2") (pintype "passive"))
    )
    (net (code "109") (name "Net-(IC13-OSC2{slash}CLKOUT)") (class "Default")
      (node (ref "C3") (pin "1") (pinfunction "1_1") (pintype "passive"))
      (node (ref "IC13") (pin "14") (pinfunction "OSC2/CLKOUT_14") (pintype "output"))
      (node (ref "Q1") (pin "1") (pinfunction "1_1") (pintype "passive"))
    )
    (net (code "110") (name "Net-(IC13-PSP4{slash}RD4)") (class "Default")
      (node (ref "IC13") (pin "27") (pinfunction "PSP4/RD4_27") (pintype "bidirectional"))
      (node (ref "IC2") (pin "5") (pinfunction "I5_5") (pintype "input"))
    )
    (net (code "111") (name "Net-(IC13-PSP5{slash}RD5)") (class "Default")
      (node (ref "IC13") (pin "28") (pinfunction "PSP5/RD5_28") (pintype "bidirectional"))
      (node (ref "IC2") (pin "6") (pinfunction "I6_6") (pintype "input"))
    )
    (net (code "112") (name "Net-(IC13-PSP6{slash}RD6)") (class "Default")
      (node (ref "IC13") (pin "29") (pinfunction "PSP6/RD6_29") (pintype "bidirectional"))
      (node (ref "IC2") (pin "7") (pinfunction "I7_7") (pintype "input"))
    )
    (net (code "113") (name "Net-(IC13-PSP7{slash}RD7)") (class "Default")
      (node (ref "IC13") (pin "30") (pinfunction "PSP7/RD7_30") (pintype "bidirectional"))
      (node (ref "IC2") (pin "8") (pinfunction "I8_8") (pintype "input"))
    )
    (net (code "114") (name "Net-(IC13-RC3{slash}SCK)") (class "Default")
      (node (ref "IC13") (pin "18") (pinfunction "RC3/SCK_18") (pintype "bidirectional"))
      (node (ref "IC14") (pin "6") (pinfunction "SCK_6") (pintype "input"))
    )
    (net (code "115") (name "Net-(IC13-RD0{slash}PSP0)") (class "Default")
      (node (ref "IC13") (pin "19") (pinfunction "RD0/PSP0_19") (pintype "bidirectional"))
      (node (ref "IC2") (pin "1") (pinfunction "I1_1") (pintype "input"))
    )
    (net (code "116") (name "Net-(IC13-RD1{slash}PSP1)") (class "Default")
      (node (ref "IC13") (pin "20") (pinfunction "RD1/PSP1_20") (pintype "bidirectional"))
      (node (ref "IC2") (pin "2") (pinfunction "I2_2") (pintype "input"))
    )
    (net (code "117") (name "Net-(IC13-RD2{slash}PSP2)") (class "Default")
      (node (ref "IC13") (pin "21") (pinfunction "RD2/PSP2_21") (pintype "bidirectional"))
      (node (ref "IC2") (pin "3") (pinfunction "I3_3") (pintype "input"))
    )
    (net (code "118") (name "Net-(IC13-RD3{slash}PSP3)") (class "Default")
      (node (ref "IC13") (pin "22") (pinfunction "RD3/PSP3_22") (pintype "bidirectional"))
      (node (ref "IC2") (pin "4") (pinfunction "I4_4") (pintype "input"))
    )
    (net (code "119") (name "Net-(IC13-RX{slash}RC7)") (class "Default")
      (node (ref "IC13") (pin "26") (pinfunction "RX/RC7_26") (pintype "bidirectional"))
      (node (ref "X1") (pin "2") (pinfunction "2_2") (pintype "passive"))
    )
    (net (code "120") (name "Net-(IC13-SDI{slash}RC4)") (class "Default")
      (node (ref "IC13") (pin "23") (pinfunction "SDI/RC4_23") (pintype "bidirectional"))
      (node (ref "IC14") (pin "2") (pinfunction "SO_2") (pintype "bidirectional"))
    )
    (net (code "121") (name "Net-(IC13-SDO{slash}RC5)") (class "Default")
      (node (ref "IC13") (pin "24") (pinfunction "SDO/RC5_24") (pintype "bidirectional"))
      (node (ref "IC14") (pin "5") (pinfunction "SI_5") (pintype "input"))
    )
    (net (code "122") (name "Net-(IC13-TX{slash}RC6)") (class "Default")
      (node (ref "IC13") (pin "25") (pinfunction "TX/RC6_25") (pintype "bidirectional"))
      (node (ref "X1") (pin "3") (pinfunction "3_3") (pintype "passive"))
    )
    (net (code "123") (name "Net-(IC13-~{MCLR{slash}THV})") (class "Default")
      (node (ref "C2") (pin "1") (pinfunction "1_1") (pintype "passive"))
      (node (ref "IC13") (pin "1") (pinfunction "~{MCLR/THV}_1") (pintype "input"))
      (node (ref "J1") (pin "1") (pinfunction "1_1") (pintype "passive"))
      (node (ref "R17") (pin "1") (pinfunction "1_1") (pintype "passive"))
      (node (ref "S1") (pin "1") (pinfunction "S_1") (pintype "passive"))
      (node (ref "S1") (pin "2") (pinfunction "S1_2") (pintype "passive"))
    )
    (net (code "124") (name "Net-(LED1-C)") (class "Default")
      (node (ref "LED1") (pin "K") (pinfunction "C_K") (pintype "passive"))
      (node (ref "LED1009") (pin "K") (pinfunction "C_K") (pintype "passive"))
      (node (ref "LED1025") (pin "K") (pinfunction "C_K") (pintype "passive"))
      (node (ref "LED1041") (pin "K") (pinfunction "C_K") (pintype "passive"))
      (node (ref "LED1057") (pin "K") (pinfunction "C_K") (pintype "passive"))
      (node (ref "LED1073") (pin "K") (pinfunction "C_K") (pintype "passive"))
      (node (ref "LED1089") (pin "K") (pinfunction "C_K") (pintype "passive"))
      (node (ref "LED1105") (pin "K") (pinfunction "C_K") (pintype "passive"))
      (node (ref "LED1121") (pin "K") (pinfunction "C_K") (pintype "passive"))
      (node (ref "LED113") (pin "K") (pinfunction "C_K") (pintype "passive"))
      (node (ref "LED1137") (pin "K") (pinfunction "C_K") (pintype "passive"))
      (node (ref "LED1153") (pin "K") (pinfunction "C_K") (pintype "passive"))
      (node (ref "LED1169") (pin "K") (pinfunction "C_K") (pintype "passive"))
      (node (ref "LED1185") (pin "K") (pinfunction "C_K") (pintype "passive"))
      (node (ref "LED1201") (pin "K") (pinfunction "C_K") (pintype "passive"))
      (node (ref "LED1217") (pin "K") (pinfunction "C_K") (pintype "passive"))
      (node (ref "LED1233") (pin "K") (pinfunction "C_K") (pintype "passive"))
      (node (ref "LED1249") (pin "K") (pinfunction "C_K") (pintype "passive"))
      (node (ref "LED1265") (pin "K") (pinfunction "C_K") (pintype "passive"))
      (node (ref "LED129") (pin "K") (pinfunction "C_K") (pintype "passive"))
      (node (ref "LED145") (pin "K") (pinfunction "C_K") (pintype "passive"))
      (node (ref "LED161") (pin "K") (pinfunction "C_K") (pintype "passive"))
      (node (ref "LED17") (pin "K") (pinfunction "C_K") (pintype "passive"))
      (node (ref "LED177") (pin "K") (pinfunction "C_K") (pintype "passive"))
      (node (ref "LED193") (pin "K") (pinfunction "C_K") (pintype "passive"))
      (node (ref "LED209") (pin "K") (pinfunction "C_K") (pintype "passive"))
      (node (ref "LED225") (pin "K") (pinfunction "C_K") (pintype "passive"))
      (node (ref "LED241") (pin "K") (pinfunction "C_K") (pintype "passive"))
      (node (ref "LED257") (pin "K") (pinfunction "C_K") (pintype "passive"))
      (node (ref "LED273") (pin "K") (pinfunction "C_K") (pintype "passive"))
      (node (ref "LED289") (pin "K") (pinfunction "C_K") (pintype "passive"))
      (node (ref "LED305") (pin "K") (pinfunction "C_K") (pintype "passive"))
      (node (ref "LED321") (pin "K") (pinfunction "C_K") (pintype "passive"))
      (node (ref "LED33") (pin "K") (pinfunction "C_K") (pintype "passive"))
      (node (ref "LED337") (pin "K") (pinfunction "C_K") (pintype "passive"))
      (node (ref "LED353") (pin "K") (pinfunction "C_K") (pintype "passive"))
      (node (ref "LED369") (pin "K") (pinfunction "C_K") (pintype "passive"))
      (node (ref "LED385") (pin "K") (pinfunction "C_K") (pintype "passive"))
      (node (ref "LED401") (pin "K") (pinfunction "C_K") (pintype "passive"))
      (node (ref "LED417") (pin "K") (pinfunction "C_K") (pintype "passive"))
      (node (ref "LED433") (pin "K") (pinfunction "C_K") (pintype "passive"))
      (node (ref "LED449") (pin "K") (pinfunction "C_K") (pintype "passive"))
      (node (ref "LED465") (pin "K") (pinfunction "C_K") (pintype "passive"))
      (node (ref "LED481") (pin "K") (pinfunction "C_K") (pintype "passive"))
      (node (ref "LED49") (pin "K") (pinfunction "C_K") (pintype "passive"))
      (node (ref "LED497") (pin "K") (pinfunction "C_K") (pintype "passive"))
      (node (ref "LED513") (pin "K") (pinfunction "C_K") (pintype "passive"))
      (node (ref "LED529") (pin "K") (pinfunction "C_K") (pintype "passive"))
      (node (ref "LED545") (pin "K") (pinfunction "C_K") (pintype "passive"))
      (node (ref "LED561") (pin "K") (pinfunction "C_K") (pintype "passive"))
      (node (ref "LED577") (pin "K") (pinfunction "C_K") (pintype "passive"))
      (node (ref "LED593") (pin "K") (pinfunction "C_K") (pintype "passive"))
      (node (ref "LED609") (pin "K") (pinfunction "C_K") (pintype "passive"))
      (node (ref "LED625") (pin "K") (pinfunction "C_K") (pintype "passive"))
      (node (ref "LED641") (pin "K") (pinfunction "C_K") (pintype "passive"))
      (node (ref "LED65") (pin "K") (pinfunction "C_K") (pintype "passive"))
      (node (ref "LED657") (pin "K") (pinfunction "C_K") (pintype "passive"))
      (node (ref "LED673") (pin "K") (pinfunction "C_K") (pintype "passive"))
      (node (ref "LED689") (pin "K") (pinfunction "C_K") (pintype "passive"))
      (node (ref "LED705") (pin "K") (pinfunction "C_K") (pintype "passive"))
      (node (ref "LED721") (pin "K") (pinfunction "C_K") (pintype "passive"))
      (node (ref "LED737") (pin "K") (pinfunction "C_K") (pintype "passive"))
      (node (ref "LED753") (pin "K") (pinfunction "C_K") (pintype "passive"))
      (node (ref "LED769") (pin "K") (pinfunction "C_K") (pintype "passive"))
      (node (ref "LED785") (pin "K") (pinfunction "C_K") (pintype "passive"))
      (node (ref "LED801") (pin "K") (pinfunction "C_K") (pintype "passive"))
      (node (ref "LED81") (pin "K") (pinfunction "C_K") (pintype "passive"))
      (node (ref "LED817") (pin "K") (pinfunction "C_K") (pintype "passive"))
      (node (ref "LED833") (pin "K") (pinfunction "C_K") (pintype "passive"))
      (node (ref "LED849") (pin "K") (pinfunction "C_K") (pintype "passive"))
      (node (ref "LED865") (pin "K") (pinfunction "C_K") (pintype "passive"))
      (node (ref "LED881") (pin "K") (pinfunction "C_K") (pintype "passive"))
      (node (ref "LED897") (pin "K") (pinfunction "C_K") (pintype "passive"))
      (node (ref "LED913") (pin "K") (pinfunction "C_K") (pintype "passive"))
      (node (ref "LED929") (pin "K") (pinfunction "C_K") (pintype "passive"))
      (node (ref "LED945") (pin "K") (pinfunction "C_K") (pintype "passive"))
      (node (ref "LED961") (pin "K") (pinfunction "C_K") (pintype "passive"))
      (node (ref "LED97") (pin "K") (pinfunction "C_K") (pintype "passive"))
      (node (ref "LED977") (pin "K") (pinfunction "C_K") (pintype "passive"))
      (node (ref "LED993") (pin "K") (pinfunction "C_K") (pintype "passive"))
      (node (ref "R1") (pin "1") (pinfunction "1_1") (pintype "passive"))
    )
    (net (code "125") (name "Net-(LED10-C)") (class "Default")
      (node (ref "LED10") (pin "K") (pinfunction "C_K") (pintype "passive"))
      (node (ref "LED1002") (pin "K") (pinfunction "C_K") (pintype "passive"))
      (node (ref "LED1018") (pin "K") (pinfunction "C_K") (pintype "passive"))
      (node (ref "LED1034") (pin "K") (pinfunction "C_K") (pintype "passive"))
      (node (ref "LED1050") (pin "K") (pinfunction "C_K") (pintype "passive"))
      (node (ref "LED106") (pin "K") (pinfunction "C_K") (pintype "passive"))
      (node (ref "LED1066") (pin "K") (pinfunction "C_K") (pintype "passive"))
      (node (ref "LED1082") (pin "K") (pinfunction "C_K") (pintype "passive"))
      (node (ref "LED1098") (pin "K") (pinfunction "C_K") (pintype "passive"))
      (node (ref "LED1114") (pin "K") (pinfunction "C_K") (pintype "passive"))
      (node (ref "LED1130") (pin "K") (pinfunction "C_K") (pintype "passive"))
      (node (ref "LED1146") (pin "K") (pinfunction "C_K") (pintype "passive"))
      (node (ref "LED1162") (pin "K") (pinfunction "C_K") (pintype "passive"))
      (node (ref "LED1178") (pin "K") (pinfunction "C_K") (pintype "passive"))
      (node (ref "LED1194") (pin "K") (pinfunction "C_K") (pintype "passive"))
      (node (ref "LED1210") (pin "K") (pinfunction "C_K") (pintype "passive"))
      (node (ref "LED122") (pin "K") (pinfunction "C_K") (pintype "passive"))
      (node (ref "LED1226") (pin "K") (pinfunction "C_K") (pintype "passive"))
      (node (ref "LED1242") (pin "K") (pinfunction "C_K") (pintype "passive"))
      (node (ref "LED1258") (pin "K") (pinfunction "C_K") (pintype "passive"))
      (node (ref "LED1274") (pin "K") (pinfunction "C_K") (pintype "passive"))
      (node (ref "LED138") (pin "K") (pinfunction "C_K") (pintype "passive"))
      (node (ref "LED154") (pin "K") (pinfunction "C_K") (pintype "passive"))
      (node (ref "LED170") (pin "K") (pinfunction "C_K") (pintype "passive"))
      (node (ref "LED186") (pin "K") (pinfunction "C_K") (pintype "passive"))
      (node (ref "LED202") (pin "K") (pinfunction "C_K") (pintype "passive"))
      (node (ref "LED218") (pin "K") (pinfunction "C_K") (pintype "passive"))
      (node (ref "LED234") (pin "K") (pinfunction "C_K") (pintype "passive"))
      (node (ref "LED250") (pin "K") (pinfunction "C_K") (pintype "passive"))
      (node (ref "LED26") (pin "K") (pinfunction "C_K") (pintype "passive"))
      (node (ref "LED266") (pin "K") (pinfunction "C_K") (pintype "passive"))
      (node (ref "LED282") (pin "K") (pinfunction "C_K") (pintype "passive"))
      (node (ref "LED298") (pin "K") (pinfunction "C_K") (pintype "passive"))
      (node (ref "LED314") (pin "K") (pinfunction "C_K") (pintype "passive"))
      (node (ref "LED330") (pin "K") (pinfunction "C_K") (pintype "passive"))
      (node (ref "LED346") (pin "K") (pinfunction "C_K") (pintype "passive"))
      (node (ref "LED362") (pin "K") (pinfunction "C_K") (pintype "passive"))
      (node (ref "LED378") (pin "K") (pinfunction "C_K") (pintype "passive"))
      (node (ref "LED394") (pin "K") (pinfunction "C_K") (pintype "passive"))
      (node (ref "LED410") (pin "K") (pinfunction "C_K") (pintype "passive"))
      (node (ref "LED42") (pin "K") (pinfunction "C_K") (pintype "passive"))
      (node (ref "LED426") (pin "K") (pinfunction "C_K") (pintype "passive"))
      (node (ref "LED442") (pin "K") (pinfunction "C_K") (pintype "passive"))
      (node (ref "LED458") (pin "K") (pinfunction "C_K") (pintype "passive"))
      (node (ref "LED474") (pin "K") (pinfunction "C_K") (pintype "passive"))
      (node (ref "LED490") (pin "K") (pinfunction "C_K") (pintype "passive"))
      (node (ref "LED506") (pin "K") (pinfunction "C_K") (pintype "passive"))
      (node (ref "LED522") (pin "K") (pinfunction "C_K") (pintype "passive"))
      (node (ref "LED538") (pin "K") (pinfunction "C_K") (pintype "passive"))
      (node (ref "LED554") (pin "K") (pinfunction "C_K") (pintype "passive"))
      (node (ref "LED570") (pin "K") (pinfunction "C_K") (pintype "passive"))
      (node (ref "LED58") (pin "K") (pinfunction "C_K") (pintype "passive"))
      (node (ref "LED586") (pin "K") (pinfunction "C_K") (pintype "passive"))
      (node (ref "LED602") (pin "K") (pinfunction "C_K") (pintype "passive"))
      (node (ref "LED618") (pin "K") (pinfunction "C_K") (pintype "passive"))
      (node (ref "LED634") (pin "K") (pinfunction "C_K") (pintype "passive"))
      (node (ref "LED650") (pin "K") (pinfunction "C_K") (pintype "passive"))
      (node (ref "LED666") (pin "K") (pinfunction "C_K") (pintype "passive"))
      (node (ref "LED682") (pin "K") (pinfunction "C_K") (pintype "passive"))
      (node (ref "LED698") (pin "K") (pinfunction "C_K") (pintype "passive"))
      (node (ref "LED714") (pin "K") (pinfunction "C_K") (pintype "passive"))
      (node (ref "LED730") (pin "K") (pinfunction "C_K") (pintype "passive"))
      (node (ref "LED74") (pin "K") (pinfunction "C_K") (pintype "passive"))
      (node (ref "LED746") (pin "K") (pinfunction "C_K") (pintype "passive"))
      (node (ref "LED762") (pin "K") (pinfunction "C_K") (pintype "passive"))
      (node (ref "LED778") (pin "K") (pinfunction "C_K") (pintype "passive"))
      (node (ref "LED794") (pin "K") (pinfunction "C_K") (pintype "passive"))
      (node (ref "LED810") (pin "K") (pinfunction "C_K") (pintype "passive"))
      (node (ref "LED826") (pin "K") (pinfunction "C_K") (pintype "passive"))
      (node (ref "LED842") (pin "K") (pinfunction "C_K") (pintype "passive"))
      (node (ref "LED858") (pin "K") (pinfunction "C_K") (pintype "passive"))
      (node (ref "LED874") (pin "K") (pinfunction "C_K") (pintype "passive"))
      (node (ref "LED890") (pin "K") (pinfunction "C_K") (pintype "passive"))
      (node (ref "LED90") (pin "K") (pinfunction "C_K") (pintype "passive"))
      (node (ref "LED906") (pin "K") (pinfunction "C_K") (pintype "passive"))
      (node (ref "LED922") (pin "K") (pinfunction "C_K") (pintype "passive"))
      (node (ref "LED938") (pin "K") (pinfunction "C_K") (pintype "passive"))
      (node (ref "LED954") (pin "K") (pinfunction "C_K") (pintype "passive"))
      (node (ref "LED970") (pin "K") (pinfunction "C_K") (pintype "passive"))
      (node (ref "LED986") (pin "K") (pinfunction "C_K") (pintype "passive"))
      (node (ref "R10") (pin "1") (pinfunction "1_1") (pintype "passive"))
    )
    (net (code "126") (name "Net-(LED100-C)") (class "Default")
      (node (ref "LED100") (pin "K") (pinfunction "C_K") (pintype "passive"))
      (node (ref "LED1012") (pin "K") (pinfunction "C_K") (pintype "passive"))
      (node (ref "LED1028") (pin "K") (pinfunction "C_K") (pintype "passive"))
      (node (ref "LED1044") (pin "K") (pinfunction "C_K") (pintype "passive"))
      (node (ref "LED1060") (pin "K") (pinfunction "C_K") (pintype "passive"))
      (node (ref "LED1076") (pin "K") (pinfunction "C_K") (pintype "passive"))
      (node (ref "LED1092") (pin "K") (pinfunction "C_K") (pintype "passive"))
      (node (ref "LED1108") (pin "K") (pinfunction "C_K") (pintype "passive"))
      (node (ref "LED1124") (pin "K") (pinfunction "C_K") (pintype "passive"))
      (node (ref "LED1140") (pin "K") (pinfunction "C_K") (pintype "passive"))
      (node (ref "LED1156") (pin "K") (pinfunction "C_K") (pintype "passive"))
      (node (ref "LED116") (pin "K") (pinfunction "C_K") (pintype "passive"))
      (node (ref "LED1172") (pin "K") (pinfunction "C_K") (pintype "passive"))
      (node (ref "LED1188") (pin "K") (pinfunction "C_K") (pintype "passive"))
      (node (ref "LED1204") (pin "K") (pinfunction "C_K") (pintype "passive"))
      (node (ref "LED1220") (pin "K") (pinfunction "C_K") (pintype "passive"))
      (node (ref "LED1236") (pin "K") (pinfunction "C_K") (pintype "passive"))
      (node (ref "LED1252") (pin "K") (pinfunction "C_K") (pintype "passive"))
      (node (ref "LED1268") (pin "K") (pinfunction "C_K") (pintype "passive"))
      (node (ref "LED132") (pin "K") (pinfunction "C_K") (pintype "passive"))
      (node (ref "LED148") (pin "K") (pinfunction "C_K") (pintype "passive"))
      (node (ref "LED164") (pin "K") (pinfunction "C_K") (pintype "passive"))
      (node (ref "LED180") (pin "K") (pinfunction "C_K") (pintype "passive"))
      (node (ref "LED196") (pin "K") (pinfunction "C_K") (pintype "passive"))
      (node (ref "LED20") (pin "K") (pinfunction "C_K") (pintype "passive"))
      (node (ref "LED212") (pin "K") (pinfunction "C_K") (pintype "passive"))
      (node (ref "LED228") (pin "K") (pinfunction "C_K") (pintype "passive"))
      (node (ref "LED244") (pin "K") (pinfunction "C_K") (pintype "passive"))
      (node (ref "LED260") (pin "K") (pinfunction "C_K") (pintype "passive"))
      (node (ref "LED276") (pin "K") (pinfunction "C_K") (pintype "passive"))
      (node (ref "LED292") (pin "K") (pinfunction "C_K") (pintype "passive"))
      (node (ref "LED308") (pin "K") (pinfunction "C_K") (pintype "passive"))
      (node (ref "LED324") (pin "K") (pinfunction "C_K") (pintype "passive"))
      (node (ref "LED340") (pin "K") (pinfunction "C_K") (pintype "passive"))
      (node (ref "LED356") (pin "K") (pinfunction "C_K") (pintype "passive"))
      (node (ref "LED36") (pin "K") (pinfunction "C_K") (pintype "passive"))
      (node (ref "LED372") (pin "K") (pinfunction "C_K") (pintype "passive"))
      (node (ref "LED388") (pin "K") (pinfunction "C_K") (pintype "passive"))
      (node (ref "LED4") (pin "K") (pinfunction "C_K") (pintype "passive"))
      (node (ref "LED404") (pin "K") (pinfunction "C_K") (pintype "passive"))
      (node (ref "LED420") (pin "K") (pinfunction "C_K") (pintype "passive"))
      (node (ref "LED436") (pin "K") (pinfunction "C_K") (pintype "passive"))
      (node (ref "LED452") (pin "K") (pinfunction "C_K") (pintype "passive"))
      (node (ref "LED468") (pin "K") (pinfunction "C_K") (pintype "passive"))
      (node (ref "LED484") (pin "K") (pinfunction "C_K") (pintype "passive"))
      (node (ref "LED500") (pin "K") (pinfunction "C_K") (pintype "passive"))
      (node (ref "LED516") (pin "K") (pinfunction "C_K") (pintype "passive"))
      (node (ref "LED52") (pin "K") (pinfunction "C_K") (pintype "passive"))
      (node (ref "LED532") (pin "K") (pinfunction "C_K") (pintype "passive"))
      (node (ref "LED548") (pin "K") (pinfunction "C_K") (pintype "passive"))
      (node (ref "LED564") (pin "K") (pinfunction "C_K") (pintype "passive"))
      (node (ref "LED580") (pin "K") (pinfunction "C_K") (pintype "passive"))
      (node (ref "LED596") (pin "K") (pinfunction "C_K") (pintype "passive"))
      (node (ref "LED612") (pin "K") (pinfunction "C_K") (pintype "passive"))
      (node (ref "LED628") (pin "K") (pinfunction "C_K") (pintype "passive"))
      (node (ref "LED644") (pin "K") (pinfunction "C_K") (pintype "passive"))
      (node (ref "LED660") (pin "K") (pinfunction "C_K") (pintype "passive"))
      (node (ref "LED676") (pin "K") (pinfunction "C_K") (pintype "passive"))
      (node (ref "LED68") (pin "K") (pinfunction "C_K") (pintype "passive"))
      (node (ref "LED692") (pin "K") (pinfunction "C_K") (pintype "passive"))
      (node (ref "LED708") (pin "K") (pinfunction "C_K") (pintype "passive"))
      (node (ref "LED724") (pin "K") (pinfunction "C_K") (pintype "passive"))
      (node (ref "LED740") (pin "K") (pinfunction "C_K") (pintype "passive"))
      (node (ref "LED756") (pin "K") (pinfunction "C_K") (pintype "passive"))
      (node (ref "LED772") (pin "K") (pinfunction "C_K") (pintype "passive"))
      (node (ref "LED788") (pin "K") (pinfunction "C_K") (pintype "passive"))
      (node (ref "LED804") (pin "K") (pinfunction "C_K") (pintype "passive"))
      (node (ref "LED820") (pin "K") (pinfunction "C_K") (pintype "passive"))
      (node (ref "LED836") (pin "K") (pinfunction "C_K") (pintype "passive"))
      (node (ref "LED84") (pin "K") (pinfunction "C_K") (pintype "passive"))
      (node (ref "LED852") (pin "K") (pinfunction "C_K") (pintype "passive"))
      (node (ref "LED868") (pin "K") (pinfunction "C_K") (pintype "passive"))
      (node (ref "LED884") (pin "K") (pinfunction "C_K") (pintype "passive"))
      (node (ref "LED900") (pin "K") (pinfunction "C_K") (pintype "passive"))
      (node (ref "LED916") (pin "K") (pinfunction "C_K") (pintype "passive"))
      (node (ref "LED932") (pin "K") (pinfunction "C_K") (pintype "passive"))
      (node (ref "LED948") (pin "K") (pinfunction "C_K") (pintype "passive"))
      (node (ref "LED964") (pin "K") (pinfunction "C_K") (pintype "passive"))
      (node (ref "LED980") (pin "K") (pinfunction "C_K") (pintype "passive"))
      (node (ref "LED996") (pin "K") (pinfunction "C_K") (pintype "passive"))
      (node (ref "R4") (pin "1") (pinfunction "1_1") (pintype "passive"))
    )
    (net (code "127") (name "Net-(LED101-C)") (class "Default")
      (node (ref "LED101") (pin "K") (pinfunction "C_K") (pintype "passive"))
      (node (ref "LED1013") (pin "K") (pinfunction "C_K") (pintype "passive"))
      (node (ref "LED1029") (pin "K") (pinfunction "C_K") (pintype "passive"))
      (node (ref "LED1045") (pin "K") (pinfunction "C_K") (pintype "passive"))
      (node (ref "LED1061") (pin "K") (pinfunction "C_K") (pintype "passive"))
      (node (ref "LED1077") (pin "K") (pinfunction "C_K") (pintype "passive"))
      (node (ref "LED1093") (pin "K") (pinfunction "C_K") (pintype "passive"))
      (node (ref "LED1109") (pin "K") (pinfunction "C_K") (pintype "passive"))
      (node (ref "LED1125") (pin "K") (pinfunction "C_K") (pintype "passive"))
      (node (ref "LED1141") (pin "K") (pinfunction "C_K") (pintype "passive"))
      (node (ref "LED1157") (pin "K") (pinfunction "C_K") (pintype "passive"))
      (node (ref "LED117") (pin "K") (pinfunction "C_K") (pintype "passive"))
      (node (ref "LED1173") (pin "K") (pinfunction "C_K") (pintype "passive"))
      (node (ref "LED1189") (pin "K") (pinfunction "C_K") (pintype "passive"))
      (node (ref "LED1205") (pin "K") (pinfunction "C_K") (pintype "passive"))
      (node (ref "LED1221") (pin "K") (pinfunction "C_K") (pintype "passive"))
      (node (ref "LED1237") (pin "K") (pinfunction "C_K") (pintype "passive"))
      (node (ref "LED1253") (pin "K") (pinfunction "C_K") (pintype "passive"))
      (node (ref "LED1269") (pin "K") (pinfunction "C_K") (pintype "passive"))
      (node (ref "LED133") (pin "K") (pinfunction "C_K") (pintype "passive"))
      (node (ref "LED149") (pin "K") (pinfunction "C_K") (pintype "passive"))
      (node (ref "LED165") (pin "K") (pinfunction "C_K") (pintype "passive"))
      (node (ref "LED181") (pin "K") (pinfunction "C_K") (pintype "passive"))
      (node (ref "LED197") (pin "K") (pinfunction "C_K") (pintype "passive"))
      (node (ref "LED21") (pin "K") (pinfunction "C_K") (pintype "passive"))
      (node (ref "LED213") (pin "K") (pinfunction "C_K") (pintype "passive"))
      (node (ref "LED229") (pin "K") (pinfunction "C_K") (pintype "passive"))
      (node (ref "LED245") (pin "K") (pinfunction "C_K") (pintype "passive"))
      (node (ref "LED261") (pin "K") (pinfunction "C_K") (pintype "passive"))
      (node (ref "LED277") (pin "K") (pinfunction "C_K") (pintype "passive"))
      (node (ref "LED293") (pin "K") (pinfunction "C_K") (pintype "passive"))
      (node (ref "LED309") (pin "K") (pinfunction "C_K") (pintype "passive"))
      (node (ref "LED325") (pin "K") (pinfunction "C_K") (pintype "passive"))
      (node (ref "LED341") (pin "K") (pinfunction "C_K") (pintype "passive"))
      (node (ref "LED357") (pin "K") (pinfunction "C_K") (pintype "passive"))
      (node (ref "LED37") (pin "K") (pinfunction "C_K") (pintype "passive"))
      (node (ref "LED373") (pin "K") (pinfunction "C_K") (pintype "passive"))
      (node (ref "LED389") (pin "K") (pinfunction "C_K") (pintype "passive"))
      (node (ref "LED405") (pin "K") (pinfunction "C_K") (pintype "passive"))
      (node (ref "LED421") (pin "K") (pinfunction "C_K") (pintype "passive"))
      (node (ref "LED437") (pin "K") (pinfunction "C_K") (pintype "passive"))
      (node (ref "LED453") (pin "K") (pinfunction "C_K") (pintype "passive"))
      (node (ref "LED469") (pin "K") (pinfunction "C_K") (pintype "passive"))
      (node (ref "LED485") (pin "K") (pinfunction "C_K") (pintype "passive"))
      (node (ref "LED5") (pin "K") (pinfunction "C_K") (pintype "passive"))
      (node (ref "LED501") (pin "K") (pinfunction "C_K") (pintype "passive"))
      (node (ref "LED517") (pin "K") (pinfunction "C_K") (pintype "passive"))
      (node (ref "LED53") (pin "K") (pinfunction "C_K") (pintype "passive"))
      (node (ref "LED533") (pin "K") (pinfunction "C_K") (pintype "passive"))
      (node (ref "LED549") (pin "K") (pinfunction "C_K") (pintype "passive"))
      (node (ref "LED565") (pin "K") (pinfunction "C_K") (pintype "passive"))
      (node (ref "LED581") (pin "K") (pinfunction "C_K") (pintype "passive"))
      (node (ref "LED597") (pin "K") (pinfunction "C_K") (pintype "passive"))
      (node (ref "LED613") (pin "K") (pinfunction "C_K") (pintype "passive"))
      (node (ref "LED629") (pin "K") (pinfunction "C_K") (pintype "passive"))
      (node (ref "LED645") (pin "K") (pinfunction "C_K") (pintype "passive"))
      (node (ref "LED661") (pin "K") (pinfunction "C_K") (pintype "passive"))
      (node (ref "LED677") (pin "K") (pinfunction "C_K") (pintype "passive"))
      (node (ref "LED69") (pin "K") (pinfunction "C_K") (pintype "passive"))
      (node (ref "LED693") (pin "K") (pinfunction "C_K") (pintype "passive"))
      (node (ref "LED709") (pin "K") (pinfunction "C_K") (pintype "passive"))
      (node (ref "LED725") (pin "K") (pinfunction "C_K") (pintype "passive"))
      (node (ref "LED741") (pin "K") (pinfunction "C_K") (pintype "passive"))
      (node (ref "LED757") (pin "K") (pinfunction "C_K") (pintype "passive"))
      (node (ref "LED773") (pin "K") (pinfunction "C_K") (pintype "passive"))
      (node (ref "LED789") (pin "K") (pinfunction "C_K") (pintype "passive"))
      (node (ref "LED805") (pin "K") (pinfunction "C_K") (pintype "passive"))
      (node (ref "LED821") (pin "K") (pinfunction "C_K") (pintype "passive"))
      (node (ref "LED837") (pin "K") (pinfunction "C_K") (pintype "passive"))
      (node (ref "LED85") (pin "K") (pinfunction "C_K") (pintype "passive"))
      (node (ref "LED853") (pin "K") (pinfunction "C_K") (pintype "passive"))
      (node (ref "LED869") (pin "K") (pinfunction "C_K") (pintype "passive"))
      (node (ref "LED885") (pin "K") (pinfunction "C_K") (pintype "passive"))
      (node (ref "LED901") (pin "K") (pinfunction "C_K") (pintype "passive"))
      (node (ref "LED917") (pin "K") (pinfunction "C_K") (pintype "passive"))
      (node (ref "LED933") (pin "K") (pinfunction "C_K") (pintype "passive"))
      (node (ref "LED949") (pin "K") (pinfunction "C_K") (pintype "passive"))
      (node (ref "LED965") (pin "K") (pinfunction "C_K") (pintype "passive"))
      (node (ref "LED981") (pin "K") (pinfunction "C_K") (pintype "passive"))
      (node (ref "LED997") (pin "K") (pinfunction "C_K") (pintype "passive"))
      (node (ref "R5") (pin "1") (pinfunction "1_1") (pintype "passive"))
    )
    (net (code "128") (name "Net-(LED1000-C)") (class "Default")
      (node (ref "LED1000") (pin "K") (pinfunction "C_K") (pintype "passive"))
      (node (ref "LED1016") (pin "K") (pinfunction "C_K") (pintype "passive"))
      (node (ref "LED1032") (pin "K") (pinfunction "C_K") (pintype "passive"))
      (node (ref "LED104") (pin "K") (pinfunction "C_K") (pintype "passive"))
      (node (ref "LED1048") (pin "K") (pinfunction "C_K") (pintype "passive"))
      (node (ref "LED1064") (pin "K") (pinfunction "C_K") (pintype "passive"))
      (node (ref "LED1080") (pin "K") (pinfunction "C_K") (pintype "passive"))
      (node (ref "LED1096") (pin "K") (pinfunction "C_K") (pintype "passive"))
      (node (ref "LED1112") (pin "K") (pinfunction "C_K") (pintype "passive"))
      (node (ref "LED1128") (pin "K") (pinfunction "C_K") (pintype "passive"))
      (node (ref "LED1144") (pin "K") (pinfunction "C_K") (pintype "passive"))
      (node (ref "LED1160") (pin "K") (pinfunction "C_K") (pintype "passive"))
      (node (ref "LED1176") (pin "K") (pinfunction "C_K") (pintype "passive"))
      (node (ref "LED1192") (pin "K") (pinfunction "C_K") (pintype "passive"))
      (node (ref "LED120") (pin "K") (pinfunction "C_K") (pintype "passive"))
      (node (ref "LED1208") (pin "K") (pinfunction "C_K") (pintype "passive"))
      (node (ref "LED1224") (pin "K") (pinfunction "C_K") (pintype "passive"))
      (node (ref "LED1240") (pin "K") (pinfunction "C_K") (pintype "passive"))
      (node (ref "LED1256") (pin "K") (pinfunction "C_K") (pintype "passive"))
      (node (ref "LED1272") (pin "K") (pinfunction "C_K") (pintype "passive"))
      (node (ref "LED136") (pin "K") (pinfunction "C_K") (pintype "passive"))
      (node (ref "LED152") (pin "K") (pinfunction "C_K") (pintype "passive"))
      (node (ref "LED168") (pin "K") (pinfunction "C_K") (pintype "passive"))
      (node (ref "LED184") (pin "K") (pinfunction "C_K") (pintype "passive"))
      (node (ref "LED200") (pin "K") (pinfunction "C_K") (pintype "passive"))
      (node (ref "LED216") (pin "K") (pinfunction "C_K") (pintype "passive"))
      (node (ref "LED232") (pin "K") (pinfunction "C_K") (pintype "passive"))
      (node (ref "LED24") (pin "K") (pinfunction "C_K") (pintype "passive"))
      (node (ref "LED248") (pin "K") (pinfunction "C_K") (pintype "passive"))
      (node (ref "LED264") (pin "K") (pinfunction "C_K") (pintype "passive"))
      (node (ref "LED280") (pin "K") (pinfunction "C_K") (pintype "passive"))
      (node (ref "LED296") (pin "K") (pinfunction "C_K") (pintype "passive"))
      (node (ref "LED312") (pin "K") (pinfunction "C_K") (pintype "passive"))
      (node (ref "LED328") (pin "K") (pinfunction "C_K") (pintype "passive"))
      (node (ref "LED344") (pin "K") (pinfunction "C_K") (pintype "passive"))
      (node (ref "LED360") (pin "K") (pinfunction "C_K") (pintype "passive"))
      (node (ref "LED376") (pin "K") (pinfunction "C_K") (pintype "passive"))
      (node (ref "LED392") (pin "K") (pinfunction "C_K") (pintype "passive"))
      (node (ref "LED40") (pin "K") (pinfunction "C_K") (pintype "passive"))
      (node (ref "LED408") (pin "K") (pinfunction "C_K") (pintype "passive"))
      (node (ref "LED424") (pin "K") (pinfunction "C_K") (pintype "passive"))
      (node (ref "LED440") (pin "K") (pinfunction "C_K") (pintype "passive"))
      (node (ref "LED456") (pin "K") (pinfunction "C_K") (pintype "passive"))
      (node (ref "LED472") (pin "K") (pinfunction "C_K") (pintype "passive"))
      (node (ref "LED488") (pin "K") (pinfunction "C_K") (pintype "passive"))
      (node (ref "LED504") (pin "K") (pinfunction "C_K") (pintype "passive"))
      (node (ref "LED520") (pin "K") (pinfunction "C_K") (pintype "passive"))
      (node (ref "LED536") (pin "K") (pinfunction "C_K") (pintype "passive"))
      (node (ref "LED552") (pin "K") (pinfunction "C_K") (pintype "passive"))
      (node (ref "LED56") (pin "K") (pinfunction "C_K") (pintype "passive"))
      (node (ref "LED568") (pin "K") (pinfunction "C_K") (pintype "passive"))
      (node (ref "LED584") (pin "K") (pinfunction "C_K") (pintype "passive"))
      (node (ref "LED600") (pin "K") (pinfunction "C_K") (pintype "passive"))
      (node (ref "LED616") (pin "K") (pinfunction "C_K") (pintype "passive"))
      (node (ref "LED632") (pin "K") (pinfunction "C_K") (pintype "passive"))
      (node (ref "LED648") (pin "K") (pinfunction "C_K") (pintype "passive"))
      (node (ref "LED664") (pin "K") (pinfunction "C_K") (pintype "passive"))
      (node (ref "LED680") (pin "K") (pinfunction "C_K") (pintype "passive"))
      (node (ref "LED696") (pin "K") (pinfunction "C_K") (pintype "passive"))
      (node (ref "LED712") (pin "K") (pinfunction "C_K") (pintype "passive"))
      (node (ref "LED72") (pin "K") (pinfunction "C_K") (pintype "passive"))
      (node (ref "LED728") (pin "K") (pinfunction "C_K") (pintype "passive"))
      (node (ref "LED744") (pin "K") (pinfunction "C_K") (pintype "passive"))
      (node (ref "LED760") (pin "K") (pinfunction "C_K") (pintype "passive"))
      (node (ref "LED776") (pin "K") (pinfunction "C_K") (pintype "passive"))
      (node (ref "LED792") (pin "K") (pinfunction "C_K") (pintype "passive"))
      (node (ref "LED8") (pin "K") (pinfunction "C_K") (pintype "passive"))
      (node (ref "LED808") (pin "K") (pinfunction "C_K") (pintype "passive"))
      (node (ref "LED824") (pin "K") (pinfunction "C_K") (pintype "passive"))
      (node (ref "LED840") (pin "K") (pinfunction "C_K") (pintype "passive"))
      (node (ref "LED856") (pin "K") (pinfunction "C_K") (pintype "passive"))
      (node (ref "LED872") (pin "K") (pinfunction "C_K") (pintype "passive"))
      (node (ref "LED88") (pin "K") (pinfunction "C_K") (pintype "passive"))
      (node (ref "LED888") (pin "K") (pinfunction "C_K") (pintype "passive"))
      (node (ref "LED904") (pin "K") (pinfunction "C_K") (pintype "passive"))
      (node (ref "LED920") (pin "K") (pinfunction "C_K") (pintype "passive"))
      (node (ref "LED936") (pin "K") (pinfunction "C_K") (pintype "passive"))
      (node (ref "LED952") (pin "K") (pinfunction "C_K") (pintype "passive"))
      (node (ref "LED968") (pin "K") (pinfunction "C_K") (pintype "passive"))
      (node (ref "LED984") (pin "K") (pinfunction "C_K") (pintype "passive"))
      (node (ref "R8") (pin "1") (pinfunction "1_1") (pintype "passive"))
    )
    (net (code "129") (name "Net-(LED1001-C)") (class "Default")
      (node (ref "LED1001") (pin "K") (pinfunction "C_K") (pintype "passive"))
      (node (ref "LED1017") (pin "K") (pinfunction "C_K") (pintype "passive"))
      (node (ref "LED1033") (pin "K") (pinfunction "C_K") (pintype "passive"))
      (node (ref "LED1049") (pin "K") (pinfunction "C_K") (pintype "passive"))
      (node (ref "LED105") (pin "K") (pinfunction "C_K") (pintype "passive"))
      (node (ref "LED1065") (pin "K") (pinfunction "C_K") (pintype "passive"))
      (node (ref "LED1081") (pin "K") (pinfunction "C_K") (pintype "passive"))
      (node (ref "LED1097") (pin "K") (pinfunction "C_K") (pintype "passive"))
      (node (ref "LED1113") (pin "K") (pinfunction "C_K") (pintype "passive"))
      (node (ref "LED1129") (pin "K") (pinfunction "C_K") (pintype "passive"))
      (node (ref "LED1145") (pin "K") (pinfunction "C_K") (pintype "passive"))
      (node (ref "LED1161") (pin "K") (pinfunction "C_K") (pintype "passive"))
      (node (ref "LED1177") (pin "K") (pinfunction "C_K") (pintype "passive"))
      (node (ref "LED1193") (pin "K") (pinfunction "C_K") (pintype "passive"))
      (node (ref "LED1209") (pin "K") (pinfunction "C_K") (pintype "passive"))
      (node (ref "LED121") (pin "K") (pinfunction "C_K") (pintype "passive"))
      (node (ref "LED1225") (pin "K") (pinfunction "C_K") (pintype "passive"))
      (node (ref "LED1241") (pin "K") (pinfunction "C_K") (pintype "passive"))
      (node (ref "LED1257") (pin "K") (pinfunction "C_K") (pintype "passive"))
      (node (ref "LED1273") (pin "K") (pinfunction "C_K") (pintype "passive"))
      (node (ref "LED137") (pin "K") (pinfunction "C_K") (pintype "passive"))
      (node (ref "LED153") (pin "K") (pinfunction "C_K") (pintype "passive"))
      (node (ref "LED169") (pin "K") (pinfunction "C_K") (pintype "passive"))
      (node (ref "LED185") (pin "K") (pinfunction "C_K") (pintype "passive"))
      (node (ref "LED201") (pin "K") (pinfunction "C_K") (pintype "passive"))
      (node (ref "LED217") (pin "K") (pinfunction "C_K") (pintype "passive"))
      (node (ref "LED233") (pin "K") (pinfunction "C_K") (pintype "passive"))
      (node (ref "LED249") (pin "K") (pinfunction "C_K") (pintype "passive"))
      (node (ref "LED25") (pin "K") (pinfunction "C_K") (pintype "passive"))
      (node (ref "LED265") (pin "K") (pinfunction "C_K") (pintype "passive"))
      (node (ref "LED281") (pin "K") (pinfunction "C_K") (pintype "passive"))
      (node (ref "LED297") (pin "K") (pinfunction "C_K") (pintype "passive"))
      (node (ref "LED313") (pin "K") (pinfunction "C_K") (pintype "passive"))
      (node (ref "LED329") (pin "K") (pinfunction "C_K") (pintype "passive"))
      (node (ref "LED345") (pin "K") (pinfunction "C_K") (pintype "passive"))
      (node (ref "LED361") (pin "K") (pinfunction "C_K") (pintype "passive"))
      (node (ref "LED377") (pin "K") (pinfunction "C_K") (pintype "passive"))
      (node (ref "LED393") (pin "K") (pinfunction "C_K") (pintype "passive"))
      (node (ref "LED409") (pin "K") (pinfunction "C_K") (pintype "passive"))
      (node (ref "LED41") (pin "K") (pinfunction "C_K") (pintype "passive"))
      (node (ref "LED425") (pin "K") (pinfunction "C_K") (pintype "passive"))
      (node (ref "LED441") (pin "K") (pinfunction "C_K") (pintype "passive"))
      (node (ref "LED457") (pin "K") (pinfunction "C_K") (pintype "passive"))
      (node (ref "LED473") (pin "K") (pinfunction "C_K") (pintype "passive"))
      (node (ref "LED489") (pin "K") (pinfunction "C_K") (pintype "passive"))
      (node (ref "LED505") (pin "K") (pinfunction "C_K") (pintype "passive"))
      (node (ref "LED521") (pin "K") (pinfunction "C_K") (pintype "passive"))
      (node (ref "LED537") (pin "K") (pinfunction "C_K") (pintype "passive"))
      (node (ref "LED553") (pin "K") (pinfunction "C_K") (pintype "passive"))
      (node (ref "LED569") (pin "K") (pinfunction "C_K") (pintype "passive"))
      (node (ref "LED57") (pin "K") (pinfunction "C_K") (pintype "passive"))
      (node (ref "LED585") (pin "K") (pinfunction "C_K") (pintype "passive"))
      (node (ref "LED601") (pin "K") (pinfunction "C_K") (pintype "passive"))
      (node (ref "LED617") (pin "K") (pinfunction "C_K") (pintype "passive"))
      (node (ref "LED633") (pin "K") (pinfunction "C_K") (pintype "passive"))
      (node (ref "LED649") (pin "K") (pinfunction "C_K") (pintype "passive"))
      (node (ref "LED665") (pin "K") (pinfunction "C_K") (pintype "passive"))
      (node (ref "LED681") (pin "K") (pinfunction "C_K") (pintype "passive"))
      (node (ref "LED697") (pin "K") (pinfunction "C_K") (pintype "passive"))
      (node (ref "LED713") (pin "K") (pinfunction "C_K") (pintype "passive"))
      (node (ref "LED729") (pin "K") (pinfunction "C_K") (pintype "passive"))
      (node (ref "LED73") (pin "K") (pinfunction "C_K") (pintype "passive"))
      (node (ref "LED745") (pin "K") (pinfunction "C_K") (pintype "passive"))
      (node (ref "LED761") (pin "K") (pinfunction "C_K") (pintype "passive"))
      (node (ref "LED777") (pin "K") (pinfunction "C_K") (pintype "passive"))
      (node (ref "LED793") (pin "K") (pinfunction "C_K") (pintype "passive"))
      (node (ref "LED809") (pin "K") (pinfunction "C_K") (pintype "passive"))
      (node (ref "LED825") (pin "K") (pinfunction "C_K") (pintype "passive"))
      (node (ref "LED841") (pin "K") (pinfunction "C_K") (pintype "passive"))
      (node (ref "LED857") (pin "K") (pinfunction "C_K") (pintype "passive"))
      (node (ref "LED873") (pin "K") (pinfunction "C_K") (pintype "passive"))
      (node (ref "LED889") (pin "K") (pinfunction "C_K") (pintype "passive"))
      (node (ref "LED89") (pin "K") (pinfunction "C_K") (pintype "passive"))
      (node (ref "LED9") (pin "K") (pinfunction "C_K") (pintype "passive"))
      (node (ref "LED905") (pin "K") (pinfunction "C_K") (pintype "passive"))
      (node (ref "LED921") (pin "K") (pinfunction "C_K") (pintype "passive"))
      (node (ref "LED937") (pin "K") (pinfunction "C_K") (pintype "passive"))
      (node (ref "LED953") (pin "K") (pinfunction "C_K") (pintype "passive"))
      (node (ref "LED969") (pin "K") (pinfunction "C_K") (pintype "passive"))
      (node (ref "LED985") (pin "K") (pinfunction "C_K") (pintype "passive"))
      (node (ref "R9") (pin "1") (pinfunction "1_1") (pintype "passive"))
    )
    (net (code "130") (name "Net-(LED1003-C)") (class "Default")
      (node (ref "LED1003") (pin "K") (pinfunction "C_K") (pintype "passive"))
      (node (ref "LED1019") (pin "K") (pinfunction "C_K") (pintype "passive"))
      (node (ref "LED1035") (pin "K") (pinfunction "C_K") (pintype "passive"))
      (node (ref "LED1051") (pin "K") (pinfunction "C_K") (pintype "passive"))
      (node (ref "LED1067") (pin "K") (pinfunction "C_K") (pintype "passive"))
      (node (ref "LED107") (pin "K") (pinfunction "C_K") (pintype "passive"))
      (node (ref "LED1083") (pin "K") (pinfunction "C_K") (pintype "passive"))
      (node (ref "LED1099") (pin "K") (pinfunction "C_K") (pintype "passive"))
      (node (ref "LED11") (pin "K") (pinfunction "C_K") (pintype "passive"))
      (node (ref "LED1115") (pin "K") (pinfunction "C_K") (pintype "passive"))
      (node (ref "LED1131") (pin "K") (pinfunction "C_K") (pintype "passive"))
      (node (ref "LED1147") (pin "K") (pinfunction "C_K") (pintype "passive"))
      (node (ref "LED1163") (pin "K") (pinfunction "C_K") (pintype "passive"))
      (node (ref "LED1179") (pin "K") (pinfunction "C_K") (pintype "passive"))
      (node (ref "LED1195") (pin "K") (pinfunction "C_K") (pintype "passive"))
      (node (ref "LED1211") (pin "K") (pinfunction "C_K") (pintype "passive"))
      (node (ref "LED1227") (pin "K") (pinfunction "C_K") (pintype "passive"))
      (node (ref "LED123") (pin "K") (pinfunction "C_K") (pintype "passive"))
      (node (ref "LED1243") (pin "K") (pinfunction "C_K") (pintype "passive"))
      (node (ref "LED1259") (pin "K") (pinfunction "C_K") (pintype "passive"))
      (node (ref "LED1275") (pin "K") (pinfunction "C_K") (pintype "passive"))
      (node (ref "LED139") (pin "K") (pinfunction "C_K") (pintype "passive"))
      (node (ref "LED155") (pin "K") (pinfunction "C_K") (pintype "passive"))
      (node (ref "LED171") (pin "K") (pinfunction "C_K") (pintype "passive"))
      (node (ref "LED187") (pin "K") (pinfunction "C_K") (pintype "passive"))
      (node (ref "LED203") (pin "K") (pinfunction "C_K") (pintype "passive"))
      (node (ref "LED219") (pin "K") (pinfunction "C_K") (pintype "passive"))
      (node (ref "LED235") (pin "K") (pinfunction "C_K") (pintype "passive"))
      (node (ref "LED251") (pin "K") (pinfunction "C_K") (pintype "passive"))
      (node (ref "LED267") (pin "K") (pinfunction "C_K") (pintype "passive"))
      (node (ref "LED27") (pin "K") (pinfunction "C_K") (pintype "passive"))
      (node (ref "LED283") (pin "K") (pinfunction "C_K") (pintype "passive"))
      (node (ref "LED299") (pin "K") (pinfunction "C_K") (pintype "passive"))
      (node (ref "LED315") (pin "K") (pinfunction "C_K") (pintype "passive"))
      (node (ref "LED331") (pin "K") (pinfunction "C_K") (pintype "passive"))
      (node (ref "LED347") (pin "K") (pinfunction "C_K") (pintype "passive"))
      (node (ref "LED363") (pin "K") (pinfunction "C_K") (pintype "passive"))
      (node (ref "LED379") (pin "K") (pinfunction "C_K") (pintype "passive"))
      (node (ref "LED395") (pin "K") (pinfunction "C_K") (pintype "passive"))
      (node (ref "LED411") (pin "K") (pinfunction "C_K") (pintype "passive"))
      (node (ref "LED427") (pin "K") (pinfunction "C_K") (pintype "passive"))
      (node (ref "LED43") (pin "K") (pinfunction "C_K") (pintype "passive"))
      (node (ref "LED443") (pin "K") (pinfunction "C_K") (pintype "passive"))
      (node (ref "LED459") (pin "K") (pinfunction "C_K") (pintype "passive"))
      (node (ref "LED475") (pin "K") (pinfunction "C_K") (pintype "passive"))
      (node (ref "LED491") (pin "K") (pinfunction "C_K") (pintype "passive"))
      (node (ref "LED507") (pin "K") (pinfunction "C_K") (pintype "passive"))
      (node (ref "LED523") (pin "K") (pinfunction "C_K") (pintype "passive"))
      (node (ref "LED539") (pin "K") (pinfunction "C_K") (pintype "passive"))
      (node (ref "LED555") (pin "K") (pinfunction "C_K") (pintype "passive"))
      (node (ref "LED571") (pin "K") (pinfunction "C_K") (pintype "passive"))
      (node (ref "LED587") (pin "K") (pinfunction "C_K") (pintype "passive"))
      (node (ref "LED59") (pin "K") (pinfunction "C_K") (pintype "passive"))
      (node (ref "LED603") (pin "K") (pinfunction "C_K") (pintype "passive"))
      (node (ref "LED619") (pin "K") (pinfunction "C_K") (pintype "passive"))
      (node (ref "LED635") (pin "K") (pinfunction "C_K") (pintype "passive"))
      (node (ref "LED651") (pin "K") (pinfunction "C_K") (pintype "passive"))
      (node (ref "LED667") (pin "K") (pinfunction "C_K") (pintype "passive"))
      (node (ref "LED683") (pin "K") (pinfunction "C_K") (pintype "passive"))
      (node (ref "LED699") (pin "K") (pinfunction "C_K") (pintype "passive"))
      (node (ref "LED715") (pin "K") (pinfunction "C_K") (pintype "passive"))
      (node (ref "LED731") (pin "K") (pinfunction "C_K") (pintype "passive"))
      (node (ref "LED747") (pin "K") (pinfunction "C_K") (pintype "passive"))
      (node (ref "LED75") (pin "K") (pinfunction "C_K") (pintype "passive"))
      (node (ref "LED763") (pin "K") (pinfunction "C_K") (pintype "passive"))
      (node (ref "LED779") (pin "K") (pinfunction "C_K") (pintype "passive"))
      (node (ref "LED795") (pin "K") (pinfunction "C_K") (pintype "passive"))
      (node (ref "LED811") (pin "K") (pinfunction "C_K") (pintype "passive"))
      (node (ref "LED827") (pin "K") (pinfunction "C_K") (pintype "passive"))
      (node (ref "LED843") (pin "K") (pinfunction "C_K") (pintype "passive"))
      (node (ref "LED859") (pin "K") (pinfunction "C_K") (pintype "passive"))
      (node (ref "LED875") (pin "K") (pinfunction "C_K") (pintype "passive"))
      (node (ref "LED891") (pin "K") (pinfunction "C_K") (pintype "passive"))
      (node (ref "LED907") (pin "K") (pinfunction "C_K") (pintype "passive"))
      (node (ref "LED91") (pin "K") (pinfunction "C_K") (pintype "passive"))
      (node (ref "LED923") (pin "K") (pinfunction "C_K") (pintype "passive"))
      (node (ref "LED939") (pin "K") (pinfunction "C_K") (pintype "passive"))
      (node (ref "LED955") (pin "K") (pinfunction "C_K") (pintype "passive"))
      (node (ref "LED971") (pin "K") (pinfunction "C_K") (pintype "passive"))
      (node (ref "LED987") (pin "K") (pinfunction "C_K") (pintype "passive"))
      (node (ref "R11") (pin "1") (pinfunction "1_1") (pintype "passive"))
    )
    (net (code "131") (name "Net-(LED1004-C)") (class "Default")
      (node (ref "LED1004") (pin "K") (pinfunction "C_K") (pintype "passive"))
      (node (ref "LED1020") (pin "K") (pinfunction "C_K") (pintype "passive"))
      (node (ref "LED1036") (pin "K") (pinfunction "C_K") (pintype "passive"))
      (node (ref "LED1052") (pin "K") (pinfunction "C_K") (pintype "passive"))
      (node (ref "LED1068") (pin "K") (pinfunction "C_K") (pintype "passive"))
      (node (ref "LED108") (pin "K") (pinfunction "C_K") (pintype "passive"))
      (node (ref "LED1084") (pin "K") (pinfunction "C_K") (pintype "passive"))
      (node (ref "LED1100") (pin "K") (pinfunction "C_K") (pintype "passive"))
      (node (ref "LED1116") (pin "K") (pinfunction "C_K") (pintype "passive"))
      (node (ref "LED1132") (pin "K") (pinfunction "C_K") (pintype "passive"))
      (node (ref "LED1148") (pin "K") (pinfunction "C_K") (pintype "passive"))
      (node (ref "LED1164") (pin "K") (pinfunction "C_K") (pintype "passive"))
      (node (ref "LED1180") (pin "K") (pinfunction "C_K") (pintype "passive"))
      (node (ref "LED1196") (pin "K") (pinfunction "C_K") (pintype "passive"))
      (node (ref "LED12") (pin "K") (pinfunction "C_K") (pintype "passive"))
      (node (ref "LED1212") (pin "K") (pinfunction "C_K") (pintype "passive"))
      (node (ref "LED1228") (pin "K") (pinfunction "C_K") (pintype "passive"))
      (node (ref "LED124") (pin "K") (pinfunction "C_K") (pintype "passive"))
      (node (ref "LED1244") (pin "K") (pinfunction "C_K") (pintype "passive"))
      (node (ref "LED1260") (pin "K") (pinfunction "C_K") (pintype "passive"))
      (node (ref "LED1276") (pin "K") (pinfunction "C_K") (pintype "passive"))
      (node (ref "LED140") (pin "K") (pinfunction "C_K") (pintype "passive"))
      (node (ref "LED156") (pin "K") (pinfunction "C_K") (pintype "passive"))
      (node (ref "LED172") (pin "K") (pinfunction "C_K") (pintype "passive"))
      (node (ref "LED188") (pin "K") (pinfunction "C_K") (pintype "passive"))
      (node (ref "LED204") (pin "K") (pinfunction "C_K") (pintype "passive"))
      (node (ref "LED220") (pin "K") (pinfunction "C_K") (pintype "passive"))
      (node (ref "LED236") (pin "K") (pinfunction "C_K") (pintype "passive"))
      (node (ref "LED252") (pin "K") (pinfunction "C_K") (pintype "passive"))
      (node (ref "LED268") (pin "K") (pinfunction "C_K") (pintype "passive"))
      (node (ref "LED28") (pin "K") (pinfunction "C_K") (pintype "passive"))
      (node (ref "LED284") (pin "K") (pinfunction "C_K") (pintype "passive"))
      (node (ref "LED300") (pin "K") (pinfunction "C_K") (pintype "passive"))
      (node (ref "LED316") (pin "K") (pinfunction "C_K") (pintype "passive"))
      (node (ref "LED332") (pin "K") (pinfunction "C_K") (pintype "passive"))
      (node (ref "LED348") (pin "K") (pinfunction "C_K") (pintype "passive"))
      (node (ref "LED364") (pin "K") (pinfunction "C_K") (pintype "passive"))
      (node (ref "LED380") (pin "K") (pinfunction "C_K") (pintype "passive"))
      (node (ref "LED396") (pin "K") (pinfunction "C_K") (pintype "passive"))
      (node (ref "LED412") (pin "K") (pinfunction "C_K") (pintype "passive"))
      (node (ref "LED428") (pin "K") (pinfunction "C_K") (pintype "passive"))
      (node (ref "LED44") (pin "K") (pinfunction "C_K") (pintype "passive"))
      (node (ref "LED444") (pin "K") (pinfunction "C_K") (pintype "passive"))
      (node (ref "LED460") (pin "K") (pinfunction "C_K") (pintype "passive"))
      (node (ref "LED476") (pin "K") (pinfunction "C_K") (pintype "passive"))
      (node (ref "LED492") (pin "K") (pinfunction "C_K") (pintype "passive"))
      (node (ref "LED508") (pin "K") (pinfunction "C_K") (pintype "passive"))
      (node (ref "LED524") (pin "K") (pinfunction "C_K") (pintype "passive"))
      (node (ref "LED540") (pin "K") (pinfunction "C_K") (pintype "passive"))
      (node (ref "LED556") (pin "K") (pinfunction "C_K") (pintype "passive"))
      (node (ref "LED572") (pin "K") (pinfunction "C_K") (pintype "passive"))
      (node (ref "LED588") (pin "K") (pinfunction "C_K") (pintype "passive"))
      (node (ref "LED60") (pin "K") (pinfunction "C_K") (pintype "passive"))
      (node (ref "LED604") (pin "K") (pinfunction "C_K") (pintype "passive"))
      (node (ref "LED620") (pin "K") (pinfunction "C_K") (pintype "passive"))
      (node (ref "LED636") (pin "K") (pinfunction "C_K") (pintype "passive"))
      (node (ref "LED652") (pin "K") (pinfunction "C_K") (pintype "passive"))
      (node (ref "LED668") (pin "K") (pinfunction "C_K") (pintype "passive"))
      (node (ref "LED684") (pin "K") (pinfunction "C_K") (pintype "passive"))
      (node (ref "LED700") (pin "K") (pinfunction "C_K") (pintype "passive"))
      (node (ref "LED716") (pin "K") (pinfunction "C_K") (pintype "passive"))
      (node (ref "LED732") (pin "K") (pinfunction "C_K") (pintype "passive"))
      (node (ref "LED748") (pin "K") (pinfunction "C_K") (pintype "passive"))
      (node (ref "LED76") (pin "K") (pinfunction "C_K") (pintype "passive"))
      (node (ref "LED764") (pin "K") (pinfunction "C_K") (pintype "passive"))
      (node (ref "LED780") (pin "K") (pinfunction "C_K") (pintype "passive"))
      (node (ref "LED796") (pin "K") (pinfunction "C_K") (pintype "passive"))
      (node (ref "LED812") (pin "K") (pinfunction "C_K") (pintype "passive"))
      (node (ref "LED828") (pin "K") (pinfunction "C_K") (pintype "passive"))
      (node (ref "LED844") (pin "K") (pinfunction "C_K") (pintype "passive"))
      (node (ref "LED860") (pin "K") (pinfunction "C_K") (pintype "passive"))
      (node (ref "LED876") (pin "K") (pinfunction "C_K") (pintype "passive"))
      (node (ref "LED892") (pin "K") (pinfunction "C_K") (pintype "passive"))
      (node (ref "LED908") (pin "K") (pinfunction "C_K") (pintype "passive"))
      (node (ref "LED92") (pin "K") (pinfunction "C_K") (pintype "passive"))
      (node (ref "LED924") (pin "K") (pinfunction "C_K") (pintype "passive"))
      (node (ref "LED940") (pin "K") (pinfunction "C_K") (pintype "passive"))
      (node (ref "LED956") (pin "K") (pinfunction "C_K") (pintype "passive"))
      (node (ref "LED972") (pin "K") (pinfunction "C_K") (pintype "passive"))
      (node (ref "LED988") (pin "K") (pinfunction "C_K") (pintype "passive"))
      (node (ref "R12") (pin "1") (pinfunction "1_1") (pintype "passive"))
    )
    (net (code "132") (name "Net-(LED1005-C)") (class "Default")
      (node (ref "LED1005") (pin "K") (pinfunction "C_K") (pintype "passive"))
      (node (ref "LED1021") (pin "K") (pinfunction "C_K") (pintype "passive"))
      (node (ref "LED1037") (pin "K") (pinfunction "C_K") (pintype "passive"))
      (node (ref "LED1053") (pin "K") (pinfunction "C_K") (pintype "passive"))
      (node (ref "LED1069") (pin "K") (pinfunction "C_K") (pintype "passive"))
      (node (ref "LED1085") (pin "K") (pinfunction "C_K") (pintype "passive"))
      (node (ref "LED109") (pin "K") (pinfunction "C_K") (pintype "passive"))
      (node (ref "LED1101") (pin "K") (pinfunction "C_K") (pintype "passive"))
      (node (ref "LED1117") (pin "K") (pinfunction "C_K") (pintype "passive"))
      (node (ref "LED1133") (pin "K") (pinfunction "C_K") (pintype "passive"))
      (node (ref "LED1149") (pin "K") (pinfunction "C_K") (pintype "passive"))
      (node (ref "LED1165") (pin "K") (pinfunction "C_K") (pintype "passive"))
      (node (ref "LED1181") (pin "K") (pinfunction "C_K") (pintype "passive"))
      (node (ref "LED1197") (pin "K") (pinfunction "C_K") (pintype "passive"))
      (node (ref "LED1213") (pin "K") (pinfunction "C_K") (pintype "passive"))
      (node (ref "LED1229") (pin "K") (pinfunction "C_K") (pintype "passive"))
      (node (ref "LED1245") (pin "K") (pinfunction "C_K") (pintype "passive"))
      (node (ref "LED125") (pin "K") (pinfunction "C_K") (pintype "passive"))
      (node (ref "LED1261") (pin "K") (pinfunction "C_K") (pintype "passive"))
      (node (ref "LED1277") (pin "K") (pinfunction "C_K") (pintype "passive"))
      (node (ref "LED13") (pin "K") (pinfunction "C_K") (pintype "passive"))
      (node (ref "LED141") (pin "K") (pinfunction "C_K") (pintype "passive"))
      (node (ref "LED157") (pin "K") (pinfunction "C_K") (pintype "passive"))
      (node (ref "LED173") (pin "K") (pinfunction "C_K") (pintype "passive"))
      (node (ref "LED189") (pin "K") (pinfunction "C_K") (pintype "passive"))
      (node (ref "LED205") (pin "K") (pinfunction "C_K") (pintype "passive"))
      (node (ref "LED221") (pin "K") (pinfunction "C_K") (pintype "passive"))
      (node (ref "LED237") (pin "K") (pinfunction "C_K") (pintype "passive"))
      (node (ref "LED253") (pin "K") (pinfunction "C_K") (pintype "passive"))
      (node (ref "LED269") (pin "K") (pinfunction "C_K") (pintype "passive"))
      (node (ref "LED285") (pin "K") (pinfunction "C_K") (pintype "passive"))
      (node (ref "LED29") (pin "K") (pinfunction "C_K") (pintype "passive"))
      (node (ref "LED301") (pin "K") (pinfunction "C_K") (pintype "passive"))
      (node (ref "LED317") (pin "K") (pinfunction "C_K") (pintype "passive"))
      (node (ref "LED333") (pin "K") (pinfunction "C_K") (pintype "passive"))
      (node (ref "LED349") (pin "K") (pinfunction "C_K") (pintype "passive"))
      (node (ref "LED365") (pin "K") (pinfunction "C_K") (pintype "passive"))
      (node (ref "LED381") (pin "K") (pinfunction "C_K") (pintype "passive"))
      (node (ref "LED397") (pin "K") (pinfunction "C_K") (pintype "passive"))
      (node (ref "LED413") (pin "K") (pinfunction "C_K") (pintype "passive"))
      (node (ref "LED429") (pin "K") (pinfunction "C_K") (pintype "passive"))
      (node (ref "LED445") (pin "K") (pinfunction "C_K") (pintype "passive"))
      (node (ref "LED45") (pin "K") (pinfunction "C_K") (pintype "passive"))
      (node (ref "LED461") (pin "K") (pinfunction "C_K") (pintype "passive"))
      (node (ref "LED477") (pin "K") (pinfunction "C_K") (pintype "passive"))
      (node (ref "LED493") (pin "K") (pinfunction "C_K") (pintype "passive"))
      (node (ref "LED509") (pin "K") (pinfunction "C_K") (pintype "passive"))
      (node (ref "LED525") (pin "K") (pinfunction "C_K") (pintype "passive"))
      (node (ref "LED541") (pin "K") (pinfunction "C_K") (pintype "passive"))
      (node (ref "LED557") (pin "K") (pinfunction "C_K") (pintype "passive"))
      (node (ref "LED573") (pin "K") (pinfunction "C_K") (pintype "passive"))
      (node (ref "LED589") (pin "K") (pinfunction "C_K") (pintype "passive"))
      (node (ref "LED605") (pin "K") (pinfunction "C_K") (pintype "passive"))
      (node (ref "LED61") (pin "K") (pinfunction "C_K") (pintype "passive"))
      (node (ref "LED621") (pin "K") (pinfunction "C_K") (pintype "passive"))
      (node (ref "LED637") (pin "K") (pinfunction "C_K") (pintype "passive"))
      (node (ref "LED653") (pin "K") (pinfunction "C_K") (pintype "passive"))
      (node (ref "LED669") (pin "K") (pinfunction "C_K") (pintype "passive"))
      (node (ref "LED685") (pin "K") (pinfunction "C_K") (pintype "passive"))
      (node (ref "LED701") (pin "K") (pinfunction "C_K") (pintype "passive"))
      (node (ref "LED717") (pin "K") (pinfunction "C_K") (pintype "passive"))
      (node (ref "LED733") (pin "K") (pinfunction "C_K") (pintype "passive"))
      (node (ref "LED749") (pin "K") (pinfunction "C_K") (pintype "passive"))
      (node (ref "LED765") (pin "K") (pinfunction "C_K") (pintype "passive"))
      (node (ref "LED77") (pin "K") (pinfunction "C_K") (pintype "passive"))
      (node (ref "LED781") (pin "K") (pinfunction "C_K") (pintype "passive"))
      (node (ref "LED797") (pin "K") (pinfunction "C_K") (pintype "passive"))
      (node (ref "LED813") (pin "K") (pinfunction "C_K") (pintype "passive"))
      (node (ref "LED829") (pin "K") (pinfunction "C_K") (pintype "passive"))
      (node (ref "LED845") (pin "K") (pinfunction "C_K") (pintype "passive"))
      (node (ref "LED861") (pin "K") (pinfunction "C_K") (pintype "passive"))
      (node (ref "LED877") (pin "K") (pinfunction "C_K") (pintype "passive"))
      (node (ref "LED893") (pin "K") (pinfunction "C_K") (pintype "passive"))
      (node (ref "LED909") (pin "K") (pinfunction "C_K") (pintype "passive"))
      (node (ref "LED925") (pin "K") (pinfunction "C_K") (pintype "passive"))
      (node (ref "LED93") (pin "K") (pinfunction "C_K") (pintype "passive"))
      (node (ref "LED941") (pin "K") (pinfunction "C_K") (pintype "passive"))
      (node (ref "LED957") (pin "K") (pinfunction "C_K") (pintype "passive"))
      (node (ref "LED973") (pin "K") (pinfunction "C_K") (pintype "passive"))
      (node (ref "LED989") (pin "K") (pinfunction "C_K") (pintype "passive"))
      (node (ref "R13") (pin "1") (pinfunction "1_1") (pintype "passive"))
    )
    (net (code "133") (name "Net-(LED1006-C)") (class "Default")
      (node (ref "LED1006") (pin "K") (pinfunction "C_K") (pintype "passive"))
      (node (ref "LED1022") (pin "K") (pinfunction "C_K") (pintype "passive"))
      (node (ref "LED1038") (pin "K") (pinfunction "C_K") (pintype "passive"))
      (node (ref "LED1054") (pin "K") (pinfunction "C_K") (pintype "passive"))
      (node (ref "LED1070") (pin "K") (pinfunction "C_K") (pintype "passive"))
      (node (ref "LED1086") (pin "K") (pinfunction "C_K") (pintype "passive"))
      (node (ref "LED110") (pin "K") (pinfunction "C_K") (pintype "passive"))
      (node (ref "LED1102") (pin "K") (pinfunction "C_K") (pintype "passive"))
      (node (ref "LED1118") (pin "K") (pinfunction "C_K") (pintype "passive"))
      (node (ref "LED1134") (pin "K") (pinfunction "C_K") (pintype "passive"))
      (node (ref "LED1150") (pin "K") (pinfunction "C_K") (pintype "passive"))
      (node (ref "LED1166") (pin "K") (pinfunction "C_K") (pintype "passive"))
      (node (ref "LED1182") (pin "K") (pinfunction "C_K") (pintype "passive"))
      (node (ref "LED1198") (pin "K") (pinfunction "C_K") (pintype "passive"))
      (node (ref "LED1214") (pin "K") (pinfunction "C_K") (pintype "passive"))
      (node (ref "LED1230") (pin "K") (pinfunction "C_K") (pintype "passive"))
      (node (ref "LED1246") (pin "K") (pinfunction "C_K") (pintype "passive"))
      (node (ref "LED126") (pin "K") (pinfunction "C_K") (pintype "passive"))
      (node (ref "LED1262") (pin "K") (pinfunction "C_K") (pintype "passive"))
      (node (ref "LED1278") (pin "K") (pinfunction "C_K") (pintype "passive"))
      (node (ref "LED14") (pin "K") (pinfunction "C_K") (pintype "passive"))
      (node (ref "LED142") (pin "K") (pinfunction "C_K") (pintype "passive"))
      (node (ref "LED158") (pin "K") (pinfunction "C_K") (pintype "passive"))
      (node (ref "LED174") (pin "K") (pinfunction "C_K") (pintype "passive"))
      (node (ref "LED190") (pin "K") (pinfunction "C_K") (pintype "passive"))
      (node (ref "LED206") (pin "K") (pinfunction "C_K") (pintype "passive"))
      (node (ref "LED222") (pin "K") (pinfunction "C_K") (pintype "passive"))
      (node (ref "LED238") (pin "K") (pinfunction "C_K") (pintype "passive"))
      (node (ref "LED254") (pin "K") (pinfunction "C_K") (pintype "passive"))
      (node (ref "LED270") (pin "K") (pinfunction "C_K") (pintype "passive"))
      (node (ref "LED286") (pin "K") (pinfunction "C_K") (pintype "passive"))
      (node (ref "LED30") (pin "K") (pinfunction "C_K") (pintype "passive"))
      (node (ref "LED302") (pin "K") (pinfunction "C_K") (pintype "passive"))
      (node (ref "LED318") (pin "K") (pinfunction "C_K") (pintype "passive"))
      (node (ref "LED334") (pin "K") (pinfunction "C_K") (pintype "passive"))
      (node (ref "LED350") (pin "K") (pinfunction "C_K") (pintype "passive"))
      (node (ref "LED366") (pin "K") (pinfunction "C_K") (pintype "passive"))
      (node (ref "LED382") (pin "K") (pinfunction "C_K") (pintype "passive"))
      (node (ref "LED398") (pin "K") (pinfunction "C_K") (pintype "passive"))
      (node (ref "LED414") (pin "K") (pinfunction "C_K") (pintype "passive"))
      (node (ref "LED430") (pin "K") (pinfunction "C_K") (pintype "passive"))
      (node (ref "LED446") (pin "K") (pinfunction "C_K") (pintype "passive"))
      (node (ref "LED46") (pin "K") (pinfunction "C_K") (pintype "passive"))
      (node (ref "LED462") (pin "K") (pinfunction "C_K") (pintype "passive"))
      (node (ref "LED478") (pin "K") (pinfunction "C_K") (pintype "passive"))
      (node (ref "LED494") (pin "K") (pinfunction "C_K") (pintype "passive"))
      (node (ref "LED510") (pin "K") (pinfunction "C_K") (pintype "passive"))
      (node (ref "LED526") (pin "K") (pinfunction "C_K") (pintype "passive"))
      (node (ref "LED542") (pin "K") (pinfunction "C_K") (pintype "passive"))
      (node (ref "LED558") (pin "K") (pinfunction "C_K") (pintype "passive"))
      (node (ref "LED574") (pin "K") (pinfunction "C_K") (pintype "passive"))
      (node (ref "LED590") (pin "K") (pinfunction "C_K") (pintype "passive"))
      (node (ref "LED606") (pin "K") (pinfunction "C_K") (pintype "passive"))
      (node (ref "LED62") (pin "K") (pinfunction "C_K") (pintype "passive"))
      (node (ref "LED622") (pin "K") (pinfunction "C_K") (pintype "passive"))
      (node (ref "LED638") (pin "K") (pinfunction "C_K") (pintype "passive"))
      (node (ref "LED654") (pin "K") (pinfunction "C_K") (pintype "passive"))
      (node (ref "LED670") (pin "K") (pinfunction "C_K") (pintype "passive"))
      (node (ref "LED686") (pin "K") (pinfunction "C_K") (pintype "passive"))
      (node (ref "LED702") (pin "K") (pinfunction "C_K") (pintype "passive"))
      (node (ref "LED718") (pin "K") (pinfunction "C_K") (pintype "passive"))
      (node (ref "LED734") (pin "K") (pinfunction "C_K") (pintype "passive"))
      (node (ref "LED750") (pin "K") (pinfunction "C_K") (pintype "passive"))
      (node (ref "LED766") (pin "K") (pinfunction "C_K") (pintype "passive"))
      (node (ref "LED78") (pin "K") (pinfunction "C_K") (pintype "passive"))
      (node (ref "LED782") (pin "K") (pinfunction "C_K") (pintype "passive"))
      (node (ref "LED798") (pin "K") (pinfunction "C_K") (pintype "passive"))
      (node (ref "LED814") (pin "K") (pinfunction "C_K") (pintype "passive"))
      (node (ref "LED830") (pin "K") (pinfunction "C_K") (pintype "passive"))
      (node (ref "LED846") (pin "K") (pinfunction "C_K") (pintype "passive"))
      (node (ref "LED862") (pin "K") (pinfunction "C_K") (pintype "passive"))
      (node (ref "LED878") (pin "K") (pinfunction "C_K") (pintype "passive"))
      (node (ref "LED894") (pin "K") (pinfunction "C_K") (pintype "passive"))
      (node (ref "LED910") (pin "K") (pinfunction "C_K") (pintype "passive"))
      (node (ref "LED926") (pin "K") (pinfunction "C_K") (pintype "passive"))
      (node (ref "LED94") (pin "K") (pinfunction "C_K") (pintype "passive"))
      (node (ref "LED942") (pin "K") (pinfunction "C_K") (pintype "passive"))
      (node (ref "LED958") (pin "K") (pinfunction "C_K") (pintype "passive"))
      (node (ref "LED974") (pin "K") (pinfunction "C_K") (pintype "passive"))
      (node (ref "LED990") (pin "K") (pinfunction "C_K") (pintype "passive"))
      (node (ref "R14") (pin "1") (pinfunction "1_1") (pintype "passive"))
    )
    (net (code "134") (name "Net-(LED1007-C)") (class "Default")
      (node (ref "LED1007") (pin "K") (pinfunction "C_K") (pintype "passive"))
      (node (ref "LED1023") (pin "K") (pinfunction "C_K") (pintype "passive"))
      (node (ref "LED1039") (pin "K") (pinfunction "C_K") (pintype "passive"))
      (node (ref "LED1055") (pin "K") (pinfunction "C_K") (pintype "passive"))
      (node (ref "LED1071") (pin "K") (pinfunction "C_K") (pintype "passive"))
      (node (ref "LED1087") (pin "K") (pinfunction "C_K") (pintype "passive"))
      (node (ref "LED1103") (pin "K") (pinfunction "C_K") (pintype "passive"))
      (node (ref "LED111") (pin "K") (pinfunction "C_K") (pintype "passive"))
      (node (ref "LED1119") (pin "K") (pinfunction "C_K") (pintype "passive"))
      (node (ref "LED1135") (pin "K") (pinfunction "C_K") (pintype "passive"))
      (node (ref "LED1151") (pin "K") (pinfunction "C_K") (pintype "passive"))
      (node (ref "LED1167") (pin "K") (pinfunction "C_K") (pintype "passive"))
      (node (ref "LED1183") (pin "K") (pinfunction "C_K") (pintype "passive"))
      (node (ref "LED1199") (pin "K") (pinfunction "C_K") (pintype "passive"))
      (node (ref "LED1215") (pin "K") (pinfunction "C_K") (pintype "passive"))
      (node (ref "LED1231") (pin "K") (pinfunction "C_K") (pintype "passive"))
      (node (ref "LED1247") (pin "K") (pinfunction "C_K") (pintype "passive"))
      (node (ref "LED1263") (pin "K") (pinfunction "C_K") (pintype "passive"))
      (node (ref "LED127") (pin "K") (pinfunction "C_K") (pintype "passive"))
      (node (ref "LED1279") (pin "K") (pinfunction "C_K") (pintype "passive"))
      (node (ref "LED143") (pin "K") (pinfunction "C_K") (pintype "passive"))
      (node (ref "LED15") (pin "K") (pinfunction "C_K") (pintype "passive"))
      (node (ref "LED159") (pin "K") (pinfunction "C_K") (pintype "passive"))
      (node (ref "LED175") (pin "K") (pinfunction "C_K") (pintype "passive"))
      (node (ref "LED191") (pin "K") (pinfunction "C_K") (pintype "passive"))
      (node (ref "LED207") (pin "K") (pinfunction "C_K") (pintype "passive"))
      (node (ref "LED223") (pin "K") (pinfunction "C_K") (pintype "passive"))
      (node (ref "LED239") (pin "K") (pinfunction "C_K") (pintype "passive"))
      (node (ref "LED255") (pin "K") (pinfunction "C_K") (pintype "passive"))
      (node (ref "LED271") (pin "K") (pinfunction "C_K") (pintype "passive"))
      (node (ref "LED287") (pin "K") (pinfunction "C_K") (pintype "passive"))
      (node (ref "LED303") (pin "K") (pinfunction "C_K") (pintype "passive"))
      (node (ref "LED31") (pin "K") (pinfunction "C_K") (pintype "passive"))
      (node (ref "LED319") (pin "K") (pinfunction "C_K") (pintype "passive"))
      (node (ref "LED335") (pin "K") (pinfunction "C_K") (pintype "passive"))
      (node (ref "LED351") (pin "K") (pinfunction "C_K") (pintype "passive"))
      (node (ref "LED367") (pin "K") (pinfunction "C_K") (pintype "passive"))
      (node (ref "LED383") (pin "K") (pinfunction "C_K") (pintype "passive"))
      (node (ref "LED399") (pin "K") (pinfunction "C_K") (pintype "passive"))
      (node (ref "LED415") (pin "K") (pinfunction "C_K") (pintype "passive"))
      (node (ref "LED431") (pin "K") (pinfunction "C_K") (pintype "passive"))
      (node (ref "LED447") (pin "K") (pinfunction "C_K") (pintype "passive"))
      (node (ref "LED463") (pin "K") (pinfunction "C_K") (pintype "passive"))
      (node (ref "LED47") (pin "K") (pinfunction "C_K") (pintype "passive"))
      (node (ref "LED479") (pin "K") (pinfunction "C_K") (pintype "passive"))
      (node (ref "LED495") (pin "K") (pinfunction "C_K") (pintype "passive"))
      (node (ref "LED511") (pin "K") (pinfunction "C_K") (pintype "passive"))
      (node (ref "LED527") (pin "K") (pinfunction "C_K") (pintype "passive"))
      (node (ref "LED543") (pin "K") (pinfunction "C_K") (pintype "passive"))
      (node (ref "LED559") (pin "K") (pinfunction "C_K") (pintype "passive"))
      (node (ref "LED575") (pin "K") (pinfunction "C_K") (pintype "passive"))
      (node (ref "LED591") (pin "K") (pinfunction "C_K") (pintype "passive"))
      (node (ref "LED607") (pin "K") (pinfunction "C_K") (pintype "passive"))
      (node (ref "LED623") (pin "K") (pinfunction "C_K") (pintype "passive"))
      (node (ref "LED63") (pin "K") (pinfunction "C_K") (pintype "passive"))
      (node (ref "LED639") (pin "K") (pinfunction "C_K") (pintype "passive"))
      (node (ref "LED655") (pin "K") (pinfunction "C_K") (pintype "passive"))
      (node (ref "LED671") (pin "K") (pinfunction "C_K") (pintype "passive"))
      (node (ref "LED687") (pin "K") (pinfunction "C_K") (pintype "passive"))
      (node (ref "LED703") (pin "K") (pinfunction "C_K") (pintype "passive"))
      (node (ref "LED719") (pin "K") (pinfunction "C_K") (pintype "passive"))
      (node (ref "LED735") (pin "K") (pinfunction "C_K") (pintype "passive"))
      (node (ref "LED751") (pin "K") (pinfunction "C_K") (pintype "passive"))
      (node (ref "LED767") (pin "K") (pinfunction "C_K") (pintype "passive"))
      (node (ref "LED783") (pin "K") (pinfunction "C_K") (pintype "passive"))
      (node (ref "LED79") (pin "K") (pinfunction "C_K") (pintype "passive"))
      (node (ref "LED799") (pin "K") (pinfunction "C_K") (pintype "passive"))
      (node (ref "LED815") (pin "K") (pinfunction "C_K") (pintype "passive"))
      (node (ref "LED831") (pin "K") (pinfunction "C_K") (pintype "passive"))
      (node (ref "LED847") (pin "K") (pinfunction "C_K") (pintype "passive"))
      (node (ref "LED863") (pin "K") (pinfunction "C_K") (pintype "passive"))
      (node (ref "LED879") (pin "K") (pinfunction "C_K") (pintype "passive"))
      (node (ref "LED895") (pin "K") (pinfunction "C_K") (pintype "passive"))
      (node (ref "LED911") (pin "K") (pinfunction "C_K") (pintype "passive"))
      (node (ref "LED927") (pin "K") (pinfunction "C_K") (pintype "passive"))
      (node (ref "LED943") (pin "K") (pinfunction "C_K") (pintype "passive"))
      (node (ref "LED95") (pin "K") (pinfunction "C_K") (pintype "passive"))
      (node (ref "LED959") (pin "K") (pinfunction "C_K") (pintype "passive"))
      (node (ref "LED975") (pin "K") (pinfunction "C_K") (pintype "passive"))
      (node (ref "LED991") (pin "K") (pinfunction "C_K") (pintype "passive"))
      (node (ref "R15") (pin "1") (pinfunction "1_1") (pintype "passive"))
    )
    (net (code "135") (name "Net-(LED1008-C)") (class "Default")
      (node (ref "LED1008") (pin "K") (pinfunction "C_K") (pintype "passive"))
      (node (ref "LED1024") (pin "K") (pinfunction "C_K") (pintype "passive"))
      (node (ref "LED1040") (pin "K") (pinfunction "C_K") (pintype "passive"))
      (node (ref "LED1056") (pin "K") (pinfunction "C_K") (pintype "passive"))
      (node (ref "LED1072") (pin "K") (pinfunction "C_K") (pintype "passive"))
      (node (ref "LED1088") (pin "K") (pinfunction "C_K") (pintype "passive"))
      (node (ref "LED1104") (pin "K") (pinfunction "C_K") (pintype "passive"))
      (node (ref "LED112") (pin "K") (pinfunction "C_K") (pintype "passive"))
      (node (ref "LED1120") (pin "K") (pinfunction "C_K") (pintype "passive"))
      (node (ref "LED1136") (pin "K") (pinfunction "C_K") (pintype "passive"))
      (node (ref "LED1152") (pin "K") (pinfunction "C_K") (pintype "passive"))
      (node (ref "LED1168") (pin "K") (pinfunction "C_K") (pintype "passive"))
      (node (ref "LED1184") (pin "K") (pinfunction "C_K") (pintype "passive"))
      (node (ref "LED1200") (pin "K") (pinfunction "C_K") (pintype "passive"))
      (node (ref "LED1216") (pin "K") (pinfunction "C_K") (pintype "passive"))
      (node (ref "LED1232") (pin "K") (pinfunction "C_K") (pintype "passive"))
      (node (ref "LED1248") (pin "K") (pinfunction "C_K") (pintype "passive"))
      (node (ref "LED1264") (pin "K") (pinfunction "C_K") (pintype "passive"))
      (node (ref "LED128") (pin "K") (pinfunction "C_K") (pintype "passive"))
      (node (ref "LED1280") (pin "K") (pinfunction "C_K") (pintype "passive"))
      (node (ref "LED144") (pin "K") (pinfunction "C_K") (pintype "passive"))
      (node (ref "LED16") (pin "K") (pinfunction "C_K") (pintype "passive"))
      (node (ref "LED160") (pin "K") (pinfunction "C_K") (pintype "passive"))
      (node (ref "LED176") (pin "K") (pinfunction "C_K") (pintype "passive"))
      (node (ref "LED192") (pin "K") (pinfunction "C_K") (pintype "passive"))
      (node (ref "LED208") (pin "K") (pinfunction "C_K") (pintype "passive"))
      (node (ref "LED224") (pin "K") (pinfunction "C_K") (pintype "passive"))
      (node (ref "LED240") (pin "K") (pinfunction "C_K") (pintype "passive"))
      (node (ref "LED256") (pin "K") (pinfunction "C_K") (pintype "passive"))
      (node (ref "LED272") (pin "K") (pinfunction "C_K") (pintype "passive"))
      (node (ref "LED288") (pin "K") (pinfunction "C_K") (pintype "passive"))
      (node (ref "LED304") (pin "K") (pinfunction "C_K") (pintype "passive"))
      (node (ref "LED32") (pin "K") (pinfunction "C_K") (pintype "passive"))
      (node (ref "LED320") (pin "K") (pinfunction "C_K") (pintype "passive"))
      (node (ref "LED336") (pin "K") (pinfunction "C_K") (pintype "passive"))
      (node (ref "LED352") (pin "K") (pinfunction "C_K") (pintype "passive"))
      (node (ref "LED368") (pin "K") (pinfunction "C_K") (pintype "passive"))
      (node (ref "LED384") (pin "K") (pinfunction "C_K") (pintype "passive"))
      (node (ref "LED400") (pin "K") (pinfunction "C_K") (pintype "passive"))
      (node (ref "LED416") (pin "K") (pinfunction "C_K") (pintype "passive"))
      (node (ref "LED432") (pin "K") (pinfunction "C_K") (pintype "passive"))
      (node (ref "LED448") (pin "K") (pinfunction "C_K") (pintype "passive"))
      (node (ref "LED464") (pin "K") (pinfunction "C_K") (pintype "passive"))
      (node (ref "LED48") (pin "K") (pinfunction "C_K") (pintype "passive"))
      (node (ref "LED480") (pin "K") (pinfunction "C_K") (pintype "passive"))
      (node (ref "LED496") (pin "K") (pinfunction "C_K") (pintype "passive"))
      (node (ref "LED512") (pin "K") (pinfunction "C_K") (pintype "passive"))
      (node (ref "LED528") (pin "K") (pinfunction "C_K") (pintype "passive"))
      (node (ref "LED544") (pin "K") (pinfunction "C_K") (pintype "passive"))
      (node (ref "LED560") (pin "K") (pinfunction "C_K") (pintype "passive"))
      (node (ref "LED576") (pin "K") (pinfunction "C_K") (pintype "passive"))
      (node (ref "LED592") (pin "K") (pinfunction "C_K") (pintype "passive"))
      (node (ref "LED608") (pin "K") (pinfunction "C_K") (pintype "passive"))
      (node (ref "LED624") (pin "K") (pinfunction "C_K") (pintype "passive"))
      (node (ref "LED64") (pin "K") (pinfunction "C_K") (pintype "passive"))
      (node (ref "LED640") (pin "K") (pinfunction "C_K") (pintype "passive"))
      (node (ref "LED656") (pin "K") (pinfunction "C_K") (pintype "passive"))
      (node (ref "LED672") (pin "K") (pinfunction "C_K") (pintype "passive"))
      (node (ref "LED688") (pin "K") (pinfunction "C_K") (pintype "passive"))
      (node (ref "LED704") (pin "K") (pinfunction "C_K") (pintype "passive"))
      (node (ref "LED720") (pin "K") (pinfunction "C_K") (pintype "passive"))
      (node (ref "LED736") (pin "K") (pinfunction "C_K") (pintype "passive"))
      (node (ref "LED752") (pin "K") (pinfunction "C_K") (pintype "passive"))
      (node (ref "LED768") (pin "K") (pinfunction "C_K") (pintype "passive"))
      (node (ref "LED784") (pin "K") (pinfunction "C_K") (pintype "passive"))
      (node (ref "LED80") (pin "K") (pinfunction "C_K") (pintype "passive"))
      (node (ref "LED800") (pin "K") (pinfunction "C_K") (pintype "passive"))
      (node (ref "LED816") (pin "K") (pinfunction "C_K") (pintype "passive"))
      (node (ref "LED832") (pin "K") (pinfunction "C_K") (pintype "passive"))
      (node (ref "LED848") (pin "K") (pinfunction "C_K") (pintype "passive"))
      (node (ref "LED864") (pin "K") (pinfunction "C_K") (pintype "passive"))
      (node (ref "LED880") (pin "K") (pinfunction "C_K") (pintype "passive"))
      (node (ref "LED896") (pin "K") (pinfunction "C_K") (pintype "passive"))
      (node (ref "LED912") (pin "K") (pinfunction "C_K") (pintype "passive"))
      (node (ref "LED928") (pin "K") (pinfunction "C_K") (pintype "passive"))
      (node (ref "LED944") (pin "K") (pinfunction "C_K") (pintype "passive"))
      (node (ref "LED96") (pin "K") (pinfunction "C_K") (pintype "passive"))
      (node (ref "LED960") (pin "K") (pinfunction "C_K") (pintype "passive"))
      (node (ref "LED976") (pin "K") (pinfunction "C_K") (pintype "passive"))
      (node (ref "LED992") (pin "K") (pinfunction "C_K") (pintype "passive"))
      (node (ref "R16") (pin "1") (pinfunction "1_1") (pintype "passive"))
    )
    (net (code "136") (name "Net-(LED1010-C)") (class "Default")
      (node (ref "LED1010") (pin "K") (pinfunction "C_K") (pintype "passive"))
      (node (ref "LED1026") (pin "K") (pinfunction "C_K") (pintype "passive"))
      (node (ref "LED1042") (pin "K") (pinfunction "C_K") (pintype "passive"))
      (node (ref "LED1058") (pin "K") (pinfunction "C_K") (pintype "passive"))
      (node (ref "LED1074") (pin "K") (pinfunction "C_K") (pintype "passive"))
      (node (ref "LED1090") (pin "K") (pinfunction "C_K") (pintype "passive"))
      (node (ref "LED1106") (pin "K") (pinfunction "C_K") (pintype "passive"))
      (node (ref "LED1122") (pin "K") (pinfunction "C_K") (pintype "passive"))
      (node (ref "LED1138") (pin "K") (pinfunction "C_K") (pintype "passive"))
      (node (ref "LED114") (pin "K") (pinfunction "C_K") (pintype "passive"))
      (node (ref "LED1154") (pin "K") (pinfunction "C_K") (pintype "passive"))
      (node (ref "LED1170") (pin "K") (pinfunction "C_K") (pintype "passive"))
      (node (ref "LED1186") (pin "K") (pinfunction "C_K") (pintype "passive"))
      (node (ref "LED1202") (pin "K") (pinfunction "C_K") (pintype "passive"))
      (node (ref "LED1218") (pin "K") (pinfunction "C_K") (pintype "passive"))
      (node (ref "LED1234") (pin "K") (pinfunction "C_K") (pintype "passive"))
      (node (ref "LED1250") (pin "K") (pinfunction "C_K") (pintype "passive"))
      (node (ref "LED1266") (pin "K") (pinfunction "C_K") (pintype "passive"))
      (node (ref "LED130") (pin "K") (pinfunction "C_K") (pintype "passive"))
      (node (ref "LED146") (pin "K") (pinfunction "C_K") (pintype "passive"))
      (node (ref "LED162") (pin "K") (pinfunction "C_K") (pintype "passive"))
      (node (ref "LED178") (pin "K") (pinfunction "C_K") (pintype "passive"))
      (node (ref "LED18") (pin "K") (pinfunction "C_K") (pintype "passive"))
      (node (ref "LED194") (pin "K") (pinfunction "C_K") (pintype "passive"))
      (node (ref "LED2") (pin "K") (pinfunction "C_K") (pintype "passive"))
      (node (ref "LED210") (pin "K") (pinfunction "C_K") (pintype "passive"))
      (node (ref "LED226") (pin "K") (pinfunction "C_K") (pintype "passive"))
      (node (ref "LED242") (pin "K") (pinfunction "C_K") (pintype "passive"))
      (node (ref "LED258") (pin "K") (pinfunction "C_K") (pintype "passive"))
      (node (ref "LED274") (pin "K") (pinfunction "C_K") (pintype "passive"))
      (node (ref "LED290") (pin "K") (pinfunction "C_K") (pintype "passive"))
      (node (ref "LED306") (pin "K") (pinfunction "C_K") (pintype "passive"))
      (node (ref "LED322") (pin "K") (pinfunction "C_K") (pintype "passive"))
      (node (ref "LED338") (pin "K") (pinfunction "C_K") (pintype "passive"))
      (node (ref "LED34") (pin "K") (pinfunction "C_K") (pintype "passive"))
      (node (ref "LED354") (pin "K") (pinfunction "C_K") (pintype "passive"))
      (node (ref "LED370") (pin "K") (pinfunction "C_K") (pintype "passive"))
      (node (ref "LED386") (pin "K") (pinfunction "C_K") (pintype "passive"))
      (node (ref "LED402") (pin "K") (pinfunction "C_K") (pintype "passive"))
      (node (ref "LED418") (pin "K") (pinfunction "C_K") (pintype "passive"))
      (node (ref "LED434") (pin "K") (pinfunction "C_K") (pintype "passive"))
      (node (ref "LED450") (pin "K") (pinfunction "C_K") (pintype "passive"))
      (node (ref "LED466") (pin "K") (pinfunction "C_K") (pintype "passive"))
      (node (ref "LED482") (pin "K") (pinfunction "C_K") (pintype "passive"))
      (node (ref "LED498") (pin "K") (pinfunction "C_K") (pintype "passive"))
      (node (ref "LED50") (pin "K") (pinfunction "C_K") (pintype "passive"))
      (node (ref "LED514") (pin "K") (pinfunction "C_K") (pintype "passive"))
      (node (ref "LED530") (pin "K") (pinfunction "C_K") (pintype "passive"))
      (node (ref "LED546") (pin "K") (pinfunction "C_K") (pintype "passive"))
      (node (ref "LED562") (pin "K") (pinfunction "C_K") (pintype "passive"))
      (node (ref "LED578") (pin "K") (pinfunction "C_K") (pintype "passive"))
      (node (ref "LED594") (pin "K") (pinfunction "C_K") (pintype "passive"))
      (node (ref "LED610") (pin "K") (pinfunction "C_K") (pintype "passive"))
      (node (ref "LED626") (pin "K") (pinfunction "C_K") (pintype "passive"))
      (node (ref "LED642") (pin "K") (pinfunction "C_K") (pintype "passive"))
      (node (ref "LED658") (pin "K") (pinfunction "C_K") (pintype "passive"))
      (node (ref "LED66") (pin "K") (pinfunction "C_K") (pintype "passive"))
      (node (ref "LED674") (pin "K") (pinfunction "C_K") (pintype "passive"))
      (node (ref "LED690") (pin "K") (pinfunction "C_K") (pintype "passive"))
      (node (ref "LED706") (pin "K") (pinfunction "C_K") (pintype "passive"))
      (node (ref "LED722") (pin "K") (pinfunction "C_K") (pintype "passive"))
      (node (ref "LED738") (pin "K") (pinfunction "C_K") (pintype "passive"))
      (node (ref "LED754") (pin "K") (pinfunction "C_K") (pintype "passive"))
      (node (ref "LED770") (pin "K") (pinfunction "C_K") (pintype "passive"))
      (node (ref "LED786") (pin "K") (pinfunction "C_K") (pintype "passive"))
      (node (ref "LED802") (pin "K") (pinfunction "C_K") (pintype "passive"))
      (node (ref "LED818") (pin "K") (pinfunction "C_K") (pintype "passive"))
      (node (ref "LED82") (pin "K") (pinfunction "C_K") (pintype "passive"))
      (node (ref "LED834") (pin "K") (pinfunction "C_K") (pintype "passive"))
      (node (ref "LED850") (pin "K") (pinfunction "C_K") (pintype "passive"))
      (node (ref "LED866") (pin "K") (pinfunction "C_K") (pintype "passive"))
      (node (ref "LED882") (pin "K") (pinfunction "C_K") (pintype "passive"))
      (node (ref "LED898") (pin "K") (pinfunction "C_K") (pintype "passive"))
      (node (ref "LED914") (pin "K") (pinfunction "C_K") (pintype "passive"))
      (node (ref "LED930") (pin "K") (pinfunction "C_K") (pintype "passive"))
      (node (ref "LED946") (pin "K") (pinfunction "C_K") (pintype "passive"))
      (node (ref "LED962") (pin "K") (pinfunction "C_K") (pintype "passive"))
      (node (ref "LED978") (pin "K") (pinfunction "C_K") (pintype "passive"))
      (node (ref "LED98") (pin "K") (pinfunction "C_K") (pintype "passive"))
      (node (ref "LED994") (pin "K") (pinfunction "C_K") (pintype "passive"))
      (node (ref "R2") (pin "1") (pinfunction "1_1") (pintype "passive"))
    )
    (net (code "137") (name "Net-(LED1011-C)") (class "Default")
      (node (ref "LED1011") (pin "K") (pinfunction "C_K") (pintype "passive"))
      (node (ref "LED1027") (pin "K") (pinfunction "C_K") (pintype "passive"))
      (node (ref "LED1043") (pin "K") (pinfunction "C_K") (pintype "passive"))
      (node (ref "LED1059") (pin "K") (pinfunction "C_K") (pintype "passive"))
      (node (ref "LED1075") (pin "K") (pinfunction "C_K") (pintype "passive"))
      (node (ref "LED1091") (pin "K") (pinfunction "C_K") (pintype "passive"))
      (node (ref "LED1107") (pin "K") (pinfunction "C_K") (pintype "passive"))
      (node (ref "LED1123") (pin "K") (pinfunction "C_K") (pintype "passive"))
      (node (ref "LED1139") (pin "K") (pinfunction "C_K") (pintype "passive"))
      (node (ref "LED115") (pin "K") (pinfunction "C_K") (pintype "passive"))
      (node (ref "LED1155") (pin "K") (pinfunction "C_K") (pintype "passive"))
      (node (ref "LED1171") (pin "K") (pinfunction "C_K") (pintype "passive"))
      (node (ref "LED1187") (pin "K") (pinfunction "C_K") (pintype "passive"))
      (node (ref "LED1203") (pin "K") (pinfunction "C_K") (pintype "passive"))
      (node (ref "LED1219") (pin "K") (pinfunction "C_K") (pintype "passive"))
      (node (ref "LED1235") (pin "K") (pinfunction "C_K") (pintype "passive"))
      (node (ref "LED1251") (pin "K") (pinfunction "C_K") (pintype "passive"))
      (node (ref "LED1267") (pin "K") (pinfunction "C_K") (pintype "passive"))
      (node (ref "LED131") (pin "K") (pinfunction "C_K") (pintype "passive"))
      (node (ref "LED147") (pin "K") (pinfunction "C_K") (pintype "passive"))
      (node (ref "LED163") (pin "K") (pinfunction "C_K") (pintype "passive"))
      (node (ref "LED179") (pin "K") (pinfunction "C_K") (pintype "passive"))
      (node (ref "LED19") (pin "K") (pinfunction "C_K") (pintype "passive"))
      (node (ref "LED195") (pin "K") (pinfunction "C_K") (pintype "passive"))
      (node (ref "LED211") (pin "K") (pinfunction "C_K") (pintype "passive"))
      (node (ref "LED227") (pin "K") (pinfunction "C_K") (pintype "passive"))
      (node (ref "LED243") (pin "K") (pinfunction "C_K") (pintype "passive"))
      (node (ref "LED259") (pin "K") (pinfunction "C_K") (pintype "passive"))
      (node (ref "LED275") (pin "K") (pinfunction "C_K") (pintype "passive"))
      (node (ref "LED291") (pin "K") (pinfunction "C_K") (pintype "passive"))
      (node (ref "LED3") (pin "K") (pinfunction "C_K") (pintype "passive"))
      (node (ref "LED307") (pin "K") (pinfunction "C_K") (pintype "passive"))
      (node (ref "LED323") (pin "K") (pinfunction "C_K") (pintype "passive"))
      (node (ref "LED339") (pin "K") (pinfunction "C_K") (pintype "passive"))
      (node (ref "LED35") (pin "K") (pinfunction "C_K") (pintype "passive"))
      (node (ref "LED355") (pin "K") (pinfunction "C_K") (pintype "passive"))
      (node (ref "LED371") (pin "K") (pinfunction "C_K") (pintype "passive"))
      (node (ref "LED387") (pin "K") (pinfunction "C_K") (pintype "passive"))
      (node (ref "LED403") (pin "K") (pinfunction "C_K") (pintype "passive"))
      (node (ref "LED419") (pin "K") (pinfunction "C_K") (pintype "passive"))
      (node (ref "LED435") (pin "K") (pinfunction "C_K") (pintype "passive"))
      (node (ref "LED451") (pin "K") (pinfunction "C_K") (pintype "passive"))
      (node (ref "LED467") (pin "K") (pinfunction "C_K") (pintype "passive"))
      (node (ref "LED483") (pin "K") (pinfunction "C_K") (pintype "passive"))
      (node (ref "LED499") (pin "K") (pinfunction "C_K") (pintype "passive"))
      (node (ref "LED51") (pin "K") (pinfunction "C_K") (pintype "passive"))
      (node (ref "LED515") (pin "K") (pinfunction "C_K") (pintype "passive"))
      (node (ref "LED531") (pin "K") (pinfunction "C_K") (pintype "passive"))
      (node (ref "LED547") (pin "K") (pinfunction "C_K") (pintype "passive"))
      (node (ref "LED563") (pin "K") (pinfunction "C_K") (pintype "passive"))
      (node (ref "LED579") (pin "K") (pinfunction "C_K") (pintype "passive"))
      (node (ref "LED595") (pin "K") (pinfunction "C_K") (pintype "passive"))
      (node (ref "LED611") (pin "K") (pinfunction "C_K") (pintype "passive"))
      (node (ref "LED627") (pin "K") (pinfunction "C_K") (pintype "passive"))
      (node (ref "LED643") (pin "K") (pinfunction "C_K") (pintype "passive"))
      (node (ref "LED659") (pin "K") (pinfunction "C_K") (pintype "passive"))
      (node (ref "LED67") (pin "K") (pinfunction "C_K") (pintype "passive"))
      (node (ref "LED675") (pin "K") (pinfunction "C_K") (pintype "passive"))
      (node (ref "LED691") (pin "K") (pinfunction "C_K") (pintype "passive"))
      (node (ref "LED707") (pin "K") (pinfunction "C_K") (pintype "passive"))
      (node (ref "LED723") (pin "K") (pinfunction "C_K") (pintype "passive"))
      (node (ref "LED739") (pin "K") (pinfunction "C_K") (pintype "passive"))
      (node (ref "LED755") (pin "K") (pinfunction "C_K") (pintype "passive"))
      (node (ref "LED771") (pin "K") (pinfunction "C_K") (pintype "passive"))
      (node (ref "LED787") (pin "K") (pinfunction "C_K") (pintype "passive"))
      (node (ref "LED803") (pin "K") (pinfunction "C_K") (pintype "passive"))
      (node (ref "LED819") (pin "K") (pinfunction "C_K") (pintype "passive"))
      (node (ref "LED83") (pin "K") (pinfunction "C_K") (pintype "passive"))
      (node (ref "LED835") (pin "K") (pinfunction "C_K") (pintype "passive"))
      (node (ref "LED851") (pin "K") (pinfunction "C_K") (pintype "passive"))
      (node (ref "LED867") (pin "K") (pinfunction "C_K") (pintype "passive"))
      (node (ref "LED883") (pin "K") (pinfunction "C_K") (pintype "passive"))
      (node (ref "LED899") (pin "K") (pinfunction "C_K") (pintype "passive"))
      (node (ref "LED915") (pin "K") (pinfunction "C_K") (pintype "passive"))
      (node (ref "LED931") (pin "K") (pinfunction "C_K") (pintype "passive"))
      (node (ref "LED947") (pin "K") (pinfunction "C_K") (pintype "passive"))
      (node (ref "LED963") (pin "K") (pinfunction "C_K") (pintype "passive"))
      (node (ref "LED979") (pin "K") (pinfunction "C_K") (pintype "passive"))
      (node (ref "LED99") (pin "K") (pinfunction "C_K") (pintype "passive"))
      (node (ref "LED995") (pin "K") (pinfunction "C_K") (pintype "passive"))
      (node (ref "R3") (pin "1") (pinfunction "1_1") (pintype "passive"))
    )
    (net (code "138") (name "Net-(LED1014-C)") (class "Default")
      (node (ref "LED1014") (pin "K") (pinfunction "C_K") (pintype "passive"))
      (node (ref "LED102") (pin "K") (pinfunction "C_K") (pintype "passive"))
      (node (ref "LED1030") (pin "K") (pinfunction "C_K") (pintype "passive"))
      (node (ref "LED1046") (pin "K") (pinfunction "C_K") (pintype "passive"))
      (node (ref "LED1062") (pin "K") (pinfunction "C_K") (pintype "passive"))
      (node (ref "LED1078") (pin "K") (pinfunction "C_K") (pintype "passive"))
      (node (ref "LED1094") (pin "K") (pinfunction "C_K") (pintype "passive"))
      (node (ref "LED1110") (pin "K") (pinfunction "C_K") (pintype "passive"))
      (node (ref "LED1126") (pin "K") (pinfunction "C_K") (pintype "passive"))
      (node (ref "LED1142") (pin "K") (pinfunction "C_K") (pintype "passive"))
      (node (ref "LED1158") (pin "K") (pinfunction "C_K") (pintype "passive"))
      (node (ref "LED1174") (pin "K") (pinfunction "C_K") (pintype "passive"))
      (node (ref "LED118") (pin "K") (pinfunction "C_K") (pintype "passive"))
      (node (ref "LED1190") (pin "K") (pinfunction "C_K") (pintype "passive"))
      (node (ref "LED1206") (pin "K") (pinfunction "C_K") (pintype "passive"))
      (node (ref "LED1222") (pin "K") (pinfunction "C_K") (pintype "passive"))
      (node (ref "LED1238") (pin "K") (pinfunction "C_K") (pintype "passive"))
      (node (ref "LED1254") (pin "K") (pinfunction "C_K") (pintype "passive"))
      (node (ref "LED1270") (pin "K") (pinfunction "C_K") (pintype "passive"))
      (node (ref "LED134") (pin "K") (pinfunction "C_K") (pintype "passive"))
      (node (ref "LED150") (pin "K") (pinfunction "C_K") (pintype "passive"))
      (node (ref "LED166") (pin "K") (pinfunction "C_K") (pintype "passive"))
      (node (ref "LED182") (pin "K") (pinfunction "C_K") (pintype "passive"))
      (node (ref "LED198") (pin "K") (pinfunction "C_K") (pintype "passive"))
      (node (ref "LED214") (pin "K") (pinfunction "C_K") (pintype "passive"))
      (node (ref "LED22") (pin "K") (pinfunction "C_K") (pintype "passive"))
      (node (ref "LED230") (pin "K") (pinfunction "C_K") (pintype "passive"))
      (node (ref "LED246") (pin "K") (pinfunction "C_K") (pintype "passive"))
      (node (ref "LED262") (pin "K") (pinfunction "C_K") (pintype "passive"))
      (node (ref "LED278") (pin "K") (pinfunction "C_K") (pintype "passive"))
      (node (ref "LED294") (pin "K") (pinfunction "C_K") (pintype "passive"))
      (node (ref "LED310") (pin "K") (pinfunction "C_K") (pintype "passive"))
      (node (ref "LED326") (pin "K") (pinfunction "C_K") (pintype "passive"))
      (node (ref "LED342") (pin "K") (pinfunction "C_K") (pintype "passive"))
      (node (ref "LED358") (pin "K") (pinfunction "C_K") (pintype "passive"))
      (node (ref "LED374") (pin "K") (pinfunction "C_K") (pintype "passive"))
      (node (ref "LED38") (pin "K") (pinfunction "C_K") (pintype "passive"))
      (node (ref "LED390") (pin "K") (pinfunction "C_K") (pintype "passive"))
      (node (ref "LED406") (pin "K") (pinfunction "C_K") (pintype "passive"))
      (node (ref "LED422") (pin "K") (pinfunction "C_K") (pintype "passive"))
      (node (ref "LED438") (pin "K") (pinfunction "C_K") (pintype "passive"))
      (node (ref "LED454") (pin "K") (pinfunction "C_K") (pintype "passive"))
      (node (ref "LED470") (pin "K") (pinfunction "C_K") (pintype "passive"))
      (node (ref "LED486") (pin "K") (pinfunction "C_K") (pintype "passive"))
      (node (ref "LED502") (pin "K") (pinfunction "C_K") (pintype "passive"))
      (node (ref "LED518") (pin "K") (pinfunction "C_K") (pintype "passive"))
      (node (ref "LED534") (pin "K") (pinfunction "C_K") (pintype "passive"))
      (node (ref "LED54") (pin "K") (pinfunction "C_K") (pintype "passive"))
      (node (ref "LED550") (pin "K") (pinfunction "C_K") (pintype "passive"))
      (node (ref "LED566") (pin "K") (pinfunction "C_K") (pintype "passive"))
      (node (ref "LED582") (pin "K") (pinfunction "C_K") (pintype "passive"))
      (node (ref "LED598") (pin "K") (pinfunction "C_K") (pintype "passive"))
      (node (ref "LED6") (pin "K") (pinfunction "C_K") (pintype "passive"))
      (node (ref "LED614") (pin "K") (pinfunction "C_K") (pintype "passive"))
      (node (ref "LED630") (pin "K") (pinfunction "C_K") (pintype "passive"))
      (node (ref "LED646") (pin "K") (pinfunction "C_K") (pintype "passive"))
      (node (ref "LED662") (pin "K") (pinfunction "C_K") (pintype "passive"))
      (node (ref "LED678") (pin "K") (pinfunction "C_K") (pintype "passive"))
      (node (ref "LED694") (pin "K") (pinfunction "C_K") (pintype "passive"))
      (node (ref "LED70") (pin "K") (pinfunction "C_K") (pintype "passive"))
      (node (ref "LED710") (pin "K") (pinfunction "C_K") (pintype "passive"))
      (node (ref "LED726") (pin "K") (pinfunction "C_K") (pintype "passive"))
      (node (ref "LED742") (pin "K") (pinfunction "C_K") (pintype "passive"))
      (node (ref "LED758") (pin "K") (pinfunction "C_K") (pintype "passive"))
      (node (ref "LED774") (pin "K") (pinfunction "C_K") (pintype "passive"))
      (node (ref "LED790") (pin "K") (pinfunction "C_K") (pintype "passive"))
      (node (ref "LED806") (pin "K") (pinfunction "C_K") (pintype "passive"))
      (node (ref "LED822") (pin "K") (pinfunction "C_K") (pintype "passive"))
      (node (ref "LED838") (pin "K") (pinfunction "C_K") (pintype "passive"))
      (node (ref "LED854") (pin "K") (pinfunction "C_K") (pintype "passive"))
      (node (ref "LED86") (pin "K") (pinfunction "C_K") (pintype "passive"))
      (node (ref "LED870") (pin "K") (pinfunction "C_K") (pintype "passive"))
      (node (ref "LED886") (pin "K") (pinfunction "C_K") (pintype "passive"))
      (node (ref "LED902") (pin "K") (pinfunction "C_K") (pintype "passive"))
      (node (ref "LED918") (pin "K") (pinfunction "C_K") (pintype "passive"))
      (node (ref "LED934") (pin "K") (pinfunction "C_K") (pintype "passive"))
      (node (ref "LED950") (pin "K") (pinfunction "C_K") (pintype "passive"))
      (node (ref "LED966") (pin "K") (pinfunction "C_K") (pintype "passive"))
      (node (ref "LED982") (pin "K") (pinfunction "C_K") (pintype "passive"))
      (node (ref "LED998") (pin "K") (pinfunction "C_K") (pintype "passive"))
      (node (ref "R6") (pin "1") (pinfunction "1_1") (pintype "passive"))
    )
    (net (code "139") (name "Net-(LED1015-C)") (class "Default")
      (node (ref "LED1015") (pin "K") (pinfunction "C_K") (pintype "passive"))
      (node (ref "LED103") (pin "K") (pinfunction "C_K") (pintype "passive"))
      (node (ref "LED1031") (pin "K") (pinfunction "C_K") (pintype "passive"))
      (node (ref "LED1047") (pin "K") (pinfunction "C_K") (pintype "passive"))
      (node (ref "LED1063") (pin "K") (pinfunction "C_K") (pintype "passive"))
      (node (ref "LED1079") (pin "K") (pinfunction "C_K") (pintype "passive"))
      (node (ref "LED1095") (pin "K") (pinfunction "C_K") (pintype "passive"))
      (node (ref "LED1111") (pin "K") (pinfunction "C_K") (pintype "passive"))
      (node (ref "LED1127") (pin "K") (pinfunction "C_K") (pintype "passive"))
      (node (ref "LED1143") (pin "K") (pinfunction "C_K") (pintype "passive"))
      (node (ref "LED1159") (pin "K") (pinfunction "C_K") (pintype "passive"))
      (node (ref "LED1175") (pin "K") (pinfunction "C_K") (pintype "passive"))
      (node (ref "LED119") (pin "K") (pinfunction "C_K") (pintype "passive"))
      (node (ref "LED1191") (pin "K") (pinfunction "C_K") (pintype "passive"))
      (node (ref "LED1207") (pin "K") (pinfunction "C_K") (pintype "passive"))
      (node (ref "LED1223") (pin "K") (pinfunction "C_K") (pintype "passive"))
      (node (ref "LED1239") (pin "K") (pinfunction "C_K") (pintype "passive"))
      (node (ref "LED1255") (pin "K") (pinfunction "C_K") (pintype "passive"))
      (node (ref "LED1271") (pin "K") (pinfunction "C_K") (pintype "passive"))
      (node (ref "LED135") (pin "K") (pinfunction "C_K") (pintype "passive"))
      (node (ref "LED151") (pin "K") (pinfunction "C_K") (pintype "passive"))
      (node (ref "LED167") (pin "K") (pinfunction "C_K") (pintype "passive"))
      (node (ref "LED183") (pin "K") (pinfunction "C_K") (pintype "passive"))
      (node (ref "LED199") (pin "K") (pinfunction "C_K") (pintype "passive"))
      (node (ref "LED215") (pin "K") (pinfunction "C_K") (pintype "passive"))
      (node (ref "LED23") (pin "K") (pinfunction "C_K") (pintype "passive"))
      (node (ref "LED231") (pin "K") (pinfunction "C_K") (pintype "passive"))
      (node (ref "LED247") (pin "K") (pinfunction "C_K") (pintype "passive"))
      (node (ref "LED263") (pin "K") (pinfunction "C_K") (pintype "passive"))
      (node (ref "LED279") (pin "K") (pinfunction "C_K") (pintype "passive"))
      (node (ref "LED295") (pin "K") (pinfunction "C_K") (pintype "passive"))
      (node (ref "LED311") (pin "K") (pinfunction "C_K") (pintype "passive"))
      (node (ref "LED327") (pin "K") (pinfunction "C_K") (pintype "passive"))
      (node (ref "LED343") (pin "K") (pinfunction "C_K") (pintype "passive"))
      (node (ref "LED359") (pin "K") (pinfunction "C_K") (pintype "passive"))
      (node (ref "LED375") (pin "K") (pinfunction "C_K") (pintype "passive"))
      (node (ref "LED39") (pin "K") (pinfunction "C_K") (pintype "passive"))
      (node (ref "LED391") (pin "K") (pinfunction "C_K") (pintype "passive"))
      (node (ref "LED407") (pin "K") (pinfunction "C_K") (pintype "passive"))
      (node (ref "LED423") (pin "K") (pinfunction "C_K") (pintype "passive"))
      (node (ref "LED439") (pin "K") (pinfunction "C_K") (pintype "passive"))
      (node (ref "LED455") (pin "K") (pinfunction "C_K") (pintype "passive"))
      (node (ref "LED471") (pin "K") (pinfunction "C_K") (pintype "passive"))
      (node (ref "LED487") (pin "K") (pinfunction "C_K") (pintype "passive"))
      (node (ref "LED503") (pin "K") (pinfunction "C_K") (pintype "passive"))
      (node (ref "LED519") (pin "K") (pinfunction "C_K") (pintype "passive"))
      (node (ref "LED535") (pin "K") (pinfunction "C_K") (pintype "passive"))
      (node (ref "LED55") (pin "K") (pinfunction "C_K") (pintype "passive"))
      (node (ref "LED551") (pin "K") (pinfunction "C_K") (pintype "passive"))
      (node (ref "LED567") (pin "K") (pinfunction "C_K") (pintype "passive"))
      (node (ref "LED583") (pin "K") (pinfunction "C_K") (pintype "passive"))
      (node (ref "LED599") (pin "K") (pinfunction "C_K") (pintype "passive"))
      (node (ref "LED615") (pin "K") (pinfunction "C_K") (pintype "passive"))
      (node (ref "LED631") (pin "K") (pinfunction "C_K") (pintype "passive"))
      (node (ref "LED647") (pin "K") (pinfunction "C_K") (pintype "passive"))
      (node (ref "LED663") (pin "K") (pinfunction "C_K") (pintype "passive"))
      (node (ref "LED679") (pin "K") (pinfunction "C_K") (pintype "passive"))
      (node (ref "LED695") (pin "K") (pinfunction "C_K") (pintype "passive"))
      (node (ref "LED7") (pin "K") (pinfunction "C_K") (pintype "passive"))
      (node (ref "LED71") (pin "K") (pinfunction "C_K") (pintype "passive"))
      (node (ref "LED711") (pin "K") (pinfunction "C_K") (pintype "passive"))
      (node (ref "LED727") (pin "K") (pinfunction "C_K") (pintype "passive"))
      (node (ref "LED743") (pin "K") (pinfunction "C_K") (pintype "passive"))
      (node (ref "LED759") (pin "K") (pinfunction "C_K") (pintype "passive"))
      (node (ref "LED775") (pin "K") (pinfunction "C_K") (pintype "passive"))
      (node (ref "LED791") (pin "K") (pinfunction "C_K") (pintype "passive"))
      (node (ref "LED807") (pin "K") (pinfunction "C_K") (pintype "passive"))
      (node (ref "LED823") (pin "K") (pinfunction "C_K") (pintype "passive"))
      (node (ref "LED839") (pin "K") (pinfunction "C_K") (pintype "passive"))
      (node (ref "LED855") (pin "K") (pinfunction "C_K") (pintype "passive"))
      (node (ref "LED87") (pin "K") (pinfunction "C_K") (pintype "passive"))
      (node (ref "LED871") (pin "K") (pinfunction "C_K") (pintype "passive"))
      (node (ref "LED887") (pin "K") (pinfunction "C_K") (pintype "passive"))
      (node (ref "LED903") (pin "K") (pinfunction "C_K") (pintype "passive"))
      (node (ref "LED919") (pin "K") (pinfunction "C_K") (pintype "passive"))
      (node (ref "LED935") (pin "K") (pinfunction "C_K") (pintype "passive"))
      (node (ref "LED951") (pin "K") (pinfunction "C_K") (pintype "passive"))
      (node (ref "LED967") (pin "K") (pinfunction "C_K") (pintype "passive"))
      (node (ref "LED983") (pin "K") (pinfunction "C_K") (pintype "passive"))
      (node (ref "LED999") (pin "K") (pinfunction "C_K") (pintype "passive"))
      (node (ref "R7") (pin "1") (pinfunction "1_1") (pintype "passive"))
    )
    (net (code "140") (name "VCC") (class "Default")
      (node (ref "C4") (pin "1") (pinfunction "1_1") (pintype "passive"))
      (node (ref "IC1") (pin "10") (pinfunction "CD+_10") (pintype "passive"))
      (node (ref "IC10") (pin "9") (pinfunction "CLR_9") (pintype "input"))
      (node (ref "IC11") (pin "9") (pinfunction "CLR_9") (pintype "input"))
      (node (ref "IC12") (pin "9") (pinfunction "CLR_9") (pintype "input"))
      (node (ref "IC13") (pin "11") (pinfunction "VDD_11") (pintype "power_in"))
      (node (ref "IC13") (pin "32") (pinfunction "VDD_32") (pintype "power_in"))
      (node (ref "IC14") (pin "3") (pinfunction "~{WP}_3") (pintype "input"))
      (node (ref "IC14") (pin "7") (pinfunction "~{HOLD}_7") (pintype "input"))
      (node (ref "IC14") (pin "8") (pinfunction "VCC_8") (pintype "power_in"))
      (node (ref "IC2") (pin "10") (pinfunction "CD+_10") (pintype "passive"))
      (node (ref "IC3") (pin "9") (pinfunction "CLR_9") (pintype "input"))
      (node (ref "IC4") (pin "9") (pinfunction "CLR_9") (pintype "input"))
      (node (ref "IC5") (pin "9") (pinfunction "CLR_9") (pintype "input"))
      (node (ref "IC6") (pin "9") (pinfunction "CLR_9") (pintype "input"))
      (node (ref "IC7") (pin "9") (pinfunction "CLR_9") (pintype "input"))
      (node (ref "IC8") (pin "9") (pinfunction "CLR_9") (pintype "input"))
      (node (ref "IC9") (pin "9") (pinfunction "CLR_9") (pintype "input"))
      (node (ref "J1") (pin "2") (pinfunction "2_2") (pintype "passive"))
      (node (ref "R17") (pin "2") (pinfunction "2_2") (pintype "passive"))
      (node (ref "SL1") (pin "1") (pinfunction "1_1") (pintype "passive"))
      (node (ref "X1") (pin "1") (pinfunction "1_1") (pintype "passive"))
    )
    (net (code "141") (name "unconnected-(IC13-RA2{slash}AN2-Pad4)") (class "Default")
      (node (ref "IC13") (pin "4") (pinfunction "RA2/AN2_4") (pintype "bidirectional"))
    )
    (net (code "142") (name "unconnected-(IC13-RA3{slash}AN3-Pad5)") (class "Default")
      (node (ref "IC13") (pin "5") (pinfunction "RA3/AN3_5") (pintype "bidirectional"))
    )
    (net (code "143") (name "unconnected-(IC13-RA4{slash}T0CKI-Pad6)") (class "Default")
      (node (ref "IC13") (pin "6") (pinfunction "RA4/T0CKI_6") (pintype "bidirectional"))
    )
    (net (code "144") (name "unconnected-(IC13-RA5{slash}AN4-Pad7)") (class "Default")
      (node (ref "IC13") (pin "7") (pinfunction "RA5/AN4_7") (pintype "bidirectional"))
    )
    (net (code "145") (name "unconnected-(IC13-RC0{slash}T1OSO-Pad15)") (class "Default")
      (node (ref "IC13") (pin "15") (pinfunction "RC0/T1OSO_15") (pintype "bidirectional"))
    )
    (net (code "146") (name "unconnected-(IC13-RC1{slash}T1OSI-Pad16)") (class "Default")
      (node (ref "IC13") (pin "16") (pinfunction "RC1/T1OSI_16") (pintype "bidirectional"))
    )
    (net (code "147") (name "unconnected-(IC13-RC2{slash}CCP1-Pad17)") (class "Default")
      (node (ref "IC13") (pin "17") (pinfunction "RC2/CCP1_17") (pintype "bidirectional"))
    )
    (net (code "148") (name "unconnected-(IC13-RE0{slash}~{RD{slash}AN5}-Pad8)") (class "Default")
      (node (ref "IC13") (pin "8") (pinfunction "RE0/~{RD/AN5}_8") (pintype "bidirectional"))
    )
    (net (code "149") (name "unconnected-(IC13-RE1{slash}~{WR{slash}AN6}-Pad9)") (class "Default")
      (node (ref "IC13") (pin "9") (pinfunction "RE1/~{WR/AN6}_9") (pintype "bidirectional"))
    )
    (net (code "150") (name "unconnected-(IC13-RE2{slash}~{CS{slash}AN7}-Pad10)") (class "Default")
      (node (ref "IC13") (pin "10") (pinfunction "RE2/~{CS/AN7}_10") (pintype "bidirectional"))
    )
    (net (code "151") (name "unconnected-(IC14-~{CS}-Pad1)") (class "Default")
      (node (ref "IC14") (pin "1") (pinfunction "~{CS}_1") (pintype "input"))
    )
  )
)
